# PDNode-600_Pro.net
KiCad netlist of a schematic drawn in EAGLE
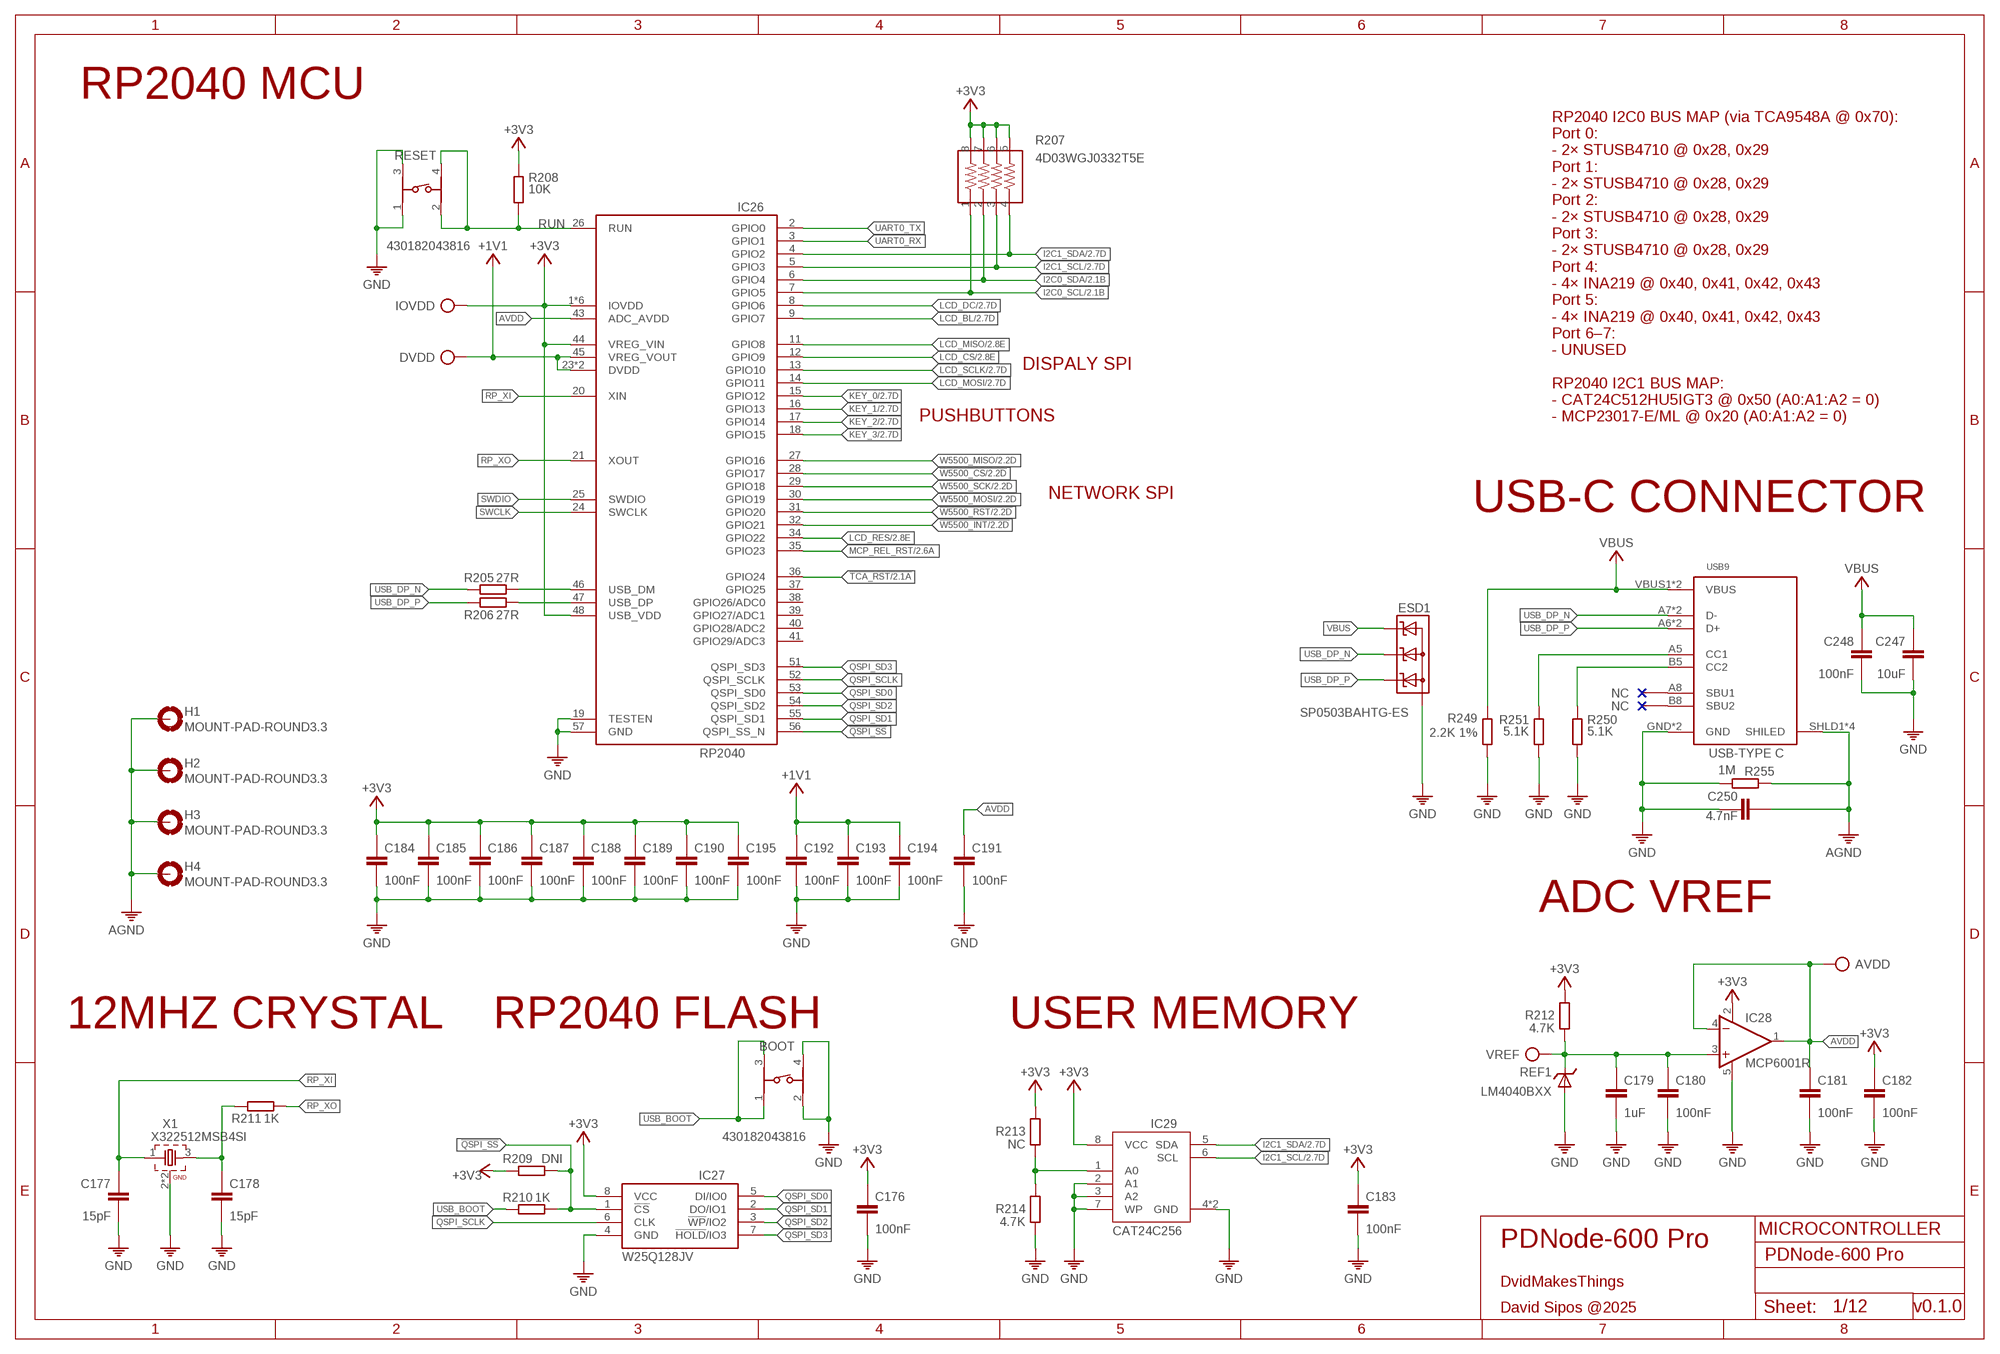
[diagram p0: schematic, sheet 1]
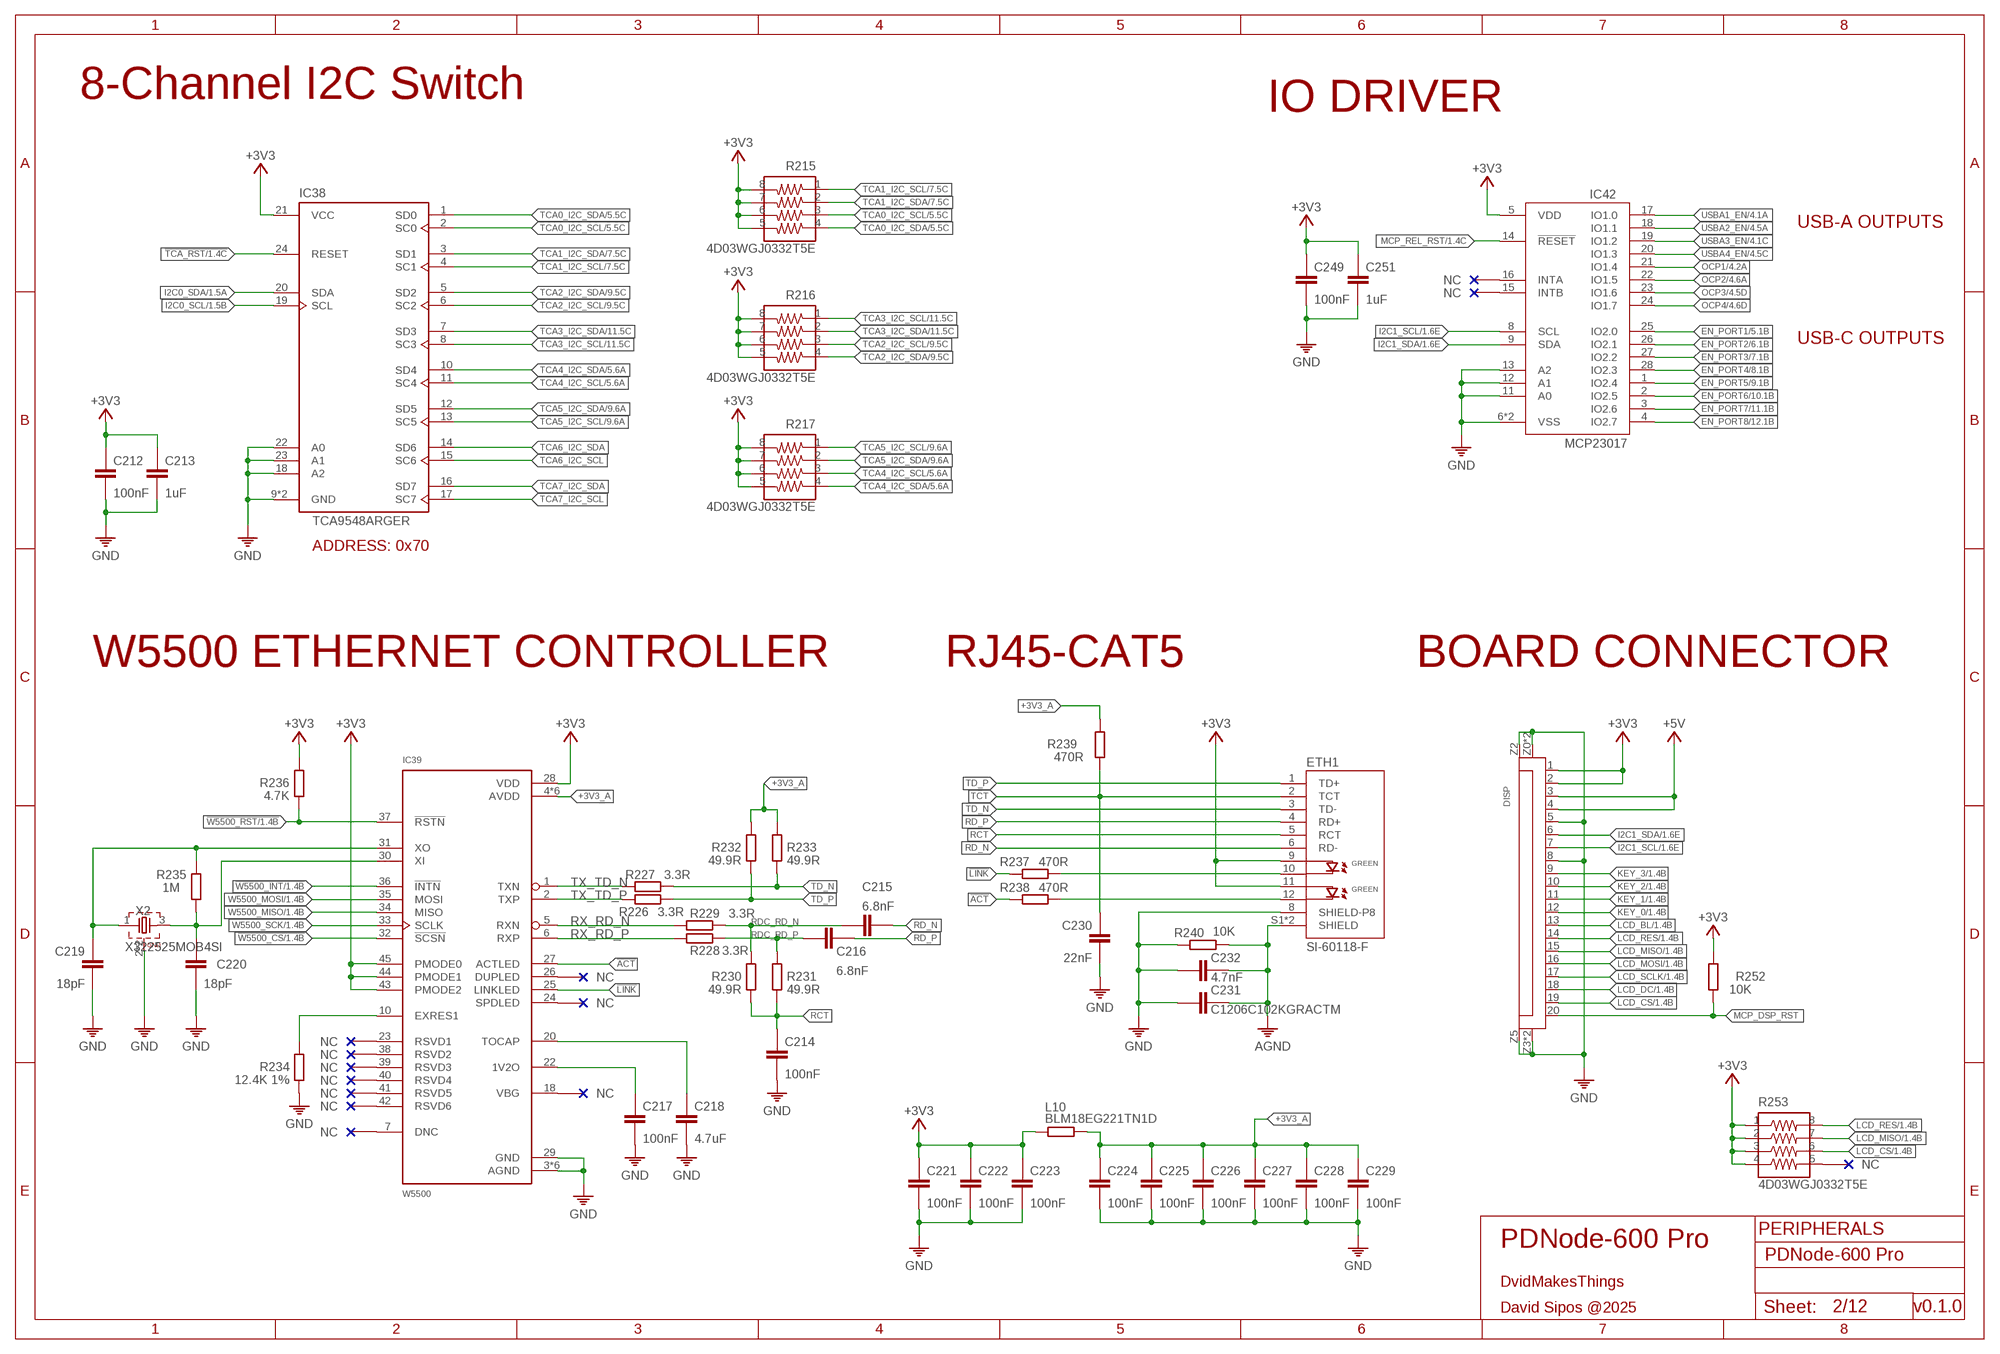
[diagram p1: schematic, sheet 2]
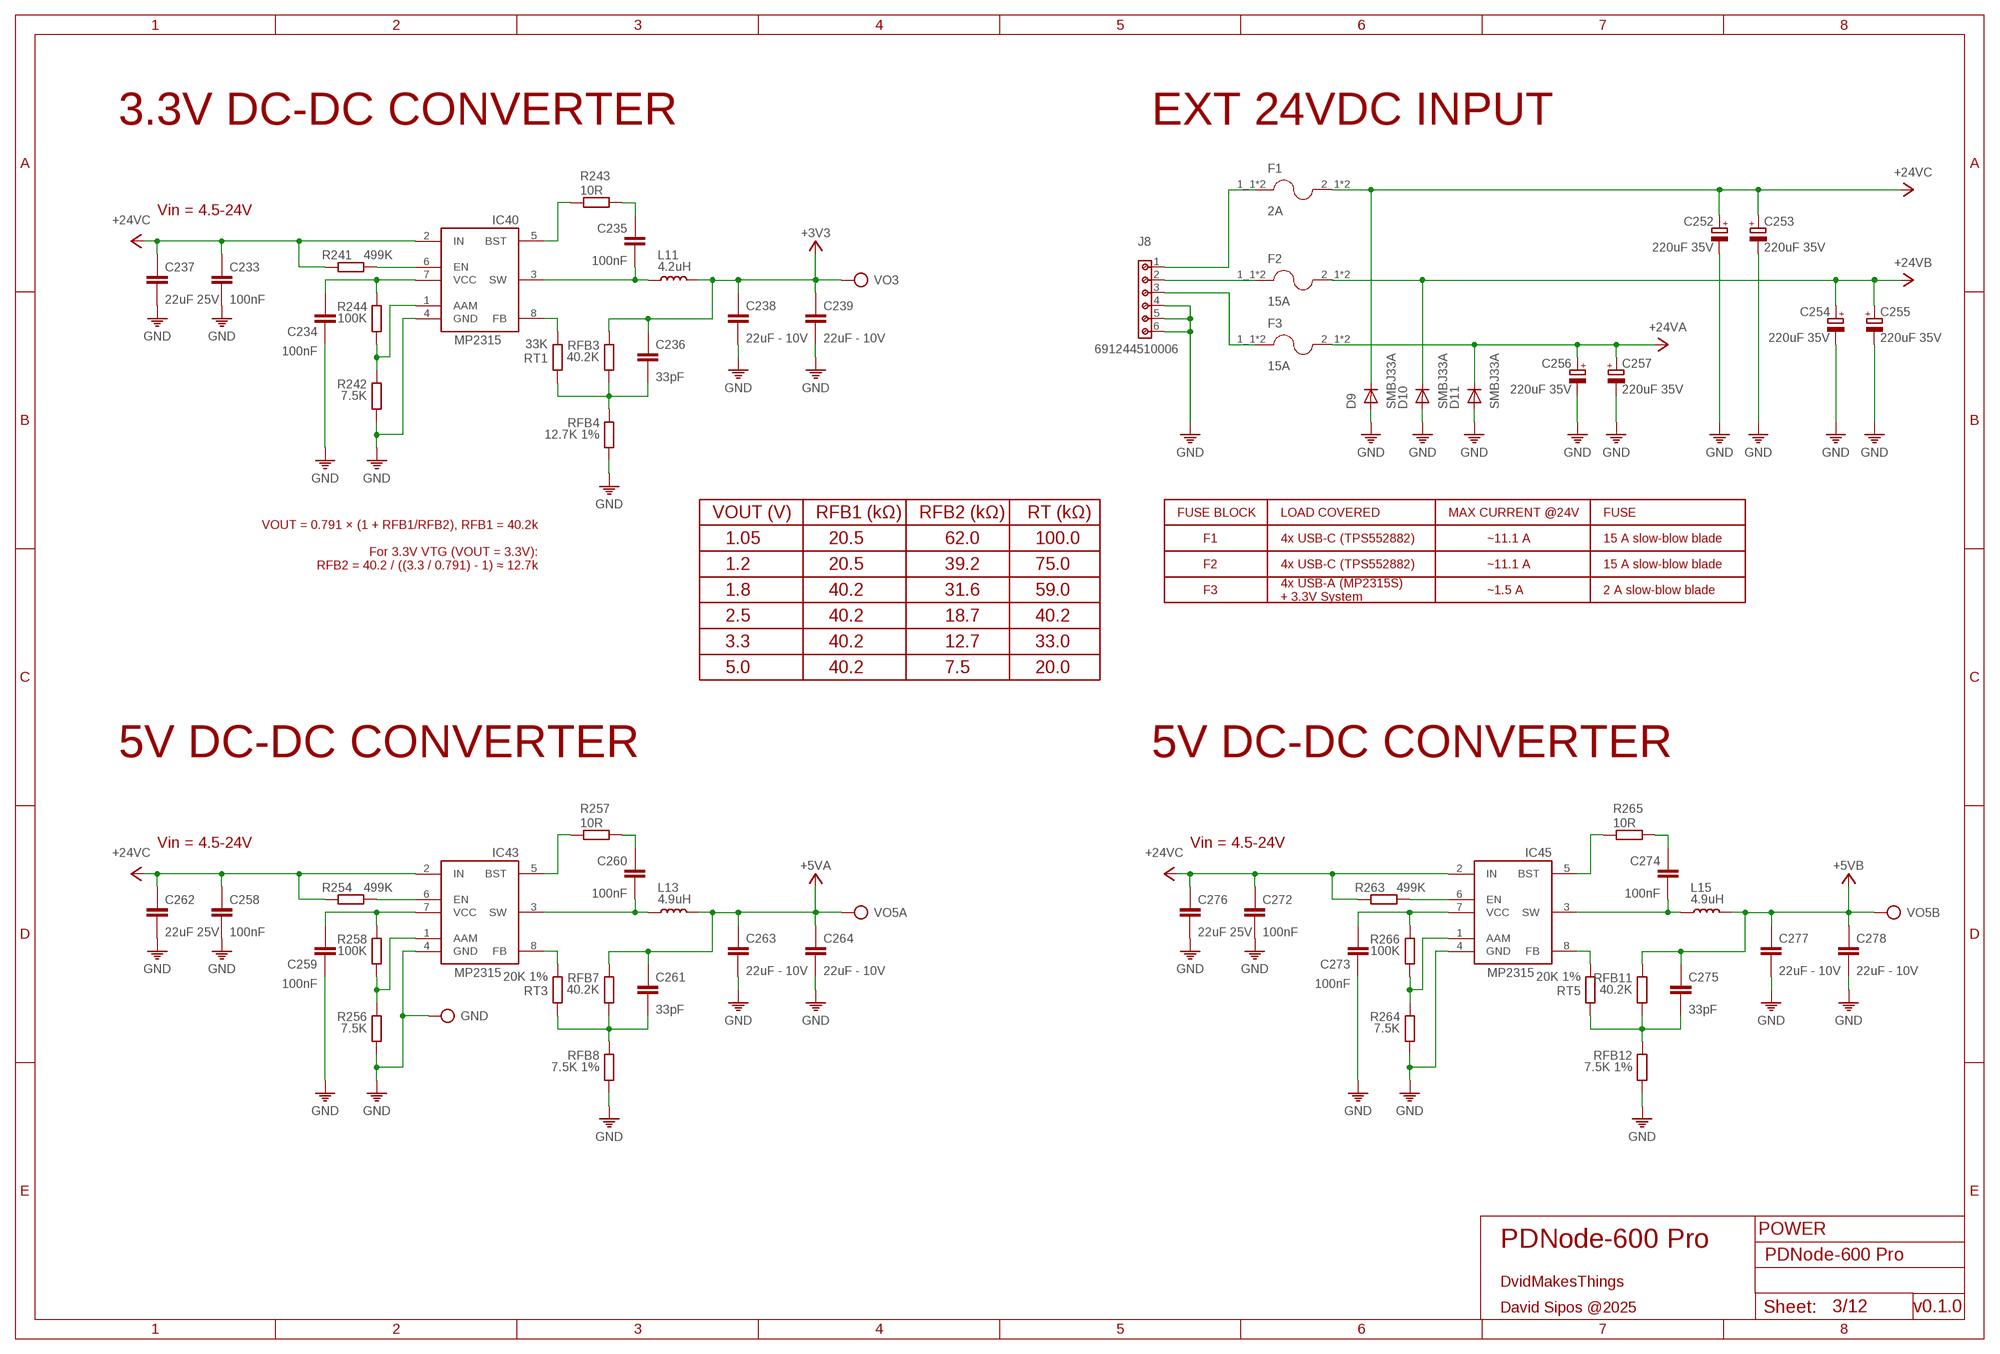
[diagram p2: schematic, sheet 3]
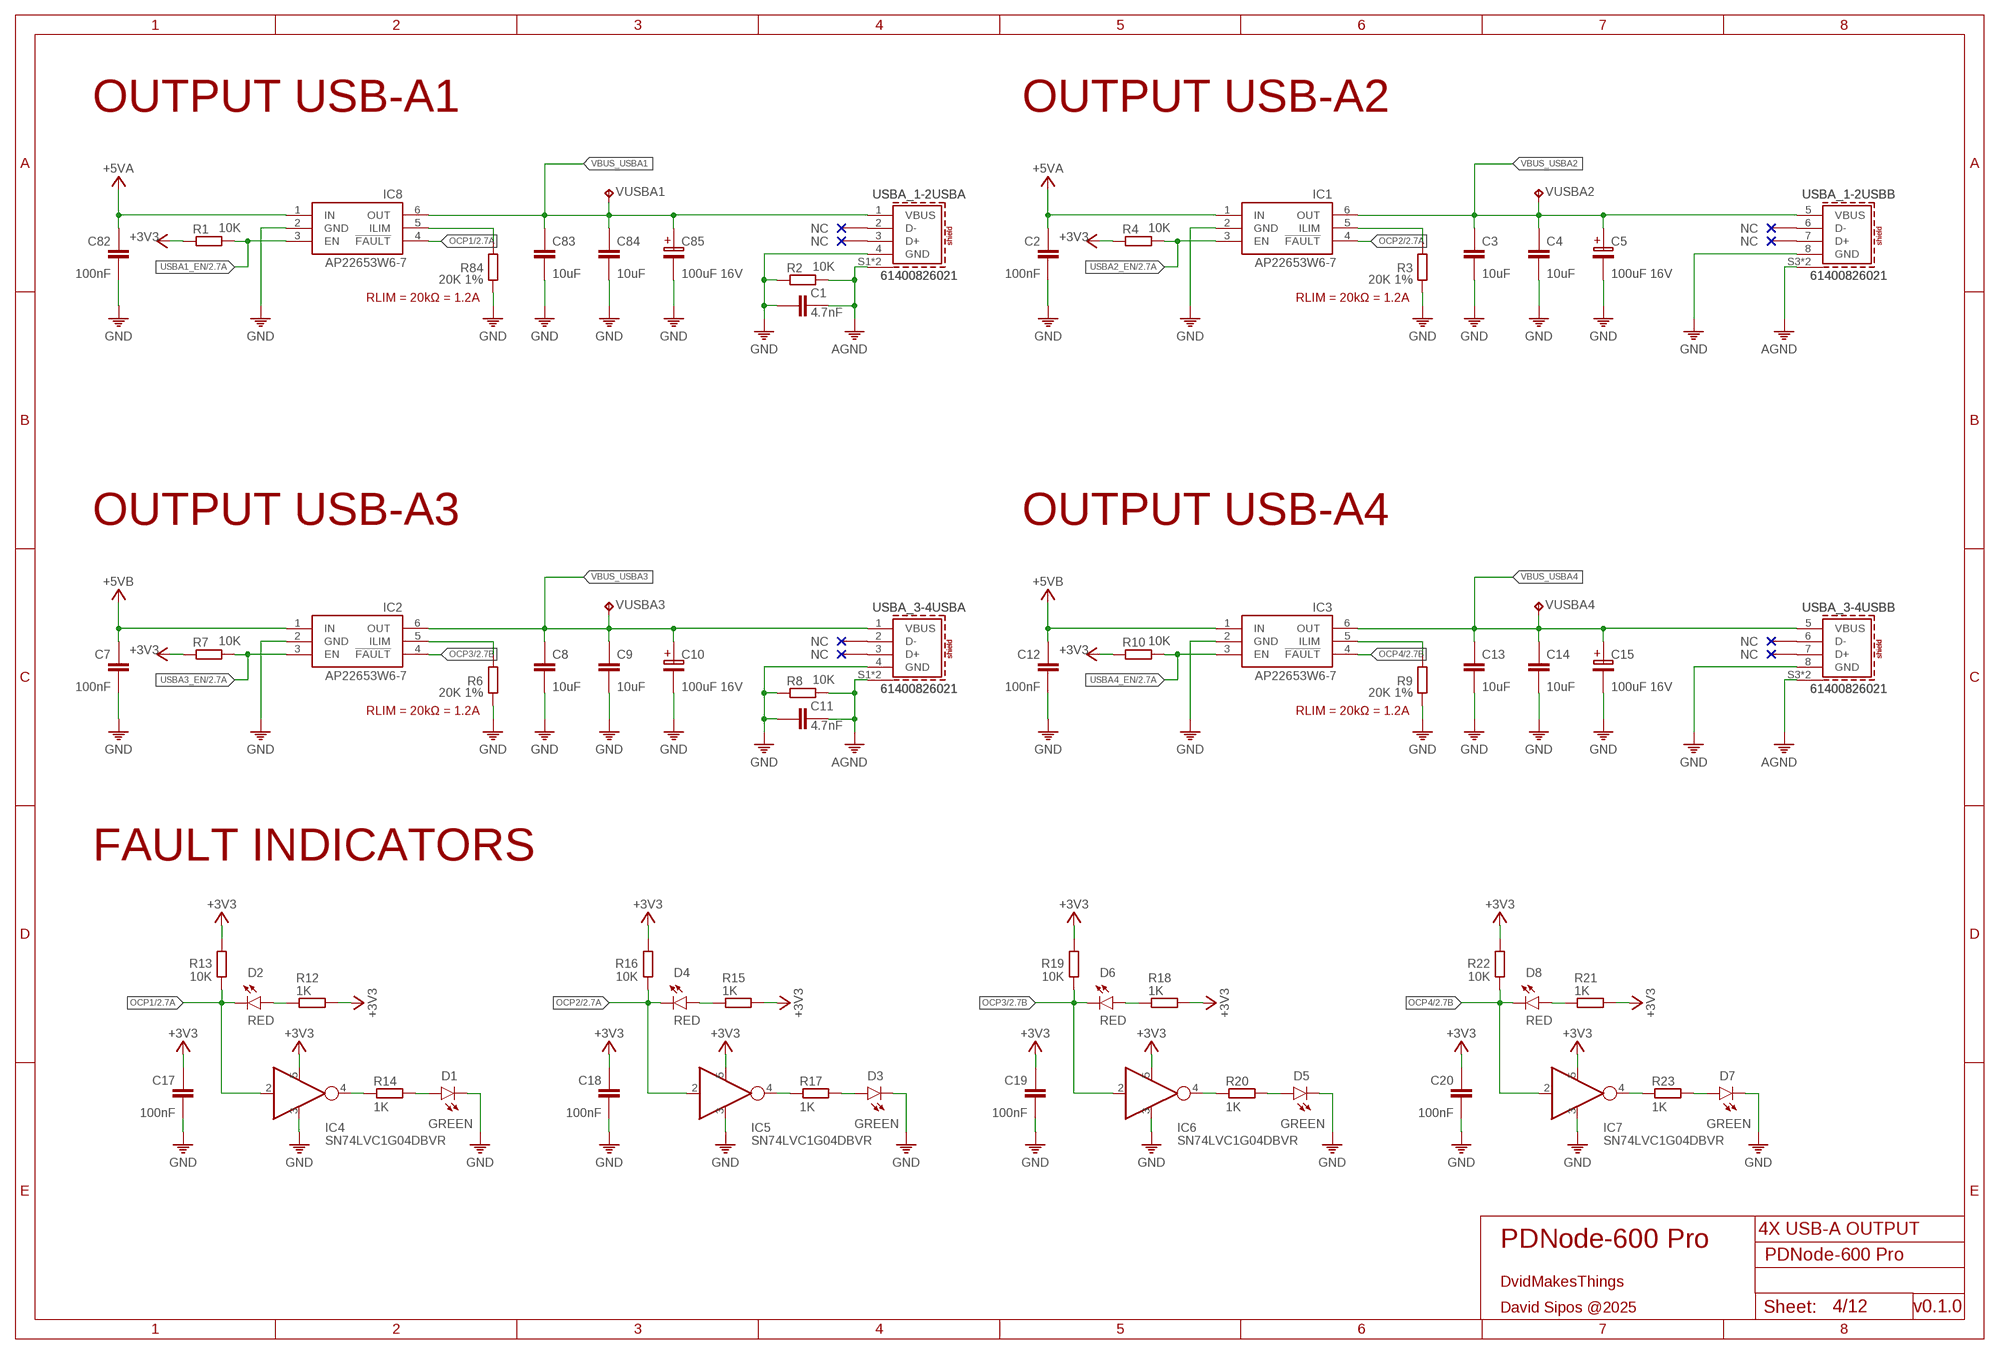
[diagram p3: schematic, sheet 4]
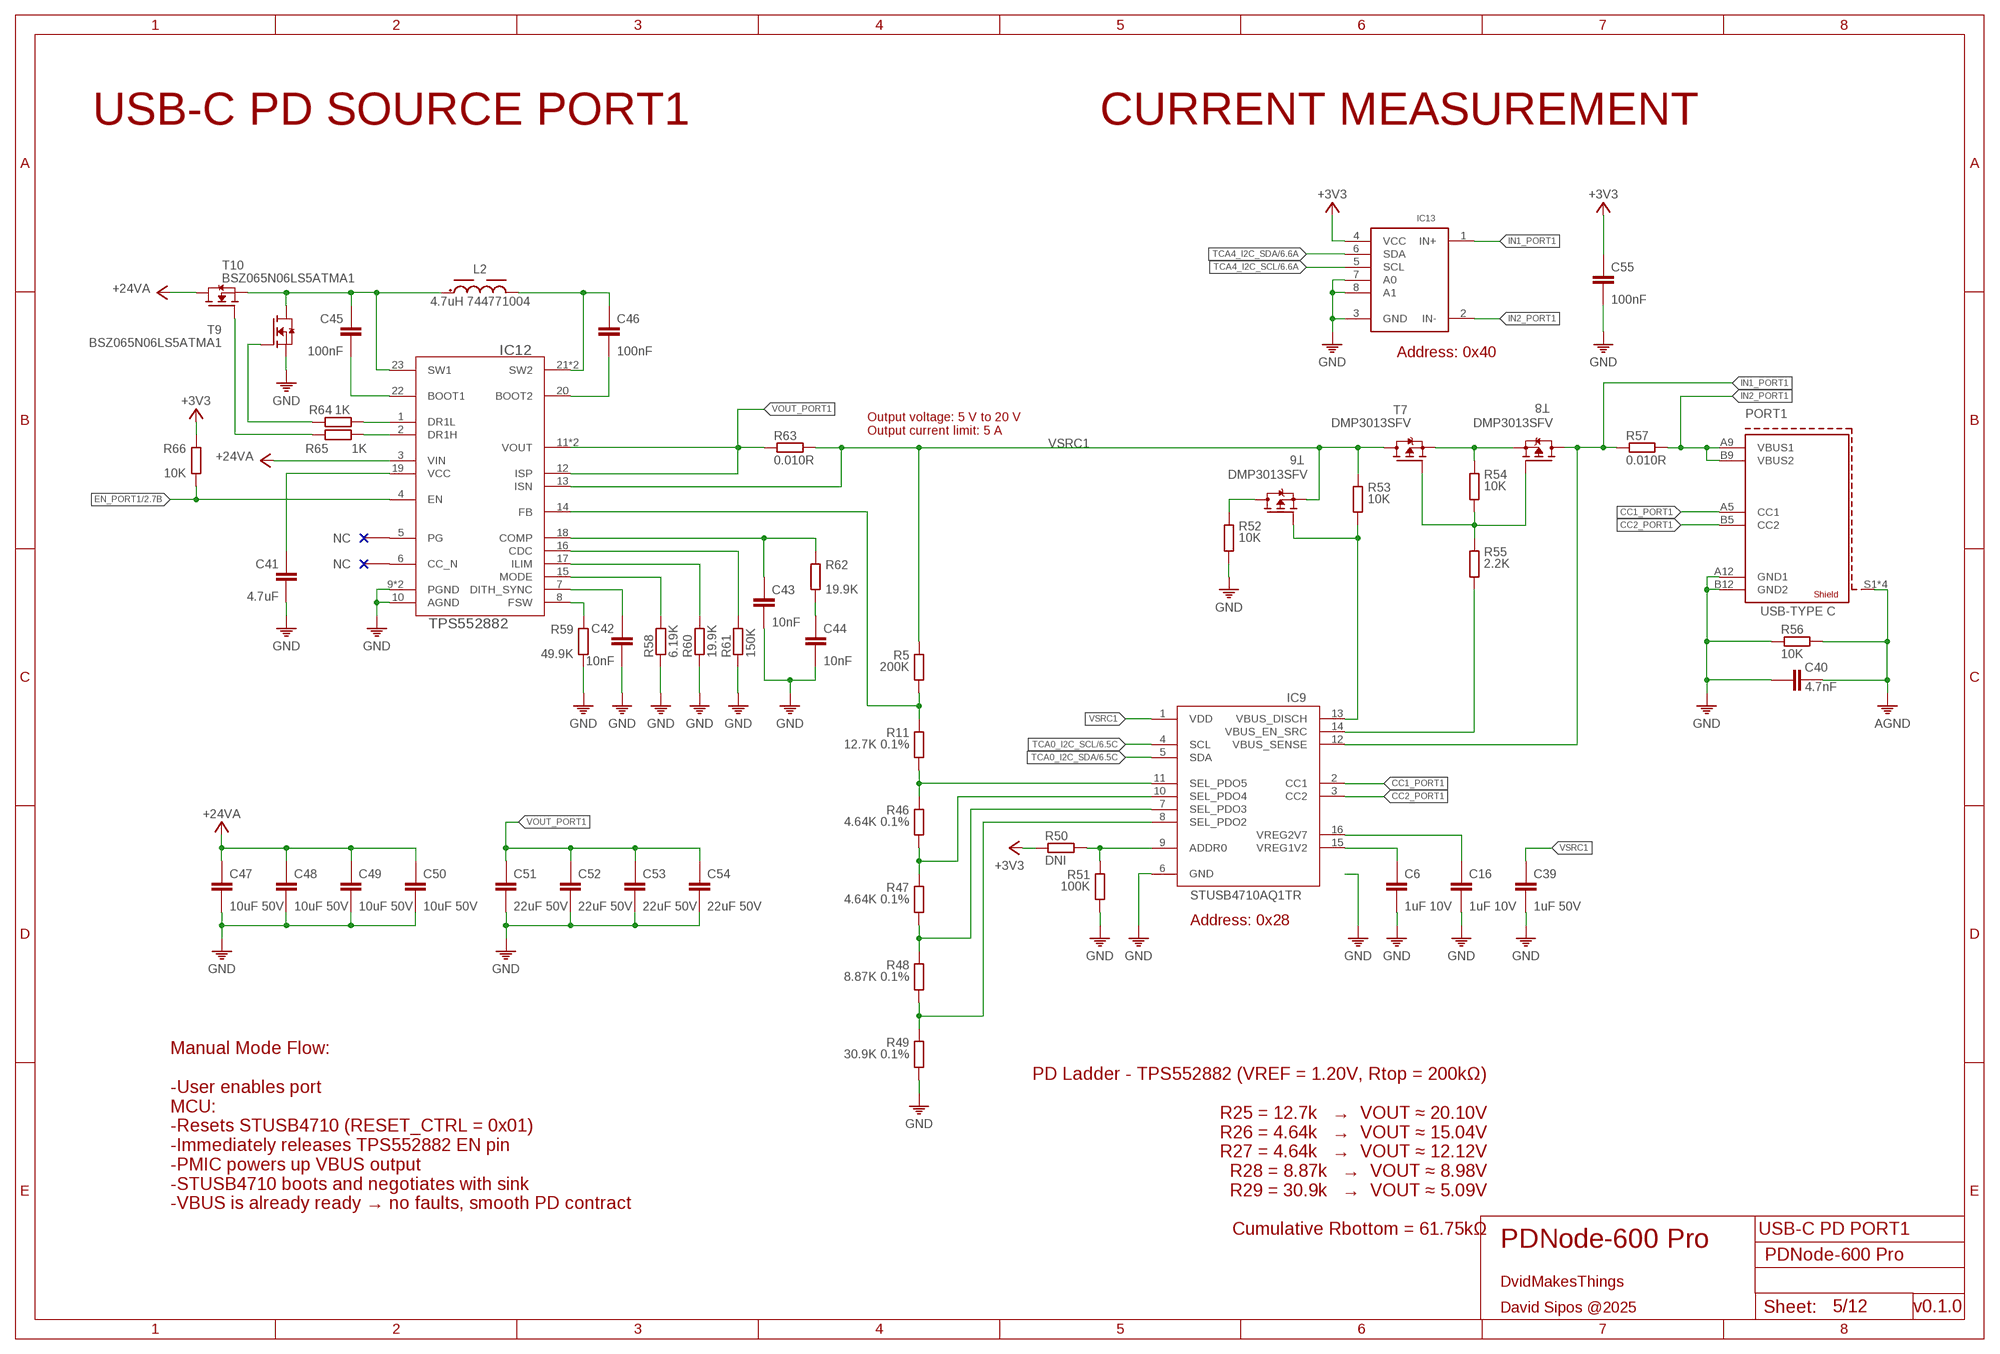
[diagram p4: schematic, sheet 5]
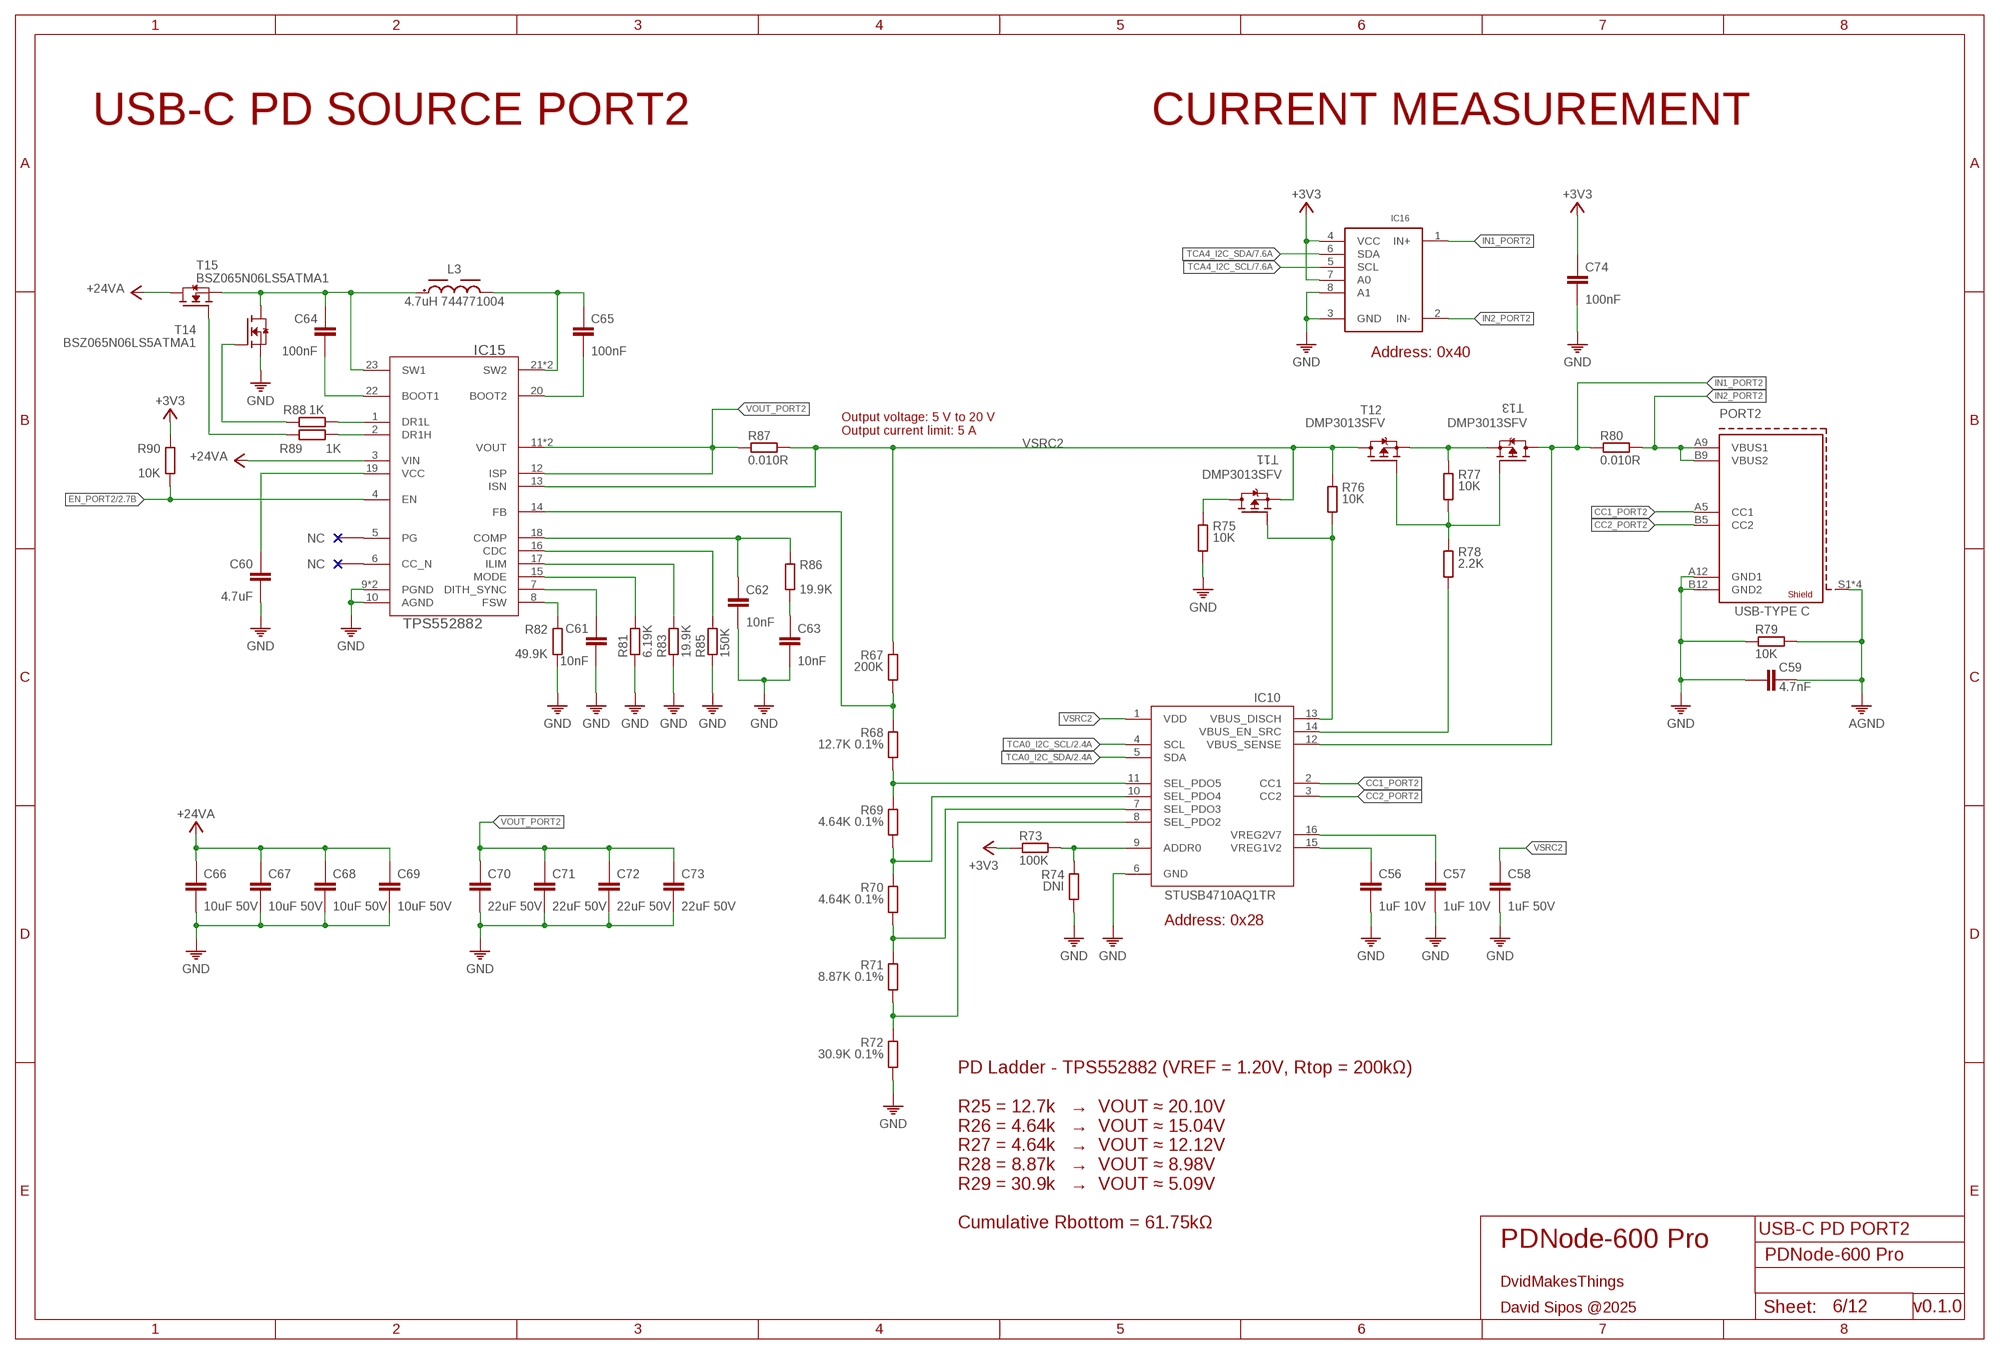
[diagram p5: schematic, sheet 6]
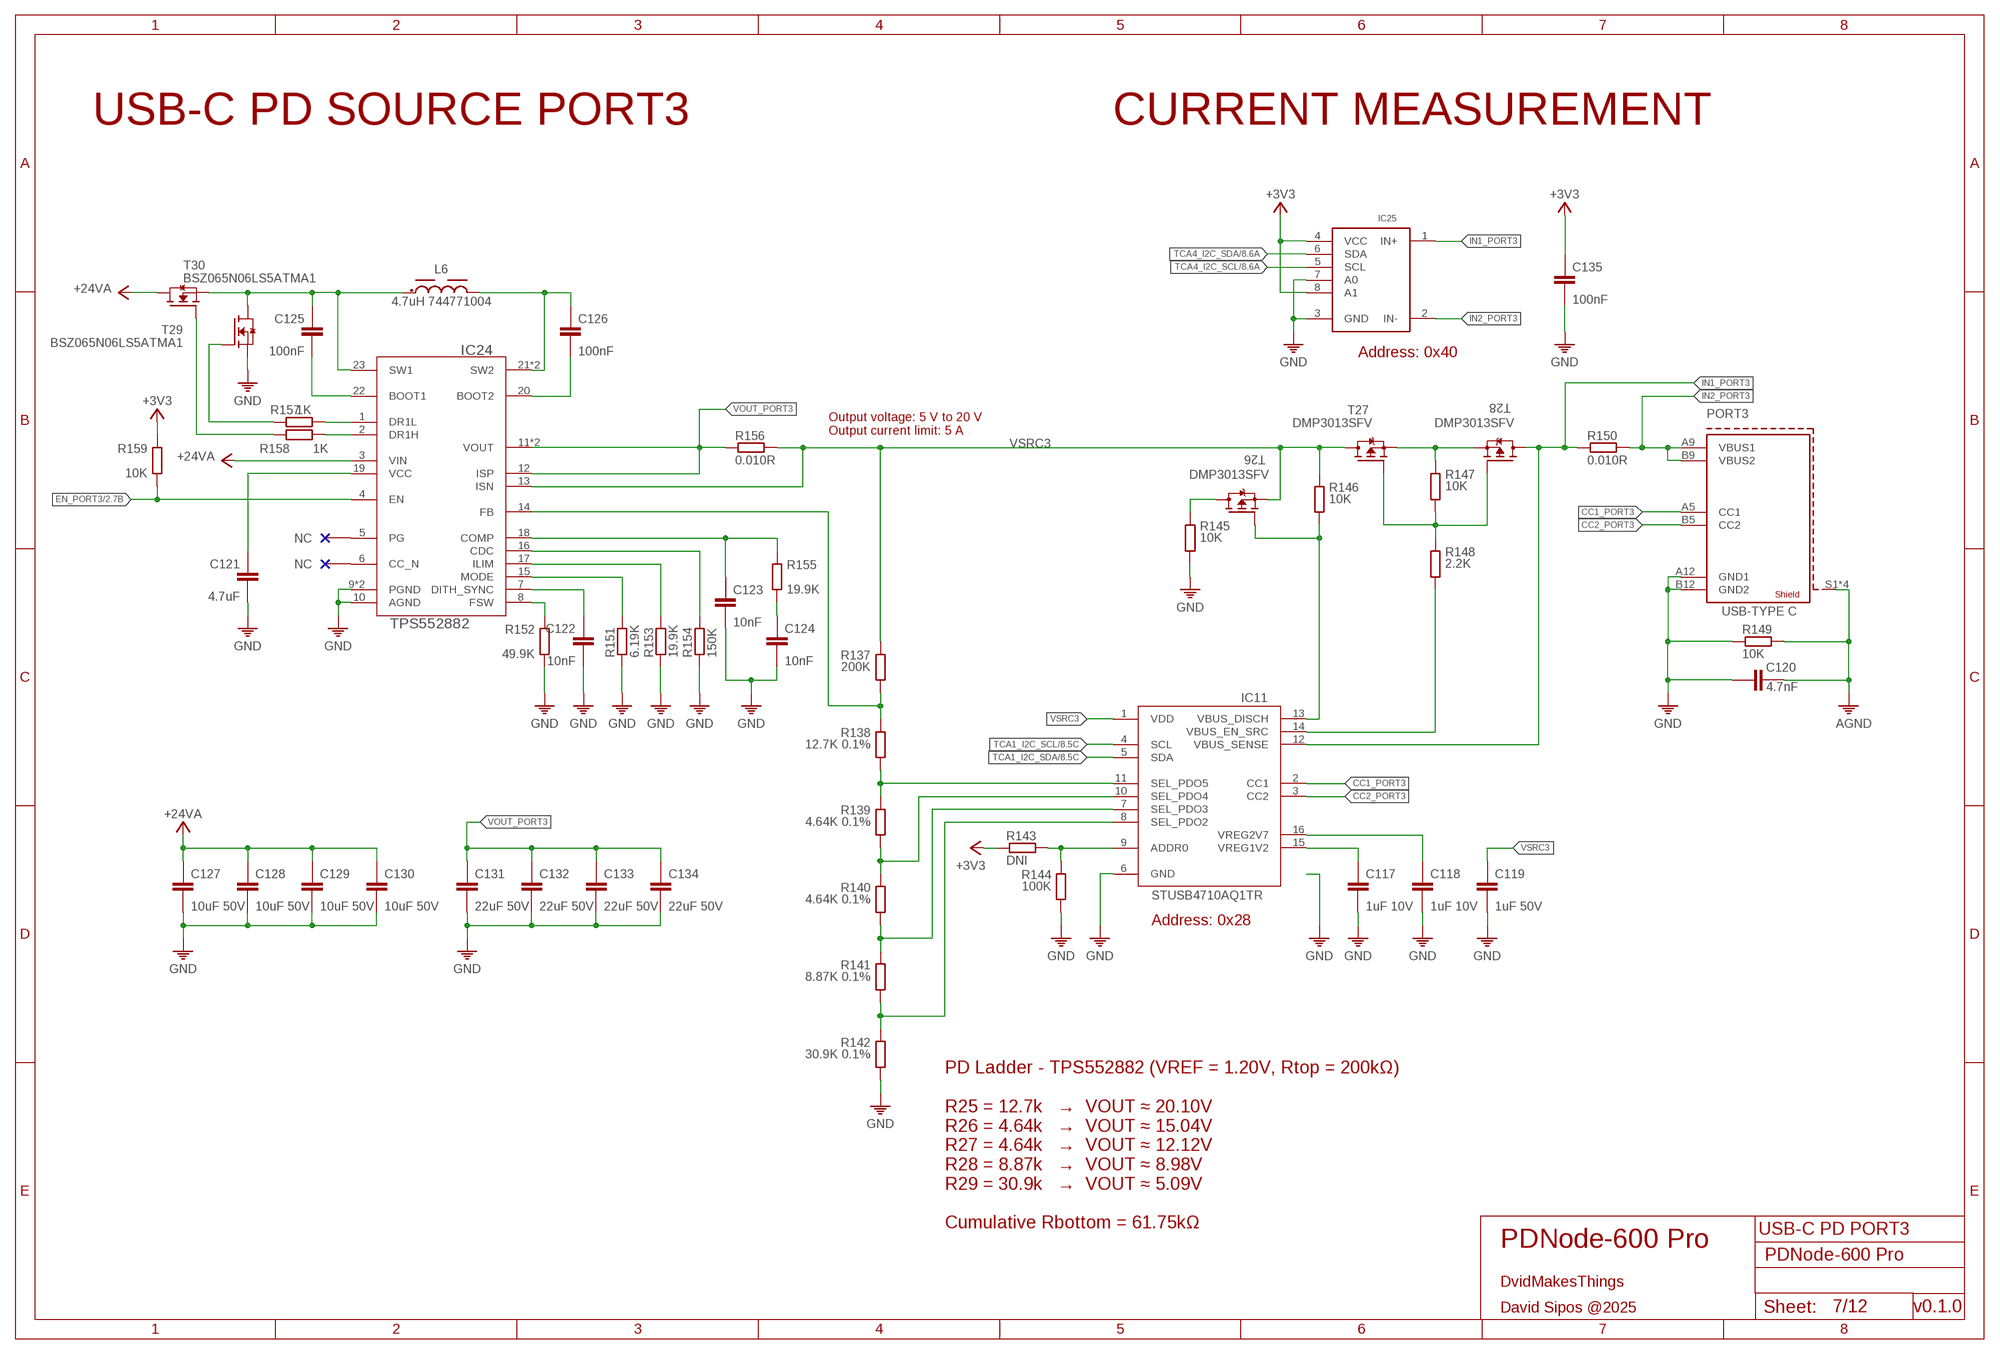
[diagram p6: schematic, sheet 7]
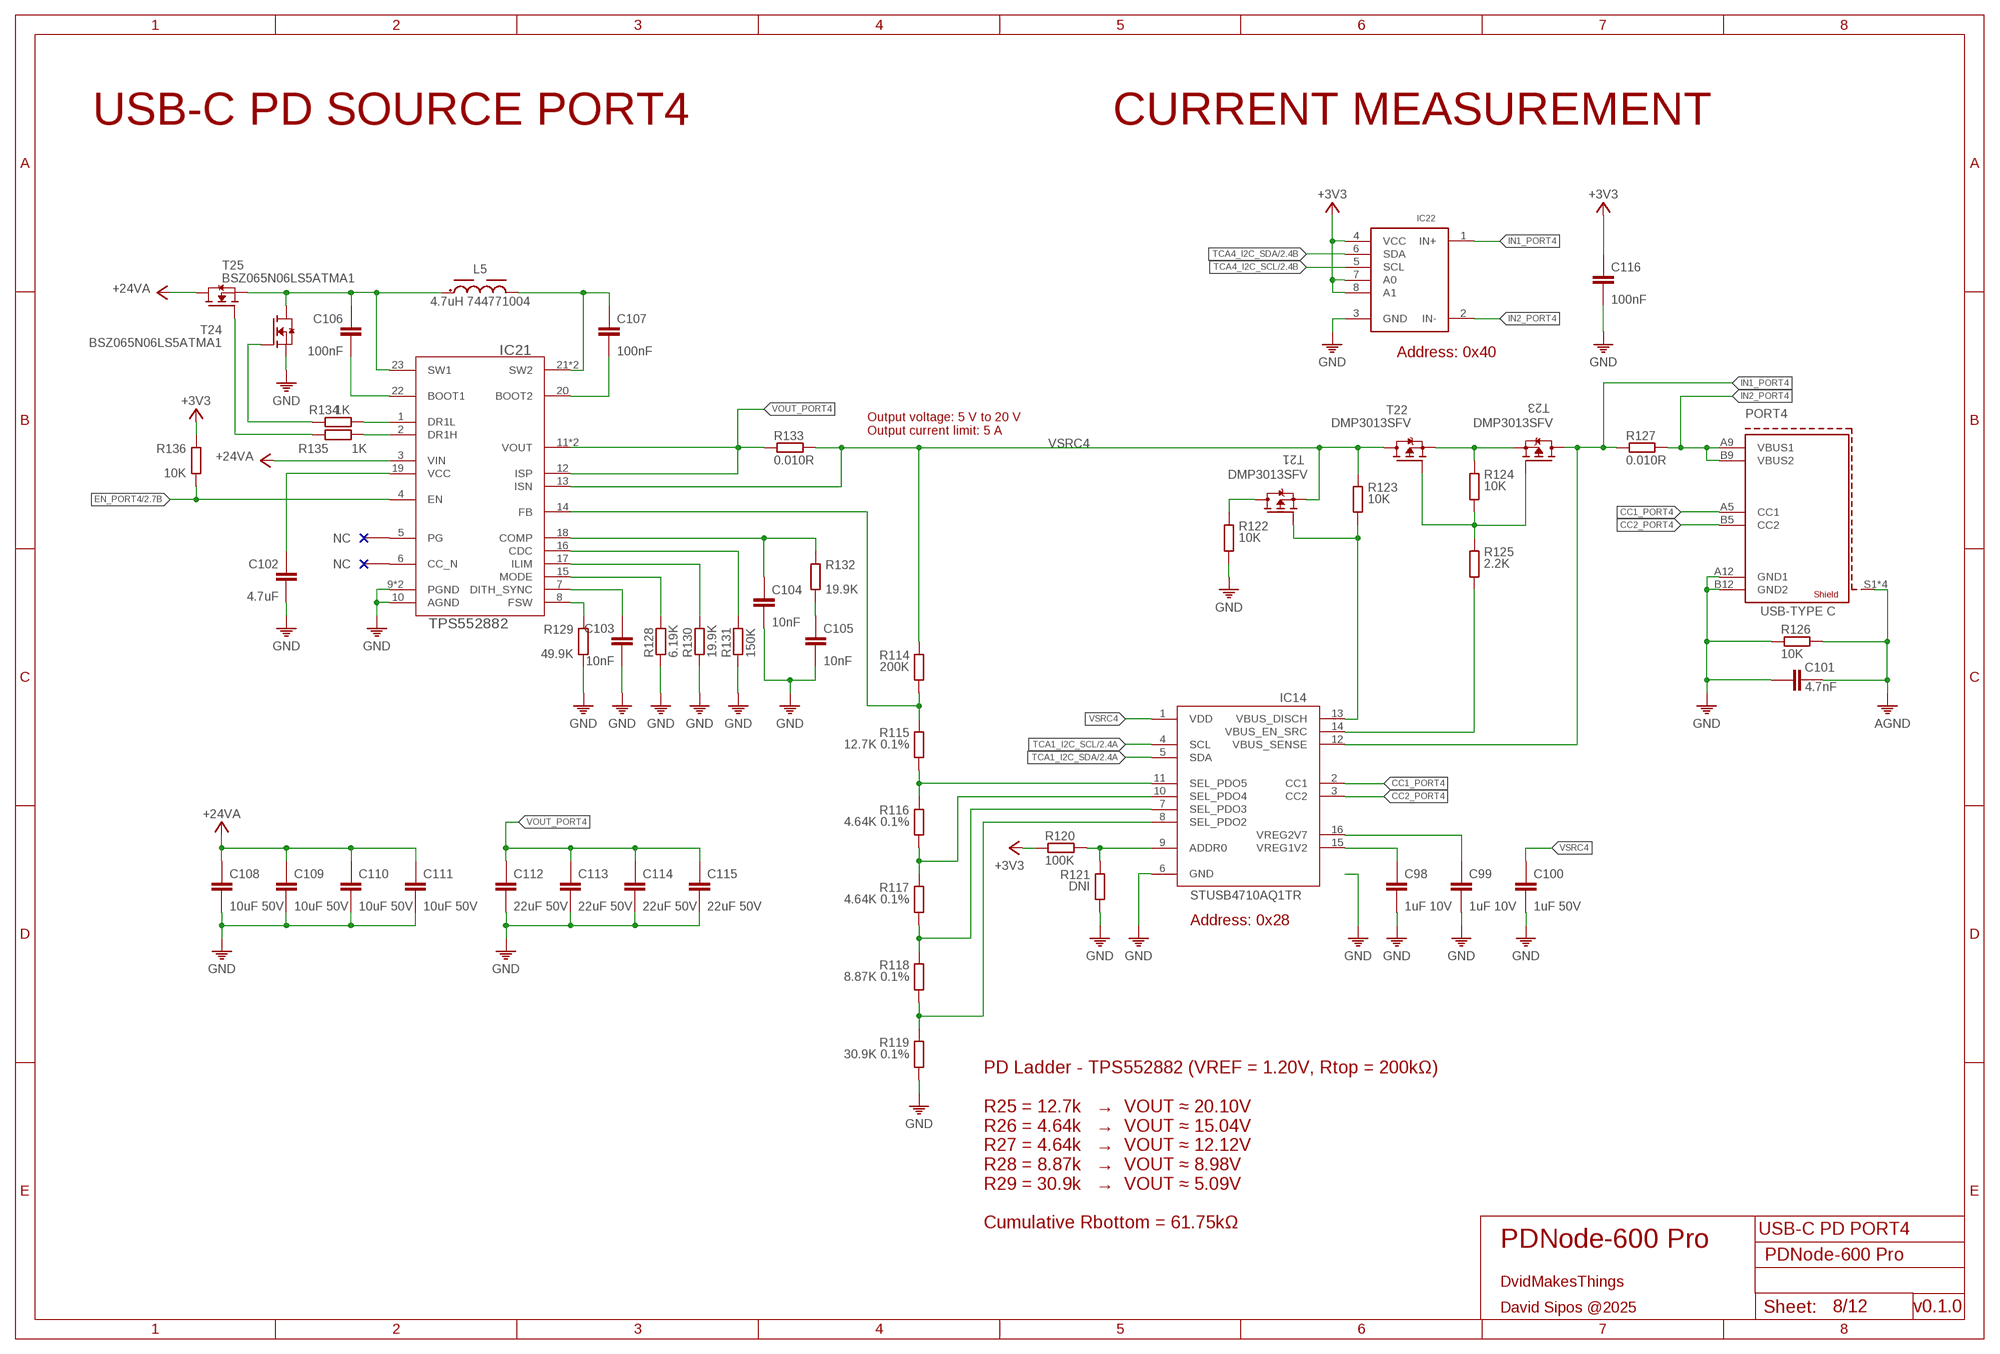
[diagram p7: schematic, sheet 8]
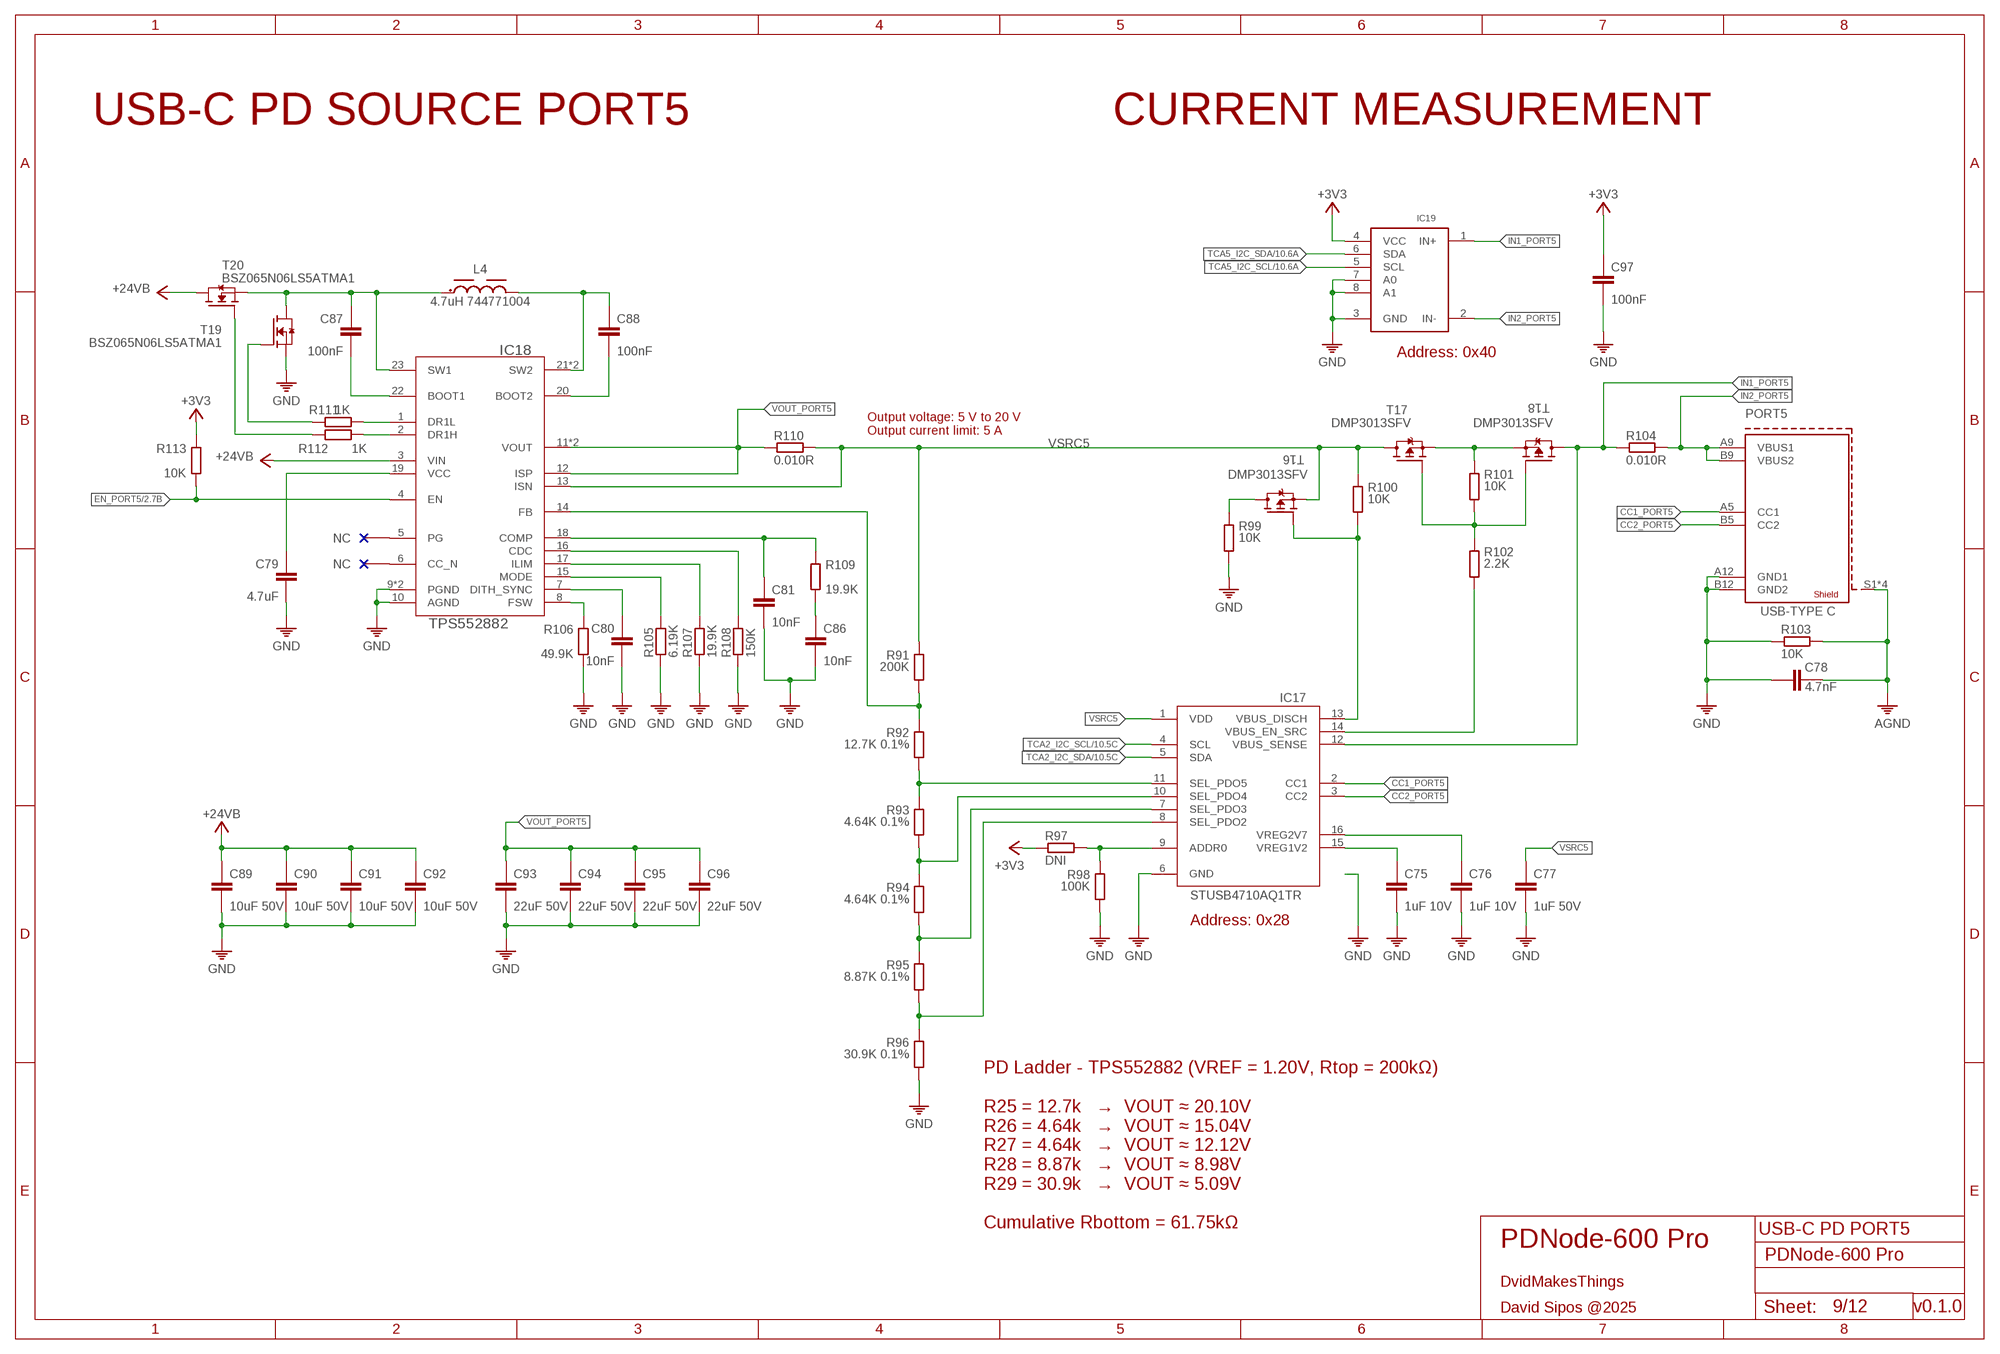
[diagram p8: schematic, sheet 9]
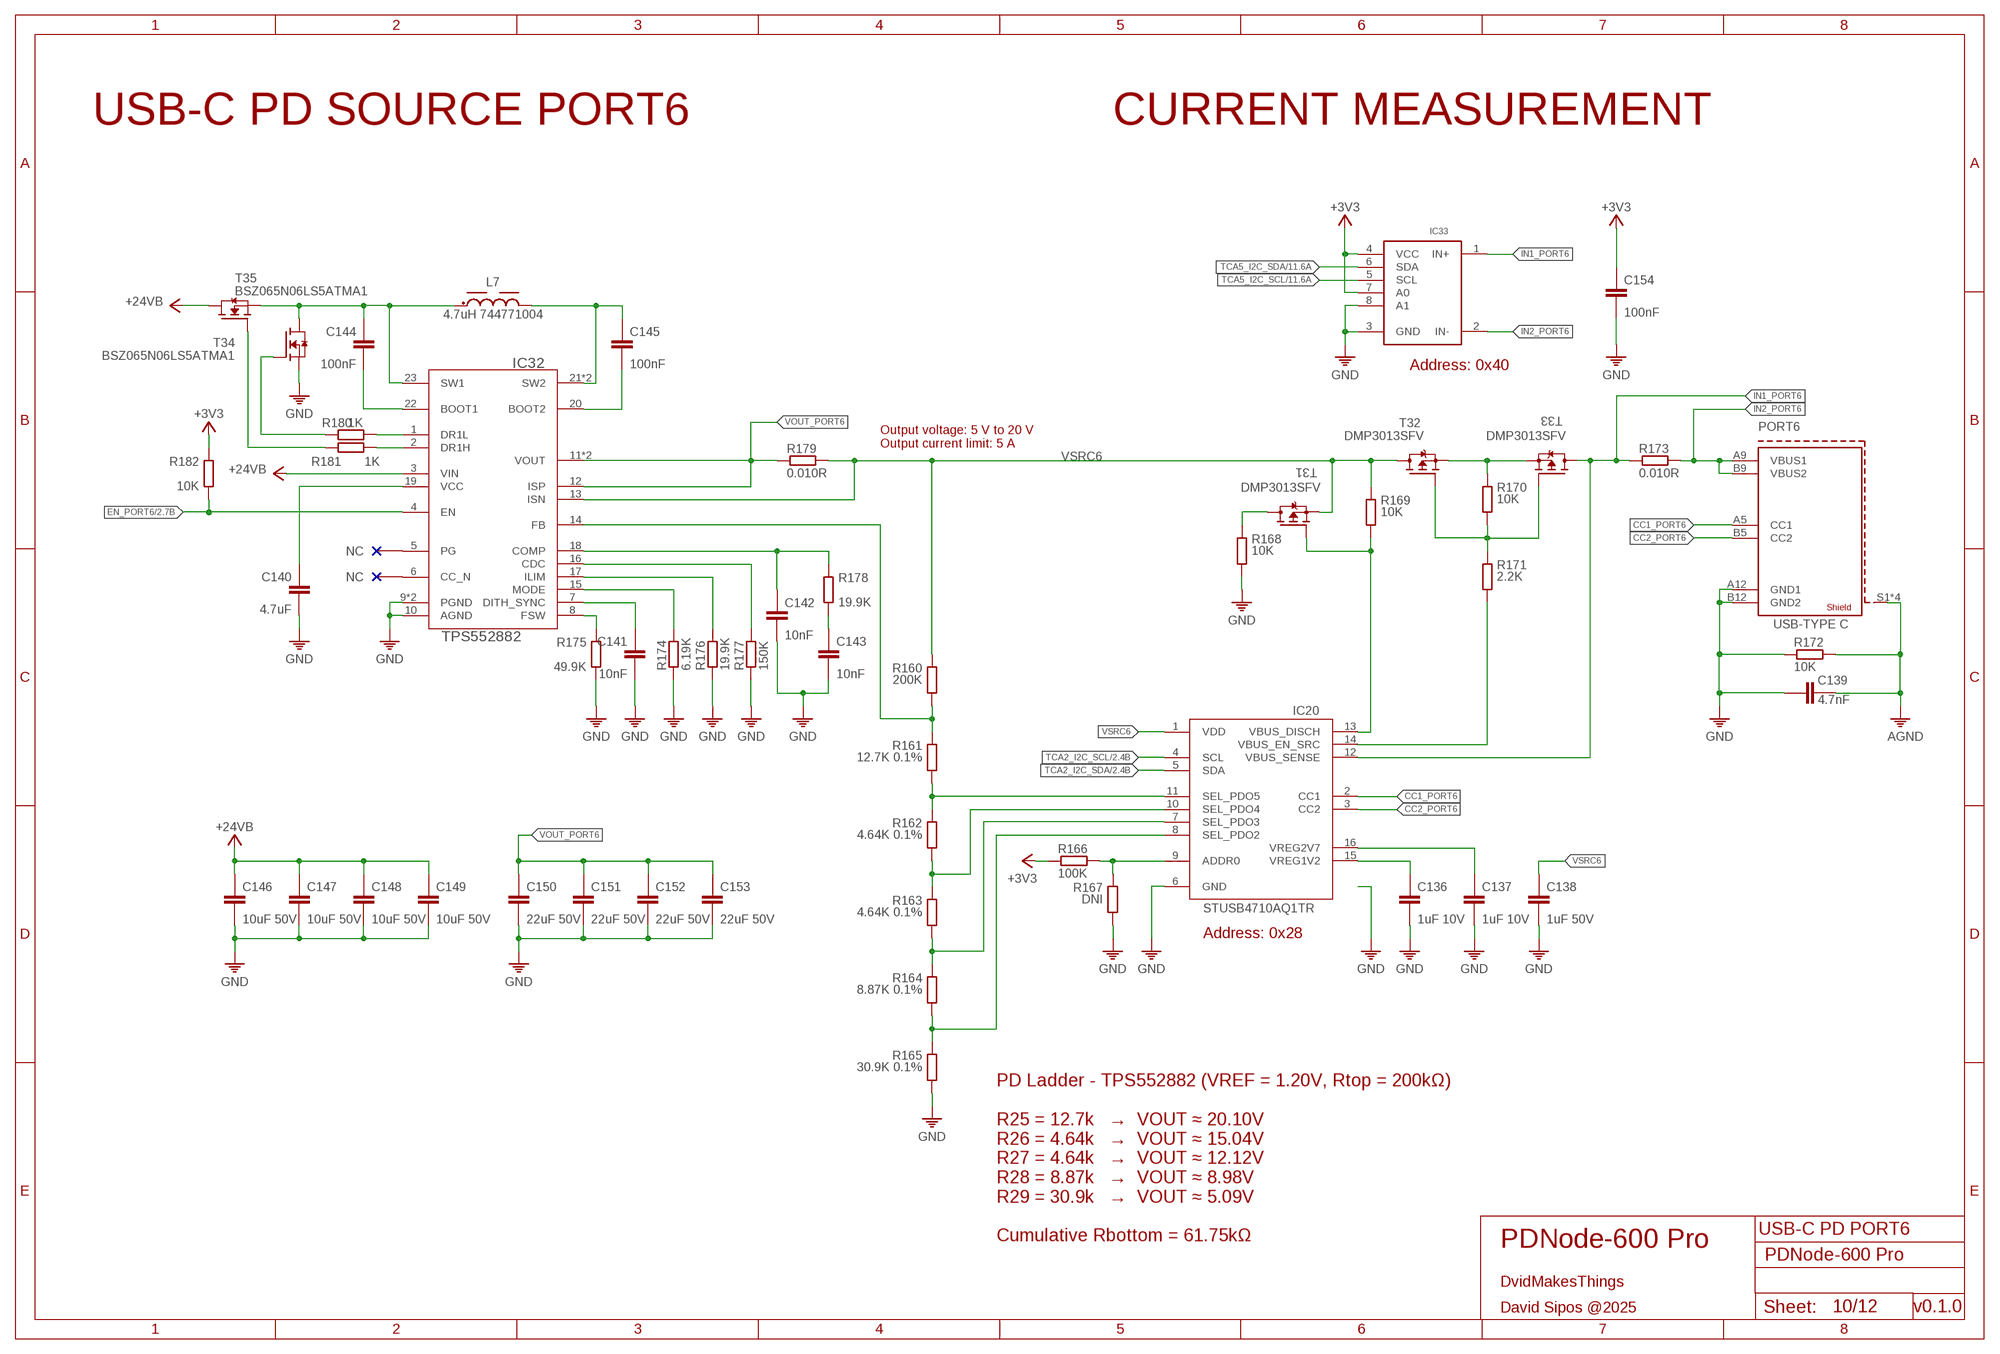
[diagram p9: schematic, sheet 10]
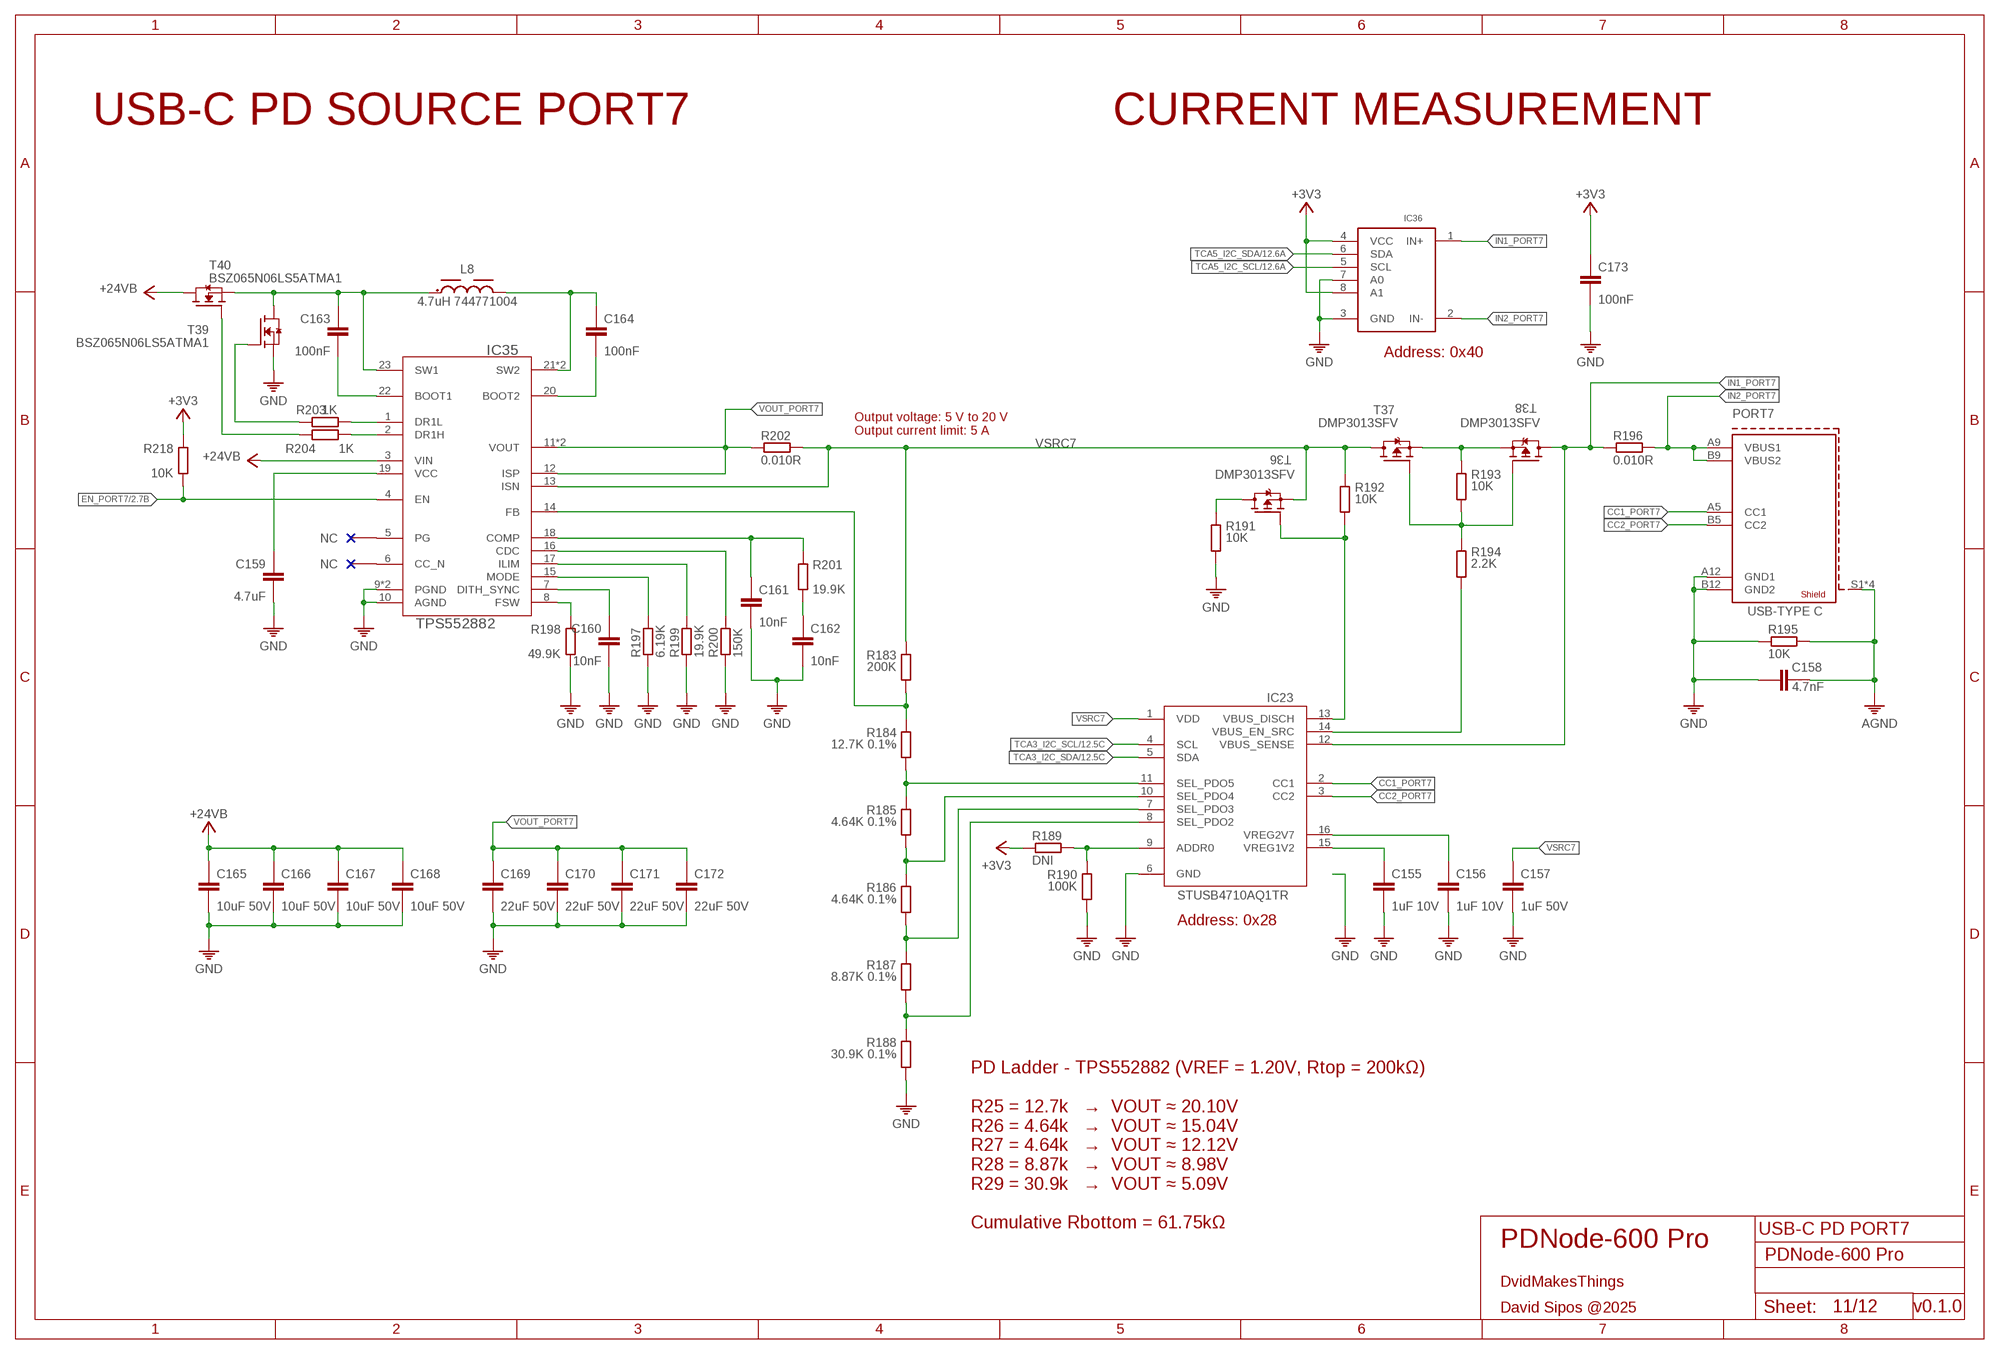
[diagram p10: schematic, sheet 11]
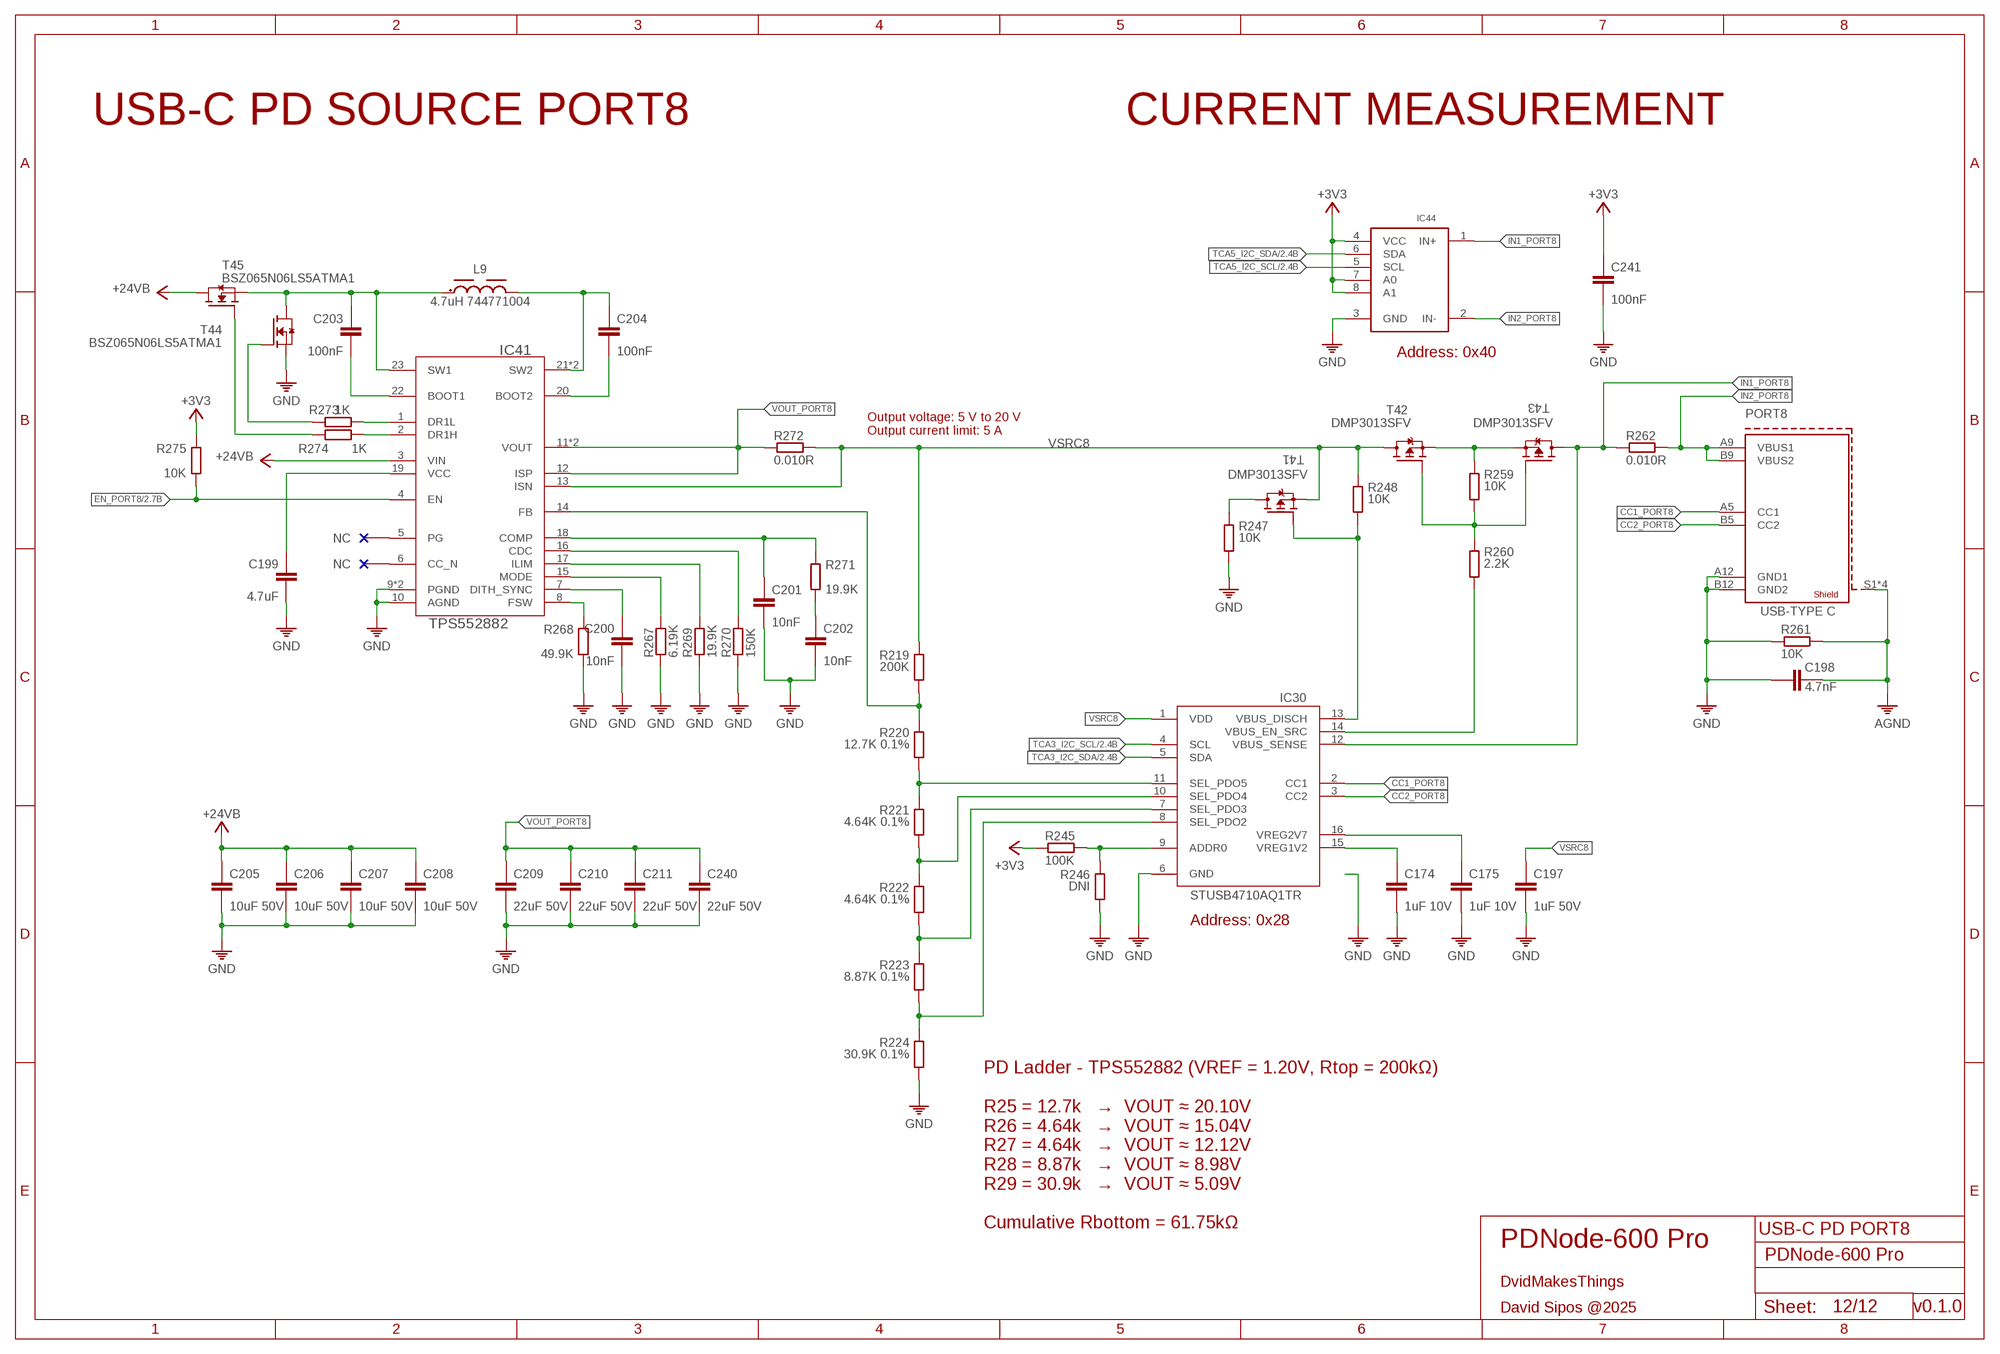
[diagram p11: schematic, sheet 12]

(export (version "E")
  (design (tool "Eeschema 10.0.6"))
  (components
    (comp (ref "AVDD")
      (value "TP")
      (footprint "eagle-import:TP")
      (libsource (lib "eagle-import") (part "TP"))
    )
    (comp (ref "BOOT")
      (value "430182043816")
      (footprint "eagle-import:430182050816")
      (libsource (lib "eagle-import") (part "430182050816"))
    )
    (comp (ref "C176")
      (value "100nF")
      (footprint "eagle-import:0201")
      (libsource (lib "eagle-import") (part "C-0201"))
    )
    (comp (ref "C177")
      (value "15pF")
      (footprint "eagle-import:0201")
      (libsource (lib "eagle-import") (part "C-0201"))
    )
    (comp (ref "C178")
      (value "15pF")
      (footprint "eagle-import:0201")
      (libsource (lib "eagle-import") (part "C-0201"))
    )
    (comp (ref "C179")
      (value "1uF")
      (footprint "eagle-import:C0402")
      (libsource (lib "eagle-import") (part "C-0402"))
    )
    (comp (ref "C180")
      (value "100nF")
      (footprint "eagle-import:0201")
      (libsource (lib "eagle-import") (part "C-0201"))
    )
    (comp (ref "C181")
      (value "100nF")
      (footprint "eagle-import:0201")
      (libsource (lib "eagle-import") (part "C-0201"))
    )
    (comp (ref "C182")
      (value "100nF")
      (footprint "eagle-import:0201")
      (libsource (lib "eagle-import") (part "C-0201"))
    )
    (comp (ref "C183")
      (value "100nF")
      (footprint "eagle-import:0201")
      (libsource (lib "eagle-import") (part "C-0201"))
    )
    (comp (ref "C184")
      (value "100nF")
      (footprint "eagle-import:0201")
      (libsource (lib "eagle-import") (part "C-0201"))
    )
    (comp (ref "C185")
      (value "100nF")
      (footprint "eagle-import:0201")
      (libsource (lib "eagle-import") (part "C-0201"))
    )
    (comp (ref "C186")
      (value "100nF")
      (footprint "eagle-import:0201")
      (libsource (lib "eagle-import") (part "C-0201"))
    )
    (comp (ref "C187")
      (value "100nF")
      (footprint "eagle-import:0201")
      (libsource (lib "eagle-import") (part "C-0201"))
    )
    (comp (ref "C188")
      (value "100nF")
      (footprint "eagle-import:0201")
      (libsource (lib "eagle-import") (part "C-0201"))
    )
    (comp (ref "C189")
      (value "100nF")
      (footprint "eagle-import:0201")
      (libsource (lib "eagle-import") (part "C-0201"))
    )
    (comp (ref "C190")
      (value "100nF")
      (footprint "eagle-import:0201")
      (libsource (lib "eagle-import") (part "C-0201"))
    )
    (comp (ref "C191")
      (value "100nF")
      (footprint "eagle-import:0201")
      (libsource (lib "eagle-import") (part "C-0201"))
    )
    (comp (ref "C192")
      (value "100nF")
      (footprint "eagle-import:0201")
      (libsource (lib "eagle-import") (part "C-0201"))
    )
    (comp (ref "C193")
      (value "100nF")
      (footprint "eagle-import:0201")
      (libsource (lib "eagle-import") (part "C-0201"))
    )
    (comp (ref "C194")
      (value "100nF")
      (footprint "eagle-import:0201")
      (libsource (lib "eagle-import") (part "C-0201"))
    )
    (comp (ref "C195")
      (value "100nF")
      (footprint "eagle-import:0201")
      (libsource (lib "eagle-import") (part "C-0201"))
    )
    (comp (ref "C247")
      (value "10uF")
      (footprint "eagle-import:0805")
      (libsource (lib "eagle-import") (part "C0805"))
    )
    (comp (ref "C248")
      (value "100nF")
      (footprint "eagle-import:0402")
      (libsource (lib "eagle-import") (part "C0402"))
    )
    (comp (ref "C250")
      (value "4.7nF")
      (footprint "eagle-import:C0402")
      (libsource (lib "eagle-import") (part "C-0402"))
    )
    (comp (ref "DVDD")
      (value "TP")
      (footprint "eagle-import:TP")
      (libsource (lib "eagle-import") (part "TP"))
    )
    (comp (ref "ESD1")
      (value "SP0503BAHTG-ES")
      (footprint "eagle-import:SOT143")
      (libsource (lib "eagle-import") (part "SP0503BAHT"))
    )
    (comp (ref "H1")
      (value "MOUNT-PAD-ROUND3.3")
      (footprint "eagle-import:3,3-PAD")
      (libsource (lib "eagle-import") (part "MOUNT-PAD-ROUND3.3"))
    )
    (comp (ref "H2")
      (value "MOUNT-PAD-ROUND3.3")
      (footprint "eagle-import:3,3-PAD")
      (libsource (lib "eagle-import") (part "MOUNT-PAD-ROUND3.3"))
    )
    (comp (ref "H3")
      (value "MOUNT-PAD-ROUND3.3")
      (footprint "eagle-import:3,3-PAD")
      (libsource (lib "eagle-import") (part "MOUNT-PAD-ROUND3.3"))
    )
    (comp (ref "H4")
      (value "MOUNT-PAD-ROUND3.3")
      (footprint "eagle-import:3,3-PAD")
      (libsource (lib "eagle-import") (part "MOUNT-PAD-ROUND3.3"))
    )
    (comp (ref "IC26")
      (value "RP2040")
      (footprint "eagle-import:QFN40P700X700X100-57T510")
      (libsource (lib "eagle-import") (part "RP2040"))
    )
    (comp (ref "IC27")
      (value "W25Q128JVPIQ")
      (footprint "eagle-import:SON127P600X500X75-8N")
      (libsource (lib "eagle-import") (part "W25Q128JVP"))
    )
    (comp (ref "IC28")
      (value "MCP6001R")
      (footprint "eagle-import:SOT23-5")
      (libsource (lib "eagle-import") (part "MCP6001RT"))
    )
    (comp (ref "IC29")
      (value "CAT24C512HU5IGT3")
      (footprint "eagle-import:SON50P300X200X50-9T130X140N")
      (libsource (lib "eagle-import") (part "CAT24C256-HU4"))
    )
    (comp (ref "IOVDD")
      (value "TP")
      (footprint "eagle-import:TP")
      (libsource (lib "eagle-import") (part "TP"))
    )
    (comp (ref "R205")
      (value "27R")
      (footprint "eagle-import:R0201")
      (libsource (lib "eagle-import") (part "R0201"))
    )
    (comp (ref "R206")
      (value "27R")
      (footprint "eagle-import:R0201")
      (libsource (lib "eagle-import") (part "R0201"))
    )
    (comp (ref "R207")
      (value "4D03WGJ0332T5E")
      (footprint "eagle-import:742C083103JP")
      (fields
        (field (name "MANUFACTURER") "CTS Resistor Products")
        (field (name "MPN") "742C083103JP")
        (field (name "CREATED_BY") "PCBLayout.com")
      )
      (libsource (lib "eagle-import") (part "742C083103JP"))
    )
    (comp (ref "R208")
      (value "10K")
      (footprint "eagle-import:R0201")
      (libsource (lib "eagle-import") (part "R0201"))
    )
    (comp (ref "R209")
      (value "DNI")
      (footprint "eagle-import:R0201")
      (libsource (lib "eagle-import") (part "R0201"))
    )
    (comp (ref "R210")
      (value "1K")
      (footprint "eagle-import:R0201")
      (libsource (lib "eagle-import") (part "R0201"))
    )
    (comp (ref "R211")
      (value "1K")
      (footprint "eagle-import:R0201")
      (libsource (lib "eagle-import") (part "R0201"))
    )
    (comp (ref "R212")
      (value "4.7K")
      (footprint "eagle-import:0402")
      (libsource (lib "eagle-import") (part "R0402"))
    )
    (comp (ref "R213")
      (value "NC")
      (footprint "eagle-import:R0201")
      (libsource (lib "eagle-import") (part "R0201"))
    )
    (comp (ref "R214")
      (value "4.7K")
      (footprint "eagle-import:R0201")
      (libsource (lib "eagle-import") (part "R0201"))
    )
    (comp (ref "R249")
      (value "2.2K 1%")
      (footprint "eagle-import:R0201")
      (libsource (lib "eagle-import") (part "R0201"))
    )
    (comp (ref "R250")
      (value "5.1K")
      (footprint "eagle-import:R0201")
      (libsource (lib "eagle-import") (part "R0201"))
    )
    (comp (ref "R251")
      (value "5.1K")
      (footprint "eagle-import:R0201")
      (libsource (lib "eagle-import") (part "R0201"))
    )
    (comp (ref "R255")
      (value "1M")
      (footprint "eagle-import:0402")
      (libsource (lib "eagle-import") (part "R0402"))
    )
    (comp (ref "REF1")
      (value "LM4040BXX")
      (footprint "eagle-import:SOT23")
      (libsource (lib "eagle-import") (part "LM4040BXX"))
    )
    (comp (ref "RESET")
      (value "430182043816")
      (footprint "eagle-import:430182050816")
      (libsource (lib "eagle-import") (part "430182050816"))
    )
    (comp (ref "USB9")
      (value "USB_C-THT")
      (footprint "eagle-import:USB-C")
      (libsource (lib "eagle-import") (part "USB_C-THT"))
    )
    (comp (ref "VREF")
      (value "TP")
      (footprint "eagle-import:TP")
      (libsource (lib "eagle-import") (part "TP"))
    )
    (comp (ref "X1")
      (value "X322512MSB4SI")
      (footprint "eagle-import:WE-XTAL_CFPX-180")
      (fields (field (name "TOLERANCE") "±20ppm"))
      (libsource (lib "eagle-import") (part "WE-XTAL_CFPX-180_830055295"))
    )
    (comp (ref "C233")
      (value "100nF")
      (footprint "eagle-import:0201")
      (libsource (lib "eagle-import") (part "C-0201"))
    )
    (comp (ref "C234")
      (value "100nF")
      (footprint "eagle-import:0201")
      (libsource (lib "eagle-import") (part "C-0201"))
    )
    (comp (ref "C235")
      (value "100nF")
      (footprint "eagle-import:0201")
      (libsource (lib "eagle-import") (part "C-0201"))
    )
    (comp (ref "C236")
      (value "33pF")
      (footprint "eagle-import:0201")
      (libsource (lib "eagle-import") (part "C-0201"))
    )
    (comp (ref "C237")
      (value "22uF 25V")
      (footprint "eagle-import:C1206")
      (libsource (lib "eagle-import") (part "C-1206"))
    )
    (comp (ref "C238")
      (value "22uF - 10V")
      (footprint "eagle-import:C1206")
      (libsource (lib "eagle-import") (part "C-1206"))
    )
    (comp (ref "C239")
      (value "22uF - 10V")
      (footprint "eagle-import:C1206")
      (libsource (lib "eagle-import") (part "C-1206"))
    )
    (comp (ref "C252")
      (value "220uF 35V")
      (footprint "eagle-import:CAPAE830X1050N")
      (libsource (lib "eagle-import") (part "C-POLECAP-8.5MM_"))
    )
    (comp (ref "C253")
      (value "220uF 35V")
      (footprint "eagle-import:CAPAE830X1050N")
      (libsource (lib "eagle-import") (part "C-POLECAP-8.5MM_"))
    )
    (comp (ref "C254")
      (value "220uF 35V")
      (footprint "eagle-import:CAPAE830X1050N")
      (libsource (lib "eagle-import") (part "C-POLECAP-8.5MM_"))
    )
    (comp (ref "C255")
      (value "220uF 35V")
      (footprint "eagle-import:CAPAE830X1050N")
      (libsource (lib "eagle-import") (part "C-POLECAP-8.5MM_"))
    )
    (comp (ref "C256")
      (value "220uF 35V")
      (footprint "eagle-import:CAPAE830X1050N")
      (libsource (lib "eagle-import") (part "C-POLECAP-8.5MM_"))
    )
    (comp (ref "C257")
      (value "220uF 35V")
      (footprint "eagle-import:CAPAE830X1050N")
      (libsource (lib "eagle-import") (part "C-POLECAP-8.5MM_"))
    )
    (comp (ref "C258")
      (value "100nF")
      (footprint "eagle-import:0201")
      (libsource (lib "eagle-import") (part "C-0201"))
    )
    (comp (ref "C259")
      (value "100nF")
      (footprint "eagle-import:0201")
      (libsource (lib "eagle-import") (part "C-0201"))
    )
    (comp (ref "C260")
      (value "100nF")
      (footprint "eagle-import:0201")
      (libsource (lib "eagle-import") (part "C-0201"))
    )
    (comp (ref "C261")
      (value "33pF")
      (footprint "eagle-import:0201")
      (libsource (lib "eagle-import") (part "C-0201"))
    )
    (comp (ref "C262")
      (value "22uF 25V")
      (footprint "eagle-import:C1206")
      (libsource (lib "eagle-import") (part "C-1206"))
    )
    (comp (ref "C263")
      (value "22uF - 10V")
      (footprint "eagle-import:C1206")
      (libsource (lib "eagle-import") (part "C-1206"))
    )
    (comp (ref "C264")
      (value "22uF - 10V")
      (footprint "eagle-import:C1206")
      (libsource (lib "eagle-import") (part "C-1206"))
    )
    (comp (ref "C272")
      (value "100nF")
      (footprint "eagle-import:0201")
      (libsource (lib "eagle-import") (part "C-0201"))
    )
    (comp (ref "C273")
      (value "100nF")
      (footprint "eagle-import:0201")
      (libsource (lib "eagle-import") (part "C-0201"))
    )
    (comp (ref "C274")
      (value "100nF")
      (footprint "eagle-import:0201")
      (libsource (lib "eagle-import") (part "C-0201"))
    )
    (comp (ref "C275")
      (value "33pF")
      (footprint "eagle-import:0201")
      (libsource (lib "eagle-import") (part "C-0201"))
    )
    (comp (ref "C276")
      (value "22uF 25V")
      (footprint "eagle-import:C1206")
      (libsource (lib "eagle-import") (part "C-1206"))
    )
    (comp (ref "C277")
      (value "22uF - 10V")
      (footprint "eagle-import:C1206")
      (libsource (lib "eagle-import") (part "C-1206"))
    )
    (comp (ref "C278")
      (value "22uF - 10V")
      (footprint "eagle-import:C1206")
      (libsource (lib "eagle-import") (part "C-1206"))
    )
    (comp (ref "D9")
      (value "SMBJ33A")
      (footprint "eagle-import:SMB")
      (libsource (lib "eagle-import") (part "DIODE-SMB"))
    )
    (comp (ref "D10")
      (value "SMBJ33A")
      (footprint "eagle-import:SMB")
      (libsource (lib "eagle-import") (part "DIODE-SMB"))
    )
    (comp (ref "D11")
      (value "SMBJ33A")
      (footprint "eagle-import:SMB")
      (libsource (lib "eagle-import") (part "DIODE-SMB"))
    )
    (comp (ref "F1")
      (value "2A")
      (footprint "eagle-import:FUSE_3544-2")
      (fields (field (name "MANUFACTURER") "Keystone"))
      (libsource (lib "eagle-import") (part "BLADE-FUSE"))
    )
    (comp (ref "F2")
      (value "15A")
      (footprint "eagle-import:FUSE_3544-2")
      (fields (field (name "MANUFACTURER") "Keystone"))
      (libsource (lib "eagle-import") (part "BLADE-FUSE"))
    )
    (comp (ref "F3")
      (value "15A")
      (footprint "eagle-import:FUSE_3544-2")
      (fields (field (name "MANUFACTURER") "Keystone"))
      (libsource (lib "eagle-import") (part "BLADE-FUSE"))
    )
    (comp (ref "GND") (value "TP") (footprint "eagle-import:TP") (libsource (lib "eagle-import") (part "TP")))
    (comp (ref "IC40")
      (value "MP2315S")
      (footprint "eagle-import:SOT65P280X110-8N")
      (libsource (lib "eagle-import") (part "MP2315TSOT23-8"))
    )
    (comp (ref "IC43")
      (value "MP2315S")
      (footprint "eagle-import:SOT65P280X110-8N")
      (libsource (lib "eagle-import") (part "MP2315TSOT23-8"))
    )
    (comp (ref "IC45")
      (value "MP2315S")
      (footprint "eagle-import:SOT65P280X110-8N")
      (libsource (lib "eagle-import") (part "MP2315TSOT23-8"))
    )
    (comp (ref "J8")
      (value "691244510006")
      (footprint "eagle-import:691244510006")
      (libsource (lib "eagle-import") (part "691244510006"))
    )
    (comp (ref "L11")
      (value "4.2uH")
      (footprint "eagle-import:SRR5228A")
      (libsource (lib "eagle-import") (part "L"))
    )
    (comp (ref "L13")
      (value "4.9uH")
      (footprint "eagle-import:SRR5228A")
      (libsource (lib "eagle-import") (part "L"))
    )
    (comp (ref "L15")
      (value "4.9uH")
      (footprint "eagle-import:SRR5228A")
      (libsource (lib "eagle-import") (part "L"))
    )
    (comp (ref "R241")
      (value "499K")
      (footprint "eagle-import:R0201")
      (libsource (lib "eagle-import") (part "R0201"))
    )
    (comp (ref "R242")
      (value "7.5K")
      (footprint "eagle-import:R0201")
      (libsource (lib "eagle-import") (part "R0201"))
    )
    (comp (ref "R243")
      (value "10R")
      (footprint "eagle-import:R0201")
      (libsource (lib "eagle-import") (part "R0201"))
    )
    (comp (ref "R244")
      (value "100K")
      (footprint "eagle-import:R0201")
      (libsource (lib "eagle-import") (part "R0201"))
    )
    (comp (ref "R254")
      (value "499K")
      (footprint "eagle-import:R0201")
      (libsource (lib "eagle-import") (part "R0201"))
    )
    (comp (ref "R256")
      (value "7.5K")
      (footprint "eagle-import:R0201")
      (libsource (lib "eagle-import") (part "R0201"))
    )
    (comp (ref "R257")
      (value "10R")
      (footprint "eagle-import:R0201")
      (libsource (lib "eagle-import") (part "R0201"))
    )
    (comp (ref "R258")
      (value "100K")
      (footprint "eagle-import:R0201")
      (libsource (lib "eagle-import") (part "R0201"))
    )
    (comp (ref "R263")
      (value "499K")
      (footprint "eagle-import:R0201")
      (libsource (lib "eagle-import") (part "R0201"))
    )
    (comp (ref "R264")
      (value "7.5K")
      (footprint "eagle-import:R0201")
      (libsource (lib "eagle-import") (part "R0201"))
    )
    (comp (ref "R265")
      (value "10R")
      (footprint "eagle-import:R0201")
      (libsource (lib "eagle-import") (part "R0201"))
    )
    (comp (ref "R266")
      (value "100K")
      (footprint "eagle-import:R0201")
      (libsource (lib "eagle-import") (part "R0201"))
    )
    (comp (ref "RFB3")
      (value "40.2K")
      (footprint "eagle-import:R0201")
      (libsource (lib "eagle-import") (part "R0201"))
    )
    (comp (ref "RFB4")
      (value "12.7K 1%")
      (footprint "eagle-import:R0201")
      (libsource (lib "eagle-import") (part "R0201"))
    )
    (comp (ref "RFB7")
      (value "40.2K")
      (footprint "eagle-import:R0201")
      (libsource (lib "eagle-import") (part "R0201"))
    )
    (comp (ref "RFB8")
      (value "7.5K 1%")
      (footprint "eagle-import:R0201")
      (libsource (lib "eagle-import") (part "R0201"))
    )
    (comp (ref "RFB11")
      (value "40.2K")
      (footprint "eagle-import:R0201")
      (libsource (lib "eagle-import") (part "R0201"))
    )
    (comp (ref "RFB12")
      (value "7.5K 1%")
      (footprint "eagle-import:R0201")
      (libsource (lib "eagle-import") (part "R0201"))
    )
    (comp (ref "RT1")
      (value "33K")
      (footprint "eagle-import:R0201")
      (libsource (lib "eagle-import") (part "R0201"))
    )
    (comp (ref "RT3")
      (value "20K 1%")
      (footprint "eagle-import:R0201")
      (libsource (lib "eagle-import") (part "R0201"))
    )
    (comp (ref "RT5")
      (value "20K 1%")
      (footprint "eagle-import:R0201")
      (libsource (lib "eagle-import") (part "R0201"))
    )
    (comp (ref "VO3") (value "TP") (footprint "eagle-import:TP") (libsource (lib "eagle-import") (part "TP")))
    (comp (ref "VO5A")
      (value "TP")
      (footprint "eagle-import:TP")
      (libsource (lib "eagle-import") (part "TP"))
    )
    (comp (ref "VO5B")
      (value "TP")
      (footprint "eagle-import:TP")
      (libsource (lib "eagle-import") (part "TP"))
    )
    (comp (ref "C56")
      (value "1uF 10V")
      (footprint "eagle-import:0201")
      (libsource (lib "eagle-import") (part "C-0201"))
    )
    (comp (ref "C57")
      (value "1uF 10V")
      (footprint "eagle-import:0201")
      (libsource (lib "eagle-import") (part "C-0201"))
    )
    (comp (ref "C58")
      (value "1uF 50V")
      (footprint "eagle-import:C0603")
      (libsource (lib "eagle-import") (part "C-0603"))
    )
    (comp (ref "C59")
      (value "4.7nF")
      (footprint "eagle-import:C0402")
      (libsource (lib "eagle-import") (part "C-0402"))
    )
    (comp (ref "C60")
      (value "4.7uF")
      (footprint "eagle-import:C0402")
      (libsource (lib "eagle-import") (part "C-0402"))
    )
    (comp (ref "C61")
      (value "10nF")
      (footprint "eagle-import:0201")
      (libsource (lib "eagle-import") (part "C-0201"))
    )
    (comp (ref "C62")
      (value "10nF")
      (footprint "eagle-import:0201")
      (libsource (lib "eagle-import") (part "C-0201"))
    )
    (comp (ref "C63")
      (value "10nF")
      (footprint "eagle-import:0201")
      (libsource (lib "eagle-import") (part "C-0201"))
    )
    (comp (ref "C64")
      (value "100nF")
      (footprint "eagle-import:C0402")
      (libsource (lib "eagle-import") (part "C-0402"))
    )
    (comp (ref "C65")
      (value "100nF")
      (footprint "eagle-import:C0402")
      (libsource (lib "eagle-import") (part "C-0402"))
    )
    (comp (ref "C66")
      (value "10uF 50V")
      (footprint "eagle-import:C0805")
      (libsource (lib "eagle-import") (part "C-0805"))
    )
    (comp (ref "C67")
      (value "10uF 50V")
      (footprint "eagle-import:C0805")
      (libsource (lib "eagle-import") (part "C-0805"))
    )
    (comp (ref "C68")
      (value "10uF 50V")
      (footprint "eagle-import:C0805")
      (libsource (lib "eagle-import") (part "C-0805"))
    )
    (comp (ref "C69")
      (value "10uF 50V")
      (footprint "eagle-import:C0805")
      (libsource (lib "eagle-import") (part "C-0805"))
    )
    (comp (ref "C70")
      (value "22uF 50V")
      (footprint "eagle-import:C0805")
      (libsource (lib "eagle-import") (part "C-0805"))
    )
    (comp (ref "C71")
      (value "22uF 50V")
      (footprint "eagle-import:C0805")
      (libsource (lib "eagle-import") (part "C-0805"))
    )
    (comp (ref "C72")
      (value "22uF 50V")
      (footprint "eagle-import:C0805")
      (libsource (lib "eagle-import") (part "C-0805"))
    )
    (comp (ref "C73")
      (value "22uF 50V")
      (footprint "eagle-import:C0805")
      (libsource (lib "eagle-import") (part "C-0805"))
    )
    (comp (ref "C74")
      (value "100nF")
      (footprint "eagle-import:0201")
      (libsource (lib "eagle-import") (part "C-0201"))
    )
    (comp (ref "IC10")
      (value "STUSB4710AQ1TR")
      (footprint "eagle-import:QFN50P300X300X55-16N")
      (libsource (lib "eagle-import") (part "STUSB4710AQ1TR"))
    )
    (comp (ref "IC15")
      (value "TPS552882")
      (footprint "eagle-import:RPM0026A-MFG")
      (fields
        (field (name "MANUFACTURER_PART_NUMBER") "TPS552882QRPMRQ1")
        (field (name "COPYRIGHT") "Copyright (C) 2025 Ultra Librarian. All rights reserved.")
      )
      (libsource (lib "eagle-import") (part "TPS552882"))
    )
    (comp (ref "IC16")
      (value "INA219BIDCNT")
      (footprint "eagle-import:SOT23-8")
      (libsource (lib "eagle-import") (part "INA219BIDCNT"))
    )
    (comp (ref "L3")
      (value "4.7uH 744771004")
      (footprint "eagle-import:WE-PD_1280")
      (libsource (lib "eagle-import") (part "WE-PD_1280_74477004"))
    )
    (comp (ref "PORT2")
      (value "632722100213")
      (footprint "eagle-import:632722100213")
      (libsource (lib "eagle-import") (part "632722100213"))
    )
    (comp (ref "R67")
      (value "200K")
      (footprint "eagle-import:R0201")
      (libsource (lib "eagle-import") (part "R0201"))
    )
    (comp (ref "R68")
      (value "12.7K 0.1%")
      (footprint "eagle-import:R0201")
      (libsource (lib "eagle-import") (part "R0201"))
    )
    (comp (ref "R69")
      (value "4.64K 0.1%")
      (footprint "eagle-import:R0201")
      (libsource (lib "eagle-import") (part "R0201"))
    )
    (comp (ref "R70")
      (value "4.64K 0.1%")
      (footprint "eagle-import:R0201")
      (libsource (lib "eagle-import") (part "R0201"))
    )
    (comp (ref "R71")
      (value "8.87K 0.1%")
      (footprint "eagle-import:R0201")
      (libsource (lib "eagle-import") (part "R0201"))
    )
    (comp (ref "R72")
      (value "30.9K 0.1%")
      (footprint "eagle-import:R0201")
      (libsource (lib "eagle-import") (part "R0201"))
    )
    (comp (ref "R73")
      (value "100K")
      (footprint "eagle-import:R0201")
      (libsource (lib "eagle-import") (part "R0201"))
    )
    (comp (ref "R74")
      (value "DNI")
      (footprint "eagle-import:R0201")
      (libsource (lib "eagle-import") (part "R0201"))
    )
    (comp (ref "R75")
      (value "10K")
      (footprint "eagle-import:0402")
      (libsource (lib "eagle-import") (part "R0402"))
    )
    (comp (ref "R76")
      (value "10K")
      (footprint "eagle-import:0402")
      (libsource (lib "eagle-import") (part "R0402"))
    )
    (comp (ref "R77")
      (value "10K")
      (footprint "eagle-import:R0201")
      (libsource (lib "eagle-import") (part "R0201"))
    )
    (comp (ref "R78")
      (value "2.2K")
      (footprint "eagle-import:R0201")
      (libsource (lib "eagle-import") (part "R0201"))
    )
    (comp (ref "R79")
      (value "10K")
      (footprint "eagle-import:0402")
      (libsource (lib "eagle-import") (part "R0402"))
    )
    (comp (ref "R80")
      (value "0.010R")
      (footprint "eagle-import:2512")
      (libsource (lib "eagle-import") (part "R2512"))
    )
    (comp (ref "R81")
      (value "6.19K")
      (footprint "eagle-import:R0201")
      (libsource (lib "eagle-import") (part "R0201"))
    )
    (comp (ref "R82")
      (value "49.9K")
      (footprint "eagle-import:R0201")
      (libsource (lib "eagle-import") (part "R0201"))
    )
    (comp (ref "R83")
      (value "19.9K")
      (footprint "eagle-import:R0201")
      (libsource (lib "eagle-import") (part "R0201"))
    )
    (comp (ref "R85")
      (value "150K")
      (footprint "eagle-import:R0201")
      (libsource (lib "eagle-import") (part "R0201"))
    )
    (comp (ref "R86")
      (value "19.9K")
      (footprint "eagle-import:R0201")
      (libsource (lib "eagle-import") (part "R0201"))
    )
    (comp (ref "R87")
      (value "0.010R")
      (footprint "eagle-import:2512")
      (libsource (lib "eagle-import") (part "R2512"))
    )
    (comp (ref "R88")
      (value "1K")
      (footprint "eagle-import:R0201")
      (libsource (lib "eagle-import") (part "R0201"))
    )
    (comp (ref "R89")
      (value "1K")
      (footprint "eagle-import:R0201")
      (libsource (lib "eagle-import") (part "R0201"))
    )
    (comp (ref "R90")
      (value "10K")
      (footprint "eagle-import:R0201")
      (libsource (lib "eagle-import") (part "R0201"))
    )
    (comp (ref "T11")
      (value "DMP3013SFV")
      (footprint "eagle-import:POWERDI3333-8_UX_DIO-L")
      (fields (field (name "MANUFACTURER_PART_NUMBER") "DMP3013SFV-7"))
      (libsource (lib "eagle-import") (part "DMP3013SFV-7UX"))
    )
    (comp (ref "T12")
      (value "DMP3013SFV")
      (footprint "eagle-import:POWERDI3333-8_UX_DIO-L")
      (fields (field (name "MANUFACTURER_PART_NUMBER") "DMP3013SFV-7"))
      (libsource (lib "eagle-import") (part "DMP3013SFV-7UX"))
    )
    (comp (ref "T13")
      (value "DMP3013SFV")
      (footprint "eagle-import:POWERDI3333-8_UX_DIO-L")
      (fields (field (name "MANUFACTURER_PART_NUMBER") "DMP3013SFV-7"))
      (libsource (lib "eagle-import") (part "DMP3013SFV-7UX"))
    )
    (comp (ref "T14")
      (value "BSZ065N06LS5ATMA1")
      (footprint "eagle-import:POWERDI3333-8_UX_DIO-L")
      (fields
        (field (name "MANUFACTURER_PART_NUMBER") "IPZ40N04S5L7R4ATMA1")
        (field (name "COPYRIGHT") "Copyright (C) 2025 Ultra Librarian. All rights reserved.")
      )
      (libsource (lib "eagle-import") (part "IPZ40N04S5L7R4ATMA1"))
    )
    (comp (ref "T15")
      (value "BSZ065N06LS5ATMA1")
      (footprint "eagle-import:POWERDI3333-8_UX_DIO-L")
      (fields
        (field (name "MANUFACTURER_PART_NUMBER") "IPZ40N04S5L7R4ATMA1")
        (field (name "COPYRIGHT") "Copyright (C) 2025 Ultra Librarian. All rights reserved.")
      )
      (libsource (lib "eagle-import") (part "IPZ40N04S5L7R4ATMA1"))
    )
    (comp (ref "C75")
      (value "1uF 10V")
      (footprint "eagle-import:0201")
      (libsource (lib "eagle-import") (part "C-0201"))
    )
    (comp (ref "C76")
      (value "1uF 10V")
      (footprint "eagle-import:0201")
      (libsource (lib "eagle-import") (part "C-0201"))
    )
    (comp (ref "C77")
      (value "1uF 50V")
      (footprint "eagle-import:C0603")
      (libsource (lib "eagle-import") (part "C-0603"))
    )
    (comp (ref "C78")
      (value "4.7nF")
      (footprint "eagle-import:C0402")
      (libsource (lib "eagle-import") (part "C-0402"))
    )
    (comp (ref "C79")
      (value "4.7uF")
      (footprint "eagle-import:C0402")
      (libsource (lib "eagle-import") (part "C-0402"))
    )
    (comp (ref "C80")
      (value "10nF")
      (footprint "eagle-import:0201")
      (libsource (lib "eagle-import") (part "C-0201"))
    )
    (comp (ref "C81")
      (value "10nF")
      (footprint "eagle-import:0201")
      (libsource (lib "eagle-import") (part "C-0201"))
    )
    (comp (ref "C86")
      (value "10nF")
      (footprint "eagle-import:0201")
      (libsource (lib "eagle-import") (part "C-0201"))
    )
    (comp (ref "C87")
      (value "100nF")
      (footprint "eagle-import:C0402")
      (libsource (lib "eagle-import") (part "C-0402"))
    )
    (comp (ref "C88")
      (value "100nF")
      (footprint "eagle-import:C0402")
      (libsource (lib "eagle-import") (part "C-0402"))
    )
    (comp (ref "C89")
      (value "10uF 50V")
      (footprint "eagle-import:C0805")
      (libsource (lib "eagle-import") (part "C-0805"))
    )
    (comp (ref "C90")
      (value "10uF 50V")
      (footprint "eagle-import:C0805")
      (libsource (lib "eagle-import") (part "C-0805"))
    )
    (comp (ref "C91")
      (value "10uF 50V")
      (footprint "eagle-import:C0805")
      (libsource (lib "eagle-import") (part "C-0805"))
    )
    (comp (ref "C92")
      (value "10uF 50V")
      (footprint "eagle-import:C0805")
      (libsource (lib "eagle-import") (part "C-0805"))
    )
    (comp (ref "C93")
      (value "22uF 50V")
      (footprint "eagle-import:C0805")
      (libsource (lib "eagle-import") (part "C-0805"))
    )
    (comp (ref "C94")
      (value "22uF 50V")
      (footprint "eagle-import:C0805")
      (libsource (lib "eagle-import") (part "C-0805"))
    )
    (comp (ref "C95")
      (value "22uF 50V")
      (footprint "eagle-import:C0805")
      (libsource (lib "eagle-import") (part "C-0805"))
    )
    (comp (ref "C96")
      (value "22uF 50V")
      (footprint "eagle-import:C0805")
      (libsource (lib "eagle-import") (part "C-0805"))
    )
    (comp (ref "C97")
      (value "100nF")
      (footprint "eagle-import:0201")
      (libsource (lib "eagle-import") (part "C-0201"))
    )
    (comp (ref "IC17")
      (value "STUSB4710AQ1TR")
      (footprint "eagle-import:QFN50P300X300X55-16N")
      (libsource (lib "eagle-import") (part "STUSB4710AQ1TR"))
    )
    (comp (ref "IC18")
      (value "TPS552882")
      (footprint "eagle-import:RPM0026A-MFG")
      (fields
        (field (name "MANUFACTURER_PART_NUMBER") "TPS552882QRPMRQ1")
        (field (name "COPYRIGHT") "Copyright (C) 2025 Ultra Librarian. All rights reserved.")
      )
      (libsource (lib "eagle-import") (part "TPS552882"))
    )
    (comp (ref "IC19")
      (value "INA219BIDCNT")
      (footprint "eagle-import:SOT23-8")
      (libsource (lib "eagle-import") (part "INA219BIDCNT"))
    )
    (comp (ref "L4")
      (value "4.7uH 744771004")
      (footprint "eagle-import:WE-PD_1280")
      (libsource (lib "eagle-import") (part "WE-PD_1280_74477004"))
    )
    (comp (ref "PORT5")
      (value "632722100213")
      (footprint "eagle-import:632722100213")
      (libsource (lib "eagle-import") (part "632722100213"))
    )
    (comp (ref "R91")
      (value "200K")
      (footprint "eagle-import:R0201")
      (libsource (lib "eagle-import") (part "R0201"))
    )
    (comp (ref "R92")
      (value "12.7K 0.1%")
      (footprint "eagle-import:R0201")
      (libsource (lib "eagle-import") (part "R0201"))
    )
    (comp (ref "R93")
      (value "4.64K 0.1%")
      (footprint "eagle-import:R0201")
      (libsource (lib "eagle-import") (part "R0201"))
    )
    (comp (ref "R94")
      (value "4.64K 0.1%")
      (footprint "eagle-import:R0201")
      (libsource (lib "eagle-import") (part "R0201"))
    )
    (comp (ref "R95")
      (value "8.87K 0.1%")
      (footprint "eagle-import:R0201")
      (libsource (lib "eagle-import") (part "R0201"))
    )
    (comp (ref "R96")
      (value "30.9K 0.1%")
      (footprint "eagle-import:R0201")
      (libsource (lib "eagle-import") (part "R0201"))
    )
    (comp (ref "R97")
      (value "DNI")
      (footprint "eagle-import:R0201")
      (libsource (lib "eagle-import") (part "R0201"))
    )
    (comp (ref "R98")
      (value "100K")
      (footprint "eagle-import:R0201")
      (libsource (lib "eagle-import") (part "R0201"))
    )
    (comp (ref "R99")
      (value "10K")
      (footprint "eagle-import:0402")
      (libsource (lib "eagle-import") (part "R0402"))
    )
    (comp (ref "R100")
      (value "10K")
      (footprint "eagle-import:0402")
      (libsource (lib "eagle-import") (part "R0402"))
    )
    (comp (ref "R101")
      (value "10K")
      (footprint "eagle-import:R0201")
      (libsource (lib "eagle-import") (part "R0201"))
    )
    (comp (ref "R102")
      (value "2.2K")
      (footprint "eagle-import:R0201")
      (libsource (lib "eagle-import") (part "R0201"))
    )
    (comp (ref "R103")
      (value "10K")
      (footprint "eagle-import:0402")
      (libsource (lib "eagle-import") (part "R0402"))
    )
    (comp (ref "R104")
      (value "0.010R")
      (footprint "eagle-import:2512")
      (libsource (lib "eagle-import") (part "R2512"))
    )
    (comp (ref "R105")
      (value "6.19K")
      (footprint "eagle-import:R0201")
      (libsource (lib "eagle-import") (part "R0201"))
    )
    (comp (ref "R106")
      (value "49.9K")
      (footprint "eagle-import:R0201")
      (libsource (lib "eagle-import") (part "R0201"))
    )
    (comp (ref "R107")
      (value "19.9K")
      (footprint "eagle-import:R0201")
      (libsource (lib "eagle-import") (part "R0201"))
    )
    (comp (ref "R108")
      (value "150K")
      (footprint "eagle-import:R0201")
      (libsource (lib "eagle-import") (part "R0201"))
    )
    (comp (ref "R109")
      (value "19.9K")
      (footprint "eagle-import:R0201")
      (libsource (lib "eagle-import") (part "R0201"))
    )
    (comp (ref "R110")
      (value "0.010R")
      (footprint "eagle-import:2512")
      (libsource (lib "eagle-import") (part "R2512"))
    )
    (comp (ref "R111")
      (value "1K")
      (footprint "eagle-import:R0201")
      (libsource (lib "eagle-import") (part "R0201"))
    )
    (comp (ref "R112")
      (value "1K")
      (footprint "eagle-import:R0201")
      (libsource (lib "eagle-import") (part "R0201"))
    )
    (comp (ref "R113")
      (value "10K")
      (footprint "eagle-import:R0201")
      (libsource (lib "eagle-import") (part "R0201"))
    )
    (comp (ref "T16")
      (value "DMP3013SFV")
      (footprint "eagle-import:POWERDI3333-8_UX_DIO-L")
      (fields (field (name "MANUFACTURER_PART_NUMBER") "DMP3013SFV-7"))
      (libsource (lib "eagle-import") (part "DMP3013SFV-7UX"))
    )
    (comp (ref "T17")
      (value "DMP3013SFV")
      (footprint "eagle-import:POWERDI3333-8_UX_DIO-L")
      (fields (field (name "MANUFACTURER_PART_NUMBER") "DMP3013SFV-7"))
      (libsource (lib "eagle-import") (part "DMP3013SFV-7UX"))
    )
    (comp (ref "T18")
      (value "DMP3013SFV")
      (footprint "eagle-import:POWERDI3333-8_UX_DIO-L")
      (fields (field (name "MANUFACTURER_PART_NUMBER") "DMP3013SFV-7"))
      (libsource (lib "eagle-import") (part "DMP3013SFV-7UX"))
    )
    (comp (ref "T19")
      (value "BSZ065N06LS5ATMA1")
      (footprint "eagle-import:POWERDI3333-8_UX_DIO-L")
      (fields
        (field (name "MANUFACTURER_PART_NUMBER") "IPZ40N04S5L7R4ATMA1")
        (field (name "COPYRIGHT") "Copyright (C) 2025 Ultra Librarian. All rights reserved.")
      )
      (libsource (lib "eagle-import") (part "IPZ40N04S5L7R4ATMA1"))
    )
    (comp (ref "T20")
      (value "BSZ065N06LS5ATMA1")
      (footprint "eagle-import:POWERDI3333-8_UX_DIO-L")
      (fields
        (field (name "MANUFACTURER_PART_NUMBER") "IPZ40N04S5L7R4ATMA1")
        (field (name "COPYRIGHT") "Copyright (C) 2025 Ultra Librarian. All rights reserved.")
      )
      (libsource (lib "eagle-import") (part "IPZ40N04S5L7R4ATMA1"))
    )
    (comp (ref "C174")
      (value "1uF 10V")
      (footprint "eagle-import:0201")
      (libsource (lib "eagle-import") (part "C-0201"))
    )
    (comp (ref "C175")
      (value "1uF 10V")
      (footprint "eagle-import:0201")
      (libsource (lib "eagle-import") (part "C-0201"))
    )
    (comp (ref "C197")
      (value "1uF 50V")
      (footprint "eagle-import:C0603")
      (libsource (lib "eagle-import") (part "C-0603"))
    )
    (comp (ref "C198")
      (value "4.7nF")
      (footprint "eagle-import:C0402")
      (libsource (lib "eagle-import") (part "C-0402"))
    )
    (comp (ref "C199")
      (value "4.7uF")
      (footprint "eagle-import:C0402")
      (libsource (lib "eagle-import") (part "C-0402"))
    )
    (comp (ref "C200")
      (value "10nF")
      (footprint "eagle-import:0201")
      (libsource (lib "eagle-import") (part "C-0201"))
    )
    (comp (ref "C201")
      (value "10nF")
      (footprint "eagle-import:0201")
      (libsource (lib "eagle-import") (part "C-0201"))
    )
    (comp (ref "C202")
      (value "10nF")
      (footprint "eagle-import:0201")
      (libsource (lib "eagle-import") (part "C-0201"))
    )
    (comp (ref "C203")
      (value "100nF")
      (footprint "eagle-import:C0402")
      (libsource (lib "eagle-import") (part "C-0402"))
    )
    (comp (ref "C204")
      (value "100nF")
      (footprint "eagle-import:C0402")
      (libsource (lib "eagle-import") (part "C-0402"))
    )
    (comp (ref "C205")
      (value "10uF 50V")
      (footprint "eagle-import:C0805")
      (libsource (lib "eagle-import") (part "C-0805"))
    )
    (comp (ref "C206")
      (value "10uF 50V")
      (footprint "eagle-import:C0805")
      (libsource (lib "eagle-import") (part "C-0805"))
    )
    (comp (ref "C207")
      (value "10uF 50V")
      (footprint "eagle-import:C0805")
      (libsource (lib "eagle-import") (part "C-0805"))
    )
    (comp (ref "C208")
      (value "10uF 50V")
      (footprint "eagle-import:C0805")
      (libsource (lib "eagle-import") (part "C-0805"))
    )
    (comp (ref "C209")
      (value "22uF 50V")
      (footprint "eagle-import:C0805")
      (libsource (lib "eagle-import") (part "C-0805"))
    )
    (comp (ref "C210")
      (value "22uF 50V")
      (footprint "eagle-import:C0805")
      (libsource (lib "eagle-import") (part "C-0805"))
    )
    (comp (ref "C211")
      (value "22uF 50V")
      (footprint "eagle-import:C0805")
      (libsource (lib "eagle-import") (part "C-0805"))
    )
    (comp (ref "C240")
      (value "22uF 50V")
      (footprint "eagle-import:C0805")
      (libsource (lib "eagle-import") (part "C-0805"))
    )
    (comp (ref "C241")
      (value "100nF")
      (footprint "eagle-import:0201")
      (libsource (lib "eagle-import") (part "C-0201"))
    )
    (comp (ref "IC30")
      (value "STUSB4710AQ1TR")
      (footprint "eagle-import:QFN50P300X300X55-16N")
      (libsource (lib "eagle-import") (part "STUSB4710AQ1TR"))
    )
    (comp (ref "IC41")
      (value "TPS552882")
      (footprint "eagle-import:RPM0026A-MFG")
      (fields
        (field (name "MANUFACTURER_PART_NUMBER") "TPS552882QRPMRQ1")
        (field (name "COPYRIGHT") "Copyright (C) 2025 Ultra Librarian. All rights reserved.")
      )
      (libsource (lib "eagle-import") (part "TPS552882"))
    )
    (comp (ref "IC44")
      (value "INA219BIDCNT")
      (footprint "eagle-import:SOT23-8")
      (libsource (lib "eagle-import") (part "INA219BIDCNT"))
    )
    (comp (ref "L9")
      (value "4.7uH 744771004")
      (footprint "eagle-import:WE-PD_1280")
      (libsource (lib "eagle-import") (part "WE-PD_1280_74477004"))
    )
    (comp (ref "PORT8")
      (value "632722100213")
      (footprint "eagle-import:632722100213")
      (libsource (lib "eagle-import") (part "632722100213"))
    )
    (comp (ref "R219")
      (value "200K")
      (footprint "eagle-import:R0201")
      (libsource (lib "eagle-import") (part "R0201"))
    )
    (comp (ref "R220")
      (value "12.7K 0.1%")
      (footprint "eagle-import:R0201")
      (libsource (lib "eagle-import") (part "R0201"))
    )
    (comp (ref "R221")
      (value "4.64K 0.1%")
      (footprint "eagle-import:R0201")
      (libsource (lib "eagle-import") (part "R0201"))
    )
    (comp (ref "R222")
      (value "4.64K 0.1%")
      (footprint "eagle-import:R0201")
      (libsource (lib "eagle-import") (part "R0201"))
    )
    (comp (ref "R223")
      (value "8.87K 0.1%")
      (footprint "eagle-import:R0201")
      (libsource (lib "eagle-import") (part "R0201"))
    )
    (comp (ref "R224")
      (value "30.9K 0.1%")
      (footprint "eagle-import:R0201")
      (libsource (lib "eagle-import") (part "R0201"))
    )
    (comp (ref "R245")
      (value "100K")
      (footprint "eagle-import:R0201")
      (libsource (lib "eagle-import") (part "R0201"))
    )
    (comp (ref "R246")
      (value "DNI")
      (footprint "eagle-import:R0201")
      (libsource (lib "eagle-import") (part "R0201"))
    )
    (comp (ref "R247")
      (value "10K")
      (footprint "eagle-import:0402")
      (libsource (lib "eagle-import") (part "R0402"))
    )
    (comp (ref "R248")
      (value "10K")
      (footprint "eagle-import:0402")
      (libsource (lib "eagle-import") (part "R0402"))
    )
    (comp (ref "R259")
      (value "10K")
      (footprint "eagle-import:R0201")
      (libsource (lib "eagle-import") (part "R0201"))
    )
    (comp (ref "R260")
      (value "2.2K")
      (footprint "eagle-import:R0201")
      (libsource (lib "eagle-import") (part "R0201"))
    )
    (comp (ref "R261")
      (value "10K")
      (footprint "eagle-import:0402")
      (libsource (lib "eagle-import") (part "R0402"))
    )
    (comp (ref "R262")
      (value "0.010R")
      (footprint "eagle-import:2512")
      (libsource (lib "eagle-import") (part "R2512"))
    )
    (comp (ref "R267")
      (value "6.19K")
      (footprint "eagle-import:R0201")
      (libsource (lib "eagle-import") (part "R0201"))
    )
    (comp (ref "R268")
      (value "49.9K")
      (footprint "eagle-import:R0201")
      (libsource (lib "eagle-import") (part "R0201"))
    )
    (comp (ref "R269")
      (value "19.9K")
      (footprint "eagle-import:R0201")
      (libsource (lib "eagle-import") (part "R0201"))
    )
    (comp (ref "R270")
      (value "150K")
      (footprint "eagle-import:R0201")
      (libsource (lib "eagle-import") (part "R0201"))
    )
    (comp (ref "R271")
      (value "19.9K")
      (footprint "eagle-import:R0201")
      (libsource (lib "eagle-import") (part "R0201"))
    )
    (comp (ref "R272")
      (value "0.010R")
      (footprint "eagle-import:2512")
      (libsource (lib "eagle-import") (part "R2512"))
    )
    (comp (ref "R273")
      (value "1K")
      (footprint "eagle-import:R0201")
      (libsource (lib "eagle-import") (part "R0201"))
    )
    (comp (ref "R274")
      (value "1K")
      (footprint "eagle-import:R0201")
      (libsource (lib "eagle-import") (part "R0201"))
    )
    (comp (ref "R275")
      (value "10K")
      (footprint "eagle-import:R0201")
      (libsource (lib "eagle-import") (part "R0201"))
    )
    (comp (ref "T41")
      (value "DMP3013SFV")
      (footprint "eagle-import:POWERDI3333-8_UX_DIO-L")
      (fields (field (name "MANUFACTURER_PART_NUMBER") "DMP3013SFV-7"))
      (libsource (lib "eagle-import") (part "DMP3013SFV-7UX"))
    )
    (comp (ref "T42")
      (value "DMP3013SFV")
      (footprint "eagle-import:POWERDI3333-8_UX_DIO-L")
      (fields (field (name "MANUFACTURER_PART_NUMBER") "DMP3013SFV-7"))
      (libsource (lib "eagle-import") (part "DMP3013SFV-7UX"))
    )
    (comp (ref "T43")
      (value "DMP3013SFV")
      (footprint "eagle-import:POWERDI3333-8_UX_DIO-L")
      (fields (field (name "MANUFACTURER_PART_NUMBER") "DMP3013SFV-7"))
      (libsource (lib "eagle-import") (part "DMP3013SFV-7UX"))
    )
    (comp (ref "T44")
      (value "BSZ065N06LS5ATMA1")
      (footprint "eagle-import:POWERDI3333-8_UX_DIO-L")
      (fields
        (field (name "MANUFACTURER_PART_NUMBER") "IPZ40N04S5L7R4ATMA1")
        (field (name "COPYRIGHT") "Copyright (C) 2025 Ultra Librarian. All rights reserved.")
      )
      (libsource (lib "eagle-import") (part "IPZ40N04S5L7R4ATMA1"))
    )
    (comp (ref "T45")
      (value "BSZ065N06LS5ATMA1")
      (footprint "eagle-import:POWERDI3333-8_UX_DIO-L")
      (fields
        (field (name "MANUFACTURER_PART_NUMBER") "IPZ40N04S5L7R4ATMA1")
        (field (name "COPYRIGHT") "Copyright (C) 2025 Ultra Librarian. All rights reserved.")
      )
      (libsource (lib "eagle-import") (part "IPZ40N04S5L7R4ATMA1"))
    )
    (comp (ref "C98")
      (value "1uF 10V")
      (footprint "eagle-import:0201")
      (libsource (lib "eagle-import") (part "C-0201"))
    )
    (comp (ref "C99")
      (value "1uF 10V")
      (footprint "eagle-import:0201")
      (libsource (lib "eagle-import") (part "C-0201"))
    )
    (comp (ref "C100")
      (value "1uF 50V")
      (footprint "eagle-import:C0603")
      (libsource (lib "eagle-import") (part "C-0603"))
    )
    (comp (ref "C101")
      (value "4.7nF")
      (footprint "eagle-import:C0402")
      (libsource (lib "eagle-import") (part "C-0402"))
    )
    (comp (ref "C102")
      (value "4.7uF")
      (footprint "eagle-import:C0402")
      (libsource (lib "eagle-import") (part "C-0402"))
    )
    (comp (ref "C103")
      (value "10nF")
      (footprint "eagle-import:0201")
      (libsource (lib "eagle-import") (part "C-0201"))
    )
    (comp (ref "C104")
      (value "10nF")
      (footprint "eagle-import:0201")
      (libsource (lib "eagle-import") (part "C-0201"))
    )
    (comp (ref "C105")
      (value "10nF")
      (footprint "eagle-import:0201")
      (libsource (lib "eagle-import") (part "C-0201"))
    )
    (comp (ref "C106")
      (value "100nF")
      (footprint "eagle-import:C0402")
      (libsource (lib "eagle-import") (part "C-0402"))
    )
    (comp (ref "C107")
      (value "100nF")
      (footprint "eagle-import:C0402")
      (libsource (lib "eagle-import") (part "C-0402"))
    )
    (comp (ref "C108")
      (value "10uF 50V")
      (footprint "eagle-import:C0805")
      (libsource (lib "eagle-import") (part "C-0805"))
    )
    (comp (ref "C109")
      (value "10uF 50V")
      (footprint "eagle-import:C0805")
      (libsource (lib "eagle-import") (part "C-0805"))
    )
    (comp (ref "C110")
      (value "10uF 50V")
      (footprint "eagle-import:C0805")
      (libsource (lib "eagle-import") (part "C-0805"))
    )
    (comp (ref "C111")
      (value "10uF 50V")
      (footprint "eagle-import:C0805")
      (libsource (lib "eagle-import") (part "C-0805"))
    )
    (comp (ref "C112")
      (value "22uF 50V")
      (footprint "eagle-import:C0805")
      (libsource (lib "eagle-import") (part "C-0805"))
    )
    (comp (ref "C113")
      (value "22uF 50V")
      (footprint "eagle-import:C0805")
      (libsource (lib "eagle-import") (part "C-0805"))
    )
    (comp (ref "C114")
      (value "22uF 50V")
      (footprint "eagle-import:C0805")
      (libsource (lib "eagle-import") (part "C-0805"))
    )
    (comp (ref "C115")
      (value "22uF 50V")
      (footprint "eagle-import:C0805")
      (libsource (lib "eagle-import") (part "C-0805"))
    )
    (comp (ref "C116")
      (value "100nF")
      (footprint "eagle-import:0201")
      (libsource (lib "eagle-import") (part "C-0201"))
    )
    (comp (ref "IC14")
      (value "STUSB4710AQ1TR")
      (footprint "eagle-import:QFN50P300X300X55-16N")
      (libsource (lib "eagle-import") (part "STUSB4710AQ1TR"))
    )
    (comp (ref "IC21")
      (value "TPS552882")
      (footprint "eagle-import:RPM0026A-MFG")
      (fields
        (field (name "MANUFACTURER_PART_NUMBER") "TPS552882QRPMRQ1")
        (field (name "COPYRIGHT") "Copyright (C) 2025 Ultra Librarian. All rights reserved.")
      )
      (libsource (lib "eagle-import") (part "TPS552882"))
    )
    (comp (ref "IC22")
      (value "INA219BIDCNT")
      (footprint "eagle-import:SOT23-8")
      (libsource (lib "eagle-import") (part "INA219BIDCNT"))
    )
    (comp (ref "L5")
      (value "4.7uH 744771004")
      (footprint "eagle-import:WE-PD_1280")
      (libsource (lib "eagle-import") (part "WE-PD_1280_74477004"))
    )
    (comp (ref "PORT4")
      (value "632722100213")
      (footprint "eagle-import:632722100213")
      (libsource (lib "eagle-import") (part "632722100213"))
    )
    (comp (ref "R114")
      (value "200K")
      (footprint "eagle-import:R0201")
      (libsource (lib "eagle-import") (part "R0201"))
    )
    (comp (ref "R115")
      (value "12.7K 0.1%")
      (footprint "eagle-import:R0201")
      (libsource (lib "eagle-import") (part "R0201"))
    )
    (comp (ref "R116")
      (value "4.64K 0.1%")
      (footprint "eagle-import:R0201")
      (libsource (lib "eagle-import") (part "R0201"))
    )
    (comp (ref "R117")
      (value "4.64K 0.1%")
      (footprint "eagle-import:R0201")
      (libsource (lib "eagle-import") (part "R0201"))
    )
    (comp (ref "R118")
      (value "8.87K 0.1%")
      (footprint "eagle-import:R0201")
      (libsource (lib "eagle-import") (part "R0201"))
    )
    (comp (ref "R119")
      (value "30.9K 0.1%")
      (footprint "eagle-import:R0201")
      (libsource (lib "eagle-import") (part "R0201"))
    )
    (comp (ref "R120")
      (value "100K")
      (footprint "eagle-import:R0201")
      (libsource (lib "eagle-import") (part "R0201"))
    )
    (comp (ref "R121")
      (value "DNI")
      (footprint "eagle-import:R0201")
      (libsource (lib "eagle-import") (part "R0201"))
    )
    (comp (ref "R122")
      (value "10K")
      (footprint "eagle-import:0402")
      (libsource (lib "eagle-import") (part "R0402"))
    )
    (comp (ref "R123")
      (value "10K")
      (footprint "eagle-import:0402")
      (libsource (lib "eagle-import") (part "R0402"))
    )
    (comp (ref "R124")
      (value "10K")
      (footprint "eagle-import:R0201")
      (libsource (lib "eagle-import") (part "R0201"))
    )
    (comp (ref "R125")
      (value "2.2K")
      (footprint "eagle-import:R0201")
      (libsource (lib "eagle-import") (part "R0201"))
    )
    (comp (ref "R126")
      (value "10K")
      (footprint "eagle-import:0402")
      (libsource (lib "eagle-import") (part "R0402"))
    )
    (comp (ref "R127")
      (value "0.010R")
      (footprint "eagle-import:2512")
      (libsource (lib "eagle-import") (part "R2512"))
    )
    (comp (ref "R128")
      (value "6.19K")
      (footprint "eagle-import:R0201")
      (libsource (lib "eagle-import") (part "R0201"))
    )
    (comp (ref "R129")
      (value "49.9K")
      (footprint "eagle-import:R0201")
      (libsource (lib "eagle-import") (part "R0201"))
    )
    (comp (ref "R130")
      (value "19.9K")
      (footprint "eagle-import:R0201")
      (libsource (lib "eagle-import") (part "R0201"))
    )
    (comp (ref "R131")
      (value "150K")
      (footprint "eagle-import:R0201")
      (libsource (lib "eagle-import") (part "R0201"))
    )
    (comp (ref "R132")
      (value "19.9K")
      (footprint "eagle-import:R0201")
      (libsource (lib "eagle-import") (part "R0201"))
    )
    (comp (ref "R133")
      (value "0.010R")
      (footprint "eagle-import:2512")
      (libsource (lib "eagle-import") (part "R2512"))
    )
    (comp (ref "R134")
      (value "1K")
      (footprint "eagle-import:R0201")
      (libsource (lib "eagle-import") (part "R0201"))
    )
    (comp (ref "R135")
      (value "1K")
      (footprint "eagle-import:R0201")
      (libsource (lib "eagle-import") (part "R0201"))
    )
    (comp (ref "R136")
      (value "10K")
      (footprint "eagle-import:R0201")
      (libsource (lib "eagle-import") (part "R0201"))
    )
    (comp (ref "T21")
      (value "DMP3013SFV")
      (footprint "eagle-import:POWERDI3333-8_UX_DIO-L")
      (fields (field (name "MANUFACTURER_PART_NUMBER") "DMP3013SFV-7"))
      (libsource (lib "eagle-import") (part "DMP3013SFV-7UX"))
    )
    (comp (ref "T22")
      (value "DMP3013SFV")
      (footprint "eagle-import:POWERDI3333-8_UX_DIO-L")
      (fields (field (name "MANUFACTURER_PART_NUMBER") "DMP3013SFV-7"))
      (libsource (lib "eagle-import") (part "DMP3013SFV-7UX"))
    )
    (comp (ref "T23")
      (value "DMP3013SFV")
      (footprint "eagle-import:POWERDI3333-8_UX_DIO-L")
      (fields (field (name "MANUFACTURER_PART_NUMBER") "DMP3013SFV-7"))
      (libsource (lib "eagle-import") (part "DMP3013SFV-7UX"))
    )
    (comp (ref "T24")
      (value "BSZ065N06LS5ATMA1")
      (footprint "eagle-import:POWERDI3333-8_UX_DIO-L")
      (fields
        (field (name "MANUFACTURER_PART_NUMBER") "IPZ40N04S5L7R4ATMA1")
        (field (name "COPYRIGHT") "Copyright (C) 2025 Ultra Librarian. All rights reserved.")
      )
      (libsource (lib "eagle-import") (part "IPZ40N04S5L7R4ATMA1"))
    )
    (comp (ref "T25")
      (value "BSZ065N06LS5ATMA1")
      (footprint "eagle-import:POWERDI3333-8_UX_DIO-L")
      (fields
        (field (name "MANUFACTURER_PART_NUMBER") "IPZ40N04S5L7R4ATMA1")
        (field (name "COPYRIGHT") "Copyright (C) 2025 Ultra Librarian. All rights reserved.")
      )
      (libsource (lib "eagle-import") (part "IPZ40N04S5L7R4ATMA1"))
    )
    (comp (ref "C212")
      (value "100nF")
      (footprint "eagle-import:0201")
      (libsource (lib "eagle-import") (part "C-0201"))
    )
    (comp (ref "C213")
      (value "1uF")
      (footprint "eagle-import:0201")
      (libsource (lib "eagle-import") (part "C-0201"))
    )
    (comp (ref "C214")
      (value "100nF")
      (footprint "eagle-import:0201")
      (libsource (lib "eagle-import") (part "C-0201"))
    )
    (comp (ref "C215")
      (value "6.8nF")
      (footprint "eagle-import:0201")
      (libsource (lib "eagle-import") (part "C-0201"))
    )
    (comp (ref "C216")
      (value "6.8nF")
      (footprint "eagle-import:0201")
      (libsource (lib "eagle-import") (part "C-0201"))
    )
    (comp (ref "C217")
      (value "100nF")
      (footprint "eagle-import:0201")
      (libsource (lib "eagle-import") (part "C-0201"))
    )
    (comp (ref "C218")
      (value "4.7uF")
      (footprint "eagle-import:C0402")
      (libsource (lib "eagle-import") (part "C-0402"))
    )
    (comp (ref "C219")
      (value "18pF")
      (footprint "eagle-import:0201")
      (libsource (lib "eagle-import") (part "C-0201"))
    )
    (comp (ref "C220")
      (value "18pF")
      (footprint "eagle-import:0201")
      (libsource (lib "eagle-import") (part "C-0201"))
    )
    (comp (ref "C221")
      (value "100nF")
      (footprint "eagle-import:0201")
      (libsource (lib "eagle-import") (part "C-0201"))
    )
    (comp (ref "C222")
      (value "100nF")
      (footprint "eagle-import:0201")
      (libsource (lib "eagle-import") (part "C-0201"))
    )
    (comp (ref "C223")
      (value "100nF")
      (footprint "eagle-import:0201")
      (libsource (lib "eagle-import") (part "C-0201"))
    )
    (comp (ref "C224")
      (value "100nF")
      (footprint "eagle-import:0201")
      (libsource (lib "eagle-import") (part "C-0201"))
    )
    (comp (ref "C225")
      (value "100nF")
      (footprint "eagle-import:0201")
      (libsource (lib "eagle-import") (part "C-0201"))
    )
    (comp (ref "C226")
      (value "100nF")
      (footprint "eagle-import:0201")
      (libsource (lib "eagle-import") (part "C-0201"))
    )
    (comp (ref "C227")
      (value "100nF")
      (footprint "eagle-import:0201")
      (libsource (lib "eagle-import") (part "C-0201"))
    )
    (comp (ref "C228")
      (value "100nF")
      (footprint "eagle-import:0201")
      (libsource (lib "eagle-import") (part "C-0201"))
    )
    (comp (ref "C229")
      (value "100nF")
      (footprint "eagle-import:0201")
      (libsource (lib "eagle-import") (part "C-0201"))
    )
    (comp (ref "C230")
      (value "22nF")
      (footprint "eagle-import:C0402")
      (libsource (lib "eagle-import") (part "C-0402"))
    )
    (comp (ref "C231")
      (value "C1206C102KGRACTM")
      (footprint "eagle-import:C1206")
      (libsource (lib "eagle-import") (part "C-1206"))
    )
    (comp (ref "C232")
      (value "4.7nF")
      (footprint "eagle-import:C0402")
      (libsource (lib "eagle-import") (part "C-0402"))
    )
    (comp (ref "C249")
      (value "100nF")
      (footprint "eagle-import:0201")
      (libsource (lib "eagle-import") (part "C-0201"))
    )
    (comp (ref "C251")
      (value "1uF")
      (footprint "eagle-import:0201")
      (libsource (lib "eagle-import") (part "C-0201"))
    )
    (comp (ref "DISP")
      (value "AFC11-S20ICC-00")
      (footprint "eagle-import:FPC20")
      (libsource (lib "eagle-import") (part "AFC11-S20ICC-00"))
    )
    (comp (ref "ETH1")
      (value "SI-60118-F")
      (footprint "eagle-import:RJ45-CAT5")
      (fields (field (name "MANUFACTURER") "Bel Fuse"))
      (libsource (lib "eagle-import") (part "RJ45-CAT5"))
    )
    (comp (ref "IC38")
      (value "TCA9548ARGER")
      (footprint "eagle-import:QFN50P400X400X100-25T210N")
      (libsource (lib "eagle-import") (part "TCA9548ARGER"))
    )
    (comp (ref "IC39")
      (value "W5500")
      (footprint "eagle-import:LQFP48")
      (libsource (lib "eagle-import") (part "W5500"))
    )
    (comp (ref "IC42")
      (value "MCP23017-E/ML")
      (footprint "eagle-import:QFN28[6X6]ML")
      (libsource (lib "eagle-import") (part "MCP23017-E/ML"))
    )
    (comp (ref "L10")
      (value "BLM18EG221TN1D")
      (footprint "eagle-import:0603")
      (libsource (lib "eagle-import") (part "R0603"))
    )
    (comp (ref "R215")
      (value "4D03WGJ0332T5E")
      (footprint "eagle-import:YC164-JR-0733RL")
      (fields
        (field (name "MANUFACTURER") "Yageo")
        (field (name "MPN") "YC164-JR-0733RL")
        (field (name "CREATED_BY") "PCBLayout.com")
      )
      (libsource (lib "eagle-import") (part "YC164-JR-0733RL"))
    )
    (comp (ref "R216")
      (value "4D03WGJ0332T5E")
      (footprint "eagle-import:YC164-JR-0733RL")
      (fields
        (field (name "MANUFACTURER") "Yageo")
        (field (name "MPN") "YC164-JR-0733RL")
        (field (name "CREATED_BY") "PCBLayout.com")
      )
      (libsource (lib "eagle-import") (part "YC164-JR-0733RL"))
    )
    (comp (ref "R217")
      (value "4D03WGJ0332T5E")
      (footprint "eagle-import:YC164-JR-0733RL")
      (fields
        (field (name "MANUFACTURER") "Yageo")
        (field (name "MPN") "YC164-JR-0733RL")
        (field (name "CREATED_BY") "PCBLayout.com")
      )
      (libsource (lib "eagle-import") (part "YC164-JR-0733RL"))
    )
    (comp (ref "R226")
      (value "3.3R")
      (footprint "eagle-import:R0201")
      (libsource (lib "eagle-import") (part "R0201"))
    )
    (comp (ref "R227")
      (value "3.3R")
      (footprint "eagle-import:R0201")
      (libsource (lib "eagle-import") (part "R0201"))
    )
    (comp (ref "R228")
      (value "3.3R")
      (footprint "eagle-import:R0201")
      (libsource (lib "eagle-import") (part "R0201"))
    )
    (comp (ref "R229")
      (value "3.3R")
      (footprint "eagle-import:R0201")
      (libsource (lib "eagle-import") (part "R0201"))
    )
    (comp (ref "R230")
      (value "49.9R")
      (footprint "eagle-import:R0201")
      (libsource (lib "eagle-import") (part "R0201"))
    )
    (comp (ref "R231")
      (value "49.9R")
      (footprint "eagle-import:R0201")
      (libsource (lib "eagle-import") (part "R0201"))
    )
    (comp (ref "R232")
      (value "49.9R")
      (footprint "eagle-import:R0201")
      (libsource (lib "eagle-import") (part "R0201"))
    )
    (comp (ref "R233")
      (value "49.9R")
      (footprint "eagle-import:R0201")
      (libsource (lib "eagle-import") (part "R0201"))
    )
    (comp (ref "R234")
      (value "12.4K 1%")
      (footprint "eagle-import:R0201")
      (libsource (lib "eagle-import") (part "R0201"))
    )
    (comp (ref "R235")
      (value "1M")
      (footprint "eagle-import:R0201")
      (libsource (lib "eagle-import") (part "R0201"))
    )
    (comp (ref "R236")
      (value "4.7K")
      (footprint "eagle-import:R0201")
      (libsource (lib "eagle-import") (part "R0201"))
    )
    (comp (ref "R237")
      (value "470R")
      (footprint "eagle-import:0402")
      (libsource (lib "eagle-import") (part "R0402"))
    )
    (comp (ref "R238")
      (value "470R")
      (footprint "eagle-import:0402")
      (libsource (lib "eagle-import") (part "R0402"))
    )
    (comp (ref "R239")
      (value "470R")
      (footprint "eagle-import:0402")
      (libsource (lib "eagle-import") (part "R0402"))
    )
    (comp (ref "R240")
      (value "10K")
      (footprint "eagle-import:0402")
      (libsource (lib "eagle-import") (part "R0402"))
    )
    (comp (ref "R252")
      (value "10K")
      (footprint "eagle-import:0402")
      (libsource (lib "eagle-import") (part "R0402"))
    )
    (comp (ref "R253")
      (value "4D03WGJ0332T5E")
      (footprint "eagle-import:742C083103JP")
      (fields
        (field (name "MANUFACTURER") "CTS Resistor Products")
        (field (name "MPN") "742C083103JP")
        (field (name "CREATED_BY") "PCBLayout.com")
      )
      (libsource (lib "eagle-import") (part "742C083103JP"))
    )
    (comp (ref "X2")
      (value "X322525MOB4SI")
      (footprint "eagle-import:WE-XTAL_CFPX-180")
      (fields (field (name "TOLERANCE") "±50ppm"))
      (libsource (lib "eagle-import") (part "WE-XTAL_CFPX-180_830035268"))
    )
    (comp (ref "C1")
      (value "4.7nF")
      (footprint "eagle-import:C0402")
      (libsource (lib "eagle-import") (part "C-0402"))
    )
    (comp (ref "C2")
      (value "100nF")
      (footprint "eagle-import:C0402")
      (libsource (lib "eagle-import") (part "C-0402"))
    )
    (comp (ref "C3")
      (value "10uF")
      (footprint "eagle-import:C0805")
      (libsource (lib "eagle-import") (part "C-0805"))
    )
    (comp (ref "C4")
      (value "10uF")
      (footprint "eagle-import:C0805")
      (libsource (lib "eagle-import") (part "C-0805"))
    )
    (comp (ref "C5")
      (value "100uF 16V")
      (footprint "eagle-import:100UF-16V")
      (libsource (lib "eagle-import") (part "CPOL"))
    )
    (comp (ref "C7")
      (value "100nF")
      (footprint "eagle-import:C0402")
      (libsource (lib "eagle-import") (part "C-0402"))
    )
    (comp (ref "C8")
      (value "10uF")
      (footprint "eagle-import:C0805")
      (libsource (lib "eagle-import") (part "C-0805"))
    )
    (comp (ref "C9")
      (value "10uF")
      (footprint "eagle-import:C0805")
      (libsource (lib "eagle-import") (part "C-0805"))
    )
    (comp (ref "C10")
      (value "100uF 16V")
      (footprint "eagle-import:100UF-16V")
      (libsource (lib "eagle-import") (part "CPOL"))
    )
    (comp (ref "C11")
      (value "4.7nF")
      (footprint "eagle-import:C0402")
      (libsource (lib "eagle-import") (part "C-0402"))
    )
    (comp (ref "C12")
      (value "100nF")
      (footprint "eagle-import:C0402")
      (libsource (lib "eagle-import") (part "C-0402"))
    )
    (comp (ref "C13")
      (value "10uF")
      (footprint "eagle-import:C0805")
      (libsource (lib "eagle-import") (part "C-0805"))
    )
    (comp (ref "C14")
      (value "10uF")
      (footprint "eagle-import:C0805")
      (libsource (lib "eagle-import") (part "C-0805"))
    )
    (comp (ref "C15")
      (value "100uF 16V")
      (footprint "eagle-import:100UF-16V")
      (libsource (lib "eagle-import") (part "CPOL"))
    )
    (comp (ref "C17")
      (value "100nF")
      (footprint "eagle-import:C0402")
      (libsource (lib "eagle-import") (part "C-0402"))
    )
    (comp (ref "C18")
      (value "100nF")
      (footprint "eagle-import:C0402")
      (libsource (lib "eagle-import") (part "C-0402"))
    )
    (comp (ref "C19")
      (value "100nF")
      (footprint "eagle-import:C0402")
      (libsource (lib "eagle-import") (part "C-0402"))
    )
    (comp (ref "C20")
      (value "100nF")
      (footprint "eagle-import:C0402")
      (libsource (lib "eagle-import") (part "C-0402"))
    )
    (comp (ref "C82")
      (value "100nF")
      (footprint "eagle-import:C0402")
      (libsource (lib "eagle-import") (part "C-0402"))
    )
    (comp (ref "C83")
      (value "10uF")
      (footprint "eagle-import:C0805")
      (libsource (lib "eagle-import") (part "C-0805"))
    )
    (comp (ref "C84")
      (value "10uF")
      (footprint "eagle-import:C0805")
      (libsource (lib "eagle-import") (part "C-0805"))
    )
    (comp (ref "C85")
      (value "100uF 16V")
      (footprint "eagle-import:100UF-16V")
      (libsource (lib "eagle-import") (part "CPOL"))
    )
    (comp (ref "D1")
      (value "GREEN")
      (footprint "eagle-import:LEDC1608X35N_FLAT-G")
      (libsource (lib "eagle-import") (part "CHIP-FLAT-G_0603-0.35MM"))
    )
    (comp (ref "D2")
      (value "RED")
      (footprint "eagle-import:LEDC1608X35N_FLAT-R")
      (libsource (lib "eagle-import") (part "CHIP-FLAT-R_0603-0.35MM"))
    )
    (comp (ref "D3")
      (value "GREEN")
      (footprint "eagle-import:LEDC1608X35N_FLAT-G")
      (libsource (lib "eagle-import") (part "CHIP-FLAT-G_0603-0.35MM"))
    )
    (comp (ref "D4")
      (value "RED")
      (footprint "eagle-import:LEDC1608X35N_FLAT-R")
      (libsource (lib "eagle-import") (part "CHIP-FLAT-R_0603-0.35MM"))
    )
    (comp (ref "D5")
      (value "GREEN")
      (footprint "eagle-import:LEDC1608X35N_FLAT-G")
      (libsource (lib "eagle-import") (part "CHIP-FLAT-G_0603-0.35MM"))
    )
    (comp (ref "D6")
      (value "RED")
      (footprint "eagle-import:LEDC1608X35N_FLAT-R")
      (libsource (lib "eagle-import") (part "CHIP-FLAT-R_0603-0.35MM"))
    )
    (comp (ref "D7")
      (value "GREEN")
      (footprint "eagle-import:LEDC1608X35N_FLAT-G")
      (libsource (lib "eagle-import") (part "CHIP-FLAT-G_0603-0.35MM"))
    )
    (comp (ref "D8")
      (value "RED")
      (footprint "eagle-import:LEDC1608X35N_FLAT-R")
      (libsource (lib "eagle-import") (part "CHIP-FLAT-R_0603-0.35MM"))
    )
    (comp (ref "IC1")
      (value "AP22653W6-7")
      (footprint "eagle-import:SOT23-6")
      (libsource (lib "eagle-import") (part "AP22653W6"))
    )
    (comp (ref "IC2")
      (value "AP22653W6-7")
      (footprint "eagle-import:SOT23-6")
      (libsource (lib "eagle-import") (part "AP22653W6"))
    )
    (comp (ref "IC3")
      (value "AP22653W6-7")
      (footprint "eagle-import:SOT23-6")
      (libsource (lib "eagle-import") (part "AP22653W6"))
    )
    (comp (ref "IC4")
      (value "SN74LVC1G04DBVR")
      (footprint "eagle-import:SOT95P280X145-5N")
      (libsource (lib "eagle-import") (part "74LVC1G04"))
    )
    (comp (ref "IC5")
      (value "SN74LVC1G04DBVR")
      (footprint "eagle-import:SOT95P280X145-5N")
      (libsource (lib "eagle-import") (part "74LVC1G04"))
    )
    (comp (ref "IC6")
      (value "SN74LVC1G04DBVR")
      (footprint "eagle-import:SOT95P280X145-5N")
      (libsource (lib "eagle-import") (part "74LVC1G04"))
    )
    (comp (ref "IC7")
      (value "SN74LVC1G04DBVR")
      (footprint "eagle-import:SOT95P280X145-5N")
      (libsource (lib "eagle-import") (part "74LVC1G04"))
    )
    (comp (ref "IC8")
      (value "AP22653W6-7")
      (footprint "eagle-import:SOT23-6")
      (libsource (lib "eagle-import") (part "AP22653W6"))
    )
    (comp (ref "R1")
      (value "10K")
      (footprint "eagle-import:0402")
      (libsource (lib "eagle-import") (part "R0402"))
    )
    (comp (ref "R2")
      (value "10K")
      (footprint "eagle-import:0402")
      (libsource (lib "eagle-import") (part "R0402"))
    )
    (comp (ref "R3")
      (value "20K 1%")
      (footprint "eagle-import:0402")
      (libsource (lib "eagle-import") (part "R0402"))
    )
    (comp (ref "R4")
      (value "10K")
      (footprint "eagle-import:0402")
      (libsource (lib "eagle-import") (part "R0402"))
    )
    (comp (ref "R6")
      (value "20K 1%")
      (footprint "eagle-import:0402")
      (libsource (lib "eagle-import") (part "R0402"))
    )
    (comp (ref "R7")
      (value "10K")
      (footprint "eagle-import:0402")
      (libsource (lib "eagle-import") (part "R0402"))
    )
    (comp (ref "R8")
      (value "10K")
      (footprint "eagle-import:0402")
      (libsource (lib "eagle-import") (part "R0402"))
    )
    (comp (ref "R9")
      (value "20K 1%")
      (footprint "eagle-import:0402")
      (libsource (lib "eagle-import") (part "R0402"))
    )
    (comp (ref "R10")
      (value "10K")
      (footprint "eagle-import:0402")
      (libsource (lib "eagle-import") (part "R0402"))
    )
    (comp (ref "R12")
      (value "1K")
      (footprint "eagle-import:0402")
      (libsource (lib "eagle-import") (part "R0402"))
    )
    (comp (ref "R13")
      (value "10K")
      (footprint "eagle-import:0402")
      (libsource (lib "eagle-import") (part "R0402"))
    )
    (comp (ref "R14")
      (value "1K")
      (footprint "eagle-import:0402")
      (libsource (lib "eagle-import") (part "R0402"))
    )
    (comp (ref "R15")
      (value "1K")
      (footprint "eagle-import:0402")
      (libsource (lib "eagle-import") (part "R0402"))
    )
    (comp (ref "R16")
      (value "10K")
      (footprint "eagle-import:0402")
      (libsource (lib "eagle-import") (part "R0402"))
    )
    (comp (ref "R17")
      (value "1K")
      (footprint "eagle-import:0402")
      (libsource (lib "eagle-import") (part "R0402"))
    )
    (comp (ref "R18")
      (value "1K")
      (footprint "eagle-import:0402")
      (libsource (lib "eagle-import") (part "R0402"))
    )
    (comp (ref "R19")
      (value "10K")
      (footprint "eagle-import:0402")
      (libsource (lib "eagle-import") (part "R0402"))
    )
    (comp (ref "R20")
      (value "1K")
      (footprint "eagle-import:0402")
      (libsource (lib "eagle-import") (part "R0402"))
    )
    (comp (ref "R21")
      (value "1K")
      (footprint "eagle-import:0402")
      (libsource (lib "eagle-import") (part "R0402"))
    )
    (comp (ref "R22")
      (value "10K")
      (footprint "eagle-import:0402")
      (libsource (lib "eagle-import") (part "R0402"))
    )
    (comp (ref "R23")
      (value "1K")
      (footprint "eagle-import:0402")
      (libsource (lib "eagle-import") (part "R0402"))
    )
    (comp (ref "R84")
      (value "20K 1%")
      (footprint "eagle-import:0402")
      (libsource (lib "eagle-import") (part "R0402"))
    )
    (comp (ref "USBA_1-2")
      (value "61400826021")
      (footprint "eagle-import:61400826021")
      (libsource (lib "eagle-import") (part "61400826021"))
    )
    (comp (ref "USBA_3-4")
      (value "61400826021")
      (footprint "eagle-import:61400826021")
      (libsource (lib "eagle-import") (part "61400826021"))
    )
    (comp (ref "VUSBA1")
      (value "TPB1,27")
      (footprint "eagle-import:B1,27")
      (libsource (lib "eagle-import") (part "TPB1,27"))
    )
    (comp (ref "VUSBA2")
      (value "TPB1,27")
      (footprint "eagle-import:B1,27")
      (libsource (lib "eagle-import") (part "TPB1,27"))
    )
    (comp (ref "VUSBA3")
      (value "TPB1,27")
      (footprint "eagle-import:B1,27")
      (libsource (lib "eagle-import") (part "TPB1,27"))
    )
    (comp (ref "VUSBA4")
      (value "TPB1,27")
      (footprint "eagle-import:B1,27")
      (libsource (lib "eagle-import") (part "TPB1,27"))
    )
    (comp (ref "C117")
      (value "1uF 10V")
      (footprint "eagle-import:0201")
      (libsource (lib "eagle-import") (part "C-0201"))
    )
    (comp (ref "C118")
      (value "1uF 10V")
      (footprint "eagle-import:0201")
      (libsource (lib "eagle-import") (part "C-0201"))
    )
    (comp (ref "C119")
      (value "1uF 50V")
      (footprint "eagle-import:C0603")
      (libsource (lib "eagle-import") (part "C-0603"))
    )
    (comp (ref "C120")
      (value "4.7nF")
      (footprint "eagle-import:C0402")
      (libsource (lib "eagle-import") (part "C-0402"))
    )
    (comp (ref "C121")
      (value "4.7uF")
      (footprint "eagle-import:C0402")
      (libsource (lib "eagle-import") (part "C-0402"))
    )
    (comp (ref "C122")
      (value "10nF")
      (footprint "eagle-import:0201")
      (libsource (lib "eagle-import") (part "C-0201"))
    )
    (comp (ref "C123")
      (value "10nF")
      (footprint "eagle-import:0201")
      (libsource (lib "eagle-import") (part "C-0201"))
    )
    (comp (ref "C124")
      (value "10nF")
      (footprint "eagle-import:0201")
      (libsource (lib "eagle-import") (part "C-0201"))
    )
    (comp (ref "C125")
      (value "100nF")
      (footprint "eagle-import:C0402")
      (libsource (lib "eagle-import") (part "C-0402"))
    )
    (comp (ref "C126")
      (value "100nF")
      (footprint "eagle-import:C0402")
      (libsource (lib "eagle-import") (part "C-0402"))
    )
    (comp (ref "C127")
      (value "10uF 50V")
      (footprint "eagle-import:C0805")
      (libsource (lib "eagle-import") (part "C-0805"))
    )
    (comp (ref "C128")
      (value "10uF 50V")
      (footprint "eagle-import:C0805")
      (libsource (lib "eagle-import") (part "C-0805"))
    )
    (comp (ref "C129")
      (value "10uF 50V")
      (footprint "eagle-import:C0805")
      (libsource (lib "eagle-import") (part "C-0805"))
    )
    (comp (ref "C130")
      (value "10uF 50V")
      (footprint "eagle-import:C0805")
      (libsource (lib "eagle-import") (part "C-0805"))
    )
    (comp (ref "C131")
      (value "22uF 50V")
      (footprint "eagle-import:C0805")
      (libsource (lib "eagle-import") (part "C-0805"))
    )
    (comp (ref "C132")
      (value "22uF 50V")
      (footprint "eagle-import:C0805")
      (libsource (lib "eagle-import") (part "C-0805"))
    )
    (comp (ref "C133")
      (value "22uF 50V")
      (footprint "eagle-import:C0805")
      (libsource (lib "eagle-import") (part "C-0805"))
    )
    (comp (ref "C134")
      (value "22uF 50V")
      (footprint "eagle-import:C0805")
      (libsource (lib "eagle-import") (part "C-0805"))
    )
    (comp (ref "C135")
      (value "100nF")
      (footprint "eagle-import:0201")
      (libsource (lib "eagle-import") (part "C-0201"))
    )
    (comp (ref "IC11")
      (value "STUSB4710AQ1TR")
      (footprint "eagle-import:QFN50P300X300X55-16N")
      (libsource (lib "eagle-import") (part "STUSB4710AQ1TR"))
    )
    (comp (ref "IC24")
      (value "TPS552882")
      (footprint "eagle-import:RPM0026A-MFG")
      (fields
        (field (name "MANUFACTURER_PART_NUMBER") "TPS552882QRPMRQ1")
        (field (name "COPYRIGHT") "Copyright (C) 2025 Ultra Librarian. All rights reserved.")
      )
      (libsource (lib "eagle-import") (part "TPS552882"))
    )
    (comp (ref "IC25")
      (value "INA219BIDCNT")
      (footprint "eagle-import:SOT23-8")
      (libsource (lib "eagle-import") (part "INA219BIDCNT"))
    )
    (comp (ref "L6")
      (value "4.7uH 744771004")
      (footprint "eagle-import:WE-PD_1280")
      (libsource (lib "eagle-import") (part "WE-PD_1280_74477004"))
    )
    (comp (ref "PORT3")
      (value "632722100213")
      (footprint "eagle-import:632722100213")
      (libsource (lib "eagle-import") (part "632722100213"))
    )
    (comp (ref "R137")
      (value "200K")
      (footprint "eagle-import:R0201")
      (libsource (lib "eagle-import") (part "R0201"))
    )
    (comp (ref "R138")
      (value "12.7K 0.1%")
      (footprint "eagle-import:R0201")
      (libsource (lib "eagle-import") (part "R0201"))
    )
    (comp (ref "R139")
      (value "4.64K 0.1%")
      (footprint "eagle-import:R0201")
      (libsource (lib "eagle-import") (part "R0201"))
    )
    (comp (ref "R140")
      (value "4.64K 0.1%")
      (footprint "eagle-import:R0201")
      (libsource (lib "eagle-import") (part "R0201"))
    )
    (comp (ref "R141")
      (value "8.87K 0.1%")
      (footprint "eagle-import:R0201")
      (libsource (lib "eagle-import") (part "R0201"))
    )
    (comp (ref "R142")
      (value "30.9K 0.1%")
      (footprint "eagle-import:R0201")
      (libsource (lib "eagle-import") (part "R0201"))
    )
    (comp (ref "R143")
      (value "DNI")
      (footprint "eagle-import:R0201")
      (libsource (lib "eagle-import") (part "R0201"))
    )
    (comp (ref "R144")
      (value "100K")
      (footprint "eagle-import:R0201")
      (libsource (lib "eagle-import") (part "R0201"))
    )
    (comp (ref "R145")
      (value "10K")
      (footprint "eagle-import:0402")
      (libsource (lib "eagle-import") (part "R0402"))
    )
    (comp (ref "R146")
      (value "10K")
      (footprint "eagle-import:0402")
      (libsource (lib "eagle-import") (part "R0402"))
    )
    (comp (ref "R147")
      (value "10K")
      (footprint "eagle-import:R0201")
      (libsource (lib "eagle-import") (part "R0201"))
    )
    (comp (ref "R148")
      (value "2.2K")
      (footprint "eagle-import:R0201")
      (libsource (lib "eagle-import") (part "R0201"))
    )
    (comp (ref "R149")
      (value "10K")
      (footprint "eagle-import:0402")
      (libsource (lib "eagle-import") (part "R0402"))
    )
    (comp (ref "R150")
      (value "0.010R")
      (footprint "eagle-import:2512")
      (libsource (lib "eagle-import") (part "R2512"))
    )
    (comp (ref "R151")
      (value "6.19K")
      (footprint "eagle-import:R0201")
      (libsource (lib "eagle-import") (part "R0201"))
    )
    (comp (ref "R152")
      (value "49.9K")
      (footprint "eagle-import:R0201")
      (libsource (lib "eagle-import") (part "R0201"))
    )
    (comp (ref "R153")
      (value "19.9K")
      (footprint "eagle-import:R0201")
      (libsource (lib "eagle-import") (part "R0201"))
    )
    (comp (ref "R154")
      (value "150K")
      (footprint "eagle-import:R0201")
      (libsource (lib "eagle-import") (part "R0201"))
    )
    (comp (ref "R155")
      (value "19.9K")
      (footprint "eagle-import:R0201")
      (libsource (lib "eagle-import") (part "R0201"))
    )
    (comp (ref "R156")
      (value "0.010R")
      (footprint "eagle-import:2512")
      (libsource (lib "eagle-import") (part "R2512"))
    )
    (comp (ref "R157")
      (value "1K")
      (footprint "eagle-import:R0201")
      (libsource (lib "eagle-import") (part "R0201"))
    )
    (comp (ref "R158")
      (value "1K")
      (footprint "eagle-import:R0201")
      (libsource (lib "eagle-import") (part "R0201"))
    )
    (comp (ref "R159")
      (value "10K")
      (footprint "eagle-import:R0201")
      (libsource (lib "eagle-import") (part "R0201"))
    )
    (comp (ref "T26")
      (value "DMP3013SFV")
      (footprint "eagle-import:POWERDI3333-8_UX_DIO-L")
      (fields (field (name "MANUFACTURER_PART_NUMBER") "DMP3013SFV-7"))
      (libsource (lib "eagle-import") (part "DMP3013SFV-7UX"))
    )
    (comp (ref "T27")
      (value "DMP3013SFV")
      (footprint "eagle-import:POWERDI3333-8_UX_DIO-L")
      (fields (field (name "MANUFACTURER_PART_NUMBER") "DMP3013SFV-7"))
      (libsource (lib "eagle-import") (part "DMP3013SFV-7UX"))
    )
    (comp (ref "T28")
      (value "DMP3013SFV")
      (footprint "eagle-import:POWERDI3333-8_UX_DIO-L")
      (fields (field (name "MANUFACTURER_PART_NUMBER") "DMP3013SFV-7"))
      (libsource (lib "eagle-import") (part "DMP3013SFV-7UX"))
    )
    (comp (ref "T29")
      (value "BSZ065N06LS5ATMA1")
      (footprint "eagle-import:POWERDI3333-8_UX_DIO-L")
      (fields
        (field (name "MANUFACTURER_PART_NUMBER") "IPZ40N04S5L7R4ATMA1")
        (field (name "COPYRIGHT") "Copyright (C) 2025 Ultra Librarian. All rights reserved.")
      )
      (libsource (lib "eagle-import") (part "IPZ40N04S5L7R4ATMA1"))
    )
    (comp (ref "T30")
      (value "BSZ065N06LS5ATMA1")
      (footprint "eagle-import:POWERDI3333-8_UX_DIO-L")
      (fields
        (field (name "MANUFACTURER_PART_NUMBER") "IPZ40N04S5L7R4ATMA1")
        (field (name "COPYRIGHT") "Copyright (C) 2025 Ultra Librarian. All rights reserved.")
      )
      (libsource (lib "eagle-import") (part "IPZ40N04S5L7R4ATMA1"))
    )
    (comp (ref "C6")
      (value "1uF 10V")
      (footprint "eagle-import:0201")
      (libsource (lib "eagle-import") (part "C-0201"))
    )
    (comp (ref "C16")
      (value "1uF 10V")
      (footprint "eagle-import:0201")
      (libsource (lib "eagle-import") (part "C-0201"))
    )
    (comp (ref "C39")
      (value "1uF 50V")
      (footprint "eagle-import:C0603")
      (libsource (lib "eagle-import") (part "C-0603"))
    )
    (comp (ref "C40")
      (value "4.7nF")
      (footprint "eagle-import:C0402")
      (libsource (lib "eagle-import") (part "C-0402"))
    )
    (comp (ref "C41")
      (value "4.7uF")
      (footprint "eagle-import:C0402")
      (libsource (lib "eagle-import") (part "C-0402"))
    )
    (comp (ref "C42")
      (value "10nF")
      (footprint "eagle-import:0201")
      (libsource (lib "eagle-import") (part "C-0201"))
    )
    (comp (ref "C43")
      (value "10nF")
      (footprint "eagle-import:0201")
      (libsource (lib "eagle-import") (part "C-0201"))
    )
    (comp (ref "C44")
      (value "10nF")
      (footprint "eagle-import:0201")
      (libsource (lib "eagle-import") (part "C-0201"))
    )
    (comp (ref "C45")
      (value "100nF")
      (footprint "eagle-import:C0402")
      (libsource (lib "eagle-import") (part "C-0402"))
    )
    (comp (ref "C46")
      (value "100nF")
      (footprint "eagle-import:C0402")
      (libsource (lib "eagle-import") (part "C-0402"))
    )
    (comp (ref "C47")
      (value "10uF 50V")
      (footprint "eagle-import:C0805")
      (libsource (lib "eagle-import") (part "C-0805"))
    )
    (comp (ref "C48")
      (value "10uF 50V")
      (footprint "eagle-import:C0805")
      (libsource (lib "eagle-import") (part "C-0805"))
    )
    (comp (ref "C49")
      (value "10uF 50V")
      (footprint "eagle-import:C0805")
      (libsource (lib "eagle-import") (part "C-0805"))
    )
    (comp (ref "C50")
      (value "10uF 50V")
      (footprint "eagle-import:C0805")
      (libsource (lib "eagle-import") (part "C-0805"))
    )
    (comp (ref "C51")
      (value "22uF 50V")
      (footprint "eagle-import:C0805")
      (libsource (lib "eagle-import") (part "C-0805"))
    )
    (comp (ref "C52")
      (value "22uF 50V")
      (footprint "eagle-import:C0805")
      (libsource (lib "eagle-import") (part "C-0805"))
    )
    (comp (ref "C53")
      (value "22uF 50V")
      (footprint "eagle-import:C0805")
      (libsource (lib "eagle-import") (part "C-0805"))
    )
    (comp (ref "C54")
      (value "22uF 50V")
      (footprint "eagle-import:C0805")
      (libsource (lib "eagle-import") (part "C-0805"))
    )
    (comp (ref "C55")
      (value "100nF")
      (footprint "eagle-import:0201")
      (libsource (lib "eagle-import") (part "C-0201"))
    )
    (comp (ref "IC9")
      (value "STUSB4710AQ1TR")
      (footprint "eagle-import:QFN50P300X300X55-16N")
      (libsource (lib "eagle-import") (part "STUSB4710AQ1TR"))
    )
    (comp (ref "IC12")
      (value "TPS552882")
      (footprint "eagle-import:RPM0026A-MFG")
      (fields
        (field (name "MANUFACTURER_PART_NUMBER") "TPS552882QRPMRQ1")
        (field (name "COPYRIGHT") "Copyright (C) 2025 Ultra Librarian. All rights reserved.")
      )
      (libsource (lib "eagle-import") (part "TPS552882"))
    )
    (comp (ref "IC13")
      (value "INA219BIDCNT")
      (footprint "eagle-import:SOT23-8")
      (libsource (lib "eagle-import") (part "INA219BIDCNT"))
    )
    (comp (ref "L2")
      (value "4.7uH 744771004")
      (footprint "eagle-import:WE-PD_1280")
      (libsource (lib "eagle-import") (part "WE-PD_1280_74477004"))
    )
    (comp (ref "PORT1")
      (value "632722100213")
      (footprint "eagle-import:632722100213")
      (libsource (lib "eagle-import") (part "632722100213"))
    )
    (comp (ref "R5")
      (value "200K")
      (footprint "eagle-import:R0201")
      (libsource (lib "eagle-import") (part "R0201"))
    )
    (comp (ref "R11")
      (value "12.7K 0.1%")
      (footprint "eagle-import:R0201")
      (libsource (lib "eagle-import") (part "R0201"))
    )
    (comp (ref "R46")
      (value "4.64K 0.1%")
      (footprint "eagle-import:R0201")
      (libsource (lib "eagle-import") (part "R0201"))
    )
    (comp (ref "R47")
      (value "4.64K 0.1%")
      (footprint "eagle-import:R0201")
      (libsource (lib "eagle-import") (part "R0201"))
    )
    (comp (ref "R48")
      (value "8.87K 0.1%")
      (footprint "eagle-import:R0201")
      (libsource (lib "eagle-import") (part "R0201"))
    )
    (comp (ref "R49")
      (value "30.9K 0.1%")
      (footprint "eagle-import:R0201")
      (libsource (lib "eagle-import") (part "R0201"))
    )
    (comp (ref "R50")
      (value "DNI")
      (footprint "eagle-import:R0201")
      (libsource (lib "eagle-import") (part "R0201"))
    )
    (comp (ref "R51")
      (value "100K")
      (footprint "eagle-import:R0201")
      (libsource (lib "eagle-import") (part "R0201"))
    )
    (comp (ref "R52")
      (value "10K")
      (footprint "eagle-import:0402")
      (libsource (lib "eagle-import") (part "R0402"))
    )
    (comp (ref "R53")
      (value "10K")
      (footprint "eagle-import:0402")
      (libsource (lib "eagle-import") (part "R0402"))
    )
    (comp (ref "R54")
      (value "10K")
      (footprint "eagle-import:R0201")
      (libsource (lib "eagle-import") (part "R0201"))
    )
    (comp (ref "R55")
      (value "2.2K")
      (footprint "eagle-import:R0201")
      (libsource (lib "eagle-import") (part "R0201"))
    )
    (comp (ref "R56")
      (value "10K")
      (footprint "eagle-import:0402")
      (libsource (lib "eagle-import") (part "R0402"))
    )
    (comp (ref "R57")
      (value "0.010R")
      (footprint "eagle-import:2512")
      (libsource (lib "eagle-import") (part "R2512"))
    )
    (comp (ref "R58")
      (value "6.19K")
      (footprint "eagle-import:R0201")
      (libsource (lib "eagle-import") (part "R0201"))
    )
    (comp (ref "R59")
      (value "49.9K")
      (footprint "eagle-import:R0201")
      (libsource (lib "eagle-import") (part "R0201"))
    )
    (comp (ref "R60")
      (value "19.9K")
      (footprint "eagle-import:R0201")
      (libsource (lib "eagle-import") (part "R0201"))
    )
    (comp (ref "R61")
      (value "150K")
      (footprint "eagle-import:R0201")
      (libsource (lib "eagle-import") (part "R0201"))
    )
    (comp (ref "R62")
      (value "19.9K")
      (footprint "eagle-import:R0201")
      (libsource (lib "eagle-import") (part "R0201"))
    )
    (comp (ref "R63")
      (value "0.010R")
      (footprint "eagle-import:2512")
      (libsource (lib "eagle-import") (part "R2512"))
    )
    (comp (ref "R64")
      (value "1K")
      (footprint "eagle-import:R0201")
      (libsource (lib "eagle-import") (part "R0201"))
    )
    (comp (ref "R65")
      (value "1K")
      (footprint "eagle-import:R0201")
      (libsource (lib "eagle-import") (part "R0201"))
    )
    (comp (ref "R66")
      (value "10K")
      (footprint "eagle-import:R0201")
      (libsource (lib "eagle-import") (part "R0201"))
    )
    (comp (ref "T6")
      (value "DMP3013SFV")
      (footprint "eagle-import:POWERDI3333-8_UX_DIO-L")
      (fields (field (name "MANUFACTURER_PART_NUMBER") "DMP3013SFV-7"))
      (libsource (lib "eagle-import") (part "DMP3013SFV-7UX"))
    )
    (comp (ref "T7")
      (value "DMP3013SFV")
      (footprint "eagle-import:POWERDI3333-8_UX_DIO-L")
      (fields (field (name "MANUFACTURER_PART_NUMBER") "DMP3013SFV-7"))
      (libsource (lib "eagle-import") (part "DMP3013SFV-7UX"))
    )
    (comp (ref "T8")
      (value "DMP3013SFV")
      (footprint "eagle-import:POWERDI3333-8_UX_DIO-L")
      (fields (field (name "MANUFACTURER_PART_NUMBER") "DMP3013SFV-7"))
      (libsource (lib "eagle-import") (part "DMP3013SFV-7UX"))
    )
    (comp (ref "T9")
      (value "BSZ065N06LS5ATMA1")
      (footprint "eagle-import:POWERDI3333-8_UX_DIO-L")
      (fields
        (field (name "MANUFACTURER_PART_NUMBER") "IPZ40N04S5L7R4ATMA1")
        (field (name "COPYRIGHT") "Copyright (C) 2025 Ultra Librarian. All rights reserved.")
      )
      (libsource (lib "eagle-import") (part "IPZ40N04S5L7R4ATMA1"))
    )
    (comp (ref "T10")
      (value "BSZ065N06LS5ATMA1")
      (footprint "eagle-import:POWERDI3333-8_UX_DIO-L")
      (fields
        (field (name "MANUFACTURER_PART_NUMBER") "IPZ40N04S5L7R4ATMA1")
        (field (name "COPYRIGHT") "Copyright (C) 2025 Ultra Librarian. All rights reserved.")
      )
      (libsource (lib "eagle-import") (part "IPZ40N04S5L7R4ATMA1"))
    )
    (comp (ref "C136")
      (value "1uF 10V")
      (footprint "eagle-import:0201")
      (libsource (lib "eagle-import") (part "C-0201"))
    )
    (comp (ref "C137")
      (value "1uF 10V")
      (footprint "eagle-import:0201")
      (libsource (lib "eagle-import") (part "C-0201"))
    )
    (comp (ref "C138")
      (value "1uF 50V")
      (footprint "eagle-import:C0603")
      (libsource (lib "eagle-import") (part "C-0603"))
    )
    (comp (ref "C139")
      (value "4.7nF")
      (footprint "eagle-import:C0402")
      (libsource (lib "eagle-import") (part "C-0402"))
    )
    (comp (ref "C140")
      (value "4.7uF")
      (footprint "eagle-import:C0402")
      (libsource (lib "eagle-import") (part "C-0402"))
    )
    (comp (ref "C141")
      (value "10nF")
      (footprint "eagle-import:0201")
      (libsource (lib "eagle-import") (part "C-0201"))
    )
    (comp (ref "C142")
      (value "10nF")
      (footprint "eagle-import:0201")
      (libsource (lib "eagle-import") (part "C-0201"))
    )
    (comp (ref "C143")
      (value "10nF")
      (footprint "eagle-import:0201")
      (libsource (lib "eagle-import") (part "C-0201"))
    )
    (comp (ref "C144")
      (value "100nF")
      (footprint "eagle-import:C0402")
      (libsource (lib "eagle-import") (part "C-0402"))
    )
    (comp (ref "C145")
      (value "100nF")
      (footprint "eagle-import:C0402")
      (libsource (lib "eagle-import") (part "C-0402"))
    )
    (comp (ref "C146")
      (value "10uF 50V")
      (footprint "eagle-import:C0805")
      (libsource (lib "eagle-import") (part "C-0805"))
    )
    (comp (ref "C147")
      (value "10uF 50V")
      (footprint "eagle-import:C0805")
      (libsource (lib "eagle-import") (part "C-0805"))
    )
    (comp (ref "C148")
      (value "10uF 50V")
      (footprint "eagle-import:C0805")
      (libsource (lib "eagle-import") (part "C-0805"))
    )
    (comp (ref "C149")
      (value "10uF 50V")
      (footprint "eagle-import:C0805")
      (libsource (lib "eagle-import") (part "C-0805"))
    )
    (comp (ref "C150")
      (value "22uF 50V")
      (footprint "eagle-import:C0805")
      (libsource (lib "eagle-import") (part "C-0805"))
    )
    (comp (ref "C151")
      (value "22uF 50V")
      (footprint "eagle-import:C0805")
      (libsource (lib "eagle-import") (part "C-0805"))
    )
    (comp (ref "C152")
      (value "22uF 50V")
      (footprint "eagle-import:C0805")
      (libsource (lib "eagle-import") (part "C-0805"))
    )
    (comp (ref "C153")
      (value "22uF 50V")
      (footprint "eagle-import:C0805")
      (libsource (lib "eagle-import") (part "C-0805"))
    )
    (comp (ref "C154")
      (value "100nF")
      (footprint "eagle-import:0201")
      (libsource (lib "eagle-import") (part "C-0201"))
    )
    (comp (ref "IC20")
      (value "STUSB4710AQ1TR")
      (footprint "eagle-import:QFN50P300X300X55-16N")
      (libsource (lib "eagle-import") (part "STUSB4710AQ1TR"))
    )
    (comp (ref "IC32")
      (value "TPS552882")
      (footprint "eagle-import:RPM0026A-MFG")
      (fields
        (field (name "MANUFACTURER_PART_NUMBER") "TPS552882QRPMRQ1")
        (field (name "COPYRIGHT") "Copyright (C) 2025 Ultra Librarian. All rights reserved.")
      )
      (libsource (lib "eagle-import") (part "TPS552882"))
    )
    (comp (ref "IC33")
      (value "INA219BIDCNT")
      (footprint "eagle-import:SOT23-8")
      (libsource (lib "eagle-import") (part "INA219BIDCNT"))
    )
    (comp (ref "L7")
      (value "4.7uH 744771004")
      (footprint "eagle-import:WE-PD_1280")
      (libsource (lib "eagle-import") (part "WE-PD_1280_74477004"))
    )
    (comp (ref "PORT6")
      (value "632722100213")
      (footprint "eagle-import:632722100213")
      (libsource (lib "eagle-import") (part "632722100213"))
    )
    (comp (ref "R160")
      (value "200K")
      (footprint "eagle-import:R0201")
      (libsource (lib "eagle-import") (part "R0201"))
    )
    (comp (ref "R161")
      (value "12.7K 0.1%")
      (footprint "eagle-import:R0201")
      (libsource (lib "eagle-import") (part "R0201"))
    )
    (comp (ref "R162")
      (value "4.64K 0.1%")
      (footprint "eagle-import:R0201")
      (libsource (lib "eagle-import") (part "R0201"))
    )
    (comp (ref "R163")
      (value "4.64K 0.1%")
      (footprint "eagle-import:R0201")
      (libsource (lib "eagle-import") (part "R0201"))
    )
    (comp (ref "R164")
      (value "8.87K 0.1%")
      (footprint "eagle-import:R0201")
      (libsource (lib "eagle-import") (part "R0201"))
    )
    (comp (ref "R165")
      (value "30.9K 0.1%")
      (footprint "eagle-import:R0201")
      (libsource (lib "eagle-import") (part "R0201"))
    )
    (comp (ref "R166")
      (value "100K")
      (footprint "eagle-import:R0201")
      (libsource (lib "eagle-import") (part "R0201"))
    )
    (comp (ref "R167")
      (value "DNI")
      (footprint "eagle-import:R0201")
      (libsource (lib "eagle-import") (part "R0201"))
    )
    (comp (ref "R168")
      (value "10K")
      (footprint "eagle-import:0402")
      (libsource (lib "eagle-import") (part "R0402"))
    )
    (comp (ref "R169")
      (value "10K")
      (footprint "eagle-import:0402")
      (libsource (lib "eagle-import") (part "R0402"))
    )
    (comp (ref "R170")
      (value "10K")
      (footprint "eagle-import:R0201")
      (libsource (lib "eagle-import") (part "R0201"))
    )
    (comp (ref "R171")
      (value "2.2K")
      (footprint "eagle-import:R0201")
      (libsource (lib "eagle-import") (part "R0201"))
    )
    (comp (ref "R172")
      (value "10K")
      (footprint "eagle-import:0402")
      (libsource (lib "eagle-import") (part "R0402"))
    )
    (comp (ref "R173")
      (value "0.010R")
      (footprint "eagle-import:2512")
      (libsource (lib "eagle-import") (part "R2512"))
    )
    (comp (ref "R174")
      (value "6.19K")
      (footprint "eagle-import:R0201")
      (libsource (lib "eagle-import") (part "R0201"))
    )
    (comp (ref "R175")
      (value "49.9K")
      (footprint "eagle-import:R0201")
      (libsource (lib "eagle-import") (part "R0201"))
    )
    (comp (ref "R176")
      (value "19.9K")
      (footprint "eagle-import:R0201")
      (libsource (lib "eagle-import") (part "R0201"))
    )
    (comp (ref "R177")
      (value "150K")
      (footprint "eagle-import:R0201")
      (libsource (lib "eagle-import") (part "R0201"))
    )
    (comp (ref "R178")
      (value "19.9K")
      (footprint "eagle-import:R0201")
      (libsource (lib "eagle-import") (part "R0201"))
    )
    (comp (ref "R179")
      (value "0.010R")
      (footprint "eagle-import:2512")
      (libsource (lib "eagle-import") (part "R2512"))
    )
    (comp (ref "R180")
      (value "1K")
      (footprint "eagle-import:R0201")
      (libsource (lib "eagle-import") (part "R0201"))
    )
    (comp (ref "R181")
      (value "1K")
      (footprint "eagle-import:R0201")
      (libsource (lib "eagle-import") (part "R0201"))
    )
    (comp (ref "R182")
      (value "10K")
      (footprint "eagle-import:R0201")
      (libsource (lib "eagle-import") (part "R0201"))
    )
    (comp (ref "T31")
      (value "DMP3013SFV")
      (footprint "eagle-import:POWERDI3333-8_UX_DIO-L")
      (fields (field (name "MANUFACTURER_PART_NUMBER") "DMP3013SFV-7"))
      (libsource (lib "eagle-import") (part "DMP3013SFV-7UX"))
    )
    (comp (ref "T32")
      (value "DMP3013SFV")
      (footprint "eagle-import:POWERDI3333-8_UX_DIO-L")
      (fields (field (name "MANUFACTURER_PART_NUMBER") "DMP3013SFV-7"))
      (libsource (lib "eagle-import") (part "DMP3013SFV-7UX"))
    )
    (comp (ref "T33")
      (value "DMP3013SFV")
      (footprint "eagle-import:POWERDI3333-8_UX_DIO-L")
      (fields (field (name "MANUFACTURER_PART_NUMBER") "DMP3013SFV-7"))
      (libsource (lib "eagle-import") (part "DMP3013SFV-7UX"))
    )
    (comp (ref "T34")
      (value "BSZ065N06LS5ATMA1")
      (footprint "eagle-import:POWERDI3333-8_UX_DIO-L")
      (fields
        (field (name "MANUFACTURER_PART_NUMBER") "IPZ40N04S5L7R4ATMA1")
        (field (name "COPYRIGHT") "Copyright (C) 2025 Ultra Librarian. All rights reserved.")
      )
      (libsource (lib "eagle-import") (part "IPZ40N04S5L7R4ATMA1"))
    )
    (comp (ref "T35")
      (value "BSZ065N06LS5ATMA1")
      (footprint "eagle-import:POWERDI3333-8_UX_DIO-L")
      (fields
        (field (name "MANUFACTURER_PART_NUMBER") "IPZ40N04S5L7R4ATMA1")
        (field (name "COPYRIGHT") "Copyright (C) 2025 Ultra Librarian. All rights reserved.")
      )
      (libsource (lib "eagle-import") (part "IPZ40N04S5L7R4ATMA1"))
    )
    (comp (ref "C155")
      (value "1uF 10V")
      (footprint "eagle-import:0201")
      (libsource (lib "eagle-import") (part "C-0201"))
    )
    (comp (ref "C156")
      (value "1uF 10V")
      (footprint "eagle-import:0201")
      (libsource (lib "eagle-import") (part "C-0201"))
    )
    (comp (ref "C157")
      (value "1uF 50V")
      (footprint "eagle-import:C0603")
      (libsource (lib "eagle-import") (part "C-0603"))
    )
    (comp (ref "C158")
      (value "4.7nF")
      (footprint "eagle-import:C0402")
      (libsource (lib "eagle-import") (part "C-0402"))
    )
    (comp (ref "C159")
      (value "4.7uF")
      (footprint "eagle-import:C0402")
      (libsource (lib "eagle-import") (part "C-0402"))
    )
    (comp (ref "C160")
      (value "10nF")
      (footprint "eagle-import:0201")
      (libsource (lib "eagle-import") (part "C-0201"))
    )
    (comp (ref "C161")
      (value "10nF")
      (footprint "eagle-import:0201")
      (libsource (lib "eagle-import") (part "C-0201"))
    )
    (comp (ref "C162")
      (value "10nF")
      (footprint "eagle-import:0201")
      (libsource (lib "eagle-import") (part "C-0201"))
    )
    (comp (ref "C163")
      (value "100nF")
      (footprint "eagle-import:C0402")
      (libsource (lib "eagle-import") (part "C-0402"))
    )
    (comp (ref "C164")
      (value "100nF")
      (footprint "eagle-import:C0402")
      (libsource (lib "eagle-import") (part "C-0402"))
    )
    (comp (ref "C165")
      (value "10uF 50V")
      (footprint "eagle-import:C0805")
      (libsource (lib "eagle-import") (part "C-0805"))
    )
    (comp (ref "C166")
      (value "10uF 50V")
      (footprint "eagle-import:C0805")
      (libsource (lib "eagle-import") (part "C-0805"))
    )
    (comp (ref "C167")
      (value "10uF 50V")
      (footprint "eagle-import:C0805")
      (libsource (lib "eagle-import") (part "C-0805"))
    )
    (comp (ref "C168")
      (value "10uF 50V")
      (footprint "eagle-import:C0805")
      (libsource (lib "eagle-import") (part "C-0805"))
    )
    (comp (ref "C169")
      (value "22uF 50V")
      (footprint "eagle-import:C0805")
      (libsource (lib "eagle-import") (part "C-0805"))
    )
    (comp (ref "C170")
      (value "22uF 50V")
      (footprint "eagle-import:C0805")
      (libsource (lib "eagle-import") (part "C-0805"))
    )
    (comp (ref "C171")
      (value "22uF 50V")
      (footprint "eagle-import:C0805")
      (libsource (lib "eagle-import") (part "C-0805"))
    )
    (comp (ref "C172")
      (value "22uF 50V")
      (footprint "eagle-import:C0805")
      (libsource (lib "eagle-import") (part "C-0805"))
    )
    (comp (ref "C173")
      (value "100nF")
      (footprint "eagle-import:0201")
      (libsource (lib "eagle-import") (part "C-0201"))
    )
    (comp (ref "IC23")
      (value "STUSB4710AQ1TR")
      (footprint "eagle-import:QFN50P300X300X55-16N")
      (libsource (lib "eagle-import") (part "STUSB4710AQ1TR"))
    )
    (comp (ref "IC35")
      (value "TPS552882")
      (footprint "eagle-import:RPM0026A-MFG")
      (fields
        (field (name "MANUFACTURER_PART_NUMBER") "TPS552882QRPMRQ1")
        (field (name "COPYRIGHT") "Copyright (C) 2025 Ultra Librarian. All rights reserved.")
      )
      (libsource (lib "eagle-import") (part "TPS552882"))
    )
    (comp (ref "IC36")
      (value "INA219BIDCNT")
      (footprint "eagle-import:SOT23-8")
      (libsource (lib "eagle-import") (part "INA219BIDCNT"))
    )
    (comp (ref "L8")
      (value "4.7uH 744771004")
      (footprint "eagle-import:WE-PD_1280")
      (libsource (lib "eagle-import") (part "WE-PD_1280_74477004"))
    )
    (comp (ref "PORT7")
      (value "632722100213")
      (footprint "eagle-import:632722100213")
      (libsource (lib "eagle-import") (part "632722100213"))
    )
    (comp (ref "R183")
      (value "200K")
      (footprint "eagle-import:R0201")
      (libsource (lib "eagle-import") (part "R0201"))
    )
    (comp (ref "R184")
      (value "12.7K 0.1%")
      (footprint "eagle-import:R0201")
      (libsource (lib "eagle-import") (part "R0201"))
    )
    (comp (ref "R185")
      (value "4.64K 0.1%")
      (footprint "eagle-import:R0201")
      (libsource (lib "eagle-import") (part "R0201"))
    )
    (comp (ref "R186")
      (value "4.64K 0.1%")
      (footprint "eagle-import:R0201")
      (libsource (lib "eagle-import") (part "R0201"))
    )
    (comp (ref "R187")
      (value "8.87K 0.1%")
      (footprint "eagle-import:R0201")
      (libsource (lib "eagle-import") (part "R0201"))
    )
    (comp (ref "R188")
      (value "30.9K 0.1%")
      (footprint "eagle-import:R0201")
      (libsource (lib "eagle-import") (part "R0201"))
    )
    (comp (ref "R189")
      (value "DNI")
      (footprint "eagle-import:R0201")
      (libsource (lib "eagle-import") (part "R0201"))
    )
    (comp (ref "R190")
      (value "100K")
      (footprint "eagle-import:R0201")
      (libsource (lib "eagle-import") (part "R0201"))
    )
    (comp (ref "R191")
      (value "10K")
      (footprint "eagle-import:0402")
      (libsource (lib "eagle-import") (part "R0402"))
    )
    (comp (ref "R192")
      (value "10K")
      (footprint "eagle-import:0402")
      (libsource (lib "eagle-import") (part "R0402"))
    )
    (comp (ref "R193")
      (value "10K")
      (footprint "eagle-import:R0201")
      (libsource (lib "eagle-import") (part "R0201"))
    )
    (comp (ref "R194")
      (value "2.2K")
      (footprint "eagle-import:R0201")
      (libsource (lib "eagle-import") (part "R0201"))
    )
    (comp (ref "R195")
      (value "10K")
      (footprint "eagle-import:0402")
      (libsource (lib "eagle-import") (part "R0402"))
    )
    (comp (ref "R196")
      (value "0.010R")
      (footprint "eagle-import:2512")
      (libsource (lib "eagle-import") (part "R2512"))
    )
    (comp (ref "R197")
      (value "6.19K")
      (footprint "eagle-import:R0201")
      (libsource (lib "eagle-import") (part "R0201"))
    )
    (comp (ref "R198")
      (value "49.9K")
      (footprint "eagle-import:R0201")
      (libsource (lib "eagle-import") (part "R0201"))
    )
    (comp (ref "R199")
      (value "19.9K")
      (footprint "eagle-import:R0201")
      (libsource (lib "eagle-import") (part "R0201"))
    )
    (comp (ref "R200")
      (value "150K")
      (footprint "eagle-import:R0201")
      (libsource (lib "eagle-import") (part "R0201"))
    )
    (comp (ref "R201")
      (value "19.9K")
      (footprint "eagle-import:R0201")
      (libsource (lib "eagle-import") (part "R0201"))
    )
    (comp (ref "R202")
      (value "0.010R")
      (footprint "eagle-import:2512")
      (libsource (lib "eagle-import") (part "R2512"))
    )
    (comp (ref "R203")
      (value "1K")
      (footprint "eagle-import:R0201")
      (libsource (lib "eagle-import") (part "R0201"))
    )
    (comp (ref "R204")
      (value "1K")
      (footprint "eagle-import:R0201")
      (libsource (lib "eagle-import") (part "R0201"))
    )
    (comp (ref "R218")
      (value "10K")
      (footprint "eagle-import:R0201")
      (libsource (lib "eagle-import") (part "R0201"))
    )
    (comp (ref "T36")
      (value "DMP3013SFV")
      (footprint "eagle-import:POWERDI3333-8_UX_DIO-L")
      (fields (field (name "MANUFACTURER_PART_NUMBER") "DMP3013SFV-7"))
      (libsource (lib "eagle-import") (part "DMP3013SFV-7UX"))
    )
    (comp (ref "T37")
      (value "DMP3013SFV")
      (footprint "eagle-import:POWERDI3333-8_UX_DIO-L")
      (fields (field (name "MANUFACTURER_PART_NUMBER") "DMP3013SFV-7"))
      (libsource (lib "eagle-import") (part "DMP3013SFV-7UX"))
    )
    (comp (ref "T38")
      (value "DMP3013SFV")
      (footprint "eagle-import:POWERDI3333-8_UX_DIO-L")
      (fields (field (name "MANUFACTURER_PART_NUMBER") "DMP3013SFV-7"))
      (libsource (lib "eagle-import") (part "DMP3013SFV-7UX"))
    )
    (comp (ref "T39")
      (value "BSZ065N06LS5ATMA1")
      (footprint "eagle-import:POWERDI3333-8_UX_DIO-L")
      (fields
        (field (name "MANUFACTURER_PART_NUMBER") "IPZ40N04S5L7R4ATMA1")
        (field (name "COPYRIGHT") "Copyright (C) 2025 Ultra Librarian. All rights reserved.")
      )
      (libsource (lib "eagle-import") (part "IPZ40N04S5L7R4ATMA1"))
    )
    (comp (ref "T40")
      (value "BSZ065N06LS5ATMA1")
      (footprint "eagle-import:POWERDI3333-8_UX_DIO-L")
      (fields
        (field (name "MANUFACTURER_PART_NUMBER") "IPZ40N04S5L7R4ATMA1")
        (field (name "COPYRIGHT") "Copyright (C) 2025 Ultra Librarian. All rights reserved.")
      )
      (libsource (lib "eagle-import") (part "IPZ40N04S5L7R4ATMA1"))
    )
  )
  (nets
    (net (code "1") (name "+1V1") (class "Default")
      (node (ref "C192") (pin "1") (pinfunction "1_1") (pintype "passive"))
      (node (ref "C193") (pin "1") (pinfunction "1_1") (pintype "passive"))
      (node (ref "C194") (pin "1") (pinfunction "1_1") (pintype "passive"))
      (node (ref "DVDD") (pin "TP") (pinfunction "P$1_TP") (pintype "bidirectional"))
      (node (ref "IC26") (pin "23") (pinfunction "DVDD_23") (pintype "bidirectional"))
      (node (ref "IC26") (pin "45") (pinfunction "VREG_VOUT_45") (pintype "bidirectional"))
      (node (ref "IC26") (pin "50") (pinfunction "DVDD_50") (pintype "bidirectional"))
    )
    (net (code "2") (name "+3V3") (class "Default")
      (node (ref "C116") (pin "1") (pinfunction "1_1") (pintype "passive"))
      (node (ref "C135") (pin "1") (pinfunction "1_1") (pintype "passive"))
      (node (ref "C154") (pin "1") (pinfunction "1_1") (pintype "passive"))
      (node (ref "C17") (pin "1") (pinfunction "1_1") (pintype "passive"))
      (node (ref "C173") (pin "1") (pinfunction "1_1") (pintype "passive"))
      (node (ref "C176") (pin "1") (pinfunction "1_1") (pintype "passive"))
      (node (ref "C18") (pin "1") (pinfunction "1_1") (pintype "passive"))
      (node (ref "C182") (pin "1") (pinfunction "1_1") (pintype "passive"))
      (node (ref "C183") (pin "1") (pinfunction "1_1") (pintype "passive"))
      (node (ref "C184") (pin "1") (pinfunction "1_1") (pintype "passive"))
      (node (ref "C185") (pin "1") (pinfunction "1_1") (pintype "passive"))
      (node (ref "C186") (pin "1") (pinfunction "1_1") (pintype "passive"))
      (node (ref "C187") (pin "1") (pinfunction "1_1") (pintype "passive"))
      (node (ref "C188") (pin "1") (pinfunction "1_1") (pintype "passive"))
      (node (ref "C189") (pin "1") (pinfunction "1_1") (pintype "passive"))
      (node (ref "C19") (pin "1") (pinfunction "1_1") (pintype "passive"))
      (node (ref "C190") (pin "1") (pinfunction "1_1") (pintype "passive"))
      (node (ref "C195") (pin "1") (pinfunction "1_1") (pintype "passive"))
      (node (ref "C20") (pin "1") (pinfunction "1_1") (pintype "passive"))
      (node (ref "C212") (pin "1") (pinfunction "1_1") (pintype "passive"))
      (node (ref "C213") (pin "1") (pinfunction "1_1") (pintype "passive"))
      (node (ref "C221") (pin "1") (pinfunction "1_1") (pintype "passive"))
      (node (ref "C222") (pin "1") (pinfunction "1_1") (pintype "passive"))
      (node (ref "C223") (pin "1") (pinfunction "1_1") (pintype "passive"))
      (node (ref "C236") (pin "1") (pinfunction "1_1") (pintype "passive"))
      (node (ref "C238") (pin "1") (pinfunction "1_1") (pintype "passive"))
      (node (ref "C239") (pin "1") (pinfunction "1_1") (pintype "passive"))
      (node (ref "C241") (pin "1") (pinfunction "1_1") (pintype "passive"))
      (node (ref "C249") (pin "1") (pinfunction "1_1") (pintype "passive"))
      (node (ref "C251") (pin "1") (pinfunction "1_1") (pintype "passive"))
      (node (ref "C55") (pin "1") (pinfunction "1_1") (pintype "passive"))
      (node (ref "C74") (pin "1") (pinfunction "1_1") (pintype "passive"))
      (node (ref "C97") (pin "1") (pinfunction "1_1") (pintype "passive"))
      (node (ref "DISP") (pin "1") (pinfunction "1_1") (pintype "bidirectional"))
      (node (ref "DISP") (pin "2") (pinfunction "2_2") (pintype "bidirectional"))
      (node (ref "ETH1") (pin "11") (pinfunction "GA2_11") (pintype "passive"))
      (node (ref "ETH1") (pin "9") (pinfunction "GA1_9") (pintype "passive"))
      (node (ref "IC13") (pin "4") (pinfunction "VCC_4") (pintype "bidirectional"))
      (node (ref "IC16") (pin "4") (pinfunction "VCC_4") (pintype "bidirectional"))
      (node (ref "IC16") (pin "7") (pinfunction "A0_7") (pintype "bidirectional"))
      (node (ref "IC19") (pin "4") (pinfunction "VCC_4") (pintype "bidirectional"))
      (node (ref "IC22") (pin "4") (pinfunction "VCC_4") (pintype "bidirectional"))
      (node (ref "IC22") (pin "7") (pinfunction "A0_7") (pintype "bidirectional"))
      (node (ref "IC22") (pin "8") (pinfunction "A1_8") (pintype "bidirectional"))
      (node (ref "IC25") (pin "4") (pinfunction "VCC_4") (pintype "bidirectional"))
      (node (ref "IC25") (pin "8") (pinfunction "A1_8") (pintype "bidirectional"))
      (node (ref "IC26") (pin "1") (pinfunction "IOVDD_1") (pintype "bidirectional"))
      (node (ref "IC26") (pin "10") (pinfunction "IOVDD_10") (pintype "bidirectional"))
      (node (ref "IC26") (pin "22") (pinfunction "IOVDD_22") (pintype "bidirectional"))
      (node (ref "IC26") (pin "33") (pinfunction "IOVDD_33") (pintype "bidirectional"))
      (node (ref "IC26") (pin "42") (pinfunction "IOVDD_42") (pintype "bidirectional"))
      (node (ref "IC26") (pin "44") (pinfunction "VREG_VIN_44") (pintype "bidirectional"))
      (node (ref "IC26") (pin "48") (pinfunction "USB_VDD_48") (pintype "bidirectional"))
      (node (ref "IC26") (pin "49") (pinfunction "IOVDD_49") (pintype "bidirectional"))
      (node (ref "IC27") (pin "8") (pinfunction "VCC_8") (pintype "power_in"))
      (node (ref "IC28") (pin "2") (pinfunction "V+_2") (pintype "power_in"))
      (node (ref "IC29") (pin "8") (pinfunction "VCC_8") (pintype "power_in"))
      (node (ref "IC33") (pin "4") (pinfunction "VCC_4") (pintype "bidirectional"))
      (node (ref "IC33") (pin "7") (pinfunction "A0_7") (pintype "bidirectional"))
      (node (ref "IC36") (pin "4") (pinfunction "VCC_4") (pintype "bidirectional"))
      (node (ref "IC36") (pin "8") (pinfunction "A1_8") (pintype "bidirectional"))
      (node (ref "IC38") (pin "21") (pinfunction "VCC_21") (pintype "power_in"))
      (node (ref "IC39") (pin "28") (pinfunction "VDD_28") (pintype "power_in"))
      (node (ref "IC39") (pin "43") (pinfunction "PMODE2_43") (pintype "input"))
      (node (ref "IC39") (pin "44") (pinfunction "PMODE1_44") (pintype "input"))
      (node (ref "IC39") (pin "45") (pinfunction "PMODE0_45") (pintype "input"))
      (node (ref "IC4") (pin "5") (pinfunction "V+_5") (pintype "bidirectional"))
      (node (ref "IC42") (pin "5") (pinfunction "VDD_5") (pintype "bidirectional"))
      (node (ref "IC44") (pin "4") (pinfunction "VCC_4") (pintype "bidirectional"))
      (node (ref "IC44") (pin "7") (pinfunction "A0_7") (pintype "bidirectional"))
      (node (ref "IC44") (pin "8") (pinfunction "A1_8") (pintype "bidirectional"))
      (node (ref "IC5") (pin "5") (pinfunction "V+_5") (pintype "bidirectional"))
      (node (ref "IC6") (pin "5") (pinfunction "V+_5") (pintype "bidirectional"))
      (node (ref "IC7") (pin "5") (pinfunction "V+_5") (pintype "bidirectional"))
      (node (ref "IOVDD") (pin "TP") (pinfunction "P$1_TP") (pintype "bidirectional"))
      (node (ref "L10") (pin "1") (pinfunction "1_1") (pintype "passive"))
      (node (ref "L11") (pin "2") (pinfunction "2_2") (pintype "passive"))
      (node (ref "R1") (pin "1") (pinfunction "1_1") (pintype "passive"))
      (node (ref "R10") (pin "1") (pinfunction "1_1") (pintype "passive"))
      (node (ref "R113") (pin "1") (pinfunction "1_1") (pintype "passive"))
      (node (ref "R12") (pin "2") (pinfunction "2_2") (pintype "passive"))
      (node (ref "R120") (pin "1") (pinfunction "1_1") (pintype "passive"))
      (node (ref "R13") (pin "2") (pinfunction "2_2") (pintype "passive"))
      (node (ref "R136") (pin "1") (pinfunction "1_1") (pintype "passive"))
      (node (ref "R143") (pin "1") (pinfunction "1_1") (pintype "passive"))
      (node (ref "R15") (pin "2") (pinfunction "2_2") (pintype "passive"))
      (node (ref "R159") (pin "1") (pinfunction "1_1") (pintype "passive"))
      (node (ref "R16") (pin "2") (pinfunction "2_2") (pintype "passive"))
      (node (ref "R166") (pin "1") (pinfunction "1_1") (pintype "passive"))
      (node (ref "R18") (pin "2") (pinfunction "2_2") (pintype "passive"))
      (node (ref "R182") (pin "1") (pinfunction "1_1") (pintype "passive"))
      (node (ref "R189") (pin "1") (pinfunction "1_1") (pintype "passive"))
      (node (ref "R19") (pin "2") (pinfunction "2_2") (pintype "passive"))
      (node (ref "R207") (pin "5") (pinfunction "5_5") (pintype "passive"))
      (node (ref "R207") (pin "6") (pinfunction "6_6") (pintype "passive"))
      (node (ref "R207") (pin "7") (pinfunction "7_7") (pintype "passive"))
      (node (ref "R207") (pin "8") (pinfunction "8_8") (pintype "passive"))
      (node (ref "R208") (pin "1") (pinfunction "1_1") (pintype "passive"))
      (node (ref "R209") (pin "2") (pinfunction "2_2") (pintype "passive"))
      (node (ref "R21") (pin "2") (pinfunction "2_2") (pintype "passive"))
      (node (ref "R212") (pin "2") (pinfunction "2_2") (pintype "passive"))
      (node (ref "R213") (pin "2") (pinfunction "2_2") (pintype "passive"))
      (node (ref "R215") (pin "5") (pinfunction "5_5") (pintype "passive"))
      (node (ref "R215") (pin "6") (pinfunction "6_6") (pintype "passive"))
      (node (ref "R215") (pin "7") (pinfunction "7_7") (pintype "passive"))
      (node (ref "R215") (pin "8") (pinfunction "8_8") (pintype "passive"))
      (node (ref "R216") (pin "5") (pinfunction "5_5") (pintype "passive"))
      (node (ref "R216") (pin "6") (pinfunction "6_6") (pintype "passive"))
      (node (ref "R216") (pin "7") (pinfunction "7_7") (pintype "passive"))
      (node (ref "R216") (pin "8") (pinfunction "8_8") (pintype "passive"))
      (node (ref "R217") (pin "5") (pinfunction "5_5") (pintype "passive"))
      (node (ref "R217") (pin "6") (pinfunction "6_6") (pintype "passive"))
      (node (ref "R217") (pin "7") (pinfunction "7_7") (pintype "passive"))
      (node (ref "R217") (pin "8") (pinfunction "8_8") (pintype "passive"))
      (node (ref "R218") (pin "1") (pinfunction "1_1") (pintype "passive"))
      (node (ref "R22") (pin "2") (pinfunction "2_2") (pintype "passive"))
      (node (ref "R236") (pin "2") (pinfunction "2_2") (pintype "passive"))
      (node (ref "R245") (pin "1") (pinfunction "1_1") (pintype "passive"))
      (node (ref "R252") (pin "2") (pinfunction "2_2") (pintype "passive"))
      (node (ref "R253") (pin "1") (pinfunction "1_1") (pintype "passive"))
      (node (ref "R253") (pin "2") (pinfunction "2_2") (pintype "passive"))
      (node (ref "R253") (pin "3") (pinfunction "3_3") (pintype "passive"))
      (node (ref "R253") (pin "4") (pinfunction "4_4") (pintype "passive"))
      (node (ref "R275") (pin "1") (pinfunction "1_1") (pintype "passive"))
      (node (ref "R4") (pin "1") (pinfunction "1_1") (pintype "passive"))
      (node (ref "R50") (pin "1") (pinfunction "1_1") (pintype "passive"))
      (node (ref "R66") (pin "1") (pinfunction "1_1") (pintype "passive"))
      (node (ref "R7") (pin "1") (pinfunction "1_1") (pintype "passive"))
      (node (ref "R73") (pin "1") (pinfunction "1_1") (pintype "passive"))
      (node (ref "R90") (pin "1") (pinfunction "1_1") (pintype "passive"))
      (node (ref "R97") (pin "1") (pinfunction "1_1") (pintype "passive"))
      (node (ref "RFB3") (pin "1") (pinfunction "1_1") (pintype "passive"))
      (node (ref "VO3") (pin "TP") (pinfunction "P$1_TP") (pintype "bidirectional"))
    )
    (net (code "3") (name "+3V3_A") (class "Default")
      (node (ref "C224") (pin "1") (pinfunction "1_1") (pintype "passive"))
      (node (ref "C225") (pin "1") (pinfunction "1_1") (pintype "passive"))
      (node (ref "C226") (pin "1") (pinfunction "1_1") (pintype "passive"))
      (node (ref "C227") (pin "1") (pinfunction "1_1") (pintype "passive"))
      (node (ref "C228") (pin "1") (pinfunction "1_1") (pintype "passive"))
      (node (ref "C229") (pin "1") (pinfunction "1_1") (pintype "passive"))
      (node (ref "IC39") (pin "11") (pinfunction "AVDD_11") (pintype "power_in"))
      (node (ref "IC39") (pin "15") (pinfunction "AVDD_15") (pintype "power_in"))
      (node (ref "IC39") (pin "17") (pinfunction "AVDD_17") (pintype "power_in"))
      (node (ref "IC39") (pin "21") (pinfunction "AVDD_21") (pintype "power_in"))
      (node (ref "IC39") (pin "4") (pinfunction "AVDD_4") (pintype "power_in"))
      (node (ref "IC39") (pin "8") (pinfunction "AVDD_8") (pintype "power_in"))
      (node (ref "L10") (pin "2") (pinfunction "2_2") (pintype "passive"))
      (node (ref "R232") (pin "2") (pinfunction "2_2") (pintype "passive"))
      (node (ref "R233") (pin "2") (pinfunction "2_2") (pintype "passive"))
      (node (ref "R239") (pin "2") (pinfunction "2_2") (pintype "passive"))
    )
    (net (code "4") (name "+5V") (class "Default")
      (node (ref "DISP") (pin "3") (pinfunction "3_3") (pintype "bidirectional"))
      (node (ref "DISP") (pin "4") (pinfunction "4_4") (pintype "bidirectional"))
    )
    (net (code "5") (name "+5VA") (class "Default")
      (node (ref "C2") (pin "1") (pinfunction "1_1") (pintype "passive"))
      (node (ref "C261") (pin "1") (pinfunction "1_1") (pintype "passive"))
      (node (ref "C263") (pin "1") (pinfunction "1_1") (pintype "passive"))
      (node (ref "C264") (pin "1") (pinfunction "1_1") (pintype "passive"))
      (node (ref "C82") (pin "1") (pinfunction "1_1") (pintype "passive"))
      (node (ref "IC1") (pin "1") (pinfunction "IN_1") (pintype "bidirectional"))
      (node (ref "IC8") (pin "1") (pinfunction "IN_1") (pintype "bidirectional"))
      (node (ref "L13") (pin "2") (pinfunction "2_2") (pintype "passive"))
      (node (ref "RFB7") (pin "1") (pinfunction "1_1") (pintype "passive"))
      (node (ref "VO5A") (pin "TP") (pinfunction "P$1_TP") (pintype "bidirectional"))
    )
    (net (code "6") (name "+5VB") (class "Default")
      (node (ref "C12") (pin "1") (pinfunction "1_1") (pintype "passive"))
      (node (ref "C275") (pin "1") (pinfunction "1_1") (pintype "passive"))
      (node (ref "C277") (pin "1") (pinfunction "1_1") (pintype "passive"))
      (node (ref "C278") (pin "1") (pinfunction "1_1") (pintype "passive"))
      (node (ref "C7") (pin "1") (pinfunction "1_1") (pintype "passive"))
      (node (ref "IC2") (pin "1") (pinfunction "IN_1") (pintype "bidirectional"))
      (node (ref "IC3") (pin "1") (pinfunction "IN_1") (pintype "bidirectional"))
      (node (ref "L15") (pin "2") (pinfunction "2_2") (pintype "passive"))
      (node (ref "RFB11") (pin "1") (pinfunction "1_1") (pintype "passive"))
      (node (ref "VO5B") (pin "TP") (pinfunction "P$1_TP") (pintype "bidirectional"))
    )
    (net (code "7") (name "+24V_A") (class "Default")
      (node (ref "C108") (pin "1") (pinfunction "1_1") (pintype "passive"))
      (node (ref "C109") (pin "1") (pinfunction "1_1") (pintype "passive"))
      (node (ref "C110") (pin "1") (pinfunction "1_1") (pintype "passive"))
      (node (ref "C111") (pin "1") (pinfunction "1_1") (pintype "passive"))
      (node (ref "C127") (pin "1") (pinfunction "1_1") (pintype "passive"))
      (node (ref "C128") (pin "1") (pinfunction "1_1") (pintype "passive"))
      (node (ref "C129") (pin "1") (pinfunction "1_1") (pintype "passive"))
      (node (ref "C130") (pin "1") (pinfunction "1_1") (pintype "passive"))
      (node (ref "C256") (pin "1") (pinfunction "+_1") (pintype "passive"))
      (node (ref "C257") (pin "1") (pinfunction "+_1") (pintype "passive"))
      (node (ref "C47") (pin "1") (pinfunction "1_1") (pintype "passive"))
      (node (ref "C48") (pin "1") (pinfunction "1_1") (pintype "passive"))
      (node (ref "C49") (pin "1") (pinfunction "1_1") (pintype "passive"))
      (node (ref "C50") (pin "1") (pinfunction "1_1") (pintype "passive"))
      (node (ref "C66") (pin "1") (pinfunction "1_1") (pintype "passive"))
      (node (ref "C67") (pin "1") (pinfunction "1_1") (pintype "passive"))
      (node (ref "C68") (pin "1") (pinfunction "1_1") (pintype "passive"))
      (node (ref "C69") (pin "1") (pinfunction "1_1") (pintype "passive"))
      (node (ref "D11") (pin "C") (pinfunction "C_C") (pintype "passive"))
      (node (ref "F3") (pin "2_1") (pinfunction "2_2_1") (pintype "passive"))
      (node (ref "F3") (pin "2_2") (pinfunction "2_2_2") (pintype "passive"))
      (node (ref "IC12") (pin "3") (pinfunction "VIN_3") (pintype "power_in"))
      (node (ref "IC15") (pin "3") (pinfunction "VIN_3") (pintype "power_in"))
      (node (ref "IC21") (pin "3") (pinfunction "VIN_3") (pintype "power_in"))
      (node (ref "IC24") (pin "3") (pinfunction "VIN_3") (pintype "power_in"))
      (node (ref "T10") (pin "5") (pinfunction "D_5") (pintype "passive"))
      (node (ref "T10") (pin "6") (pinfunction "D_6") (pintype "passive"))
      (node (ref "T10") (pin "7") (pinfunction "D_7") (pintype "passive"))
      (node (ref "T10") (pin "8") (pinfunction "D_8") (pintype "passive"))
      (node (ref "T10") (pin "9") (pinfunction "D_9") (pintype "passive"))
      (node (ref "T15") (pin "5") (pinfunction "D_5") (pintype "passive"))
      (node (ref "T15") (pin "6") (pinfunction "D_6") (pintype "passive"))
      (node (ref "T15") (pin "7") (pinfunction "D_7") (pintype "passive"))
      (node (ref "T15") (pin "8") (pinfunction "D_8") (pintype "passive"))
      (node (ref "T15") (pin "9") (pinfunction "D_9") (pintype "passive"))
      (node (ref "T25") (pin "5") (pinfunction "D_5") (pintype "passive"))
      (node (ref "T25") (pin "6") (pinfunction "D_6") (pintype "passive"))
      (node (ref "T25") (pin "7") (pinfunction "D_7") (pintype "passive"))
      (node (ref "T25") (pin "8") (pinfunction "D_8") (pintype "passive"))
      (node (ref "T25") (pin "9") (pinfunction "D_9") (pintype "passive"))
      (node (ref "T30") (pin "5") (pinfunction "D_5") (pintype "passive"))
      (node (ref "T30") (pin "6") (pinfunction "D_6") (pintype "passive"))
      (node (ref "T30") (pin "7") (pinfunction "D_7") (pintype "passive"))
      (node (ref "T30") (pin "8") (pinfunction "D_8") (pintype "passive"))
      (node (ref "T30") (pin "9") (pinfunction "D_9") (pintype "passive"))
    )
    (net (code "8") (name "+24V_B") (class "Default")
      (node (ref "C146") (pin "1") (pinfunction "1_1") (pintype "passive"))
      (node (ref "C147") (pin "1") (pinfunction "1_1") (pintype "passive"))
      (node (ref "C148") (pin "1") (pinfunction "1_1") (pintype "passive"))
      (node (ref "C149") (pin "1") (pinfunction "1_1") (pintype "passive"))
      (node (ref "C165") (pin "1") (pinfunction "1_1") (pintype "passive"))
      (node (ref "C166") (pin "1") (pinfunction "1_1") (pintype "passive"))
      (node (ref "C167") (pin "1") (pinfunction "1_1") (pintype "passive"))
      (node (ref "C168") (pin "1") (pinfunction "1_1") (pintype "passive"))
      (node (ref "C205") (pin "1") (pinfunction "1_1") (pintype "passive"))
      (node (ref "C206") (pin "1") (pinfunction "1_1") (pintype "passive"))
      (node (ref "C207") (pin "1") (pinfunction "1_1") (pintype "passive"))
      (node (ref "C208") (pin "1") (pinfunction "1_1") (pintype "passive"))
      (node (ref "C254") (pin "1") (pinfunction "+_1") (pintype "passive"))
      (node (ref "C255") (pin "1") (pinfunction "+_1") (pintype "passive"))
      (node (ref "C89") (pin "1") (pinfunction "1_1") (pintype "passive"))
      (node (ref "C90") (pin "1") (pinfunction "1_1") (pintype "passive"))
      (node (ref "C91") (pin "1") (pinfunction "1_1") (pintype "passive"))
      (node (ref "C92") (pin "1") (pinfunction "1_1") (pintype "passive"))
      (node (ref "D10") (pin "C") (pinfunction "C_C") (pintype "passive"))
      (node (ref "F2") (pin "2_1") (pinfunction "2_2_1") (pintype "passive"))
      (node (ref "F2") (pin "2_2") (pinfunction "2_2_2") (pintype "passive"))
      (node (ref "IC18") (pin "3") (pinfunction "VIN_3") (pintype "power_in"))
      (node (ref "IC32") (pin "3") (pinfunction "VIN_3") (pintype "power_in"))
      (node (ref "IC35") (pin "3") (pinfunction "VIN_3") (pintype "power_in"))
      (node (ref "IC41") (pin "3") (pinfunction "VIN_3") (pintype "power_in"))
      (node (ref "T20") (pin "5") (pinfunction "D_5") (pintype "passive"))
      (node (ref "T20") (pin "6") (pinfunction "D_6") (pintype "passive"))
      (node (ref "T20") (pin "7") (pinfunction "D_7") (pintype "passive"))
      (node (ref "T20") (pin "8") (pinfunction "D_8") (pintype "passive"))
      (node (ref "T20") (pin "9") (pinfunction "D_9") (pintype "passive"))
      (node (ref "T35") (pin "5") (pinfunction "D_5") (pintype "passive"))
      (node (ref "T35") (pin "6") (pinfunction "D_6") (pintype "passive"))
      (node (ref "T35") (pin "7") (pinfunction "D_7") (pintype "passive"))
      (node (ref "T35") (pin "8") (pinfunction "D_8") (pintype "passive"))
      (node (ref "T35") (pin "9") (pinfunction "D_9") (pintype "passive"))
      (node (ref "T40") (pin "5") (pinfunction "D_5") (pintype "passive"))
      (node (ref "T40") (pin "6") (pinfunction "D_6") (pintype "passive"))
      (node (ref "T40") (pin "7") (pinfunction "D_7") (pintype "passive"))
      (node (ref "T40") (pin "8") (pinfunction "D_8") (pintype "passive"))
      (node (ref "T40") (pin "9") (pinfunction "D_9") (pintype "passive"))
      (node (ref "T45") (pin "5") (pinfunction "D_5") (pintype "passive"))
      (node (ref "T45") (pin "6") (pinfunction "D_6") (pintype "passive"))
      (node (ref "T45") (pin "7") (pinfunction "D_7") (pintype "passive"))
      (node (ref "T45") (pin "8") (pinfunction "D_8") (pintype "passive"))
      (node (ref "T45") (pin "9") (pinfunction "D_9") (pintype "passive"))
    )
    (net (code "9") (name "+24V_C") (class "Default")
      (node (ref "C233") (pin "1") (pinfunction "1_1") (pintype "passive"))
      (node (ref "C237") (pin "1") (pinfunction "1_1") (pintype "passive"))
      (node (ref "C252") (pin "1") (pinfunction "+_1") (pintype "passive"))
      (node (ref "C253") (pin "1") (pinfunction "+_1") (pintype "passive"))
      (node (ref "C258") (pin "1") (pinfunction "1_1") (pintype "passive"))
      (node (ref "C262") (pin "1") (pinfunction "1_1") (pintype "passive"))
      (node (ref "C272") (pin "1") (pinfunction "1_1") (pintype "passive"))
      (node (ref "C276") (pin "1") (pinfunction "1_1") (pintype "passive"))
      (node (ref "D9") (pin "C") (pinfunction "C_C") (pintype "passive"))
      (node (ref "F1") (pin "2_1") (pinfunction "2_2_1") (pintype "passive"))
      (node (ref "F1") (pin "2_2") (pinfunction "2_2_2") (pintype "passive"))
      (node (ref "IC40") (pin "2") (pinfunction "IN_2") (pintype "bidirectional"))
      (node (ref "IC43") (pin "2") (pinfunction "IN_2") (pintype "bidirectional"))
      (node (ref "IC45") (pin "2") (pinfunction "IN_2") (pintype "bidirectional"))
      (node (ref "R241") (pin "1") (pinfunction "1_1") (pintype "passive"))
      (node (ref "R254") (pin "1") (pinfunction "1_1") (pintype "passive"))
      (node (ref "R263") (pin "1") (pinfunction "1_1") (pintype "passive"))
    )
    (net (code "10") (name "AGND") (class "Default")
      (node (ref "C1") (pin "2") (pinfunction "2_2") (pintype "passive"))
      (node (ref "C101") (pin "2") (pinfunction "2_2") (pintype "passive"))
      (node (ref "C11") (pin "2") (pinfunction "2_2") (pintype "passive"))
      (node (ref "C120") (pin "2") (pinfunction "2_2") (pintype "passive"))
      (node (ref "C139") (pin "2") (pinfunction "2_2") (pintype "passive"))
      (node (ref "C158") (pin "2") (pinfunction "2_2") (pintype "passive"))
      (node (ref "C198") (pin "2") (pinfunction "2_2") (pintype "passive"))
      (node (ref "C231") (pin "2") (pinfunction "2_2") (pintype "passive"))
      (node (ref "C232") (pin "2") (pinfunction "2_2") (pintype "passive"))
      (node (ref "C250") (pin "1") (pinfunction "1_1") (pintype "passive"))
      (node (ref "C40") (pin "2") (pinfunction "2_2") (pintype "passive"))
      (node (ref "C59") (pin "2") (pinfunction "2_2") (pintype "passive"))
      (node (ref "C78") (pin "2") (pinfunction "2_2") (pintype "passive"))
      (node (ref "ETH1") (pin "S1") (pinfunction "SHIELD_S1") (pintype "passive"))
      (node (ref "ETH1") (pin "S2") (pinfunction "SHIELD_S2") (pintype "passive"))
      (node (ref "H1") (pin "B3,3") (pinfunction "MOUNT_B3,3") (pintype "passive"))
      (node (ref "H2") (pin "B3,3") (pinfunction "MOUNT_B3,3") (pintype "passive"))
      (node (ref "H3") (pin "B3,3") (pinfunction "MOUNT_B3,3") (pintype "passive"))
      (node (ref "H4") (pin "B3,3") (pinfunction "MOUNT_B3,3") (pintype "passive"))
      (node (ref "PORT1") (pin "S1") (pinfunction "SHIELD1_S1") (pintype "passive"))
      (node (ref "PORT1") (pin "S2") (pinfunction "SHIELD1_S2") (pintype "passive"))
      (node (ref "PORT1") (pin "S3") (pinfunction "SHIELD1_S3") (pintype "passive"))
      (node (ref "PORT1") (pin "S4") (pinfunction "SHIELD1_S4") (pintype "passive"))
      (node (ref "PORT2") (pin "S1") (pinfunction "SHIELD1_S1") (pintype "passive"))
      (node (ref "PORT2") (pin "S2") (pinfunction "SHIELD1_S2") (pintype "passive"))
      (node (ref "PORT2") (pin "S3") (pinfunction "SHIELD1_S3") (pintype "passive"))
      (node (ref "PORT2") (pin "S4") (pinfunction "SHIELD1_S4") (pintype "passive"))
      (node (ref "PORT3") (pin "S1") (pinfunction "SHIELD1_S1") (pintype "passive"))
      (node (ref "PORT3") (pin "S2") (pinfunction "SHIELD1_S2") (pintype "passive"))
      (node (ref "PORT3") (pin "S3") (pinfunction "SHIELD1_S3") (pintype "passive"))
      (node (ref "PORT3") (pin "S4") (pinfunction "SHIELD1_S4") (pintype "passive"))
      (node (ref "PORT4") (pin "S1") (pinfunction "SHIELD1_S1") (pintype "passive"))
      (node (ref "PORT4") (pin "S2") (pinfunction "SHIELD1_S2") (pintype "passive"))
      (node (ref "PORT4") (pin "S3") (pinfunction "SHIELD1_S3") (pintype "passive"))
      (node (ref "PORT4") (pin "S4") (pinfunction "SHIELD1_S4") (pintype "passive"))
      (node (ref "PORT5") (pin "S1") (pinfunction "SHIELD1_S1") (pintype "passive"))
      (node (ref "PORT5") (pin "S2") (pinfunction "SHIELD1_S2") (pintype "passive"))
      (node (ref "PORT5") (pin "S3") (pinfunction "SHIELD1_S3") (pintype "passive"))
      (node (ref "PORT5") (pin "S4") (pinfunction "SHIELD1_S4") (pintype "passive"))
      (node (ref "PORT6") (pin "S1") (pinfunction "SHIELD1_S1") (pintype "passive"))
      (node (ref "PORT6") (pin "S2") (pinfunction "SHIELD1_S2") (pintype "passive"))
      (node (ref "PORT6") (pin "S3") (pinfunction "SHIELD1_S3") (pintype "passive"))
      (node (ref "PORT6") (pin "S4") (pinfunction "SHIELD1_S4") (pintype "passive"))
      (node (ref "PORT7") (pin "S1") (pinfunction "SHIELD1_S1") (pintype "passive"))
      (node (ref "PORT7") (pin "S2") (pinfunction "SHIELD1_S2") (pintype "passive"))
      (node (ref "PORT7") (pin "S3") (pinfunction "SHIELD1_S3") (pintype "passive"))
      (node (ref "PORT7") (pin "S4") (pinfunction "SHIELD1_S4") (pintype "passive"))
      (node (ref "PORT8") (pin "S1") (pinfunction "SHIELD1_S1") (pintype "passive"))
      (node (ref "PORT8") (pin "S2") (pinfunction "SHIELD1_S2") (pintype "passive"))
      (node (ref "PORT8") (pin "S3") (pinfunction "SHIELD1_S3") (pintype "passive"))
      (node (ref "PORT8") (pin "S4") (pinfunction "SHIELD1_S4") (pintype "passive"))
      (node (ref "R103") (pin "2") (pinfunction "2_2") (pintype "passive"))
      (node (ref "R126") (pin "2") (pinfunction "2_2") (pintype "passive"))
      (node (ref "R149") (pin "2") (pinfunction "2_2") (pintype "passive"))
      (node (ref "R172") (pin "2") (pinfunction "2_2") (pintype "passive"))
      (node (ref "R195") (pin "2") (pinfunction "2_2") (pintype "passive"))
      (node (ref "R2") (pin "2") (pinfunction "2_2") (pintype "passive"))
      (node (ref "R240") (pin "2") (pinfunction "2_2") (pintype "passive"))
      (node (ref "R255") (pin "1") (pinfunction "1_1") (pintype "passive"))
      (node (ref "R261") (pin "2") (pinfunction "2_2") (pintype "passive"))
      (node (ref "R56") (pin "2") (pinfunction "2_2") (pintype "passive"))
      (node (ref "R79") (pin "2") (pinfunction "2_2") (pintype "passive"))
      (node (ref "R8") (pin "2") (pinfunction "2_2") (pintype "passive"))
      (node (ref "USB9") (pin "SHLD1") (pinfunction "SHILED_SHLD1") (pintype "power_in"))
      (node (ref "USB9") (pin "SHLD2") (pinfunction "SHILED_SHLD2") (pintype "power_in"))
      (node (ref "USB9") (pin "SHLD3") (pinfunction "SHILED_SHLD3") (pintype "power_in"))
      (node (ref "USB9") (pin "SHLD4") (pinfunction "SHILED_SHLD4") (pintype "power_in"))
      (node (ref "USBA_1-2") (pin "S1") (pinfunction "SHIELD_S1") (pintype "passive"))
      (node (ref "USBA_1-2") (pin "S2") (pinfunction "SHIELD_S2") (pintype "passive"))
      (node (ref "USBA_1-2") (pin "S3") (pinfunction "SHIELD_S3") (pintype "passive"))
      (node (ref "USBA_1-2") (pin "S4") (pinfunction "SHIELD_S4") (pintype "passive"))
      (node (ref "USBA_3-4") (pin "S1") (pinfunction "SHIELD_S1") (pintype "passive"))
      (node (ref "USBA_3-4") (pin "S2") (pinfunction "SHIELD_S2") (pintype "passive"))
      (node (ref "USBA_3-4") (pin "S3") (pinfunction "SHIELD_S3") (pintype "passive"))
      (node (ref "USBA_3-4") (pin "S4") (pinfunction "SHIELD_S4") (pintype "passive"))
    )
    (net (code "11") (name "AVDD") (class "Default")
      (node (ref "AVDD") (pin "TP") (pinfunction "P$1_TP") (pintype "bidirectional"))
      (node (ref "C181") (pin "1") (pinfunction "1_1") (pintype "passive"))
      (node (ref "C191") (pin "1") (pinfunction "1_1") (pintype "passive"))
      (node (ref "IC26") (pin "43") (pinfunction "ADC_AVDD_43") (pintype "bidirectional"))
      (node (ref "IC28") (pin "1") (pinfunction "OUT_1") (pintype "output"))
      (node (ref "IC28") (pin "4") (pinfunction "-IN_4") (pintype "input"))
    )
    (net (code "12") (name "CC1_PORT1") (class "Default")
      (node (ref "IC9") (pin "2") (pinfunction "CC1_2") (pintype "bidirectional"))
      (node (ref "PORT1") (pin "A5") (pinfunction "CC1_A5") (pintype "passive"))
    )
    (net (code "13") (name "CC1_PORT2") (class "Default")
      (node (ref "IC10") (pin "2") (pinfunction "CC1_2") (pintype "bidirectional"))
      (node (ref "PORT2") (pin "A5") (pinfunction "CC1_A5") (pintype "passive"))
    )
    (net (code "14") (name "CC1_PORT3") (class "Default")
      (node (ref "IC11") (pin "2") (pinfunction "CC1_2") (pintype "bidirectional"))
      (node (ref "PORT3") (pin "A5") (pinfunction "CC1_A5") (pintype "passive"))
    )
    (net (code "15") (name "CC1_PORT4") (class "Default")
      (node (ref "IC14") (pin "2") (pinfunction "CC1_2") (pintype "bidirectional"))
      (node (ref "PORT4") (pin "A5") (pinfunction "CC1_A5") (pintype "passive"))
    )
    (net (code "16") (name "CC1_PORT5") (class "Default")
      (node (ref "IC17") (pin "2") (pinfunction "CC1_2") (pintype "bidirectional"))
      (node (ref "PORT5") (pin "A5") (pinfunction "CC1_A5") (pintype "passive"))
    )
    (net (code "17") (name "CC1_PORT6") (class "Default")
      (node (ref "IC20") (pin "2") (pinfunction "CC1_2") (pintype "bidirectional"))
      (node (ref "PORT6") (pin "A5") (pinfunction "CC1_A5") (pintype "passive"))
    )
    (net (code "18") (name "CC1_PORT7") (class "Default")
      (node (ref "IC23") (pin "2") (pinfunction "CC1_2") (pintype "bidirectional"))
      (node (ref "PORT7") (pin "A5") (pinfunction "CC1_A5") (pintype "passive"))
    )
    (net (code "19") (name "CC1_PORT8") (class "Default")
      (node (ref "IC30") (pin "2") (pinfunction "CC1_2") (pintype "bidirectional"))
      (node (ref "PORT8") (pin "A5") (pinfunction "CC1_A5") (pintype "passive"))
    )
    (net (code "20") (name "CC2_PORT1") (class "Default")
      (node (ref "IC9") (pin "3") (pinfunction "CC2_3") (pintype "bidirectional"))
      (node (ref "PORT1") (pin "B5") (pinfunction "CC2_B5") (pintype "passive"))
    )
    (net (code "21") (name "CC2_PORT2") (class "Default")
      (node (ref "IC10") (pin "3") (pinfunction "CC2_3") (pintype "bidirectional"))
      (node (ref "PORT2") (pin "B5") (pinfunction "CC2_B5") (pintype "passive"))
    )
    (net (code "22") (name "CC2_PORT3") (class "Default")
      (node (ref "IC11") (pin "3") (pinfunction "CC2_3") (pintype "bidirectional"))
      (node (ref "PORT3") (pin "B5") (pinfunction "CC2_B5") (pintype "passive"))
    )
    (net (code "23") (name "CC2_PORT4") (class "Default")
      (node (ref "IC14") (pin "3") (pinfunction "CC2_3") (pintype "bidirectional"))
      (node (ref "PORT4") (pin "B5") (pinfunction "CC2_B5") (pintype "passive"))
    )
    (net (code "24") (name "CC2_PORT5") (class "Default")
      (node (ref "IC17") (pin "3") (pinfunction "CC2_3") (pintype "bidirectional"))
      (node (ref "PORT5") (pin "B5") (pinfunction "CC2_B5") (pintype "passive"))
    )
    (net (code "25") (name "CC2_PORT6") (class "Default")
      (node (ref "IC20") (pin "3") (pinfunction "CC2_3") (pintype "bidirectional"))
      (node (ref "PORT6") (pin "B5") (pinfunction "CC2_B5") (pintype "passive"))
    )
    (net (code "26") (name "CC2_PORT7") (class "Default")
      (node (ref "IC23") (pin "3") (pinfunction "CC2_3") (pintype "bidirectional"))
      (node (ref "PORT7") (pin "B5") (pinfunction "CC2_B5") (pintype "passive"))
    )
    (net (code "27") (name "CC2_PORT8") (class "Default")
      (node (ref "IC30") (pin "3") (pinfunction "CC2_3") (pintype "bidirectional"))
      (node (ref "PORT8") (pin "B5") (pinfunction "CC2_B5") (pintype "passive"))
    )
    (net (code "28") (name "EN_PORT1") (class "Default")
      (node (ref "IC12") (pin "4") (pinfunction "EN_4") (pintype "input"))
      (node (ref "IC42") (pin "25") (pinfunction "IO2.0_25") (pintype "bidirectional"))
      (node (ref "R66") (pin "2") (pinfunction "2_2") (pintype "passive"))
    )
    (net (code "29") (name "EN_PORT2") (class "Default")
      (node (ref "IC15") (pin "4") (pinfunction "EN_4") (pintype "input"))
      (node (ref "IC42") (pin "26") (pinfunction "IO2.1_26") (pintype "bidirectional"))
      (node (ref "R90") (pin "2") (pinfunction "2_2") (pintype "passive"))
    )
    (net (code "30") (name "EN_PORT3") (class "Default")
      (node (ref "IC24") (pin "4") (pinfunction "EN_4") (pintype "input"))
      (node (ref "IC42") (pin "27") (pinfunction "IO2.2_27") (pintype "bidirectional"))
      (node (ref "R159") (pin "2") (pinfunction "2_2") (pintype "passive"))
    )
    (net (code "31") (name "EN_PORT4") (class "Default")
      (node (ref "IC21") (pin "4") (pinfunction "EN_4") (pintype "input"))
      (node (ref "IC42") (pin "28") (pinfunction "IO2.3_28") (pintype "bidirectional"))
      (node (ref "R136") (pin "2") (pinfunction "2_2") (pintype "passive"))
    )
    (net (code "32") (name "EN_PORT5") (class "Default")
      (node (ref "IC18") (pin "4") (pinfunction "EN_4") (pintype "input"))
      (node (ref "IC42") (pin "1") (pinfunction "IO2.4_1") (pintype "bidirectional"))
      (node (ref "R113") (pin "2") (pinfunction "2_2") (pintype "passive"))
    )
    (net (code "33") (name "EN_PORT6") (class "Default")
      (node (ref "IC32") (pin "4") (pinfunction "EN_4") (pintype "input"))
      (node (ref "IC42") (pin "2") (pinfunction "IO2.5_2") (pintype "bidirectional"))
      (node (ref "R182") (pin "2") (pinfunction "2_2") (pintype "passive"))
    )
    (net (code "34") (name "EN_PORT7") (class "Default")
      (node (ref "IC35") (pin "4") (pinfunction "EN_4") (pintype "input"))
      (node (ref "IC42") (pin "3") (pinfunction "IO2.6_3") (pintype "bidirectional"))
      (node (ref "R218") (pin "2") (pinfunction "2_2") (pintype "passive"))
    )
    (net (code "35") (name "EN_PORT8") (class "Default")
      (node (ref "IC41") (pin "4") (pinfunction "EN_4") (pintype "input"))
      (node (ref "IC42") (pin "4") (pinfunction "IO2.7_4") (pintype "bidirectional"))
      (node (ref "R275") (pin "2") (pinfunction "2_2") (pintype "passive"))
    )
    (net (code "36") (name "GND") (class "Default")
      (node (ref "BOOT") (pin "2") (pinfunction "2_2") (pintype "passive"))
      (node (ref "BOOT") (pin "4") (pinfunction "4_4") (pintype "passive"))
      (node (ref "C1") (pin "1") (pinfunction "1_1") (pintype "passive"))
      (node (ref "C10") (pin "2") (pinfunction "2_2") (pintype "passive"))
      (node (ref "C100") (pin "2") (pinfunction "2_2") (pintype "passive"))
      (node (ref "C101") (pin "1") (pinfunction "1_1") (pintype "passive"))
      (node (ref "C102") (pin "2") (pinfunction "2_2") (pintype "passive"))
      (node (ref "C103") (pin "2") (pinfunction "2_2") (pintype "passive"))
      (node (ref "C104") (pin "2") (pinfunction "2_2") (pintype "passive"))
      (node (ref "C105") (pin "2") (pinfunction "2_2") (pintype "passive"))
      (node (ref "C108") (pin "2") (pinfunction "2_2") (pintype "passive"))
      (node (ref "C109") (pin "2") (pinfunction "2_2") (pintype "passive"))
      (node (ref "C11") (pin "1") (pinfunction "1_1") (pintype "passive"))
      (node (ref "C110") (pin "2") (pinfunction "2_2") (pintype "passive"))
      (node (ref "C111") (pin "2") (pinfunction "2_2") (pintype "passive"))
      (node (ref "C112") (pin "2") (pinfunction "2_2") (pintype "passive"))
      (node (ref "C113") (pin "2") (pinfunction "2_2") (pintype "passive"))
      (node (ref "C114") (pin "2") (pinfunction "2_2") (pintype "passive"))
      (node (ref "C115") (pin "2") (pinfunction "2_2") (pintype "passive"))
      (node (ref "C116") (pin "2") (pinfunction "2_2") (pintype "passive"))
      (node (ref "C117") (pin "2") (pinfunction "2_2") (pintype "passive"))
      (node (ref "C118") (pin "2") (pinfunction "2_2") (pintype "passive"))
      (node (ref "C119") (pin "2") (pinfunction "2_2") (pintype "passive"))
      (node (ref "C12") (pin "2") (pinfunction "2_2") (pintype "passive"))
      (node (ref "C120") (pin "1") (pinfunction "1_1") (pintype "passive"))
      (node (ref "C121") (pin "2") (pinfunction "2_2") (pintype "passive"))
      (node (ref "C122") (pin "2") (pinfunction "2_2") (pintype "passive"))
      (node (ref "C123") (pin "2") (pinfunction "2_2") (pintype "passive"))
      (node (ref "C124") (pin "2") (pinfunction "2_2") (pintype "passive"))
      (node (ref "C127") (pin "2") (pinfunction "2_2") (pintype "passive"))
      (node (ref "C128") (pin "2") (pinfunction "2_2") (pintype "passive"))
      (node (ref "C129") (pin "2") (pinfunction "2_2") (pintype "passive"))
      (node (ref "C13") (pin "2") (pinfunction "2_2") (pintype "passive"))
      (node (ref "C130") (pin "2") (pinfunction "2_2") (pintype "passive"))
      (node (ref "C131") (pin "2") (pinfunction "2_2") (pintype "passive"))
      (node (ref "C132") (pin "2") (pinfunction "2_2") (pintype "passive"))
      (node (ref "C133") (pin "2") (pinfunction "2_2") (pintype "passive"))
      (node (ref "C134") (pin "2") (pinfunction "2_2") (pintype "passive"))
      (node (ref "C135") (pin "2") (pinfunction "2_2") (pintype "passive"))
      (node (ref "C136") (pin "2") (pinfunction "2_2") (pintype "passive"))
      (node (ref "C137") (pin "2") (pinfunction "2_2") (pintype "passive"))
      (node (ref "C138") (pin "2") (pinfunction "2_2") (pintype "passive"))
      (node (ref "C139") (pin "1") (pinfunction "1_1") (pintype "passive"))
      (node (ref "C14") (pin "2") (pinfunction "2_2") (pintype "passive"))
      (node (ref "C140") (pin "2") (pinfunction "2_2") (pintype "passive"))
      (node (ref "C141") (pin "2") (pinfunction "2_2") (pintype "passive"))
      (node (ref "C142") (pin "2") (pinfunction "2_2") (pintype "passive"))
      (node (ref "C143") (pin "2") (pinfunction "2_2") (pintype "passive"))
      (node (ref "C146") (pin "2") (pinfunction "2_2") (pintype "passive"))
      (node (ref "C147") (pin "2") (pinfunction "2_2") (pintype "passive"))
      (node (ref "C148") (pin "2") (pinfunction "2_2") (pintype "passive"))
      (node (ref "C149") (pin "2") (pinfunction "2_2") (pintype "passive"))
      (node (ref "C15") (pin "2") (pinfunction "2_2") (pintype "passive"))
      (node (ref "C150") (pin "2") (pinfunction "2_2") (pintype "passive"))
      (node (ref "C151") (pin "2") (pinfunction "2_2") (pintype "passive"))
      (node (ref "C152") (pin "2") (pinfunction "2_2") (pintype "passive"))
      (node (ref "C153") (pin "2") (pinfunction "2_2") (pintype "passive"))
      (node (ref "C154") (pin "2") (pinfunction "2_2") (pintype "passive"))
      (node (ref "C155") (pin "2") (pinfunction "2_2") (pintype "passive"))
      (node (ref "C156") (pin "2") (pinfunction "2_2") (pintype "passive"))
      (node (ref "C157") (pin "2") (pinfunction "2_2") (pintype "passive"))
      (node (ref "C158") (pin "1") (pinfunction "1_1") (pintype "passive"))
      (node (ref "C159") (pin "2") (pinfunction "2_2") (pintype "passive"))
      (node (ref "C16") (pin "2") (pinfunction "2_2") (pintype "passive"))
      (node (ref "C160") (pin "2") (pinfunction "2_2") (pintype "passive"))
      (node (ref "C161") (pin "2") (pinfunction "2_2") (pintype "passive"))
      (node (ref "C162") (pin "2") (pinfunction "2_2") (pintype "passive"))
      (node (ref "C165") (pin "2") (pinfunction "2_2") (pintype "passive"))
      (node (ref "C166") (pin "2") (pinfunction "2_2") (pintype "passive"))
      (node (ref "C167") (pin "2") (pinfunction "2_2") (pintype "passive"))
      (node (ref "C168") (pin "2") (pinfunction "2_2") (pintype "passive"))
      (node (ref "C169") (pin "2") (pinfunction "2_2") (pintype "passive"))
      (node (ref "C17") (pin "2") (pinfunction "2_2") (pintype "passive"))
      (node (ref "C170") (pin "2") (pinfunction "2_2") (pintype "passive"))
      (node (ref "C171") (pin "2") (pinfunction "2_2") (pintype "passive"))
      (node (ref "C172") (pin "2") (pinfunction "2_2") (pintype "passive"))
      (node (ref "C173") (pin "2") (pinfunction "2_2") (pintype "passive"))
      (node (ref "C174") (pin "2") (pinfunction "2_2") (pintype "passive"))
      (node (ref "C175") (pin "2") (pinfunction "2_2") (pintype "passive"))
      (node (ref "C176") (pin "2") (pinfunction "2_2") (pintype "passive"))
      (node (ref "C177") (pin "2") (pinfunction "2_2") (pintype "passive"))
      (node (ref "C178") (pin "2") (pinfunction "2_2") (pintype "passive"))
      (node (ref "C179") (pin "2") (pinfunction "2_2") (pintype "passive"))
      (node (ref "C18") (pin "2") (pinfunction "2_2") (pintype "passive"))
      (node (ref "C180") (pin "2") (pinfunction "2_2") (pintype "passive"))
      (node (ref "C181") (pin "2") (pinfunction "2_2") (pintype "passive"))
      (node (ref "C182") (pin "2") (pinfunction "2_2") (pintype "passive"))
      (node (ref "C183") (pin "2") (pinfunction "2_2") (pintype "passive"))
      (node (ref "C184") (pin "2") (pinfunction "2_2") (pintype "passive"))
      (node (ref "C185") (pin "2") (pinfunction "2_2") (pintype "passive"))
      (node (ref "C186") (pin "2") (pinfunction "2_2") (pintype "passive"))
      (node (ref "C187") (pin "2") (pinfunction "2_2") (pintype "passive"))
      (node (ref "C188") (pin "2") (pinfunction "2_2") (pintype "passive"))
      (node (ref "C189") (pin "2") (pinfunction "2_2") (pintype "passive"))
      (node (ref "C19") (pin "2") (pinfunction "2_2") (pintype "passive"))
      (node (ref "C190") (pin "2") (pinfunction "2_2") (pintype "passive"))
      (node (ref "C191") (pin "2") (pinfunction "2_2") (pintype "passive"))
      (node (ref "C192") (pin "2") (pinfunction "2_2") (pintype "passive"))
      (node (ref "C193") (pin "2") (pinfunction "2_2") (pintype "passive"))
      (node (ref "C194") (pin "2") (pinfunction "2_2") (pintype "passive"))
      (node (ref "C195") (pin "2") (pinfunction "2_2") (pintype "passive"))
      (node (ref "C197") (pin "2") (pinfunction "2_2") (pintype "passive"))
      (node (ref "C198") (pin "1") (pinfunction "1_1") (pintype "passive"))
      (node (ref "C199") (pin "2") (pinfunction "2_2") (pintype "passive"))
      (node (ref "C2") (pin "2") (pinfunction "2_2") (pintype "passive"))
      (node (ref "C20") (pin "2") (pinfunction "2_2") (pintype "passive"))
      (node (ref "C200") (pin "2") (pinfunction "2_2") (pintype "passive"))
      (node (ref "C201") (pin "2") (pinfunction "2_2") (pintype "passive"))
      (node (ref "C202") (pin "2") (pinfunction "2_2") (pintype "passive"))
      (node (ref "C205") (pin "2") (pinfunction "2_2") (pintype "passive"))
      (node (ref "C206") (pin "2") (pinfunction "2_2") (pintype "passive"))
      (node (ref "C207") (pin "2") (pinfunction "2_2") (pintype "passive"))
      (node (ref "C208") (pin "2") (pinfunction "2_2") (pintype "passive"))
      (node (ref "C209") (pin "2") (pinfunction "2_2") (pintype "passive"))
      (node (ref "C210") (pin "2") (pinfunction "2_2") (pintype "passive"))
      (node (ref "C211") (pin "2") (pinfunction "2_2") (pintype "passive"))
      (node (ref "C212") (pin "2") (pinfunction "2_2") (pintype "passive"))
      (node (ref "C213") (pin "2") (pinfunction "2_2") (pintype "passive"))
      (node (ref "C214") (pin "2") (pinfunction "2_2") (pintype "passive"))
      (node (ref "C217") (pin "2") (pinfunction "2_2") (pintype "passive"))
      (node (ref "C218") (pin "2") (pinfunction "2_2") (pintype "passive"))
      (node (ref "C219") (pin "2") (pinfunction "2_2") (pintype "passive"))
      (node (ref "C220") (pin "2") (pinfunction "2_2") (pintype "passive"))
      (node (ref "C221") (pin "2") (pinfunction "2_2") (pintype "passive"))
      (node (ref "C222") (pin "2") (pinfunction "2_2") (pintype "passive"))
      (node (ref "C223") (pin "2") (pinfunction "2_2") (pintype "passive"))
      (node (ref "C224") (pin "2") (pinfunction "2_2") (pintype "passive"))
      (node (ref "C225") (pin "2") (pinfunction "2_2") (pintype "passive"))
      (node (ref "C226") (pin "2") (pinfunction "2_2") (pintype "passive"))
      (node (ref "C227") (pin "2") (pinfunction "2_2") (pintype "passive"))
      (node (ref "C228") (pin "2") (pinfunction "2_2") (pintype "passive"))
      (node (ref "C229") (pin "2") (pinfunction "2_2") (pintype "passive"))
      (node (ref "C230") (pin "2") (pinfunction "2_2") (pintype "passive"))
      (node (ref "C231") (pin "1") (pinfunction "1_1") (pintype "passive"))
      (node (ref "C232") (pin "1") (pinfunction "1_1") (pintype "passive"))
      (node (ref "C233") (pin "2") (pinfunction "2_2") (pintype "passive"))
      (node (ref "C234") (pin "2") (pinfunction "2_2") (pintype "passive"))
      (node (ref "C237") (pin "2") (pinfunction "2_2") (pintype "passive"))
      (node (ref "C238") (pin "2") (pinfunction "2_2") (pintype "passive"))
      (node (ref "C239") (pin "2") (pinfunction "2_2") (pintype "passive"))
      (node (ref "C240") (pin "2") (pinfunction "2_2") (pintype "passive"))
      (node (ref "C241") (pin "2") (pinfunction "2_2") (pintype "passive"))
      (node (ref "C247") (pin "2") (pinfunction "2_2") (pintype "passive"))
      (node (ref "C248") (pin "2") (pinfunction "2_2") (pintype "passive"))
      (node (ref "C249") (pin "2") (pinfunction "2_2") (pintype "passive"))
      (node (ref "C250") (pin "2") (pinfunction "2_2") (pintype "passive"))
      (node (ref "C251") (pin "2") (pinfunction "2_2") (pintype "passive"))
      (node (ref "C252") (pin "2") (pinfunction "-_2") (pintype "passive"))
      (node (ref "C253") (pin "2") (pinfunction "-_2") (pintype "passive"))
      (node (ref "C254") (pin "2") (pinfunction "-_2") (pintype "passive"))
      (node (ref "C255") (pin "2") (pinfunction "-_2") (pintype "passive"))
      (node (ref "C256") (pin "2") (pinfunction "-_2") (pintype "passive"))
      (node (ref "C257") (pin "2") (pinfunction "-_2") (pintype "passive"))
      (node (ref "C258") (pin "2") (pinfunction "2_2") (pintype "passive"))
      (node (ref "C259") (pin "2") (pinfunction "2_2") (pintype "passive"))
      (node (ref "C262") (pin "2") (pinfunction "2_2") (pintype "passive"))
      (node (ref "C263") (pin "2") (pinfunction "2_2") (pintype "passive"))
      (node (ref "C264") (pin "2") (pinfunction "2_2") (pintype "passive"))
      (node (ref "C272") (pin "2") (pinfunction "2_2") (pintype "passive"))
      (node (ref "C273") (pin "2") (pinfunction "2_2") (pintype "passive"))
      (node (ref "C276") (pin "2") (pinfunction "2_2") (pintype "passive"))
      (node (ref "C277") (pin "2") (pinfunction "2_2") (pintype "passive"))
      (node (ref "C278") (pin "2") (pinfunction "2_2") (pintype "passive"))
      (node (ref "C3") (pin "2") (pinfunction "2_2") (pintype "passive"))
      (node (ref "C39") (pin "2") (pinfunction "2_2") (pintype "passive"))
      (node (ref "C4") (pin "2") (pinfunction "2_2") (pintype "passive"))
      (node (ref "C40") (pin "1") (pinfunction "1_1") (pintype "passive"))
      (node (ref "C41") (pin "2") (pinfunction "2_2") (pintype "passive"))
      (node (ref "C42") (pin "2") (pinfunction "2_2") (pintype "passive"))
      (node (ref "C43") (pin "2") (pinfunction "2_2") (pintype "passive"))
      (node (ref "C44") (pin "2") (pinfunction "2_2") (pintype "passive"))
      (node (ref "C47") (pin "2") (pinfunction "2_2") (pintype "passive"))
      (node (ref "C48") (pin "2") (pinfunction "2_2") (pintype "passive"))
      (node (ref "C49") (pin "2") (pinfunction "2_2") (pintype "passive"))
      (node (ref "C5") (pin "2") (pinfunction "2_2") (pintype "passive"))
      (node (ref "C50") (pin "2") (pinfunction "2_2") (pintype "passive"))
      (node (ref "C51") (pin "2") (pinfunction "2_2") (pintype "passive"))
      (node (ref "C52") (pin "2") (pinfunction "2_2") (pintype "passive"))
      (node (ref "C53") (pin "2") (pinfunction "2_2") (pintype "passive"))
      (node (ref "C54") (pin "2") (pinfunction "2_2") (pintype "passive"))
      (node (ref "C55") (pin "2") (pinfunction "2_2") (pintype "passive"))
      (node (ref "C56") (pin "2") (pinfunction "2_2") (pintype "passive"))
      (node (ref "C57") (pin "2") (pinfunction "2_2") (pintype "passive"))
      (node (ref "C58") (pin "2") (pinfunction "2_2") (pintype "passive"))
      (node (ref "C59") (pin "1") (pinfunction "1_1") (pintype "passive"))
      (node (ref "C6") (pin "2") (pinfunction "2_2") (pintype "passive"))
      (node (ref "C60") (pin "2") (pinfunction "2_2") (pintype "passive"))
      (node (ref "C61") (pin "2") (pinfunction "2_2") (pintype "passive"))
      (node (ref "C62") (pin "2") (pinfunction "2_2") (pintype "passive"))
      (node (ref "C63") (pin "2") (pinfunction "2_2") (pintype "passive"))
      (node (ref "C66") (pin "2") (pinfunction "2_2") (pintype "passive"))
      (node (ref "C67") (pin "2") (pinfunction "2_2") (pintype "passive"))
      (node (ref "C68") (pin "2") (pinfunction "2_2") (pintype "passive"))
      (node (ref "C69") (pin "2") (pinfunction "2_2") (pintype "passive"))
      (node (ref "C7") (pin "2") (pinfunction "2_2") (pintype "passive"))
      (node (ref "C70") (pin "2") (pinfunction "2_2") (pintype "passive"))
      (node (ref "C71") (pin "2") (pinfunction "2_2") (pintype "passive"))
      (node (ref "C72") (pin "2") (pinfunction "2_2") (pintype "passive"))
      (node (ref "C73") (pin "2") (pinfunction "2_2") (pintype "passive"))
      (node (ref "C74") (pin "2") (pinfunction "2_2") (pintype "passive"))
      (node (ref "C75") (pin "2") (pinfunction "2_2") (pintype "passive"))
      (node (ref "C76") (pin "2") (pinfunction "2_2") (pintype "passive"))
      (node (ref "C77") (pin "2") (pinfunction "2_2") (pintype "passive"))
      (node (ref "C78") (pin "1") (pinfunction "1_1") (pintype "passive"))
      (node (ref "C79") (pin "2") (pinfunction "2_2") (pintype "passive"))
      (node (ref "C8") (pin "2") (pinfunction "2_2") (pintype "passive"))
      (node (ref "C80") (pin "2") (pinfunction "2_2") (pintype "passive"))
      (node (ref "C81") (pin "2") (pinfunction "2_2") (pintype "passive"))
      (node (ref "C82") (pin "2") (pinfunction "2_2") (pintype "passive"))
      (node (ref "C83") (pin "2") (pinfunction "2_2") (pintype "passive"))
      (node (ref "C84") (pin "2") (pinfunction "2_2") (pintype "passive"))
      (node (ref "C85") (pin "2") (pinfunction "2_2") (pintype "passive"))
      (node (ref "C86") (pin "2") (pinfunction "2_2") (pintype "passive"))
      (node (ref "C89") (pin "2") (pinfunction "2_2") (pintype "passive"))
      (node (ref "C9") (pin "2") (pinfunction "2_2") (pintype "passive"))
      (node (ref "C90") (pin "2") (pinfunction "2_2") (pintype "passive"))
      (node (ref "C91") (pin "2") (pinfunction "2_2") (pintype "passive"))
      (node (ref "C92") (pin "2") (pinfunction "2_2") (pintype "passive"))
      (node (ref "C93") (pin "2") (pinfunction "2_2") (pintype "passive"))
      (node (ref "C94") (pin "2") (pinfunction "2_2") (pintype "passive"))
      (node (ref "C95") (pin "2") (pinfunction "2_2") (pintype "passive"))
      (node (ref "C96") (pin "2") (pinfunction "2_2") (pintype "passive"))
      (node (ref "C97") (pin "2") (pinfunction "2_2") (pintype "passive"))
      (node (ref "C98") (pin "2") (pinfunction "2_2") (pintype "passive"))
      (node (ref "C99") (pin "2") (pinfunction "2_2") (pintype "passive"))
      (node (ref "D1") (pin "C") (pinfunction "C_C") (pintype "passive"))
      (node (ref "D10") (pin "A") (pinfunction "A_A") (pintype "passive"))
      (node (ref "D11") (pin "A") (pinfunction "A_A") (pintype "passive"))
      (node (ref "D3") (pin "C") (pinfunction "C_C") (pintype "passive"))
      (node (ref "D5") (pin "C") (pinfunction "C_C") (pintype "passive"))
      (node (ref "D7") (pin "C") (pinfunction "C_C") (pintype "passive"))
      (node (ref "D9") (pin "A") (pinfunction "A_A") (pintype "passive"))
      (node (ref "DISP") (pin "5") (pinfunction "5_5") (pintype "bidirectional"))
      (node (ref "DISP") (pin "8") (pinfunction "8_8") (pintype "bidirectional"))
      (node (ref "DISP") (pin "Z0") (pinfunction "Z1_Z0") (pintype "bidirectional"))
      (node (ref "DISP") (pin "Z1") (pinfunction "Z1_Z1") (pintype "bidirectional"))
      (node (ref "DISP") (pin "Z2") (pinfunction "Z2_Z2") (pintype "bidirectional"))
      (node (ref "DISP") (pin "Z3") (pinfunction "Z3_Z3") (pintype "bidirectional"))
      (node (ref "DISP") (pin "Z4") (pinfunction "Z3_Z4") (pintype "bidirectional"))
      (node (ref "DISP") (pin "Z5") (pinfunction "Z4_Z5") (pintype "bidirectional"))
      (node (ref "ESD1") (pin "1") (pinfunction "A_1") (pintype "bidirectional"))
      (node (ref "ETH1") (pin "8") (pinfunction "SHIELD-P8_8") (pintype "passive"))
      (node (ref "GND") (pin "TP") (pinfunction "P$1_TP") (pintype "bidirectional"))
      (node (ref "IC1") (pin "2") (pinfunction "GND_2") (pintype "bidirectional"))
      (node (ref "IC10") (pin "6") (pinfunction "GND_6") (pintype "power_in"))
      (node (ref "IC11") (pin "6") (pinfunction "GND_6") (pintype "power_in"))
      (node (ref "IC12") (pin "10") (pinfunction "AGND_10") (pintype "power_in"))
      (node (ref "IC12") (pin "24") (pinfunction "PGND_24") (pintype "power_in"))
      (node (ref "IC12") (pin "9") (pinfunction "PGND_9") (pintype "power_in"))
      (node (ref "IC13") (pin "3") (pinfunction "GND_3") (pintype "bidirectional"))
      (node (ref "IC13") (pin "7") (pinfunction "A0_7") (pintype "bidirectional"))
      (node (ref "IC13") (pin "8") (pinfunction "A1_8") (pintype "bidirectional"))
      (node (ref "IC14") (pin "6") (pinfunction "GND_6") (pintype "power_in"))
      (node (ref "IC15") (pin "10") (pinfunction "AGND_10") (pintype "power_in"))
      (node (ref "IC15") (pin "24") (pinfunction "PGND_24") (pintype "power_in"))
      (node (ref "IC15") (pin "9") (pinfunction "PGND_9") (pintype "power_in"))
      (node (ref "IC16") (pin "3") (pinfunction "GND_3") (pintype "bidirectional"))
      (node (ref "IC16") (pin "8") (pinfunction "A1_8") (pintype "bidirectional"))
      (node (ref "IC17") (pin "6") (pinfunction "GND_6") (pintype "power_in"))
      (node (ref "IC18") (pin "10") (pinfunction "AGND_10") (pintype "power_in"))
      (node (ref "IC18") (pin "24") (pinfunction "PGND_24") (pintype "power_in"))
      (node (ref "IC18") (pin "9") (pinfunction "PGND_9") (pintype "power_in"))
      (node (ref "IC19") (pin "3") (pinfunction "GND_3") (pintype "bidirectional"))
      (node (ref "IC19") (pin "7") (pinfunction "A0_7") (pintype "bidirectional"))
      (node (ref "IC19") (pin "8") (pinfunction "A1_8") (pintype "bidirectional"))
      (node (ref "IC2") (pin "2") (pinfunction "GND_2") (pintype "bidirectional"))
      (node (ref "IC20") (pin "6") (pinfunction "GND_6") (pintype "power_in"))
      (node (ref "IC21") (pin "10") (pinfunction "AGND_10") (pintype "power_in"))
      (node (ref "IC21") (pin "24") (pinfunction "PGND_24") (pintype "power_in"))
      (node (ref "IC21") (pin "9") (pinfunction "PGND_9") (pintype "power_in"))
      (node (ref "IC22") (pin "3") (pinfunction "GND_3") (pintype "bidirectional"))
      (node (ref "IC23") (pin "6") (pinfunction "GND_6") (pintype "power_in"))
      (node (ref "IC24") (pin "10") (pinfunction "AGND_10") (pintype "power_in"))
      (node (ref "IC24") (pin "24") (pinfunction "PGND_24") (pintype "power_in"))
      (node (ref "IC24") (pin "9") (pinfunction "PGND_9") (pintype "power_in"))
      (node (ref "IC25") (pin "3") (pinfunction "GND_3") (pintype "bidirectional"))
      (node (ref "IC25") (pin "7") (pinfunction "A0_7") (pintype "bidirectional"))
      (node (ref "IC26") (pin "19") (pinfunction "TESTEN_19") (pintype "bidirectional"))
      (node (ref "IC26") (pin "57") (pinfunction "GND_57") (pintype "bidirectional"))
      (node (ref "IC27") (pin "4") (pinfunction "GND_4") (pintype "power_in"))
      (node (ref "IC28") (pin "5") (pinfunction "V-_5") (pintype "power_in"))
      (node (ref "IC29") (pin "2") (pinfunction "A1_2") (pintype "bidirectional"))
      (node (ref "IC29") (pin "3") (pinfunction "A2_3") (pintype "bidirectional"))
      (node (ref "IC29") (pin "4") (pinfunction "GND_4") (pintype "power_in"))
      (node (ref "IC29") (pin "7") (pinfunction "WP_7") (pintype "bidirectional"))
      (node (ref "IC29") (pin "9") (pinfunction "GND_9") (pintype "power_in"))
      (node (ref "IC3") (pin "2") (pinfunction "GND_2") (pintype "bidirectional"))
      (node (ref "IC30") (pin "6") (pinfunction "GND_6") (pintype "power_in"))
      (node (ref "IC32") (pin "10") (pinfunction "AGND_10") (pintype "power_in"))
      (node (ref "IC32") (pin "24") (pinfunction "PGND_24") (pintype "power_in"))
      (node (ref "IC32") (pin "9") (pinfunction "PGND_9") (pintype "power_in"))
      (node (ref "IC33") (pin "3") (pinfunction "GND_3") (pintype "bidirectional"))
      (node (ref "IC33") (pin "8") (pinfunction "A1_8") (pintype "bidirectional"))
      (node (ref "IC35") (pin "10") (pinfunction "AGND_10") (pintype "power_in"))
      (node (ref "IC35") (pin "24") (pinfunction "PGND_24") (pintype "power_in"))
      (node (ref "IC35") (pin "9") (pinfunction "PGND_9") (pintype "power_in"))
      (node (ref "IC36") (pin "3") (pinfunction "GND_3") (pintype "bidirectional"))
      (node (ref "IC36") (pin "7") (pinfunction "A0_7") (pintype "bidirectional"))
      (node (ref "IC38") (pin "18") (pinfunction "A2_18") (pintype "input"))
      (node (ref "IC38") (pin "22") (pinfunction "A0_22") (pintype "input"))
      (node (ref "IC38") (pin "23") (pinfunction "A1_23") (pintype "input"))
      (node (ref "IC38") (pin "25") (pinfunction "GND_25") (pintype "power_in"))
      (node (ref "IC38") (pin "9") (pinfunction "GND_9") (pintype "power_in"))
      (node (ref "IC39") (pin "14") (pinfunction "AGND_14") (pintype "power_in"))
      (node (ref "IC39") (pin "16") (pinfunction "AGND_16") (pintype "power_in"))
      (node (ref "IC39") (pin "19") (pinfunction "AGND_19") (pintype "power_in"))
      (node (ref "IC39") (pin "29") (pinfunction "GND_29") (pintype "passive"))
      (node (ref "IC39") (pin "3") (pinfunction "AGND_3") (pintype "power_in"))
      (node (ref "IC39") (pin "48") (pinfunction "AGND_48") (pintype "power_in"))
      (node (ref "IC39") (pin "9") (pinfunction "AGND_9") (pintype "power_in"))
      (node (ref "IC4") (pin "3") (pinfunction "V-_3") (pintype "bidirectional"))
      (node (ref "IC40") (pin "4") (pinfunction "GND_4") (pintype "bidirectional"))
      (node (ref "IC41") (pin "10") (pinfunction "AGND_10") (pintype "power_in"))
      (node (ref "IC41") (pin "24") (pinfunction "PGND_24") (pintype "power_in"))
      (node (ref "IC41") (pin "9") (pinfunction "PGND_9") (pintype "power_in"))
      (node (ref "IC42") (pin "11") (pinfunction "A0_11") (pintype "bidirectional"))
      (node (ref "IC42") (pin "12") (pinfunction "A1_12") (pintype "bidirectional"))
      (node (ref "IC42") (pin "13") (pinfunction "A2_13") (pintype "bidirectional"))
      (node (ref "IC42") (pin "6") (pinfunction "VSS_6") (pintype "bidirectional"))
      (node (ref "IC42") (pin "PAD") (pinfunction "VSS_PAD") (pintype "bidirectional"))
      (node (ref "IC43") (pin "4") (pinfunction "GND_4") (pintype "bidirectional"))
      (node (ref "IC44") (pin "3") (pinfunction "GND_3") (pintype "bidirectional"))
      (node (ref "IC45") (pin "4") (pinfunction "GND_4") (pintype "bidirectional"))
      (node (ref "IC5") (pin "3") (pinfunction "V-_3") (pintype "bidirectional"))
      (node (ref "IC6") (pin "3") (pinfunction "V-_3") (pintype "bidirectional"))
      (node (ref "IC7") (pin "3") (pinfunction "V-_3") (pintype "bidirectional"))
      (node (ref "IC8") (pin "2") (pinfunction "GND_2") (pintype "bidirectional"))
      (node (ref "IC9") (pin "6") (pinfunction "GND_6") (pintype "power_in"))
      (node (ref "J8") (pin "4") (pinfunction "4_4") (pintype "passive"))
      (node (ref "J8") (pin "5") (pinfunction "5_5") (pintype "passive"))
      (node (ref "J8") (pin "6") (pinfunction "6_6") (pintype "passive"))
      (node (ref "PORT1") (pin "A12") (pinfunction "GND1_A12") (pintype "passive"))
      (node (ref "PORT1") (pin "B12") (pinfunction "GND2_B12") (pintype "passive"))
      (node (ref "PORT2") (pin "A12") (pinfunction "GND1_A12") (pintype "passive"))
      (node (ref "PORT2") (pin "B12") (pinfunction "GND2_B12") (pintype "passive"))
      (node (ref "PORT3") (pin "A12") (pinfunction "GND1_A12") (pintype "passive"))
      (node (ref "PORT3") (pin "B12") (pinfunction "GND2_B12") (pintype "passive"))
      (node (ref "PORT4") (pin "A12") (pinfunction "GND1_A12") (pintype "passive"))
      (node (ref "PORT4") (pin "B12") (pinfunction "GND2_B12") (pintype "passive"))
      (node (ref "PORT5") (pin "A12") (pinfunction "GND1_A12") (pintype "passive"))
      (node (ref "PORT5") (pin "B12") (pinfunction "GND2_B12") (pintype "passive"))
      (node (ref "PORT6") (pin "A12") (pinfunction "GND1_A12") (pintype "passive"))
      (node (ref "PORT6") (pin "B12") (pinfunction "GND2_B12") (pintype "passive"))
      (node (ref "PORT7") (pin "A12") (pinfunction "GND1_A12") (pintype "passive"))
      (node (ref "PORT7") (pin "B12") (pinfunction "GND2_B12") (pintype "passive"))
      (node (ref "PORT8") (pin "A12") (pinfunction "GND1_A12") (pintype "passive"))
      (node (ref "PORT8") (pin "B12") (pinfunction "GND2_B12") (pintype "passive"))
      (node (ref "R103") (pin "1") (pinfunction "1_1") (pintype "passive"))
      (node (ref "R105") (pin "2") (pinfunction "2_2") (pintype "passive"))
      (node (ref "R106") (pin "2") (pinfunction "2_2") (pintype "passive"))
      (node (ref "R107") (pin "2") (pinfunction "2_2") (pintype "passive"))
      (node (ref "R108") (pin "2") (pinfunction "2_2") (pintype "passive"))
      (node (ref "R119") (pin "2") (pinfunction "2_2") (pintype "passive"))
      (node (ref "R121") (pin "2") (pinfunction "2_2") (pintype "passive"))
      (node (ref "R122") (pin "2") (pinfunction "2_2") (pintype "passive"))
      (node (ref "R126") (pin "1") (pinfunction "1_1") (pintype "passive"))
      (node (ref "R128") (pin "2") (pinfunction "2_2") (pintype "passive"))
      (node (ref "R129") (pin "2") (pinfunction "2_2") (pintype "passive"))
      (node (ref "R130") (pin "2") (pinfunction "2_2") (pintype "passive"))
      (node (ref "R131") (pin "2") (pinfunction "2_2") (pintype "passive"))
      (node (ref "R142") (pin "2") (pinfunction "2_2") (pintype "passive"))
      (node (ref "R144") (pin "2") (pinfunction "2_2") (pintype "passive"))
      (node (ref "R145") (pin "2") (pinfunction "2_2") (pintype "passive"))
      (node (ref "R149") (pin "1") (pinfunction "1_1") (pintype "passive"))
      (node (ref "R151") (pin "2") (pinfunction "2_2") (pintype "passive"))
      (node (ref "R152") (pin "2") (pinfunction "2_2") (pintype "passive"))
      (node (ref "R153") (pin "2") (pinfunction "2_2") (pintype "passive"))
      (node (ref "R154") (pin "2") (pinfunction "2_2") (pintype "passive"))
      (node (ref "R165") (pin "2") (pinfunction "2_2") (pintype "passive"))
      (node (ref "R167") (pin "2") (pinfunction "2_2") (pintype "passive"))
      (node (ref "R168") (pin "2") (pinfunction "2_2") (pintype "passive"))
      (node (ref "R172") (pin "1") (pinfunction "1_1") (pintype "passive"))
      (node (ref "R174") (pin "2") (pinfunction "2_2") (pintype "passive"))
      (node (ref "R175") (pin "2") (pinfunction "2_2") (pintype "passive"))
      (node (ref "R176") (pin "2") (pinfunction "2_2") (pintype "passive"))
      (node (ref "R177") (pin "2") (pinfunction "2_2") (pintype "passive"))
      (node (ref "R188") (pin "2") (pinfunction "2_2") (pintype "passive"))
      (node (ref "R190") (pin "2") (pinfunction "2_2") (pintype "passive"))
      (node (ref "R191") (pin "2") (pinfunction "2_2") (pintype "passive"))
      (node (ref "R195") (pin "1") (pinfunction "1_1") (pintype "passive"))
      (node (ref "R197") (pin "2") (pinfunction "2_2") (pintype "passive"))
      (node (ref "R198") (pin "2") (pinfunction "2_2") (pintype "passive"))
      (node (ref "R199") (pin "2") (pinfunction "2_2") (pintype "passive"))
      (node (ref "R2") (pin "1") (pinfunction "1_1") (pintype "passive"))
      (node (ref "R200") (pin "2") (pinfunction "2_2") (pintype "passive"))
      (node (ref "R214") (pin "1") (pinfunction "1_1") (pintype "passive"))
      (node (ref "R224") (pin "2") (pinfunction "2_2") (pintype "passive"))
      (node (ref "R234") (pin "1") (pinfunction "1_1") (pintype "passive"))
      (node (ref "R240") (pin "1") (pinfunction "1_1") (pintype "passive"))
      (node (ref "R242") (pin "2") (pinfunction "2_2") (pintype "passive"))
      (node (ref "R246") (pin "2") (pinfunction "2_2") (pintype "passive"))
      (node (ref "R247") (pin "2") (pinfunction "2_2") (pintype "passive"))
      (node (ref "R249") (pin "2") (pinfunction "2_2") (pintype "passive"))
      (node (ref "R250") (pin "2") (pinfunction "2_2") (pintype "passive"))
      (node (ref "R251") (pin "2") (pinfunction "2_2") (pintype "passive"))
      (node (ref "R255") (pin "2") (pinfunction "2_2") (pintype "passive"))
      (node (ref "R256") (pin "2") (pinfunction "2_2") (pintype "passive"))
      (node (ref "R261") (pin "1") (pinfunction "1_1") (pintype "passive"))
      (node (ref "R264") (pin "2") (pinfunction "2_2") (pintype "passive"))
      (node (ref "R267") (pin "2") (pinfunction "2_2") (pintype "passive"))
      (node (ref "R268") (pin "2") (pinfunction "2_2") (pintype "passive"))
      (node (ref "R269") (pin "2") (pinfunction "2_2") (pintype "passive"))
      (node (ref "R270") (pin "2") (pinfunction "2_2") (pintype "passive"))
      (node (ref "R3") (pin "2") (pinfunction "2_2") (pintype "passive"))
      (node (ref "R49") (pin "2") (pinfunction "2_2") (pintype "passive"))
      (node (ref "R51") (pin "2") (pinfunction "2_2") (pintype "passive"))
      (node (ref "R52") (pin "2") (pinfunction "2_2") (pintype "passive"))
      (node (ref "R56") (pin "1") (pinfunction "1_1") (pintype "passive"))
      (node (ref "R58") (pin "2") (pinfunction "2_2") (pintype "passive"))
      (node (ref "R59") (pin "2") (pinfunction "2_2") (pintype "passive"))
      (node (ref "R6") (pin "2") (pinfunction "2_2") (pintype "passive"))
      (node (ref "R60") (pin "2") (pinfunction "2_2") (pintype "passive"))
      (node (ref "R61") (pin "2") (pinfunction "2_2") (pintype "passive"))
      (node (ref "R72") (pin "2") (pinfunction "2_2") (pintype "passive"))
      (node (ref "R74") (pin "2") (pinfunction "2_2") (pintype "passive"))
      (node (ref "R75") (pin "2") (pinfunction "2_2") (pintype "passive"))
      (node (ref "R79") (pin "1") (pinfunction "1_1") (pintype "passive"))
      (node (ref "R8") (pin "1") (pinfunction "1_1") (pintype "passive"))
      (node (ref "R81") (pin "2") (pinfunction "2_2") (pintype "passive"))
      (node (ref "R82") (pin "2") (pinfunction "2_2") (pintype "passive"))
      (node (ref "R83") (pin "2") (pinfunction "2_2") (pintype "passive"))
      (node (ref "R84") (pin "2") (pinfunction "2_2") (pintype "passive"))
      (node (ref "R85") (pin "2") (pinfunction "2_2") (pintype "passive"))
      (node (ref "R9") (pin "2") (pinfunction "2_2") (pintype "passive"))
      (node (ref "R96") (pin "2") (pinfunction "2_2") (pintype "passive"))
      (node (ref "R98") (pin "2") (pinfunction "2_2") (pintype "passive"))
      (node (ref "R99") (pin "2") (pinfunction "2_2") (pintype "passive"))
      (node (ref "REF1") (pin "2") (pinfunction "A_2") (pintype "passive"))
      (node (ref "REF1") (pin "3") (pinfunction "A_3") (pintype "passive"))
      (node (ref "RESET") (pin "1") (pinfunction "1_1") (pintype "passive"))
      (node (ref "RESET") (pin "3") (pinfunction "3_3") (pintype "passive"))
      (node (ref "RFB12") (pin "2") (pinfunction "2_2") (pintype "passive"))
      (node (ref "RFB4") (pin "2") (pinfunction "2_2") (pintype "passive"))
      (node (ref "RFB8") (pin "2") (pinfunction "2_2") (pintype "passive"))
      (node (ref "T14") (pin "1") (pinfunction "S_1") (pintype "passive"))
      (node (ref "T14") (pin "2") (pinfunction "S_2") (pintype "passive"))
      (node (ref "T14") (pin "3") (pinfunction "S_3") (pintype "passive"))
      (node (ref "T19") (pin "1") (pinfunction "S_1") (pintype "passive"))
      (node (ref "T19") (pin "2") (pinfunction "S_2") (pintype "passive"))
      (node (ref "T19") (pin "3") (pinfunction "S_3") (pintype "passive"))
      (node (ref "T24") (pin "1") (pinfunction "S_1") (pintype "passive"))
      (node (ref "T24") (pin "2") (pinfunction "S_2") (pintype "passive"))
      (node (ref "T24") (pin "3") (pinfunction "S_3") (pintype "passive"))
      (node (ref "T29") (pin "1") (pinfunction "S_1") (pintype "passive"))
      (node (ref "T29") (pin "2") (pinfunction "S_2") (pintype "passive"))
      (node (ref "T29") (pin "3") (pinfunction "S_3") (pintype "passive"))
      (node (ref "T34") (pin "1") (pinfunction "S_1") (pintype "passive"))
      (node (ref "T34") (pin "2") (pinfunction "S_2") (pintype "passive"))
      (node (ref "T34") (pin "3") (pinfunction "S_3") (pintype "passive"))
      (node (ref "T39") (pin "1") (pinfunction "S_1") (pintype "passive"))
      (node (ref "T39") (pin "2") (pinfunction "S_2") (pintype "passive"))
      (node (ref "T39") (pin "3") (pinfunction "S_3") (pintype "passive"))
      (node (ref "T44") (pin "1") (pinfunction "S_1") (pintype "passive"))
      (node (ref "T44") (pin "2") (pinfunction "S_2") (pintype "passive"))
      (node (ref "T44") (pin "3") (pinfunction "S_3") (pintype "passive"))
      (node (ref "T9") (pin "1") (pinfunction "S_1") (pintype "passive"))
      (node (ref "T9") (pin "2") (pinfunction "S_2") (pintype "passive"))
      (node (ref "T9") (pin "3") (pinfunction "S_3") (pintype "passive"))
      (node (ref "USB9") (pin "GND") (pinfunction "GND_GND") (pintype "power_in"))
      (node (ref "USB9") (pin "GND2") (pinfunction "GND_GND2") (pintype "power_in"))
      (node (ref "USBA_1-2") (pin "4") (pinfunction "GND_4") (pintype "passive"))
      (node (ref "USBA_1-2") (pin "8") (pinfunction "GND_8") (pintype "passive"))
      (node (ref "USBA_3-4") (pin "4") (pinfunction "GND_4") (pintype "passive"))
      (node (ref "USBA_3-4") (pin "8") (pinfunction "GND_8") (pintype "passive"))
      (node (ref "X1") (pin "2") (pinfunction "GND_2") (pintype "passive"))
      (node (ref "X1") (pin "4") (pinfunction "GND_4") (pintype "passive"))
      (node (ref "X2") (pin "2") (pinfunction "GND_2") (pintype "passive"))
      (node (ref "X2") (pin "4") (pinfunction "GND_4") (pintype "passive"))
    )
    (net (code "37") (name "I2C0_SCL") (class "Default")
      (node (ref "IC26") (pin "7") (pinfunction "GPIO5_7") (pintype "bidirectional"))
      (node (ref "IC38") (pin "19") (pinfunction "SCL_19") (pintype "bidirectional"))
      (node (ref "R207") (pin "1") (pinfunction "1_1") (pintype "passive"))
    )
    (net (code "38") (name "I2C0_SDA") (class "Default")
      (node (ref "IC26") (pin "6") (pinfunction "GPIO4_6") (pintype "bidirectional"))
      (node (ref "IC38") (pin "20") (pinfunction "SDA_20") (pintype "bidirectional"))
      (node (ref "R207") (pin "2") (pinfunction "2_2") (pintype "passive"))
    )
    (net (code "39") (name "I2C1_SCL") (class "Default")
      (node (ref "DISP") (pin "7") (pinfunction "7_7") (pintype "bidirectional"))
      (node (ref "IC26") (pin "5") (pinfunction "GPIO3_5") (pintype "bidirectional"))
      (node (ref "IC29") (pin "6") (pinfunction "SCL_6") (pintype "bidirectional"))
      (node (ref "IC42") (pin "8") (pinfunction "SCL_8") (pintype "bidirectional"))
      (node (ref "R207") (pin "3") (pinfunction "3_3") (pintype "passive"))
    )
    (net (code "40") (name "I2C1_SDA") (class "Default")
      (node (ref "DISP") (pin "6") (pinfunction "6_6") (pintype "bidirectional"))
      (node (ref "IC26") (pin "4") (pinfunction "GPIO2_4") (pintype "bidirectional"))
      (node (ref "IC29") (pin "5") (pinfunction "SDA_5") (pintype "bidirectional"))
      (node (ref "IC42") (pin "9") (pinfunction "SDA_9") (pintype "bidirectional"))
      (node (ref "R207") (pin "4") (pinfunction "4_4") (pintype "passive"))
    )
    (net (code "41") (name "IN1_PORT1") (class "Default")
      (node (ref "IC13") (pin "1") (pinfunction "IN+_1") (pintype "bidirectional"))
      (node (ref "IC9") (pin "12") (pinfunction "VBUS_SENSE_12") (pintype "input"))
      (node (ref "R57") (pin "1") (pinfunction "1_1") (pintype "passive"))
      (node (ref "T8") (pin "5") (pinfunction "D_5") (pintype "passive"))
      (node (ref "T8") (pin "6") (pinfunction "D_6") (pintype "passive"))
      (node (ref "T8") (pin "7") (pinfunction "D_7") (pintype "passive"))
      (node (ref "T8") (pin "8") (pinfunction "D_8") (pintype "passive"))
      (node (ref "T8") (pin "9") (pinfunction "D_9") (pintype "passive"))
    )
    (net (code "42") (name "IN1_PORT2") (class "Default")
      (node (ref "IC10") (pin "12") (pinfunction "VBUS_SENSE_12") (pintype "input"))
      (node (ref "IC16") (pin "1") (pinfunction "IN+_1") (pintype "bidirectional"))
      (node (ref "R80") (pin "1") (pinfunction "1_1") (pintype "passive"))
      (node (ref "T13") (pin "5") (pinfunction "D_5") (pintype "passive"))
      (node (ref "T13") (pin "6") (pinfunction "D_6") (pintype "passive"))
      (node (ref "T13") (pin "7") (pinfunction "D_7") (pintype "passive"))
      (node (ref "T13") (pin "8") (pinfunction "D_8") (pintype "passive"))
      (node (ref "T13") (pin "9") (pinfunction "D_9") (pintype "passive"))
    )
    (net (code "43") (name "IN1_PORT3") (class "Default")
      (node (ref "IC11") (pin "12") (pinfunction "VBUS_SENSE_12") (pintype "input"))
      (node (ref "IC25") (pin "1") (pinfunction "IN+_1") (pintype "bidirectional"))
      (node (ref "R150") (pin "1") (pinfunction "1_1") (pintype "passive"))
      (node (ref "T28") (pin "5") (pinfunction "D_5") (pintype "passive"))
      (node (ref "T28") (pin "6") (pinfunction "D_6") (pintype "passive"))
      (node (ref "T28") (pin "7") (pinfunction "D_7") (pintype "passive"))
      (node (ref "T28") (pin "8") (pinfunction "D_8") (pintype "passive"))
      (node (ref "T28") (pin "9") (pinfunction "D_9") (pintype "passive"))
    )
    (net (code "44") (name "IN1_PORT4") (class "Default")
      (node (ref "IC14") (pin "12") (pinfunction "VBUS_SENSE_12") (pintype "input"))
      (node (ref "IC22") (pin "1") (pinfunction "IN+_1") (pintype "bidirectional"))
      (node (ref "R127") (pin "1") (pinfunction "1_1") (pintype "passive"))
      (node (ref "T23") (pin "5") (pinfunction "D_5") (pintype "passive"))
      (node (ref "T23") (pin "6") (pinfunction "D_6") (pintype "passive"))
      (node (ref "T23") (pin "7") (pinfunction "D_7") (pintype "passive"))
      (node (ref "T23") (pin "8") (pinfunction "D_8") (pintype "passive"))
      (node (ref "T23") (pin "9") (pinfunction "D_9") (pintype "passive"))
    )
    (net (code "45") (name "IN1_PORT5") (class "Default")
      (node (ref "IC17") (pin "12") (pinfunction "VBUS_SENSE_12") (pintype "input"))
      (node (ref "IC19") (pin "1") (pinfunction "IN+_1") (pintype "bidirectional"))
      (node (ref "R104") (pin "1") (pinfunction "1_1") (pintype "passive"))
      (node (ref "T18") (pin "5") (pinfunction "D_5") (pintype "passive"))
      (node (ref "T18") (pin "6") (pinfunction "D_6") (pintype "passive"))
      (node (ref "T18") (pin "7") (pinfunction "D_7") (pintype "passive"))
      (node (ref "T18") (pin "8") (pinfunction "D_8") (pintype "passive"))
      (node (ref "T18") (pin "9") (pinfunction "D_9") (pintype "passive"))
    )
    (net (code "46") (name "IN1_PORT6") (class "Default")
      (node (ref "IC20") (pin "12") (pinfunction "VBUS_SENSE_12") (pintype "input"))
      (node (ref "IC33") (pin "1") (pinfunction "IN+_1") (pintype "bidirectional"))
      (node (ref "R173") (pin "1") (pinfunction "1_1") (pintype "passive"))
      (node (ref "T33") (pin "5") (pinfunction "D_5") (pintype "passive"))
      (node (ref "T33") (pin "6") (pinfunction "D_6") (pintype "passive"))
      (node (ref "T33") (pin "7") (pinfunction "D_7") (pintype "passive"))
      (node (ref "T33") (pin "8") (pinfunction "D_8") (pintype "passive"))
      (node (ref "T33") (pin "9") (pinfunction "D_9") (pintype "passive"))
    )
    (net (code "47") (name "IN1_PORT7") (class "Default")
      (node (ref "IC23") (pin "12") (pinfunction "VBUS_SENSE_12") (pintype "input"))
      (node (ref "IC36") (pin "1") (pinfunction "IN+_1") (pintype "bidirectional"))
      (node (ref "R196") (pin "1") (pinfunction "1_1") (pintype "passive"))
      (node (ref "T38") (pin "5") (pinfunction "D_5") (pintype "passive"))
      (node (ref "T38") (pin "6") (pinfunction "D_6") (pintype "passive"))
      (node (ref "T38") (pin "7") (pinfunction "D_7") (pintype "passive"))
      (node (ref "T38") (pin "8") (pinfunction "D_8") (pintype "passive"))
      (node (ref "T38") (pin "9") (pinfunction "D_9") (pintype "passive"))
    )
    (net (code "48") (name "IN1_PORT8") (class "Default")
      (node (ref "IC30") (pin "12") (pinfunction "VBUS_SENSE_12") (pintype "input"))
      (node (ref "IC44") (pin "1") (pinfunction "IN+_1") (pintype "bidirectional"))
      (node (ref "R262") (pin "1") (pinfunction "1_1") (pintype "passive"))
      (node (ref "T43") (pin "5") (pinfunction "D_5") (pintype "passive"))
      (node (ref "T43") (pin "6") (pinfunction "D_6") (pintype "passive"))
      (node (ref "T43") (pin "7") (pinfunction "D_7") (pintype "passive"))
      (node (ref "T43") (pin "8") (pinfunction "D_8") (pintype "passive"))
      (node (ref "T43") (pin "9") (pinfunction "D_9") (pintype "passive"))
    )
    (net (code "49") (name "IN2_PORT1") (class "Default")
      (node (ref "IC13") (pin "2") (pinfunction "IN-_2") (pintype "bidirectional"))
      (node (ref "PORT1") (pin "A9") (pinfunction "VBUS1_A9") (pintype "passive"))
      (node (ref "PORT1") (pin "B9") (pinfunction "VBUS2_B9") (pintype "passive"))
      (node (ref "R57") (pin "2") (pinfunction "2_2") (pintype "passive"))
    )
    (net (code "50") (name "IN2_PORT2") (class "Default")
      (node (ref "IC16") (pin "2") (pinfunction "IN-_2") (pintype "bidirectional"))
      (node (ref "PORT2") (pin "A9") (pinfunction "VBUS1_A9") (pintype "passive"))
      (node (ref "PORT2") (pin "B9") (pinfunction "VBUS2_B9") (pintype "passive"))
      (node (ref "R80") (pin "2") (pinfunction "2_2") (pintype "passive"))
    )
    (net (code "51") (name "IN2_PORT3") (class "Default")
      (node (ref "IC25") (pin "2") (pinfunction "IN-_2") (pintype "bidirectional"))
      (node (ref "PORT3") (pin "A9") (pinfunction "VBUS1_A9") (pintype "passive"))
      (node (ref "PORT3") (pin "B9") (pinfunction "VBUS2_B9") (pintype "passive"))
      (node (ref "R150") (pin "2") (pinfunction "2_2") (pintype "passive"))
    )
    (net (code "52") (name "IN2_PORT4") (class "Default")
      (node (ref "IC22") (pin "2") (pinfunction "IN-_2") (pintype "bidirectional"))
      (node (ref "PORT4") (pin "A9") (pinfunction "VBUS1_A9") (pintype "passive"))
      (node (ref "PORT4") (pin "B9") (pinfunction "VBUS2_B9") (pintype "passive"))
      (node (ref "R127") (pin "2") (pinfunction "2_2") (pintype "passive"))
    )
    (net (code "53") (name "IN2_PORT5") (class "Default")
      (node (ref "IC19") (pin "2") (pinfunction "IN-_2") (pintype "bidirectional"))
      (node (ref "PORT5") (pin "A9") (pinfunction "VBUS1_A9") (pintype "passive"))
      (node (ref "PORT5") (pin "B9") (pinfunction "VBUS2_B9") (pintype "passive"))
      (node (ref "R104") (pin "2") (pinfunction "2_2") (pintype "passive"))
    )
    (net (code "54") (name "IN2_PORT6") (class "Default")
      (node (ref "IC33") (pin "2") (pinfunction "IN-_2") (pintype "bidirectional"))
      (node (ref "PORT6") (pin "A9") (pinfunction "VBUS1_A9") (pintype "passive"))
      (node (ref "PORT6") (pin "B9") (pinfunction "VBUS2_B9") (pintype "passive"))
      (node (ref "R173") (pin "2") (pinfunction "2_2") (pintype "passive"))
    )
    (net (code "55") (name "IN2_PORT7") (class "Default")
      (node (ref "IC36") (pin "2") (pinfunction "IN-_2") (pintype "bidirectional"))
      (node (ref "PORT7") (pin "A9") (pinfunction "VBUS1_A9") (pintype "passive"))
      (node (ref "PORT7") (pin "B9") (pinfunction "VBUS2_B9") (pintype "passive"))
      (node (ref "R196") (pin "2") (pinfunction "2_2") (pintype "passive"))
    )
    (net (code "56") (name "IN2_PORT8") (class "Default")
      (node (ref "IC44") (pin "2") (pinfunction "IN-_2") (pintype "bidirectional"))
      (node (ref "PORT8") (pin "A9") (pinfunction "VBUS1_A9") (pintype "passive"))
      (node (ref "PORT8") (pin "B9") (pinfunction "VBUS2_B9") (pintype "passive"))
      (node (ref "R262") (pin "2") (pinfunction "2_2") (pintype "passive"))
    )
    (net (code "57") (name "KEY_0") (class "Default")
      (node (ref "DISP") (pin "12") (pinfunction "12_12") (pintype "bidirectional"))
      (node (ref "IC26") (pin "15") (pinfunction "GPIO12_15") (pintype "bidirectional"))
    )
    (net (code "58") (name "KEY_1") (class "Default")
      (node (ref "DISP") (pin "11") (pinfunction "11_11") (pintype "bidirectional"))
      (node (ref "IC26") (pin "16") (pinfunction "GPIO13_16") (pintype "bidirectional"))
    )
    (net (code "59") (name "KEY_2") (class "Default")
      (node (ref "DISP") (pin "10") (pinfunction "10_10") (pintype "bidirectional"))
      (node (ref "IC26") (pin "17") (pinfunction "GPIO14_17") (pintype "bidirectional"))
    )
    (net (code "60") (name "KEY_3") (class "Default")
      (node (ref "DISP") (pin "9") (pinfunction "9_9") (pintype "bidirectional"))
      (node (ref "IC26") (pin "18") (pinfunction "GPIO15_18") (pintype "bidirectional"))
    )
    (net (code "61") (name "LCD_BL") (class "Default")
      (node (ref "DISP") (pin "13") (pinfunction "13_13") (pintype "bidirectional"))
      (node (ref "IC26") (pin "9") (pinfunction "GPIO7_9") (pintype "bidirectional"))
    )
    (net (code "62") (name "LCD_CS") (class "Default")
      (node (ref "DISP") (pin "19") (pinfunction "19_19") (pintype "bidirectional"))
      (node (ref "IC26") (pin "12") (pinfunction "GPIO9_12") (pintype "bidirectional"))
      (node (ref "R253") (pin "6") (pinfunction "6_6") (pintype "passive"))
    )
    (net (code "63") (name "LCD_DC") (class "Default")
      (node (ref "DISP") (pin "18") (pinfunction "18_18") (pintype "bidirectional"))
      (node (ref "IC26") (pin "8") (pinfunction "GPIO6_8") (pintype "bidirectional"))
    )
    (net (code "64") (name "LCD_MISO") (class "Default")
      (node (ref "DISP") (pin "15") (pinfunction "15_15") (pintype "bidirectional"))
      (node (ref "IC26") (pin "11") (pinfunction "GPIO8_11") (pintype "bidirectional"))
      (node (ref "R253") (pin "7") (pinfunction "7_7") (pintype "passive"))
    )
    (net (code "65") (name "LCD_MOSI") (class "Default")
      (node (ref "DISP") (pin "16") (pinfunction "16_16") (pintype "bidirectional"))
      (node (ref "IC26") (pin "14") (pinfunction "GPIO11_14") (pintype "bidirectional"))
    )
    (net (code "66") (name "LCD_RES") (class "Default")
      (node (ref "DISP") (pin "14") (pinfunction "14_14") (pintype "bidirectional"))
      (node (ref "IC26") (pin "34") (pinfunction "GPIO22_34") (pintype "bidirectional"))
      (node (ref "R253") (pin "8") (pinfunction "8_8") (pintype "passive"))
    )
    (net (code "67") (name "LCD_SCLK") (class "Default")
      (node (ref "DISP") (pin "17") (pinfunction "17_17") (pintype "bidirectional"))
      (node (ref "IC26") (pin "13") (pinfunction "GPIO10_13") (pintype "bidirectional"))
    )
    (net (code "68") (name "MCP_DSP_RST") (class "Default")
      (node (ref "DISP") (pin "20") (pinfunction "20_20") (pintype "bidirectional"))
      (node (ref "R252") (pin "1") (pinfunction "1_1") (pintype "passive"))
    )
    (net (code "69") (name "MCP_REL_RST") (class "Default")
      (node (ref "IC26") (pin "35") (pinfunction "GPIO23_35") (pintype "bidirectional"))
      (node (ref "IC42") (pin "14") (pinfunction "~{RESET}_14") (pintype "bidirectional"))
    )
    (net (code "70") (name "Net-(C44-Pad1)") (class "Default")
      (node (ref "C44") (pin "1") (pinfunction "1_1") (pintype "passive"))
      (node (ref "R62") (pin "2") (pinfunction "2_2") (pintype "passive"))
    )
    (net (code "71") (name "Net-(C46-Pad1)") (class "Default")
      (node (ref "C46") (pin "1") (pinfunction "1_1") (pintype "passive"))
      (node (ref "IC12") (pin "21") (pinfunction "SW2_21") (pintype "power_in"))
      (node (ref "IC12") (pin "25") (pinfunction "SW2_25") (pintype "power_in"))
      (node (ref "L2") (pin "2") (pinfunction "2_2") (pintype "passive"))
    )
    (net (code "72") (name "Net-(C63-Pad1)") (class "Default")
      (node (ref "C63") (pin "1") (pinfunction "1_1") (pintype "passive"))
      (node (ref "R86") (pin "2") (pinfunction "2_2") (pintype "passive"))
    )
    (net (code "73") (name "Net-(C65-Pad1)") (class "Default")
      (node (ref "C65") (pin "1") (pinfunction "1_1") (pintype "passive"))
      (node (ref "IC15") (pin "21") (pinfunction "SW2_21") (pintype "power_in"))
      (node (ref "IC15") (pin "25") (pinfunction "SW2_25") (pintype "power_in"))
      (node (ref "L3") (pin "2") (pinfunction "2_2") (pintype "passive"))
    )
    (net (code "74") (name "Net-(C86-Pad1)") (class "Default")
      (node (ref "C86") (pin "1") (pinfunction "1_1") (pintype "passive"))
      (node (ref "R109") (pin "2") (pinfunction "2_2") (pintype "passive"))
    )
    (net (code "75") (name "Net-(C88-Pad1)") (class "Default")
      (node (ref "C88") (pin "1") (pinfunction "1_1") (pintype "passive"))
      (node (ref "IC18") (pin "21") (pinfunction "SW2_21") (pintype "power_in"))
      (node (ref "IC18") (pin "25") (pinfunction "SW2_25") (pintype "power_in"))
      (node (ref "L4") (pin "2") (pinfunction "2_2") (pintype "passive"))
    )
    (net (code "76") (name "Net-(C105-Pad1)") (class "Default")
      (node (ref "C105") (pin "1") (pinfunction "1_1") (pintype "passive"))
      (node (ref "R132") (pin "2") (pinfunction "2_2") (pintype "passive"))
    )
    (net (code "77") (name "Net-(C107-Pad1)") (class "Default")
      (node (ref "C107") (pin "1") (pinfunction "1_1") (pintype "passive"))
      (node (ref "IC21") (pin "21") (pinfunction "SW2_21") (pintype "power_in"))
      (node (ref "IC21") (pin "25") (pinfunction "SW2_25") (pintype "power_in"))
      (node (ref "L5") (pin "2") (pinfunction "2_2") (pintype "passive"))
    )
    (net (code "78") (name "Net-(C124-Pad1)") (class "Default")
      (node (ref "C124") (pin "1") (pinfunction "1_1") (pintype "passive"))
      (node (ref "R155") (pin "2") (pinfunction "2_2") (pintype "passive"))
    )
    (net (code "79") (name "Net-(C126-Pad1)") (class "Default")
      (node (ref "C126") (pin "1") (pinfunction "1_1") (pintype "passive"))
      (node (ref "IC24") (pin "21") (pinfunction "SW2_21") (pintype "power_in"))
      (node (ref "IC24") (pin "25") (pinfunction "SW2_25") (pintype "power_in"))
      (node (ref "L6") (pin "2") (pinfunction "2_2") (pintype "passive"))
    )
    (net (code "80") (name "Net-(C143-Pad1)") (class "Default")
      (node (ref "C143") (pin "1") (pinfunction "1_1") (pintype "passive"))
      (node (ref "R178") (pin "2") (pinfunction "2_2") (pintype "passive"))
    )
    (net (code "81") (name "Net-(C145-Pad1)") (class "Default")
      (node (ref "C145") (pin "1") (pinfunction "1_1") (pintype "passive"))
      (node (ref "IC32") (pin "21") (pinfunction "SW2_21") (pintype "power_in"))
      (node (ref "IC32") (pin "25") (pinfunction "SW2_25") (pintype "power_in"))
      (node (ref "L7") (pin "2") (pinfunction "2_2") (pintype "passive"))
    )
    (net (code "82") (name "Net-(C162-Pad1)") (class "Default")
      (node (ref "C162") (pin "1") (pinfunction "1_1") (pintype "passive"))
      (node (ref "R201") (pin "2") (pinfunction "2_2") (pintype "passive"))
    )
    (net (code "83") (name "Net-(C164-Pad1)") (class "Default")
      (node (ref "C164") (pin "1") (pinfunction "1_1") (pintype "passive"))
      (node (ref "IC35") (pin "21") (pinfunction "SW2_21") (pintype "power_in"))
      (node (ref "IC35") (pin "25") (pinfunction "SW2_25") (pintype "power_in"))
      (node (ref "L8") (pin "2") (pinfunction "2_2") (pintype "passive"))
    )
    (net (code "84") (name "Net-(C202-Pad1)") (class "Default")
      (node (ref "C202") (pin "1") (pinfunction "1_1") (pintype "passive"))
      (node (ref "R271") (pin "2") (pinfunction "2_2") (pintype "passive"))
    )
    (net (code "85") (name "Net-(C204-Pad1)") (class "Default")
      (node (ref "C204") (pin "1") (pinfunction "1_1") (pintype "passive"))
      (node (ref "IC41") (pin "21") (pinfunction "SW2_21") (pintype "power_in"))
      (node (ref "IC41") (pin "25") (pinfunction "SW2_25") (pintype "power_in"))
      (node (ref "L9") (pin "2") (pinfunction "2_2") (pintype "passive"))
    )
    (net (code "86") (name "Net-(C235-Pad1)") (class "Default")
      (node (ref "C235") (pin "1") (pinfunction "1_1") (pintype "passive"))
      (node (ref "R243") (pin "1") (pinfunction "1_1") (pintype "passive"))
    )
    (net (code "87") (name "Net-(C236-Pad2)") (class "Default")
      (node (ref "C236") (pin "2") (pinfunction "2_2") (pintype "passive"))
      (node (ref "RFB3") (pin "2") (pinfunction "2_2") (pintype "passive"))
      (node (ref "RFB4") (pin "1") (pinfunction "1_1") (pintype "passive"))
      (node (ref "RT1") (pin "2") (pinfunction "2_2") (pintype "passive"))
    )
    (net (code "88") (name "Net-(C260-Pad1)") (class "Default")
      (node (ref "C260") (pin "1") (pinfunction "1_1") (pintype "passive"))
      (node (ref "R257") (pin "1") (pinfunction "1_1") (pintype "passive"))
    )
    (net (code "89") (name "Net-(C261-Pad2)") (class "Default")
      (node (ref "C261") (pin "2") (pinfunction "2_2") (pintype "passive"))
      (node (ref "RFB7") (pin "2") (pinfunction "2_2") (pintype "passive"))
      (node (ref "RFB8") (pin "1") (pinfunction "1_1") (pintype "passive"))
      (node (ref "RT3") (pin "2") (pinfunction "2_2") (pintype "passive"))
    )
    (net (code "90") (name "Net-(C274-Pad1)") (class "Default")
      (node (ref "C274") (pin "1") (pinfunction "1_1") (pintype "passive"))
      (node (ref "R265") (pin "1") (pinfunction "1_1") (pintype "passive"))
    )
    (net (code "91") (name "Net-(C275-Pad2)") (class "Default")
      (node (ref "C275") (pin "2") (pinfunction "2_2") (pintype "passive"))
      (node (ref "RFB11") (pin "2") (pinfunction "2_2") (pintype "passive"))
      (node (ref "RFB12") (pin "1") (pinfunction "1_1") (pintype "passive"))
      (node (ref "RT5") (pin "2") (pinfunction "2_2") (pintype "passive"))
    )
    (net (code "92") (name "Net-(D1-PadA)") (class "Default")
      (node (ref "D1") (pin "A") (pinfunction "A_A") (pintype "passive"))
      (node (ref "R14") (pin "2") (pinfunction "2_2") (pintype "passive"))
    )
    (net (code "93") (name "Net-(D2-PadA)") (class "Default")
      (node (ref "D2") (pin "A") (pinfunction "A_A") (pintype "passive"))
      (node (ref "R12") (pin "1") (pinfunction "1_1") (pintype "passive"))
    )
    (net (code "94") (name "Net-(D3-PadA)") (class "Default")
      (node (ref "D3") (pin "A") (pinfunction "A_A") (pintype "passive"))
      (node (ref "R17") (pin "2") (pinfunction "2_2") (pintype "passive"))
    )
    (net (code "95") (name "Net-(D4-PadA)") (class "Default")
      (node (ref "D4") (pin "A") (pinfunction "A_A") (pintype "passive"))
      (node (ref "R15") (pin "1") (pinfunction "1_1") (pintype "passive"))
    )
    (net (code "96") (name "Net-(D5-PadA)") (class "Default")
      (node (ref "D5") (pin "A") (pinfunction "A_A") (pintype "passive"))
      (node (ref "R20") (pin "2") (pinfunction "2_2") (pintype "passive"))
    )
    (net (code "97") (name "Net-(D6-PadA)") (class "Default")
      (node (ref "D6") (pin "A") (pinfunction "A_A") (pintype "passive"))
      (node (ref "R18") (pin "1") (pinfunction "1_1") (pintype "passive"))
    )
    (net (code "98") (name "Net-(D7-PadA)") (class "Default")
      (node (ref "D7") (pin "A") (pinfunction "A_A") (pintype "passive"))
      (node (ref "R23") (pin "2") (pinfunction "2_2") (pintype "passive"))
    )
    (net (code "99") (name "Net-(D8-PadA)") (class "Default")
      (node (ref "D8") (pin "A") (pinfunction "A_A") (pintype "passive"))
      (node (ref "R21") (pin "1") (pinfunction "1_1") (pintype "passive"))
    )
    (net (code "100") (name "Net-(ETH1-GK1)") (class "Default")
      (node (ref "ETH1") (pin "10") (pinfunction "GK1_10") (pintype "passive"))
      (node (ref "R237") (pin "2") (pinfunction "2_2") (pintype "passive"))
    )
    (net (code "101") (name "Net-(ETH1-GK2)") (class "Default")
      (node (ref "ETH1") (pin "12") (pinfunction "GK2_12") (pintype "passive"))
      (node (ref "R238") (pin "2") (pinfunction "2_2") (pintype "passive"))
    )
    (net (code "102") (name "Net-(F1-1-Pad1_1)") (class "Default")
      (node (ref "F1") (pin "1_1") (pinfunction "1_1_1") (pintype "passive"))
      (node (ref "F1") (pin "1_2") (pinfunction "1_1_2") (pintype "passive"))
      (node (ref "J8") (pin "1") (pinfunction "1_1") (pintype "passive"))
    )
    (net (code "103") (name "Net-(F2-1-Pad1_1)") (class "Default")
      (node (ref "F2") (pin "1_1") (pinfunction "1_1_1") (pintype "passive"))
      (node (ref "F2") (pin "1_2") (pinfunction "1_1_2") (pintype "passive"))
      (node (ref "J8") (pin "2") (pinfunction "2_2") (pintype "passive"))
    )
    (net (code "104") (name "Net-(F3-1-Pad1_1)") (class "Default")
      (node (ref "F3") (pin "1_1") (pinfunction "1_1_1") (pintype "passive"))
      (node (ref "F3") (pin "1_2") (pinfunction "1_1_2") (pintype "passive"))
      (node (ref "J8") (pin "3") (pinfunction "3_3") (pintype "passive"))
    )
    (net (code "105") (name "Net-(IC1-ILIM)") (class "Default")
      (node (ref "IC1") (pin "5") (pinfunction "ILIM_5") (pintype "bidirectional"))
      (node (ref "R3") (pin "1") (pinfunction "1_1") (pintype "passive"))
    )
    (net (code "106") (name "Net-(IC2-ILIM)") (class "Default")
      (node (ref "IC2") (pin "5") (pinfunction "ILIM_5") (pintype "bidirectional"))
      (node (ref "R6") (pin "1") (pinfunction "1_1") (pintype "passive"))
    )
    (net (code "107") (name "Net-(IC3-ILIM)") (class "Default")
      (node (ref "IC3") (pin "5") (pinfunction "ILIM_5") (pintype "bidirectional"))
      (node (ref "R9") (pin "1") (pinfunction "1_1") (pintype "passive"))
    )
    (net (code "108") (name "Net-(IC4-OUT)") (class "Default")
      (node (ref "IC4") (pin "4") (pinfunction "OUT_4") (pintype "bidirectional"))
      (node (ref "R14") (pin "1") (pinfunction "1_1") (pintype "passive"))
    )
    (net (code "109") (name "Net-(IC5-OUT)") (class "Default")
      (node (ref "IC5") (pin "4") (pinfunction "OUT_4") (pintype "bidirectional"))
      (node (ref "R17") (pin "1") (pinfunction "1_1") (pintype "passive"))
    )
    (net (code "110") (name "Net-(IC6-OUT)") (class "Default")
      (node (ref "IC6") (pin "4") (pinfunction "OUT_4") (pintype "bidirectional"))
      (node (ref "R20") (pin "1") (pinfunction "1_1") (pintype "passive"))
    )
    (net (code "111") (name "Net-(IC7-OUT)") (class "Default")
      (node (ref "IC7") (pin "4") (pinfunction "OUT_4") (pintype "bidirectional"))
      (node (ref "R23") (pin "1") (pinfunction "1_1") (pintype "passive"))
    )
    (net (code "112") (name "Net-(IC8-ILIM)") (class "Default")
      (node (ref "IC8") (pin "5") (pinfunction "ILIM_5") (pintype "bidirectional"))
      (node (ref "R84") (pin "1") (pinfunction "1_1") (pintype "passive"))
    )
    (net (code "113") (name "Net-(IC9-ADDR0)") (class "Default")
      (node (ref "IC9") (pin "9") (pinfunction "ADDR0_9") (pintype "input"))
      (node (ref "R50") (pin "2") (pinfunction "2_2") (pintype "passive"))
      (node (ref "R51") (pin "1") (pinfunction "1_1") (pintype "passive"))
    )
    (net (code "114") (name "Net-(IC9-SEL_PDO2)") (class "Default")
      (node (ref "IC9") (pin "8") (pinfunction "SEL_PDO2_8") (pintype "open_collector"))
      (node (ref "R48") (pin "2") (pinfunction "2_2") (pintype "passive"))
      (node (ref "R49") (pin "1") (pinfunction "1_1") (pintype "passive"))
    )
    (net (code "115") (name "Net-(IC9-SEL_PDO3)") (class "Default")
      (node (ref "IC9") (pin "7") (pinfunction "SEL_PDO3_7") (pintype "open_collector"))
      (node (ref "R47") (pin "2") (pinfunction "2_2") (pintype "passive"))
      (node (ref "R48") (pin "1") (pinfunction "1_1") (pintype "passive"))
    )
    (net (code "116") (name "Net-(IC9-SEL_PDO4)") (class "Default")
      (node (ref "IC9") (pin "10") (pinfunction "SEL_PDO4_10") (pintype "open_collector"))
      (node (ref "R46") (pin "2") (pinfunction "2_2") (pintype "passive"))
      (node (ref "R47") (pin "1") (pinfunction "1_1") (pintype "passive"))
    )
    (net (code "117") (name "Net-(IC9-SEL_PDO5)") (class "Default")
      (node (ref "IC9") (pin "11") (pinfunction "SEL_PDO5_11") (pintype "open_collector"))
      (node (ref "R11") (pin "2") (pinfunction "2_2") (pintype "passive"))
      (node (ref "R46") (pin "1") (pinfunction "1_1") (pintype "passive"))
    )
    (net (code "118") (name "Net-(IC9-VBUS_DISCH)") (class "Default")
      (node (ref "IC9") (pin "13") (pinfunction "VBUS_DISCH_13") (pintype "output"))
      (node (ref "R53") (pin "2") (pinfunction "2_2") (pintype "passive"))
      (node (ref "T6") (pin "4") (pinfunction "G_4") (pintype "passive"))
    )
    (net (code "119") (name "Net-(IC9-VBUS_EN_SRC)") (class "Default")
      (node (ref "IC9") (pin "14") (pinfunction "VBUS_EN_SRC_14") (pintype "open_collector"))
      (node (ref "R55") (pin "2") (pinfunction "2_2") (pintype "passive"))
    )
    (net (code "120") (name "Net-(IC9-VREG1V2)") (class "Default")
      (node (ref "C6") (pin "1") (pinfunction "1_1") (pintype "passive"))
      (node (ref "IC9") (pin "15") (pinfunction "VREG1V2_15") (pintype "input"))
    )
    (net (code "121") (name "Net-(IC9-VREG2V7)") (class "Default")
      (node (ref "C16") (pin "1") (pinfunction "1_1") (pintype "passive"))
      (node (ref "IC9") (pin "16") (pinfunction "VREG2V7_16") (pintype "input"))
    )
    (net (code "122") (name "Net-(IC10-ADDR0)") (class "Default")
      (node (ref "IC10") (pin "9") (pinfunction "ADDR0_9") (pintype "input"))
      (node (ref "R73") (pin "2") (pinfunction "2_2") (pintype "passive"))
      (node (ref "R74") (pin "1") (pinfunction "1_1") (pintype "passive"))
    )
    (net (code "123") (name "Net-(IC10-SEL_PDO2)") (class "Default")
      (node (ref "IC10") (pin "8") (pinfunction "SEL_PDO2_8") (pintype "open_collector"))
      (node (ref "R71") (pin "2") (pinfunction "2_2") (pintype "passive"))
      (node (ref "R72") (pin "1") (pinfunction "1_1") (pintype "passive"))
    )
    (net (code "124") (name "Net-(IC10-SEL_PDO3)") (class "Default")
      (node (ref "IC10") (pin "7") (pinfunction "SEL_PDO3_7") (pintype "open_collector"))
      (node (ref "R70") (pin "2") (pinfunction "2_2") (pintype "passive"))
      (node (ref "R71") (pin "1") (pinfunction "1_1") (pintype "passive"))
    )
    (net (code "125") (name "Net-(IC10-SEL_PDO4)") (class "Default")
      (node (ref "IC10") (pin "10") (pinfunction "SEL_PDO4_10") (pintype "open_collector"))
      (node (ref "R69") (pin "2") (pinfunction "2_2") (pintype "passive"))
      (node (ref "R70") (pin "1") (pinfunction "1_1") (pintype "passive"))
    )
    (net (code "126") (name "Net-(IC10-SEL_PDO5)") (class "Default")
      (node (ref "IC10") (pin "11") (pinfunction "SEL_PDO5_11") (pintype "open_collector"))
      (node (ref "R68") (pin "2") (pinfunction "2_2") (pintype "passive"))
      (node (ref "R69") (pin "1") (pinfunction "1_1") (pintype "passive"))
    )
    (net (code "127") (name "Net-(IC10-VBUS_DISCH)") (class "Default")
      (node (ref "IC10") (pin "13") (pinfunction "VBUS_DISCH_13") (pintype "output"))
      (node (ref "R76") (pin "2") (pinfunction "2_2") (pintype "passive"))
      (node (ref "T11") (pin "4") (pinfunction "G_4") (pintype "passive"))
    )
    (net (code "128") (name "Net-(IC10-VBUS_EN_SRC)") (class "Default")
      (node (ref "IC10") (pin "14") (pinfunction "VBUS_EN_SRC_14") (pintype "open_collector"))
      (node (ref "R78") (pin "2") (pinfunction "2_2") (pintype "passive"))
    )
    (net (code "129") (name "Net-(IC10-VREG1V2)") (class "Default")
      (node (ref "C56") (pin "1") (pinfunction "1_1") (pintype "passive"))
      (node (ref "IC10") (pin "15") (pinfunction "VREG1V2_15") (pintype "input"))
    )
    (net (code "130") (name "Net-(IC10-VREG2V7)") (class "Default")
      (node (ref "C57") (pin "1") (pinfunction "1_1") (pintype "passive"))
      (node (ref "IC10") (pin "16") (pinfunction "VREG2V7_16") (pintype "input"))
    )
    (net (code "131") (name "Net-(IC11-ADDR0)") (class "Default")
      (node (ref "IC11") (pin "9") (pinfunction "ADDR0_9") (pintype "input"))
      (node (ref "R143") (pin "2") (pinfunction "2_2") (pintype "passive"))
      (node (ref "R144") (pin "1") (pinfunction "1_1") (pintype "passive"))
    )
    (net (code "132") (name "Net-(IC11-SEL_PDO2)") (class "Default")
      (node (ref "IC11") (pin "8") (pinfunction "SEL_PDO2_8") (pintype "open_collector"))
      (node (ref "R141") (pin "2") (pinfunction "2_2") (pintype "passive"))
      (node (ref "R142") (pin "1") (pinfunction "1_1") (pintype "passive"))
    )
    (net (code "133") (name "Net-(IC11-SEL_PDO3)") (class "Default")
      (node (ref "IC11") (pin "7") (pinfunction "SEL_PDO3_7") (pintype "open_collector"))
      (node (ref "R140") (pin "2") (pinfunction "2_2") (pintype "passive"))
      (node (ref "R141") (pin "1") (pinfunction "1_1") (pintype "passive"))
    )
    (net (code "134") (name "Net-(IC11-SEL_PDO4)") (class "Default")
      (node (ref "IC11") (pin "10") (pinfunction "SEL_PDO4_10") (pintype "open_collector"))
      (node (ref "R139") (pin "2") (pinfunction "2_2") (pintype "passive"))
      (node (ref "R140") (pin "1") (pinfunction "1_1") (pintype "passive"))
    )
    (net (code "135") (name "Net-(IC11-SEL_PDO5)") (class "Default")
      (node (ref "IC11") (pin "11") (pinfunction "SEL_PDO5_11") (pintype "open_collector"))
      (node (ref "R138") (pin "2") (pinfunction "2_2") (pintype "passive"))
      (node (ref "R139") (pin "1") (pinfunction "1_1") (pintype "passive"))
    )
    (net (code "136") (name "Net-(IC11-VBUS_DISCH)") (class "Default")
      (node (ref "IC11") (pin "13") (pinfunction "VBUS_DISCH_13") (pintype "output"))
      (node (ref "R146") (pin "2") (pinfunction "2_2") (pintype "passive"))
      (node (ref "T26") (pin "4") (pinfunction "G_4") (pintype "passive"))
    )
    (net (code "137") (name "Net-(IC11-VBUS_EN_SRC)") (class "Default")
      (node (ref "IC11") (pin "14") (pinfunction "VBUS_EN_SRC_14") (pintype "open_collector"))
      (node (ref "R148") (pin "2") (pinfunction "2_2") (pintype "passive"))
    )
    (net (code "138") (name "Net-(IC11-VREG1V2)") (class "Default")
      (node (ref "C117") (pin "1") (pinfunction "1_1") (pintype "passive"))
      (node (ref "IC11") (pin "15") (pinfunction "VREG1V2_15") (pintype "input"))
    )
    (net (code "139") (name "Net-(IC11-VREG2V7)") (class "Default")
      (node (ref "C118") (pin "1") (pinfunction "1_1") (pintype "passive"))
      (node (ref "IC11") (pin "16") (pinfunction "VREG2V7_16") (pintype "input"))
    )
    (net (code "140") (name "Net-(IC12-BOOT1)") (class "Default")
      (node (ref "C45") (pin "2") (pinfunction "2_2") (pintype "passive"))
      (node (ref "IC12") (pin "22") (pinfunction "BOOT1_22") (pintype "power_in"))
    )
    (net (code "141") (name "Net-(IC12-BOOT2)") (class "Default")
      (node (ref "C46") (pin "2") (pinfunction "2_2") (pintype "passive"))
      (node (ref "IC12") (pin "20") (pinfunction "BOOT2_20") (pintype "power_in"))
    )
    (net (code "142") (name "Net-(IC12-CDC)") (class "Default")
      (node (ref "IC12") (pin "16") (pinfunction "CDC_16") (pintype "output"))
      (node (ref "R61") (pin "1") (pinfunction "1_1") (pintype "passive"))
    )
    (net (code "143") (name "Net-(IC12-COMP)") (class "Default")
      (node (ref "C43") (pin "1") (pinfunction "1_1") (pintype "passive"))
      (node (ref "IC12") (pin "18") (pinfunction "COMP_18") (pintype "input"))
      (node (ref "R62") (pin "1") (pinfunction "1_1") (pintype "passive"))
    )
    (net (code "144") (name "Net-(IC12-DITH_SYNC)") (class "Default")
      (node (ref "C42") (pin "1") (pinfunction "1_1") (pintype "passive"))
      (node (ref "IC12") (pin "7") (pinfunction "DITH_SYNC_7") (pintype "input"))
    )
    (net (code "145") (name "Net-(IC12-DR1H)") (class "Default")
      (node (ref "IC12") (pin "2") (pinfunction "DR1H_2") (pintype "output"))
      (node (ref "R65") (pin "1") (pinfunction "1_1") (pintype "passive"))
    )
    (net (code "146") (name "Net-(IC12-DR1L)") (class "Default")
      (node (ref "IC12") (pin "1") (pinfunction "DR1L_1") (pintype "output"))
      (node (ref "R64") (pin "1") (pinfunction "1_1") (pintype "passive"))
    )
    (net (code "147") (name "Net-(IC12-FB)") (class "Default")
      (node (ref "IC12") (pin "14") (pinfunction "FB_14") (pintype "input"))
      (node (ref "R11") (pin "1") (pinfunction "1_1") (pintype "passive"))
      (node (ref "R5") (pin "2") (pinfunction "2_2") (pintype "passive"))
    )
    (net (code "148") (name "Net-(IC12-FSW)") (class "Default")
      (node (ref "IC12") (pin "8") (pinfunction "FSW_8") (pintype "input"))
      (node (ref "R59") (pin "1") (pinfunction "1_1") (pintype "passive"))
    )
    (net (code "149") (name "Net-(IC12-ILIM)") (class "Default")
      (node (ref "IC12") (pin "17") (pinfunction "ILIM_17") (pintype "output"))
      (node (ref "R60") (pin "1") (pinfunction "1_1") (pintype "passive"))
    )
    (net (code "150") (name "Net-(IC12-MODE)") (class "Default")
      (node (ref "IC12") (pin "15") (pinfunction "MODE_15") (pintype "input"))
      (node (ref "R58") (pin "1") (pinfunction "1_1") (pintype "passive"))
    )
    (net (code "151") (name "Net-(IC12-SW1)") (class "Default")
      (node (ref "C45") (pin "1") (pinfunction "1_1") (pintype "passive"))
      (node (ref "IC12") (pin "23") (pinfunction "SW1_23") (pintype "power_in"))
      (node (ref "L2") (pin "1") (pinfunction "1_1") (pintype "passive"))
      (node (ref "T10") (pin "1") (pinfunction "S_1") (pintype "passive"))
      (node (ref "T10") (pin "2") (pinfunction "S_2") (pintype "passive"))
      (node (ref "T10") (pin "3") (pinfunction "S_3") (pintype "passive"))
      (node (ref "T9") (pin "5") (pinfunction "D_5") (pintype "passive"))
      (node (ref "T9") (pin "6") (pinfunction "D_6") (pintype "passive"))
      (node (ref "T9") (pin "7") (pinfunction "D_7") (pintype "passive"))
      (node (ref "T9") (pin "8") (pinfunction "D_8") (pintype "passive"))
      (node (ref "T9") (pin "9") (pinfunction "D_9") (pintype "passive"))
    )
    (net (code "152") (name "Net-(IC12-VCC)") (class "Default")
      (node (ref "C41") (pin "1") (pinfunction "1_1") (pintype "passive"))
      (node (ref "IC12") (pin "19") (pinfunction "VCC_19") (pintype "power_in"))
    )
    (net (code "153") (name "Net-(IC14-ADDR0)") (class "Default")
      (node (ref "IC14") (pin "9") (pinfunction "ADDR0_9") (pintype "input"))
      (node (ref "R120") (pin "2") (pinfunction "2_2") (pintype "passive"))
      (node (ref "R121") (pin "1") (pinfunction "1_1") (pintype "passive"))
    )
    (net (code "154") (name "Net-(IC14-SEL_PDO2)") (class "Default")
      (node (ref "IC14") (pin "8") (pinfunction "SEL_PDO2_8") (pintype "open_collector"))
      (node (ref "R118") (pin "2") (pinfunction "2_2") (pintype "passive"))
      (node (ref "R119") (pin "1") (pinfunction "1_1") (pintype "passive"))
    )
    (net (code "155") (name "Net-(IC14-SEL_PDO3)") (class "Default")
      (node (ref "IC14") (pin "7") (pinfunction "SEL_PDO3_7") (pintype "open_collector"))
      (node (ref "R117") (pin "2") (pinfunction "2_2") (pintype "passive"))
      (node (ref "R118") (pin "1") (pinfunction "1_1") (pintype "passive"))
    )
    (net (code "156") (name "Net-(IC14-SEL_PDO4)") (class "Default")
      (node (ref "IC14") (pin "10") (pinfunction "SEL_PDO4_10") (pintype "open_collector"))
      (node (ref "R116") (pin "2") (pinfunction "2_2") (pintype "passive"))
      (node (ref "R117") (pin "1") (pinfunction "1_1") (pintype "passive"))
    )
    (net (code "157") (name "Net-(IC14-SEL_PDO5)") (class "Default")
      (node (ref "IC14") (pin "11") (pinfunction "SEL_PDO5_11") (pintype "open_collector"))
      (node (ref "R115") (pin "2") (pinfunction "2_2") (pintype "passive"))
      (node (ref "R116") (pin "1") (pinfunction "1_1") (pintype "passive"))
    )
    (net (code "158") (name "Net-(IC14-VBUS_DISCH)") (class "Default")
      (node (ref "IC14") (pin "13") (pinfunction "VBUS_DISCH_13") (pintype "output"))
      (node (ref "R123") (pin "2") (pinfunction "2_2") (pintype "passive"))
      (node (ref "T21") (pin "4") (pinfunction "G_4") (pintype "passive"))
    )
    (net (code "159") (name "Net-(IC14-VBUS_EN_SRC)") (class "Default")
      (node (ref "IC14") (pin "14") (pinfunction "VBUS_EN_SRC_14") (pintype "open_collector"))
      (node (ref "R125") (pin "2") (pinfunction "2_2") (pintype "passive"))
    )
    (net (code "160") (name "Net-(IC14-VREG1V2)") (class "Default")
      (node (ref "C98") (pin "1") (pinfunction "1_1") (pintype "passive"))
      (node (ref "IC14") (pin "15") (pinfunction "VREG1V2_15") (pintype "input"))
    )
    (net (code "161") (name "Net-(IC14-VREG2V7)") (class "Default")
      (node (ref "C99") (pin "1") (pinfunction "1_1") (pintype "passive"))
      (node (ref "IC14") (pin "16") (pinfunction "VREG2V7_16") (pintype "input"))
    )
    (net (code "162") (name "Net-(IC15-BOOT1)") (class "Default")
      (node (ref "C64") (pin "2") (pinfunction "2_2") (pintype "passive"))
      (node (ref "IC15") (pin "22") (pinfunction "BOOT1_22") (pintype "power_in"))
    )
    (net (code "163") (name "Net-(IC15-BOOT2)") (class "Default")
      (node (ref "C65") (pin "2") (pinfunction "2_2") (pintype "passive"))
      (node (ref "IC15") (pin "20") (pinfunction "BOOT2_20") (pintype "power_in"))
    )
    (net (code "164") (name "Net-(IC15-CDC)") (class "Default")
      (node (ref "IC15") (pin "16") (pinfunction "CDC_16") (pintype "output"))
      (node (ref "R85") (pin "1") (pinfunction "1_1") (pintype "passive"))
    )
    (net (code "165") (name "Net-(IC15-COMP)") (class "Default")
      (node (ref "C62") (pin "1") (pinfunction "1_1") (pintype "passive"))
      (node (ref "IC15") (pin "18") (pinfunction "COMP_18") (pintype "input"))
      (node (ref "R86") (pin "1") (pinfunction "1_1") (pintype "passive"))
    )
    (net (code "166") (name "Net-(IC15-DITH_SYNC)") (class "Default")
      (node (ref "C61") (pin "1") (pinfunction "1_1") (pintype "passive"))
      (node (ref "IC15") (pin "7") (pinfunction "DITH_SYNC_7") (pintype "input"))
    )
    (net (code "167") (name "Net-(IC15-DR1H)") (class "Default")
      (node (ref "IC15") (pin "2") (pinfunction "DR1H_2") (pintype "output"))
      (node (ref "R89") (pin "1") (pinfunction "1_1") (pintype "passive"))
    )
    (net (code "168") (name "Net-(IC15-DR1L)") (class "Default")
      (node (ref "IC15") (pin "1") (pinfunction "DR1L_1") (pintype "output"))
      (node (ref "R88") (pin "1") (pinfunction "1_1") (pintype "passive"))
    )
    (net (code "169") (name "Net-(IC15-FB)") (class "Default")
      (node (ref "IC15") (pin "14") (pinfunction "FB_14") (pintype "input"))
      (node (ref "R67") (pin "2") (pinfunction "2_2") (pintype "passive"))
      (node (ref "R68") (pin "1") (pinfunction "1_1") (pintype "passive"))
    )
    (net (code "170") (name "Net-(IC15-FSW)") (class "Default")
      (node (ref "IC15") (pin "8") (pinfunction "FSW_8") (pintype "input"))
      (node (ref "R82") (pin "1") (pinfunction "1_1") (pintype "passive"))
    )
    (net (code "171") (name "Net-(IC15-ILIM)") (class "Default")
      (node (ref "IC15") (pin "17") (pinfunction "ILIM_17") (pintype "output"))
      (node (ref "R83") (pin "1") (pinfunction "1_1") (pintype "passive"))
    )
    (net (code "172") (name "Net-(IC15-MODE)") (class "Default")
      (node (ref "IC15") (pin "15") (pinfunction "MODE_15") (pintype "input"))
      (node (ref "R81") (pin "1") (pinfunction "1_1") (pintype "passive"))
    )
    (net (code "173") (name "Net-(IC15-SW1)") (class "Default")
      (node (ref "C64") (pin "1") (pinfunction "1_1") (pintype "passive"))
      (node (ref "IC15") (pin "23") (pinfunction "SW1_23") (pintype "power_in"))
      (node (ref "L3") (pin "1") (pinfunction "1_1") (pintype "passive"))
      (node (ref "T14") (pin "5") (pinfunction "D_5") (pintype "passive"))
      (node (ref "T14") (pin "6") (pinfunction "D_6") (pintype "passive"))
      (node (ref "T14") (pin "7") (pinfunction "D_7") (pintype "passive"))
      (node (ref "T14") (pin "8") (pinfunction "D_8") (pintype "passive"))
      (node (ref "T14") (pin "9") (pinfunction "D_9") (pintype "passive"))
      (node (ref "T15") (pin "1") (pinfunction "S_1") (pintype "passive"))
      (node (ref "T15") (pin "2") (pinfunction "S_2") (pintype "passive"))
      (node (ref "T15") (pin "3") (pinfunction "S_3") (pintype "passive"))
    )
    (net (code "174") (name "Net-(IC15-VCC)") (class "Default")
      (node (ref "C60") (pin "1") (pinfunction "1_1") (pintype "passive"))
      (node (ref "IC15") (pin "19") (pinfunction "VCC_19") (pintype "power_in"))
    )
    (net (code "175") (name "Net-(IC17-ADDR0)") (class "Default")
      (node (ref "IC17") (pin "9") (pinfunction "ADDR0_9") (pintype "input"))
      (node (ref "R97") (pin "2") (pinfunction "2_2") (pintype "passive"))
      (node (ref "R98") (pin "1") (pinfunction "1_1") (pintype "passive"))
    )
    (net (code "176") (name "Net-(IC17-SEL_PDO2)") (class "Default")
      (node (ref "IC17") (pin "8") (pinfunction "SEL_PDO2_8") (pintype "open_collector"))
      (node (ref "R95") (pin "2") (pinfunction "2_2") (pintype "passive"))
      (node (ref "R96") (pin "1") (pinfunction "1_1") (pintype "passive"))
    )
    (net (code "177") (name "Net-(IC17-SEL_PDO3)") (class "Default")
      (node (ref "IC17") (pin "7") (pinfunction "SEL_PDO3_7") (pintype "open_collector"))
      (node (ref "R94") (pin "2") (pinfunction "2_2") (pintype "passive"))
      (node (ref "R95") (pin "1") (pinfunction "1_1") (pintype "passive"))
    )
    (net (code "178") (name "Net-(IC17-SEL_PDO4)") (class "Default")
      (node (ref "IC17") (pin "10") (pinfunction "SEL_PDO4_10") (pintype "open_collector"))
      (node (ref "R93") (pin "2") (pinfunction "2_2") (pintype "passive"))
      (node (ref "R94") (pin "1") (pinfunction "1_1") (pintype "passive"))
    )
    (net (code "179") (name "Net-(IC17-SEL_PDO5)") (class "Default")
      (node (ref "IC17") (pin "11") (pinfunction "SEL_PDO5_11") (pintype "open_collector"))
      (node (ref "R92") (pin "2") (pinfunction "2_2") (pintype "passive"))
      (node (ref "R93") (pin "1") (pinfunction "1_1") (pintype "passive"))
    )
    (net (code "180") (name "Net-(IC17-VBUS_DISCH)") (class "Default")
      (node (ref "IC17") (pin "13") (pinfunction "VBUS_DISCH_13") (pintype "output"))
      (node (ref "R100") (pin "2") (pinfunction "2_2") (pintype "passive"))
      (node (ref "T16") (pin "4") (pinfunction "G_4") (pintype "passive"))
    )
    (net (code "181") (name "Net-(IC17-VBUS_EN_SRC)") (class "Default")
      (node (ref "IC17") (pin "14") (pinfunction "VBUS_EN_SRC_14") (pintype "open_collector"))
      (node (ref "R102") (pin "2") (pinfunction "2_2") (pintype "passive"))
    )
    (net (code "182") (name "Net-(IC17-VREG1V2)") (class "Default")
      (node (ref "C75") (pin "1") (pinfunction "1_1") (pintype "passive"))
      (node (ref "IC17") (pin "15") (pinfunction "VREG1V2_15") (pintype "input"))
    )
    (net (code "183") (name "Net-(IC17-VREG2V7)") (class "Default")
      (node (ref "C76") (pin "1") (pinfunction "1_1") (pintype "passive"))
      (node (ref "IC17") (pin "16") (pinfunction "VREG2V7_16") (pintype "input"))
    )
    (net (code "184") (name "Net-(IC18-BOOT1)") (class "Default")
      (node (ref "C87") (pin "2") (pinfunction "2_2") (pintype "passive"))
      (node (ref "IC18") (pin "22") (pinfunction "BOOT1_22") (pintype "power_in"))
    )
    (net (code "185") (name "Net-(IC18-BOOT2)") (class "Default")
      (node (ref "C88") (pin "2") (pinfunction "2_2") (pintype "passive"))
      (node (ref "IC18") (pin "20") (pinfunction "BOOT2_20") (pintype "power_in"))
    )
    (net (code "186") (name "Net-(IC18-CDC)") (class "Default")
      (node (ref "IC18") (pin "16") (pinfunction "CDC_16") (pintype "output"))
      (node (ref "R108") (pin "1") (pinfunction "1_1") (pintype "passive"))
    )
    (net (code "187") (name "Net-(IC18-COMP)") (class "Default")
      (node (ref "C81") (pin "1") (pinfunction "1_1") (pintype "passive"))
      (node (ref "IC18") (pin "18") (pinfunction "COMP_18") (pintype "input"))
      (node (ref "R109") (pin "1") (pinfunction "1_1") (pintype "passive"))
    )
    (net (code "188") (name "Net-(IC18-DITH_SYNC)") (class "Default")
      (node (ref "C80") (pin "1") (pinfunction "1_1") (pintype "passive"))
      (node (ref "IC18") (pin "7") (pinfunction "DITH_SYNC_7") (pintype "input"))
    )
    (net (code "189") (name "Net-(IC18-DR1H)") (class "Default")
      (node (ref "IC18") (pin "2") (pinfunction "DR1H_2") (pintype "output"))
      (node (ref "R112") (pin "1") (pinfunction "1_1") (pintype "passive"))
    )
    (net (code "190") (name "Net-(IC18-DR1L)") (class "Default")
      (node (ref "IC18") (pin "1") (pinfunction "DR1L_1") (pintype "output"))
      (node (ref "R111") (pin "1") (pinfunction "1_1") (pintype "passive"))
    )
    (net (code "191") (name "Net-(IC18-FB)") (class "Default")
      (node (ref "IC18") (pin "14") (pinfunction "FB_14") (pintype "input"))
      (node (ref "R91") (pin "2") (pinfunction "2_2") (pintype "passive"))
      (node (ref "R92") (pin "1") (pinfunction "1_1") (pintype "passive"))
    )
    (net (code "192") (name "Net-(IC18-FSW)") (class "Default")
      (node (ref "IC18") (pin "8") (pinfunction "FSW_8") (pintype "input"))
      (node (ref "R106") (pin "1") (pinfunction "1_1") (pintype "passive"))
    )
    (net (code "193") (name "Net-(IC18-ILIM)") (class "Default")
      (node (ref "IC18") (pin "17") (pinfunction "ILIM_17") (pintype "output"))
      (node (ref "R107") (pin "1") (pinfunction "1_1") (pintype "passive"))
    )
    (net (code "194") (name "Net-(IC18-MODE)") (class "Default")
      (node (ref "IC18") (pin "15") (pinfunction "MODE_15") (pintype "input"))
      (node (ref "R105") (pin "1") (pinfunction "1_1") (pintype "passive"))
    )
    (net (code "195") (name "Net-(IC18-SW1)") (class "Default")
      (node (ref "C87") (pin "1") (pinfunction "1_1") (pintype "passive"))
      (node (ref "IC18") (pin "23") (pinfunction "SW1_23") (pintype "power_in"))
      (node (ref "L4") (pin "1") (pinfunction "1_1") (pintype "passive"))
      (node (ref "T19") (pin "5") (pinfunction "D_5") (pintype "passive"))
      (node (ref "T19") (pin "6") (pinfunction "D_6") (pintype "passive"))
      (node (ref "T19") (pin "7") (pinfunction "D_7") (pintype "passive"))
      (node (ref "T19") (pin "8") (pinfunction "D_8") (pintype "passive"))
      (node (ref "T19") (pin "9") (pinfunction "D_9") (pintype "passive"))
      (node (ref "T20") (pin "1") (pinfunction "S_1") (pintype "passive"))
      (node (ref "T20") (pin "2") (pinfunction "S_2") (pintype "passive"))
      (node (ref "T20") (pin "3") (pinfunction "S_3") (pintype "passive"))
    )
    (net (code "196") (name "Net-(IC18-VCC)") (class "Default")
      (node (ref "C79") (pin "1") (pinfunction "1_1") (pintype "passive"))
      (node (ref "IC18") (pin "19") (pinfunction "VCC_19") (pintype "power_in"))
    )
    (net (code "197") (name "Net-(IC20-ADDR0)") (class "Default")
      (node (ref "IC20") (pin "9") (pinfunction "ADDR0_9") (pintype "input"))
      (node (ref "R166") (pin "2") (pinfunction "2_2") (pintype "passive"))
      (node (ref "R167") (pin "1") (pinfunction "1_1") (pintype "passive"))
    )
    (net (code "198") (name "Net-(IC20-SEL_PDO2)") (class "Default")
      (node (ref "IC20") (pin "8") (pinfunction "SEL_PDO2_8") (pintype "open_collector"))
      (node (ref "R164") (pin "2") (pinfunction "2_2") (pintype "passive"))
      (node (ref "R165") (pin "1") (pinfunction "1_1") (pintype "passive"))
    )
    (net (code "199") (name "Net-(IC20-SEL_PDO3)") (class "Default")
      (node (ref "IC20") (pin "7") (pinfunction "SEL_PDO3_7") (pintype "open_collector"))
      (node (ref "R163") (pin "2") (pinfunction "2_2") (pintype "passive"))
      (node (ref "R164") (pin "1") (pinfunction "1_1") (pintype "passive"))
    )
    (net (code "200") (name "Net-(IC20-SEL_PDO4)") (class "Default")
      (node (ref "IC20") (pin "10") (pinfunction "SEL_PDO4_10") (pintype "open_collector"))
      (node (ref "R162") (pin "2") (pinfunction "2_2") (pintype "passive"))
      (node (ref "R163") (pin "1") (pinfunction "1_1") (pintype "passive"))
    )
    (net (code "201") (name "Net-(IC20-SEL_PDO5)") (class "Default")
      (node (ref "IC20") (pin "11") (pinfunction "SEL_PDO5_11") (pintype "open_collector"))
      (node (ref "R161") (pin "2") (pinfunction "2_2") (pintype "passive"))
      (node (ref "R162") (pin "1") (pinfunction "1_1") (pintype "passive"))
    )
    (net (code "202") (name "Net-(IC20-VBUS_DISCH)") (class "Default")
      (node (ref "IC20") (pin "13") (pinfunction "VBUS_DISCH_13") (pintype "output"))
      (node (ref "R169") (pin "2") (pinfunction "2_2") (pintype "passive"))
      (node (ref "T31") (pin "4") (pinfunction "G_4") (pintype "passive"))
    )
    (net (code "203") (name "Net-(IC20-VBUS_EN_SRC)") (class "Default")
      (node (ref "IC20") (pin "14") (pinfunction "VBUS_EN_SRC_14") (pintype "open_collector"))
      (node (ref "R171") (pin "2") (pinfunction "2_2") (pintype "passive"))
    )
    (net (code "204") (name "Net-(IC20-VREG1V2)") (class "Default")
      (node (ref "C136") (pin "1") (pinfunction "1_1") (pintype "passive"))
      (node (ref "IC20") (pin "15") (pinfunction "VREG1V2_15") (pintype "input"))
    )
    (net (code "205") (name "Net-(IC20-VREG2V7)") (class "Default")
      (node (ref "C137") (pin "1") (pinfunction "1_1") (pintype "passive"))
      (node (ref "IC20") (pin "16") (pinfunction "VREG2V7_16") (pintype "input"))
    )
    (net (code "206") (name "Net-(IC21-BOOT1)") (class "Default")
      (node (ref "C106") (pin "2") (pinfunction "2_2") (pintype "passive"))
      (node (ref "IC21") (pin "22") (pinfunction "BOOT1_22") (pintype "power_in"))
    )
    (net (code "207") (name "Net-(IC21-BOOT2)") (class "Default")
      (node (ref "C107") (pin "2") (pinfunction "2_2") (pintype "passive"))
      (node (ref "IC21") (pin "20") (pinfunction "BOOT2_20") (pintype "power_in"))
    )
    (net (code "208") (name "Net-(IC21-CDC)") (class "Default")
      (node (ref "IC21") (pin "16") (pinfunction "CDC_16") (pintype "output"))
      (node (ref "R131") (pin "1") (pinfunction "1_1") (pintype "passive"))
    )
    (net (code "209") (name "Net-(IC21-COMP)") (class "Default")
      (node (ref "C104") (pin "1") (pinfunction "1_1") (pintype "passive"))
      (node (ref "IC21") (pin "18") (pinfunction "COMP_18") (pintype "input"))
      (node (ref "R132") (pin "1") (pinfunction "1_1") (pintype "passive"))
    )
    (net (code "210") (name "Net-(IC21-DITH_SYNC)") (class "Default")
      (node (ref "C103") (pin "1") (pinfunction "1_1") (pintype "passive"))
      (node (ref "IC21") (pin "7") (pinfunction "DITH_SYNC_7") (pintype "input"))
    )
    (net (code "211") (name "Net-(IC21-DR1H)") (class "Default")
      (node (ref "IC21") (pin "2") (pinfunction "DR1H_2") (pintype "output"))
      (node (ref "R135") (pin "1") (pinfunction "1_1") (pintype "passive"))
    )
    (net (code "212") (name "Net-(IC21-DR1L)") (class "Default")
      (node (ref "IC21") (pin "1") (pinfunction "DR1L_1") (pintype "output"))
      (node (ref "R134") (pin "1") (pinfunction "1_1") (pintype "passive"))
    )
    (net (code "213") (name "Net-(IC21-FB)") (class "Default")
      (node (ref "IC21") (pin "14") (pinfunction "FB_14") (pintype "input"))
      (node (ref "R114") (pin "2") (pinfunction "2_2") (pintype "passive"))
      (node (ref "R115") (pin "1") (pinfunction "1_1") (pintype "passive"))
    )
    (net (code "214") (name "Net-(IC21-FSW)") (class "Default")
      (node (ref "IC21") (pin "8") (pinfunction "FSW_8") (pintype "input"))
      (node (ref "R129") (pin "1") (pinfunction "1_1") (pintype "passive"))
    )
    (net (code "215") (name "Net-(IC21-ILIM)") (class "Default")
      (node (ref "IC21") (pin "17") (pinfunction "ILIM_17") (pintype "output"))
      (node (ref "R130") (pin "1") (pinfunction "1_1") (pintype "passive"))
    )
    (net (code "216") (name "Net-(IC21-MODE)") (class "Default")
      (node (ref "IC21") (pin "15") (pinfunction "MODE_15") (pintype "input"))
      (node (ref "R128") (pin "1") (pinfunction "1_1") (pintype "passive"))
    )
    (net (code "217") (name "Net-(IC21-SW1)") (class "Default")
      (node (ref "C106") (pin "1") (pinfunction "1_1") (pintype "passive"))
      (node (ref "IC21") (pin "23") (pinfunction "SW1_23") (pintype "power_in"))
      (node (ref "L5") (pin "1") (pinfunction "1_1") (pintype "passive"))
      (node (ref "T24") (pin "5") (pinfunction "D_5") (pintype "passive"))
      (node (ref "T24") (pin "6") (pinfunction "D_6") (pintype "passive"))
      (node (ref "T24") (pin "7") (pinfunction "D_7") (pintype "passive"))
      (node (ref "T24") (pin "8") (pinfunction "D_8") (pintype "passive"))
      (node (ref "T24") (pin "9") (pinfunction "D_9") (pintype "passive"))
      (node (ref "T25") (pin "1") (pinfunction "S_1") (pintype "passive"))
      (node (ref "T25") (pin "2") (pinfunction "S_2") (pintype "passive"))
      (node (ref "T25") (pin "3") (pinfunction "S_3") (pintype "passive"))
    )
    (net (code "218") (name "Net-(IC21-VCC)") (class "Default")
      (node (ref "C102") (pin "1") (pinfunction "1_1") (pintype "passive"))
      (node (ref "IC21") (pin "19") (pinfunction "VCC_19") (pintype "power_in"))
    )
    (net (code "219") (name "Net-(IC23-ADDR0)") (class "Default")
      (node (ref "IC23") (pin "9") (pinfunction "ADDR0_9") (pintype "input"))
      (node (ref "R189") (pin "2") (pinfunction "2_2") (pintype "passive"))
      (node (ref "R190") (pin "1") (pinfunction "1_1") (pintype "passive"))
    )
    (net (code "220") (name "Net-(IC23-SEL_PDO2)") (class "Default")
      (node (ref "IC23") (pin "8") (pinfunction "SEL_PDO2_8") (pintype "open_collector"))
      (node (ref "R187") (pin "2") (pinfunction "2_2") (pintype "passive"))
      (node (ref "R188") (pin "1") (pinfunction "1_1") (pintype "passive"))
    )
    (net (code "221") (name "Net-(IC23-SEL_PDO3)") (class "Default")
      (node (ref "IC23") (pin "7") (pinfunction "SEL_PDO3_7") (pintype "open_collector"))
      (node (ref "R186") (pin "2") (pinfunction "2_2") (pintype "passive"))
      (node (ref "R187") (pin "1") (pinfunction "1_1") (pintype "passive"))
    )
    (net (code "222") (name "Net-(IC23-SEL_PDO4)") (class "Default")
      (node (ref "IC23") (pin "10") (pinfunction "SEL_PDO4_10") (pintype "open_collector"))
      (node (ref "R185") (pin "2") (pinfunction "2_2") (pintype "passive"))
      (node (ref "R186") (pin "1") (pinfunction "1_1") (pintype "passive"))
    )
    (net (code "223") (name "Net-(IC23-SEL_PDO5)") (class "Default")
      (node (ref "IC23") (pin "11") (pinfunction "SEL_PDO5_11") (pintype "open_collector"))
      (node (ref "R184") (pin "2") (pinfunction "2_2") (pintype "passive"))
      (node (ref "R185") (pin "1") (pinfunction "1_1") (pintype "passive"))
    )
    (net (code "224") (name "Net-(IC23-VBUS_DISCH)") (class "Default")
      (node (ref "IC23") (pin "13") (pinfunction "VBUS_DISCH_13") (pintype "output"))
      (node (ref "R192") (pin "2") (pinfunction "2_2") (pintype "passive"))
      (node (ref "T36") (pin "4") (pinfunction "G_4") (pintype "passive"))
    )
    (net (code "225") (name "Net-(IC23-VBUS_EN_SRC)") (class "Default")
      (node (ref "IC23") (pin "14") (pinfunction "VBUS_EN_SRC_14") (pintype "open_collector"))
      (node (ref "R194") (pin "2") (pinfunction "2_2") (pintype "passive"))
    )
    (net (code "226") (name "Net-(IC23-VREG1V2)") (class "Default")
      (node (ref "C155") (pin "1") (pinfunction "1_1") (pintype "passive"))
      (node (ref "IC23") (pin "15") (pinfunction "VREG1V2_15") (pintype "input"))
    )
    (net (code "227") (name "Net-(IC23-VREG2V7)") (class "Default")
      (node (ref "C156") (pin "1") (pinfunction "1_1") (pintype "passive"))
      (node (ref "IC23") (pin "16") (pinfunction "VREG2V7_16") (pintype "input"))
    )
    (net (code "228") (name "Net-(IC24-BOOT1)") (class "Default")
      (node (ref "C125") (pin "2") (pinfunction "2_2") (pintype "passive"))
      (node (ref "IC24") (pin "22") (pinfunction "BOOT1_22") (pintype "power_in"))
    )
    (net (code "229") (name "Net-(IC24-BOOT2)") (class "Default")
      (node (ref "C126") (pin "2") (pinfunction "2_2") (pintype "passive"))
      (node (ref "IC24") (pin "20") (pinfunction "BOOT2_20") (pintype "power_in"))
    )
    (net (code "230") (name "Net-(IC24-CDC)") (class "Default")
      (node (ref "IC24") (pin "16") (pinfunction "CDC_16") (pintype "output"))
      (node (ref "R154") (pin "1") (pinfunction "1_1") (pintype "passive"))
    )
    (net (code "231") (name "Net-(IC24-COMP)") (class "Default")
      (node (ref "C123") (pin "1") (pinfunction "1_1") (pintype "passive"))
      (node (ref "IC24") (pin "18") (pinfunction "COMP_18") (pintype "input"))
      (node (ref "R155") (pin "1") (pinfunction "1_1") (pintype "passive"))
    )
    (net (code "232") (name "Net-(IC24-DITH_SYNC)") (class "Default")
      (node (ref "C122") (pin "1") (pinfunction "1_1") (pintype "passive"))
      (node (ref "IC24") (pin "7") (pinfunction "DITH_SYNC_7") (pintype "input"))
    )
    (net (code "233") (name "Net-(IC24-DR1H)") (class "Default")
      (node (ref "IC24") (pin "2") (pinfunction "DR1H_2") (pintype "output"))
      (node (ref "R158") (pin "1") (pinfunction "1_1") (pintype "passive"))
    )
    (net (code "234") (name "Net-(IC24-DR1L)") (class "Default")
      (node (ref "IC24") (pin "1") (pinfunction "DR1L_1") (pintype "output"))
      (node (ref "R157") (pin "1") (pinfunction "1_1") (pintype "passive"))
    )
    (net (code "235") (name "Net-(IC24-FB)") (class "Default")
      (node (ref "IC24") (pin "14") (pinfunction "FB_14") (pintype "input"))
      (node (ref "R137") (pin "2") (pinfunction "2_2") (pintype "passive"))
      (node (ref "R138") (pin "1") (pinfunction "1_1") (pintype "passive"))
    )
    (net (code "236") (name "Net-(IC24-FSW)") (class "Default")
      (node (ref "IC24") (pin "8") (pinfunction "FSW_8") (pintype "input"))
      (node (ref "R152") (pin "1") (pinfunction "1_1") (pintype "passive"))
    )
    (net (code "237") (name "Net-(IC24-ILIM)") (class "Default")
      (node (ref "IC24") (pin "17") (pinfunction "ILIM_17") (pintype "output"))
      (node (ref "R153") (pin "1") (pinfunction "1_1") (pintype "passive"))
    )
    (net (code "238") (name "Net-(IC24-MODE)") (class "Default")
      (node (ref "IC24") (pin "15") (pinfunction "MODE_15") (pintype "input"))
      (node (ref "R151") (pin "1") (pinfunction "1_1") (pintype "passive"))
    )
    (net (code "239") (name "Net-(IC24-SW1)") (class "Default")
      (node (ref "C125") (pin "1") (pinfunction "1_1") (pintype "passive"))
      (node (ref "IC24") (pin "23") (pinfunction "SW1_23") (pintype "power_in"))
      (node (ref "L6") (pin "1") (pinfunction "1_1") (pintype "passive"))
      (node (ref "T29") (pin "5") (pinfunction "D_5") (pintype "passive"))
      (node (ref "T29") (pin "6") (pinfunction "D_6") (pintype "passive"))
      (node (ref "T29") (pin "7") (pinfunction "D_7") (pintype "passive"))
      (node (ref "T29") (pin "8") (pinfunction "D_8") (pintype "passive"))
      (node (ref "T29") (pin "9") (pinfunction "D_9") (pintype "passive"))
      (node (ref "T30") (pin "1") (pinfunction "S_1") (pintype "passive"))
      (node (ref "T30") (pin "2") (pinfunction "S_2") (pintype "passive"))
      (node (ref "T30") (pin "3") (pinfunction "S_3") (pintype "passive"))
    )
    (net (code "240") (name "Net-(IC24-VCC)") (class "Default")
      (node (ref "C121") (pin "1") (pinfunction "1_1") (pintype "passive"))
      (node (ref "IC24") (pin "19") (pinfunction "VCC_19") (pintype "power_in"))
    )
    (net (code "241") (name "Net-(IC26-USB_DM)") (class "Default")
      (node (ref "IC26") (pin "46") (pinfunction "USB_DM_46") (pintype "bidirectional"))
      (node (ref "R205") (pin "2") (pinfunction "2_2") (pintype "passive"))
    )
    (net (code "242") (name "Net-(IC26-USB_DP)") (class "Default")
      (node (ref "IC26") (pin "47") (pinfunction "USB_DP_47") (pintype "bidirectional"))
      (node (ref "R206") (pin "2") (pinfunction "2_2") (pintype "passive"))
    )
    (net (code "243") (name "Net-(IC28-+IN)") (class "Default")
      (node (ref "C179") (pin "1") (pinfunction "1_1") (pintype "passive"))
      (node (ref "C180") (pin "1") (pinfunction "1_1") (pintype "passive"))
      (node (ref "IC28") (pin "3") (pinfunction "+IN_3") (pintype "input"))
      (node (ref "R212") (pin "1") (pinfunction "1_1") (pintype "passive"))
      (node (ref "REF1") (pin "1") (pinfunction "C_1") (pintype "passive"))
      (node (ref "VREF") (pin "TP") (pinfunction "P$1_TP") (pintype "bidirectional"))
    )
    (net (code "244") (name "Net-(IC29-A0)") (class "Default")
      (node (ref "IC29") (pin "1") (pinfunction "A0_1") (pintype "bidirectional"))
      (node (ref "R213") (pin "1") (pinfunction "1_1") (pintype "passive"))
      (node (ref "R214") (pin "2") (pinfunction "2_2") (pintype "passive"))
    )
    (net (code "245") (name "Net-(IC30-ADDR0)") (class "Default")
      (node (ref "IC30") (pin "9") (pinfunction "ADDR0_9") (pintype "input"))
      (node (ref "R245") (pin "2") (pinfunction "2_2") (pintype "passive"))
      (node (ref "R246") (pin "1") (pinfunction "1_1") (pintype "passive"))
    )
    (net (code "246") (name "Net-(IC30-SEL_PDO2)") (class "Default")
      (node (ref "IC30") (pin "8") (pinfunction "SEL_PDO2_8") (pintype "open_collector"))
      (node (ref "R223") (pin "2") (pinfunction "2_2") (pintype "passive"))
      (node (ref "R224") (pin "1") (pinfunction "1_1") (pintype "passive"))
    )
    (net (code "247") (name "Net-(IC30-SEL_PDO3)") (class "Default")
      (node (ref "IC30") (pin "7") (pinfunction "SEL_PDO3_7") (pintype "open_collector"))
      (node (ref "R222") (pin "2") (pinfunction "2_2") (pintype "passive"))
      (node (ref "R223") (pin "1") (pinfunction "1_1") (pintype "passive"))
    )
    (net (code "248") (name "Net-(IC30-SEL_PDO4)") (class "Default")
      (node (ref "IC30") (pin "10") (pinfunction "SEL_PDO4_10") (pintype "open_collector"))
      (node (ref "R221") (pin "2") (pinfunction "2_2") (pintype "passive"))
      (node (ref "R222") (pin "1") (pinfunction "1_1") (pintype "passive"))
    )
    (net (code "249") (name "Net-(IC30-SEL_PDO5)") (class "Default")
      (node (ref "IC30") (pin "11") (pinfunction "SEL_PDO5_11") (pintype "open_collector"))
      (node (ref "R220") (pin "2") (pinfunction "2_2") (pintype "passive"))
      (node (ref "R221") (pin "1") (pinfunction "1_1") (pintype "passive"))
    )
    (net (code "250") (name "Net-(IC30-VBUS_DISCH)") (class "Default")
      (node (ref "IC30") (pin "13") (pinfunction "VBUS_DISCH_13") (pintype "output"))
      (node (ref "R248") (pin "2") (pinfunction "2_2") (pintype "passive"))
      (node (ref "T41") (pin "4") (pinfunction "G_4") (pintype "passive"))
    )
    (net (code "251") (name "Net-(IC30-VBUS_EN_SRC)") (class "Default")
      (node (ref "IC30") (pin "14") (pinfunction "VBUS_EN_SRC_14") (pintype "open_collector"))
      (node (ref "R260") (pin "2") (pinfunction "2_2") (pintype "passive"))
    )
    (net (code "252") (name "Net-(IC30-VREG1V2)") (class "Default")
      (node (ref "C174") (pin "1") (pinfunction "1_1") (pintype "passive"))
      (node (ref "IC30") (pin "15") (pinfunction "VREG1V2_15") (pintype "input"))
    )
    (net (code "253") (name "Net-(IC30-VREG2V7)") (class "Default")
      (node (ref "C175") (pin "1") (pinfunction "1_1") (pintype "passive"))
      (node (ref "IC30") (pin "16") (pinfunction "VREG2V7_16") (pintype "input"))
    )
    (net (code "254") (name "Net-(IC32-BOOT1)") (class "Default")
      (node (ref "C144") (pin "2") (pinfunction "2_2") (pintype "passive"))
      (node (ref "IC32") (pin "22") (pinfunction "BOOT1_22") (pintype "power_in"))
    )
    (net (code "255") (name "Net-(IC32-BOOT2)") (class "Default")
      (node (ref "C145") (pin "2") (pinfunction "2_2") (pintype "passive"))
      (node (ref "IC32") (pin "20") (pinfunction "BOOT2_20") (pintype "power_in"))
    )
    (net (code "256") (name "Net-(IC32-CDC)") (class "Default")
      (node (ref "IC32") (pin "16") (pinfunction "CDC_16") (pintype "output"))
      (node (ref "R177") (pin "1") (pinfunction "1_1") (pintype "passive"))
    )
    (net (code "257") (name "Net-(IC32-COMP)") (class "Default")
      (node (ref "C142") (pin "1") (pinfunction "1_1") (pintype "passive"))
      (node (ref "IC32") (pin "18") (pinfunction "COMP_18") (pintype "input"))
      (node (ref "R178") (pin "1") (pinfunction "1_1") (pintype "passive"))
    )
    (net (code "258") (name "Net-(IC32-DITH_SYNC)") (class "Default")
      (node (ref "C141") (pin "1") (pinfunction "1_1") (pintype "passive"))
      (node (ref "IC32") (pin "7") (pinfunction "DITH_SYNC_7") (pintype "input"))
    )
    (net (code "259") (name "Net-(IC32-DR1H)") (class "Default")
      (node (ref "IC32") (pin "2") (pinfunction "DR1H_2") (pintype "output"))
      (node (ref "R181") (pin "1") (pinfunction "1_1") (pintype "passive"))
    )
    (net (code "260") (name "Net-(IC32-DR1L)") (class "Default")
      (node (ref "IC32") (pin "1") (pinfunction "DR1L_1") (pintype "output"))
      (node (ref "R180") (pin "1") (pinfunction "1_1") (pintype "passive"))
    )
    (net (code "261") (name "Net-(IC32-FB)") (class "Default")
      (node (ref "IC32") (pin "14") (pinfunction "FB_14") (pintype "input"))
      (node (ref "R160") (pin "2") (pinfunction "2_2") (pintype "passive"))
      (node (ref "R161") (pin "1") (pinfunction "1_1") (pintype "passive"))
    )
    (net (code "262") (name "Net-(IC32-FSW)") (class "Default")
      (node (ref "IC32") (pin "8") (pinfunction "FSW_8") (pintype "input"))
      (node (ref "R175") (pin "1") (pinfunction "1_1") (pintype "passive"))
    )
    (net (code "263") (name "Net-(IC32-ILIM)") (class "Default")
      (node (ref "IC32") (pin "17") (pinfunction "ILIM_17") (pintype "output"))
      (node (ref "R176") (pin "1") (pinfunction "1_1") (pintype "passive"))
    )
    (net (code "264") (name "Net-(IC32-MODE)") (class "Default")
      (node (ref "IC32") (pin "15") (pinfunction "MODE_15") (pintype "input"))
      (node (ref "R174") (pin "1") (pinfunction "1_1") (pintype "passive"))
    )
    (net (code "265") (name "Net-(IC32-SW1)") (class "Default")
      (node (ref "C144") (pin "1") (pinfunction "1_1") (pintype "passive"))
      (node (ref "IC32") (pin "23") (pinfunction "SW1_23") (pintype "power_in"))
      (node (ref "L7") (pin "1") (pinfunction "1_1") (pintype "passive"))
      (node (ref "T34") (pin "5") (pinfunction "D_5") (pintype "passive"))
      (node (ref "T34") (pin "6") (pinfunction "D_6") (pintype "passive"))
      (node (ref "T34") (pin "7") (pinfunction "D_7") (pintype "passive"))
      (node (ref "T34") (pin "8") (pinfunction "D_8") (pintype "passive"))
      (node (ref "T34") (pin "9") (pinfunction "D_9") (pintype "passive"))
      (node (ref "T35") (pin "1") (pinfunction "S_1") (pintype "passive"))
      (node (ref "T35") (pin "2") (pinfunction "S_2") (pintype "passive"))
      (node (ref "T35") (pin "3") (pinfunction "S_3") (pintype "passive"))
    )
    (net (code "266") (name "Net-(IC32-VCC)") (class "Default")
      (node (ref "C140") (pin "1") (pinfunction "1_1") (pintype "passive"))
      (node (ref "IC32") (pin "19") (pinfunction "VCC_19") (pintype "power_in"))
    )
    (net (code "267") (name "Net-(IC35-BOOT1)") (class "Default")
      (node (ref "C163") (pin "2") (pinfunction "2_2") (pintype "passive"))
      (node (ref "IC35") (pin "22") (pinfunction "BOOT1_22") (pintype "power_in"))
    )
    (net (code "268") (name "Net-(IC35-BOOT2)") (class "Default")
      (node (ref "C164") (pin "2") (pinfunction "2_2") (pintype "passive"))
      (node (ref "IC35") (pin "20") (pinfunction "BOOT2_20") (pintype "power_in"))
    )
    (net (code "269") (name "Net-(IC35-CDC)") (class "Default")
      (node (ref "IC35") (pin "16") (pinfunction "CDC_16") (pintype "output"))
      (node (ref "R200") (pin "1") (pinfunction "1_1") (pintype "passive"))
    )
    (net (code "270") (name "Net-(IC35-COMP)") (class "Default")
      (node (ref "C161") (pin "1") (pinfunction "1_1") (pintype "passive"))
      (node (ref "IC35") (pin "18") (pinfunction "COMP_18") (pintype "input"))
      (node (ref "R201") (pin "1") (pinfunction "1_1") (pintype "passive"))
    )
    (net (code "271") (name "Net-(IC35-DITH_SYNC)") (class "Default")
      (node (ref "C160") (pin "1") (pinfunction "1_1") (pintype "passive"))
      (node (ref "IC35") (pin "7") (pinfunction "DITH_SYNC_7") (pintype "input"))
    )
    (net (code "272") (name "Net-(IC35-DR1H)") (class "Default")
      (node (ref "IC35") (pin "2") (pinfunction "DR1H_2") (pintype "output"))
      (node (ref "R204") (pin "1") (pinfunction "1_1") (pintype "passive"))
    )
    (net (code "273") (name "Net-(IC35-DR1L)") (class "Default")
      (node (ref "IC35") (pin "1") (pinfunction "DR1L_1") (pintype "output"))
      (node (ref "R203") (pin "1") (pinfunction "1_1") (pintype "passive"))
    )
    (net (code "274") (name "Net-(IC35-FB)") (class "Default")
      (node (ref "IC35") (pin "14") (pinfunction "FB_14") (pintype "input"))
      (node (ref "R183") (pin "2") (pinfunction "2_2") (pintype "passive"))
      (node (ref "R184") (pin "1") (pinfunction "1_1") (pintype "passive"))
    )
    (net (code "275") (name "Net-(IC35-FSW)") (class "Default")
      (node (ref "IC35") (pin "8") (pinfunction "FSW_8") (pintype "input"))
      (node (ref "R198") (pin "1") (pinfunction "1_1") (pintype "passive"))
    )
    (net (code "276") (name "Net-(IC35-ILIM)") (class "Default")
      (node (ref "IC35") (pin "17") (pinfunction "ILIM_17") (pintype "output"))
      (node (ref "R199") (pin "1") (pinfunction "1_1") (pintype "passive"))
    )
    (net (code "277") (name "Net-(IC35-MODE)") (class "Default")
      (node (ref "IC35") (pin "15") (pinfunction "MODE_15") (pintype "input"))
      (node (ref "R197") (pin "1") (pinfunction "1_1") (pintype "passive"))
    )
    (net (code "278") (name "Net-(IC35-SW1)") (class "Default")
      (node (ref "C163") (pin "1") (pinfunction "1_1") (pintype "passive"))
      (node (ref "IC35") (pin "23") (pinfunction "SW1_23") (pintype "power_in"))
      (node (ref "L8") (pin "1") (pinfunction "1_1") (pintype "passive"))
      (node (ref "T39") (pin "5") (pinfunction "D_5") (pintype "passive"))
      (node (ref "T39") (pin "6") (pinfunction "D_6") (pintype "passive"))
      (node (ref "T39") (pin "7") (pinfunction "D_7") (pintype "passive"))
      (node (ref "T39") (pin "8") (pinfunction "D_8") (pintype "passive"))
      (node (ref "T39") (pin "9") (pinfunction "D_9") (pintype "passive"))
      (node (ref "T40") (pin "1") (pinfunction "S_1") (pintype "passive"))
      (node (ref "T40") (pin "2") (pinfunction "S_2") (pintype "passive"))
      (node (ref "T40") (pin "3") (pinfunction "S_3") (pintype "passive"))
    )
    (net (code "279") (name "Net-(IC35-VCC)") (class "Default")
      (node (ref "C159") (pin "1") (pinfunction "1_1") (pintype "passive"))
      (node (ref "IC35") (pin "19") (pinfunction "VCC_19") (pintype "power_in"))
    )
    (net (code "280") (name "Net-(IC39-1V2O)") (class "Default")
      (node (ref "C217") (pin "1") (pinfunction "1_1") (pintype "passive"))
      (node (ref "IC39") (pin "22") (pinfunction "1V2O_22") (pintype "output"))
    )
    (net (code "281") (name "Net-(IC39-EXRES1)") (class "Default")
      (node (ref "IC39") (pin "10") (pinfunction "EXRES1_10") (pintype "bidirectional"))
      (node (ref "R234") (pin "2") (pinfunction "2_2") (pintype "passive"))
    )
    (net (code "282") (name "Net-(IC39-TOCAP)") (class "Default")
      (node (ref "C218") (pin "1") (pinfunction "1_1") (pintype "passive"))
      (node (ref "IC39") (pin "20") (pinfunction "TOCAP_20") (pintype "output"))
    )
    (net (code "283") (name "Net-(IC39-XI)") (class "Default")
      (node (ref "C220") (pin "1") (pinfunction "1_1") (pintype "passive"))
      (node (ref "IC39") (pin "30") (pinfunction "XI_30") (pintype "input"))
      (node (ref "R235") (pin "1") (pinfunction "1_1") (pintype "passive"))
      (node (ref "X2") (pin "3") (pinfunction "2_3") (pintype "passive"))
    )
    (net (code "284") (name "Net-(IC39-XO)") (class "Default")
      (node (ref "C219") (pin "1") (pinfunction "1_1") (pintype "passive"))
      (node (ref "IC39") (pin "31") (pinfunction "XO_31") (pintype "output"))
      (node (ref "R235") (pin "2") (pinfunction "2_2") (pintype "passive"))
      (node (ref "X2") (pin "1") (pinfunction "1_1") (pintype "passive"))
    )
    (net (code "285") (name "Net-(IC40-AAM)") (class "Default")
      (node (ref "IC40") (pin "1") (pinfunction "AAM_1") (pintype "bidirectional"))
      (node (ref "R242") (pin "1") (pinfunction "1_1") (pintype "passive"))
      (node (ref "R244") (pin "2") (pinfunction "2_2") (pintype "passive"))
    )
    (net (code "286") (name "Net-(IC40-BST)") (class "Default")
      (node (ref "IC40") (pin "5") (pinfunction "BST_5") (pintype "bidirectional"))
      (node (ref "R243") (pin "2") (pinfunction "2_2") (pintype "passive"))
    )
    (net (code "287") (name "Net-(IC40-EN)") (class "Default")
      (node (ref "IC40") (pin "6") (pinfunction "EN_6") (pintype "bidirectional"))
      (node (ref "R241") (pin "2") (pinfunction "2_2") (pintype "passive"))
    )
    (net (code "288") (name "Net-(IC40-FB)") (class "Default")
      (node (ref "IC40") (pin "8") (pinfunction "FB_8") (pintype "bidirectional"))
      (node (ref "RT1") (pin "1") (pinfunction "1_1") (pintype "passive"))
    )
    (net (code "289") (name "Net-(IC40-SW)") (class "Default")
      (node (ref "C235") (pin "2") (pinfunction "2_2") (pintype "passive"))
      (node (ref "IC40") (pin "3") (pinfunction "SW_3") (pintype "bidirectional"))
      (node (ref "L11") (pin "1") (pinfunction "1_1") (pintype "passive"))
    )
    (net (code "290") (name "Net-(IC40-VCC)") (class "Default")
      (node (ref "C234") (pin "1") (pinfunction "1_1") (pintype "passive"))
      (node (ref "IC40") (pin "7") (pinfunction "VCC_7") (pintype "bidirectional"))
      (node (ref "R244") (pin "1") (pinfunction "1_1") (pintype "passive"))
    )
    (net (code "291") (name "Net-(IC41-BOOT1)") (class "Default")
      (node (ref "C203") (pin "2") (pinfunction "2_2") (pintype "passive"))
      (node (ref "IC41") (pin "22") (pinfunction "BOOT1_22") (pintype "power_in"))
    )
    (net (code "292") (name "Net-(IC41-BOOT2)") (class "Default")
      (node (ref "C204") (pin "2") (pinfunction "2_2") (pintype "passive"))
      (node (ref "IC41") (pin "20") (pinfunction "BOOT2_20") (pintype "power_in"))
    )
    (net (code "293") (name "Net-(IC41-CDC)") (class "Default")
      (node (ref "IC41") (pin "16") (pinfunction "CDC_16") (pintype "output"))
      (node (ref "R270") (pin "1") (pinfunction "1_1") (pintype "passive"))
    )
    (net (code "294") (name "Net-(IC41-COMP)") (class "Default")
      (node (ref "C201") (pin "1") (pinfunction "1_1") (pintype "passive"))
      (node (ref "IC41") (pin "18") (pinfunction "COMP_18") (pintype "input"))
      (node (ref "R271") (pin "1") (pinfunction "1_1") (pintype "passive"))
    )
    (net (code "295") (name "Net-(IC41-DITH_SYNC)") (class "Default")
      (node (ref "C200") (pin "1") (pinfunction "1_1") (pintype "passive"))
      (node (ref "IC41") (pin "7") (pinfunction "DITH_SYNC_7") (pintype "input"))
    )
    (net (code "296") (name "Net-(IC41-DR1H)") (class "Default")
      (node (ref "IC41") (pin "2") (pinfunction "DR1H_2") (pintype "output"))
      (node (ref "R274") (pin "1") (pinfunction "1_1") (pintype "passive"))
    )
    (net (code "297") (name "Net-(IC41-DR1L)") (class "Default")
      (node (ref "IC41") (pin "1") (pinfunction "DR1L_1") (pintype "output"))
      (node (ref "R273") (pin "1") (pinfunction "1_1") (pintype "passive"))
    )
    (net (code "298") (name "Net-(IC41-FB)") (class "Default")
      (node (ref "IC41") (pin "14") (pinfunction "FB_14") (pintype "input"))
      (node (ref "R219") (pin "2") (pinfunction "2_2") (pintype "passive"))
      (node (ref "R220") (pin "1") (pinfunction "1_1") (pintype "passive"))
    )
    (net (code "299") (name "Net-(IC41-FSW)") (class "Default")
      (node (ref "IC41") (pin "8") (pinfunction "FSW_8") (pintype "input"))
      (node (ref "R268") (pin "1") (pinfunction "1_1") (pintype "passive"))
    )
    (net (code "300") (name "Net-(IC41-ILIM)") (class "Default")
      (node (ref "IC41") (pin "17") (pinfunction "ILIM_17") (pintype "output"))
      (node (ref "R269") (pin "1") (pinfunction "1_1") (pintype "passive"))
    )
    (net (code "301") (name "Net-(IC41-MODE)") (class "Default")
      (node (ref "IC41") (pin "15") (pinfunction "MODE_15") (pintype "input"))
      (node (ref "R267") (pin "1") (pinfunction "1_1") (pintype "passive"))
    )
    (net (code "302") (name "Net-(IC41-SW1)") (class "Default")
      (node (ref "C203") (pin "1") (pinfunction "1_1") (pintype "passive"))
      (node (ref "IC41") (pin "23") (pinfunction "SW1_23") (pintype "power_in"))
      (node (ref "L9") (pin "1") (pinfunction "1_1") (pintype "passive"))
      (node (ref "T44") (pin "5") (pinfunction "D_5") (pintype "passive"))
      (node (ref "T44") (pin "6") (pinfunction "D_6") (pintype "passive"))
      (node (ref "T44") (pin "7") (pinfunction "D_7") (pintype "passive"))
      (node (ref "T44") (pin "8") (pinfunction "D_8") (pintype "passive"))
      (node (ref "T44") (pin "9") (pinfunction "D_9") (pintype "passive"))
      (node (ref "T45") (pin "1") (pinfunction "S_1") (pintype "passive"))
      (node (ref "T45") (pin "2") (pinfunction "S_2") (pintype "passive"))
      (node (ref "T45") (pin "3") (pinfunction "S_3") (pintype "passive"))
    )
    (net (code "303") (name "Net-(IC41-VCC)") (class "Default")
      (node (ref "C199") (pin "1") (pinfunction "1_1") (pintype "passive"))
      (node (ref "IC41") (pin "19") (pinfunction "VCC_19") (pintype "power_in"))
    )
    (net (code "304") (name "Net-(IC43-AAM)") (class "Default")
      (node (ref "IC43") (pin "1") (pinfunction "AAM_1") (pintype "bidirectional"))
      (node (ref "R256") (pin "1") (pinfunction "1_1") (pintype "passive"))
      (node (ref "R258") (pin "2") (pinfunction "2_2") (pintype "passive"))
    )
    (net (code "305") (name "Net-(IC43-BST)") (class "Default")
      (node (ref "IC43") (pin "5") (pinfunction "BST_5") (pintype "bidirectional"))
      (node (ref "R257") (pin "2") (pinfunction "2_2") (pintype "passive"))
    )
    (net (code "306") (name "Net-(IC43-EN)") (class "Default")
      (node (ref "IC43") (pin "6") (pinfunction "EN_6") (pintype "bidirectional"))
      (node (ref "R254") (pin "2") (pinfunction "2_2") (pintype "passive"))
    )
    (net (code "307") (name "Net-(IC43-FB)") (class "Default")
      (node (ref "IC43") (pin "8") (pinfunction "FB_8") (pintype "bidirectional"))
      (node (ref "RT3") (pin "1") (pinfunction "1_1") (pintype "passive"))
    )
    (net (code "308") (name "Net-(IC43-SW)") (class "Default")
      (node (ref "C260") (pin "2") (pinfunction "2_2") (pintype "passive"))
      (node (ref "IC43") (pin "3") (pinfunction "SW_3") (pintype "bidirectional"))
      (node (ref "L13") (pin "1") (pinfunction "1_1") (pintype "passive"))
    )
    (net (code "309") (name "Net-(IC43-VCC)") (class "Default")
      (node (ref "C259") (pin "1") (pinfunction "1_1") (pintype "passive"))
      (node (ref "IC43") (pin "7") (pinfunction "VCC_7") (pintype "bidirectional"))
      (node (ref "R258") (pin "1") (pinfunction "1_1") (pintype "passive"))
    )
    (net (code "310") (name "Net-(IC45-AAM)") (class "Default")
      (node (ref "IC45") (pin "1") (pinfunction "AAM_1") (pintype "bidirectional"))
      (node (ref "R264") (pin "1") (pinfunction "1_1") (pintype "passive"))
      (node (ref "R266") (pin "2") (pinfunction "2_2") (pintype "passive"))
    )
    (net (code "311") (name "Net-(IC45-BST)") (class "Default")
      (node (ref "IC45") (pin "5") (pinfunction "BST_5") (pintype "bidirectional"))
      (node (ref "R265") (pin "2") (pinfunction "2_2") (pintype "passive"))
    )
    (net (code "312") (name "Net-(IC45-EN)") (class "Default")
      (node (ref "IC45") (pin "6") (pinfunction "EN_6") (pintype "bidirectional"))
      (node (ref "R263") (pin "2") (pinfunction "2_2") (pintype "passive"))
    )
    (net (code "313") (name "Net-(IC45-FB)") (class "Default")
      (node (ref "IC45") (pin "8") (pinfunction "FB_8") (pintype "bidirectional"))
      (node (ref "RT5") (pin "1") (pinfunction "1_1") (pintype "passive"))
    )
    (net (code "314") (name "Net-(IC45-SW)") (class "Default")
      (node (ref "C274") (pin "2") (pinfunction "2_2") (pintype "passive"))
      (node (ref "IC45") (pin "3") (pinfunction "SW_3") (pintype "bidirectional"))
      (node (ref "L15") (pin "1") (pinfunction "1_1") (pintype "passive"))
    )
    (net (code "315") (name "Net-(IC45-VCC)") (class "Default")
      (node (ref "C273") (pin "1") (pinfunction "1_1") (pintype "passive"))
      (node (ref "IC45") (pin "7") (pinfunction "VCC_7") (pintype "bidirectional"))
      (node (ref "R266") (pin "1") (pinfunction "1_1") (pintype "passive"))
    )
    (net (code "316") (name "Net-(R52-Pad1)") (class "Default")
      (node (ref "R52") (pin "1") (pinfunction "1_1") (pintype "passive"))
      (node (ref "T6") (pin "5") (pinfunction "D_5") (pintype "passive"))
      (node (ref "T6") (pin "6") (pinfunction "D_6") (pintype "passive"))
      (node (ref "T6") (pin "7") (pinfunction "D_7") (pintype "passive"))
      (node (ref "T6") (pin "8") (pinfunction "D_8") (pintype "passive"))
      (node (ref "T6") (pin "9") (pinfunction "D_9") (pintype "passive"))
    )
    (net (code "317") (name "Net-(R54-Pad1)") (class "Default")
      (node (ref "R54") (pin "1") (pinfunction "1_1") (pintype "passive"))
      (node (ref "T7") (pin "1") (pinfunction "S_1") (pintype "passive"))
      (node (ref "T7") (pin "2") (pinfunction "S_2") (pintype "passive"))
      (node (ref "T7") (pin "3") (pinfunction "S_3") (pintype "passive"))
      (node (ref "T8") (pin "1") (pinfunction "S_1") (pintype "passive"))
      (node (ref "T8") (pin "2") (pinfunction "S_2") (pintype "passive"))
      (node (ref "T8") (pin "3") (pinfunction "S_3") (pintype "passive"))
    )
    (net (code "318") (name "Net-(R75-Pad1)") (class "Default")
      (node (ref "R75") (pin "1") (pinfunction "1_1") (pintype "passive"))
      (node (ref "T11") (pin "5") (pinfunction "D_5") (pintype "passive"))
      (node (ref "T11") (pin "6") (pinfunction "D_6") (pintype "passive"))
      (node (ref "T11") (pin "7") (pinfunction "D_7") (pintype "passive"))
      (node (ref "T11") (pin "8") (pinfunction "D_8") (pintype "passive"))
      (node (ref "T11") (pin "9") (pinfunction "D_9") (pintype "passive"))
    )
    (net (code "319") (name "Net-(R77-Pad1)") (class "Default")
      (node (ref "R77") (pin "1") (pinfunction "1_1") (pintype "passive"))
      (node (ref "T12") (pin "1") (pinfunction "S_1") (pintype "passive"))
      (node (ref "T12") (pin "2") (pinfunction "S_2") (pintype "passive"))
      (node (ref "T12") (pin "3") (pinfunction "S_3") (pintype "passive"))
      (node (ref "T13") (pin "1") (pinfunction "S_1") (pintype "passive"))
      (node (ref "T13") (pin "2") (pinfunction "S_2") (pintype "passive"))
      (node (ref "T13") (pin "3") (pinfunction "S_3") (pintype "passive"))
    )
    (net (code "320") (name "Net-(R99-Pad1)") (class "Default")
      (node (ref "R99") (pin "1") (pinfunction "1_1") (pintype "passive"))
      (node (ref "T16") (pin "5") (pinfunction "D_5") (pintype "passive"))
      (node (ref "T16") (pin "6") (pinfunction "D_6") (pintype "passive"))
      (node (ref "T16") (pin "7") (pinfunction "D_7") (pintype "passive"))
      (node (ref "T16") (pin "8") (pinfunction "D_8") (pintype "passive"))
      (node (ref "T16") (pin "9") (pinfunction "D_9") (pintype "passive"))
    )
    (net (code "321") (name "Net-(R101-Pad1)") (class "Default")
      (node (ref "R101") (pin "1") (pinfunction "1_1") (pintype "passive"))
      (node (ref "T17") (pin "1") (pinfunction "S_1") (pintype "passive"))
      (node (ref "T17") (pin "2") (pinfunction "S_2") (pintype "passive"))
      (node (ref "T17") (pin "3") (pinfunction "S_3") (pintype "passive"))
      (node (ref "T18") (pin "1") (pinfunction "S_1") (pintype "passive"))
      (node (ref "T18") (pin "2") (pinfunction "S_2") (pintype "passive"))
      (node (ref "T18") (pin "3") (pinfunction "S_3") (pintype "passive"))
    )
    (net (code "322") (name "Net-(R122-Pad1)") (class "Default")
      (node (ref "R122") (pin "1") (pinfunction "1_1") (pintype "passive"))
      (node (ref "T21") (pin "5") (pinfunction "D_5") (pintype "passive"))
      (node (ref "T21") (pin "6") (pinfunction "D_6") (pintype "passive"))
      (node (ref "T21") (pin "7") (pinfunction "D_7") (pintype "passive"))
      (node (ref "T21") (pin "8") (pinfunction "D_8") (pintype "passive"))
      (node (ref "T21") (pin "9") (pinfunction "D_9") (pintype "passive"))
    )
    (net (code "323") (name "Net-(R124-Pad1)") (class "Default")
      (node (ref "R124") (pin "1") (pinfunction "1_1") (pintype "passive"))
      (node (ref "T22") (pin "1") (pinfunction "S_1") (pintype "passive"))
      (node (ref "T22") (pin "2") (pinfunction "S_2") (pintype "passive"))
      (node (ref "T22") (pin "3") (pinfunction "S_3") (pintype "passive"))
      (node (ref "T23") (pin "1") (pinfunction "S_1") (pintype "passive"))
      (node (ref "T23") (pin "2") (pinfunction "S_2") (pintype "passive"))
      (node (ref "T23") (pin "3") (pinfunction "S_3") (pintype "passive"))
    )
    (net (code "324") (name "Net-(R145-Pad1)") (class "Default")
      (node (ref "R145") (pin "1") (pinfunction "1_1") (pintype "passive"))
      (node (ref "T26") (pin "5") (pinfunction "D_5") (pintype "passive"))
      (node (ref "T26") (pin "6") (pinfunction "D_6") (pintype "passive"))
      (node (ref "T26") (pin "7") (pinfunction "D_7") (pintype "passive"))
      (node (ref "T26") (pin "8") (pinfunction "D_8") (pintype "passive"))
      (node (ref "T26") (pin "9") (pinfunction "D_9") (pintype "passive"))
    )
    (net (code "325") (name "Net-(R147-Pad1)") (class "Default")
      (node (ref "R147") (pin "1") (pinfunction "1_1") (pintype "passive"))
      (node (ref "T27") (pin "1") (pinfunction "S_1") (pintype "passive"))
      (node (ref "T27") (pin "2") (pinfunction "S_2") (pintype "passive"))
      (node (ref "T27") (pin "3") (pinfunction "S_3") (pintype "passive"))
      (node (ref "T28") (pin "1") (pinfunction "S_1") (pintype "passive"))
      (node (ref "T28") (pin "2") (pinfunction "S_2") (pintype "passive"))
      (node (ref "T28") (pin "3") (pinfunction "S_3") (pintype "passive"))
    )
    (net (code "326") (name "Net-(R168-Pad1)") (class "Default")
      (node (ref "R168") (pin "1") (pinfunction "1_1") (pintype "passive"))
      (node (ref "T31") (pin "5") (pinfunction "D_5") (pintype "passive"))
      (node (ref "T31") (pin "6") (pinfunction "D_6") (pintype "passive"))
      (node (ref "T31") (pin "7") (pinfunction "D_7") (pintype "passive"))
      (node (ref "T31") (pin "8") (pinfunction "D_8") (pintype "passive"))
      (node (ref "T31") (pin "9") (pinfunction "D_9") (pintype "passive"))
    )
    (net (code "327") (name "Net-(R170-Pad1)") (class "Default")
      (node (ref "R170") (pin "1") (pinfunction "1_1") (pintype "passive"))
      (node (ref "T32") (pin "1") (pinfunction "S_1") (pintype "passive"))
      (node (ref "T32") (pin "2") (pinfunction "S_2") (pintype "passive"))
      (node (ref "T32") (pin "3") (pinfunction "S_3") (pintype "passive"))
      (node (ref "T33") (pin "1") (pinfunction "S_1") (pintype "passive"))
      (node (ref "T33") (pin "2") (pinfunction "S_2") (pintype "passive"))
      (node (ref "T33") (pin "3") (pinfunction "S_3") (pintype "passive"))
    )
    (net (code "328") (name "Net-(R191-Pad1)") (class "Default")
      (node (ref "R191") (pin "1") (pinfunction "1_1") (pintype "passive"))
      (node (ref "T36") (pin "5") (pinfunction "D_5") (pintype "passive"))
      (node (ref "T36") (pin "6") (pinfunction "D_6") (pintype "passive"))
      (node (ref "T36") (pin "7") (pinfunction "D_7") (pintype "passive"))
      (node (ref "T36") (pin "8") (pinfunction "D_8") (pintype "passive"))
      (node (ref "T36") (pin "9") (pinfunction "D_9") (pintype "passive"))
    )
    (net (code "329") (name "Net-(R193-Pad1)") (class "Default")
      (node (ref "R193") (pin "1") (pinfunction "1_1") (pintype "passive"))
      (node (ref "T37") (pin "1") (pinfunction "S_1") (pintype "passive"))
      (node (ref "T37") (pin "2") (pinfunction "S_2") (pintype "passive"))
      (node (ref "T37") (pin "3") (pinfunction "S_3") (pintype "passive"))
      (node (ref "T38") (pin "1") (pinfunction "S_1") (pintype "passive"))
      (node (ref "T38") (pin "2") (pinfunction "S_2") (pintype "passive"))
      (node (ref "T38") (pin "3") (pinfunction "S_3") (pintype "passive"))
    )
    (net (code "330") (name "Net-(R247-Pad1)") (class "Default")
      (node (ref "R247") (pin "1") (pinfunction "1_1") (pintype "passive"))
      (node (ref "T41") (pin "5") (pinfunction "D_5") (pintype "passive"))
      (node (ref "T41") (pin "6") (pinfunction "D_6") (pintype "passive"))
      (node (ref "T41") (pin "7") (pinfunction "D_7") (pintype "passive"))
      (node (ref "T41") (pin "8") (pinfunction "D_8") (pintype "passive"))
      (node (ref "T41") (pin "9") (pinfunction "D_9") (pintype "passive"))
    )
    (net (code "331") (name "Net-(R259-Pad1)") (class "Default")
      (node (ref "R259") (pin "1") (pinfunction "1_1") (pintype "passive"))
      (node (ref "T42") (pin "1") (pinfunction "S_1") (pintype "passive"))
      (node (ref "T42") (pin "2") (pinfunction "S_2") (pintype "passive"))
      (node (ref "T42") (pin "3") (pinfunction "S_3") (pintype "passive"))
      (node (ref "T43") (pin "1") (pinfunction "S_1") (pintype "passive"))
      (node (ref "T43") (pin "2") (pinfunction "S_2") (pintype "passive"))
      (node (ref "T43") (pin "3") (pinfunction "S_3") (pintype "passive"))
    )
    (net (code "332") (name "Net-(T7-G)") (class "Default")
      (node (ref "R54") (pin "2") (pinfunction "2_2") (pintype "passive"))
      (node (ref "R55") (pin "1") (pinfunction "1_1") (pintype "passive"))
      (node (ref "T7") (pin "4") (pinfunction "G_4") (pintype "passive"))
      (node (ref "T8") (pin "4") (pinfunction "G_4") (pintype "passive"))
    )
    (net (code "333") (name "Net-(T9-G)") (class "Default")
      (node (ref "R64") (pin "2") (pinfunction "2_2") (pintype "passive"))
      (node (ref "T9") (pin "4") (pinfunction "G_4") (pintype "passive"))
    )
    (net (code "334") (name "Net-(T10-G)") (class "Default")
      (node (ref "R65") (pin "2") (pinfunction "2_2") (pintype "passive"))
      (node (ref "T10") (pin "4") (pinfunction "G_4") (pintype "passive"))
    )
    (net (code "335") (name "Net-(T12-G)") (class "Default")
      (node (ref "R77") (pin "2") (pinfunction "2_2") (pintype "passive"))
      (node (ref "R78") (pin "1") (pinfunction "1_1") (pintype "passive"))
      (node (ref "T12") (pin "4") (pinfunction "G_4") (pintype "passive"))
      (node (ref "T13") (pin "4") (pinfunction "G_4") (pintype "passive"))
    )
    (net (code "336") (name "Net-(T14-G)") (class "Default")
      (node (ref "R88") (pin "2") (pinfunction "2_2") (pintype "passive"))
      (node (ref "T14") (pin "4") (pinfunction "G_4") (pintype "passive"))
    )
    (net (code "337") (name "Net-(T15-G)") (class "Default")
      (node (ref "R89") (pin "2") (pinfunction "2_2") (pintype "passive"))
      (node (ref "T15") (pin "4") (pinfunction "G_4") (pintype "passive"))
    )
    (net (code "338") (name "Net-(T17-G)") (class "Default")
      (node (ref "R101") (pin "2") (pinfunction "2_2") (pintype "passive"))
      (node (ref "R102") (pin "1") (pinfunction "1_1") (pintype "passive"))
      (node (ref "T17") (pin "4") (pinfunction "G_4") (pintype "passive"))
      (node (ref "T18") (pin "4") (pinfunction "G_4") (pintype "passive"))
    )
    (net (code "339") (name "Net-(T19-G)") (class "Default")
      (node (ref "R111") (pin "2") (pinfunction "2_2") (pintype "passive"))
      (node (ref "T19") (pin "4") (pinfunction "G_4") (pintype "passive"))
    )
    (net (code "340") (name "Net-(T20-G)") (class "Default")
      (node (ref "R112") (pin "2") (pinfunction "2_2") (pintype "passive"))
      (node (ref "T20") (pin "4") (pinfunction "G_4") (pintype "passive"))
    )
    (net (code "341") (name "Net-(T22-G)") (class "Default")
      (node (ref "R124") (pin "2") (pinfunction "2_2") (pintype "passive"))
      (node (ref "R125") (pin "1") (pinfunction "1_1") (pintype "passive"))
      (node (ref "T22") (pin "4") (pinfunction "G_4") (pintype "passive"))
      (node (ref "T23") (pin "4") (pinfunction "G_4") (pintype "passive"))
    )
    (net (code "342") (name "Net-(T24-G)") (class "Default")
      (node (ref "R134") (pin "2") (pinfunction "2_2") (pintype "passive"))
      (node (ref "T24") (pin "4") (pinfunction "G_4") (pintype "passive"))
    )
    (net (code "343") (name "Net-(T25-G)") (class "Default")
      (node (ref "R135") (pin "2") (pinfunction "2_2") (pintype "passive"))
      (node (ref "T25") (pin "4") (pinfunction "G_4") (pintype "passive"))
    )
    (net (code "344") (name "Net-(T27-G)") (class "Default")
      (node (ref "R147") (pin "2") (pinfunction "2_2") (pintype "passive"))
      (node (ref "R148") (pin "1") (pinfunction "1_1") (pintype "passive"))
      (node (ref "T27") (pin "4") (pinfunction "G_4") (pintype "passive"))
      (node (ref "T28") (pin "4") (pinfunction "G_4") (pintype "passive"))
    )
    (net (code "345") (name "Net-(T29-G)") (class "Default")
      (node (ref "R157") (pin "2") (pinfunction "2_2") (pintype "passive"))
      (node (ref "T29") (pin "4") (pinfunction "G_4") (pintype "passive"))
    )
    (net (code "346") (name "Net-(T30-G)") (class "Default")
      (node (ref "R158") (pin "2") (pinfunction "2_2") (pintype "passive"))
      (node (ref "T30") (pin "4") (pinfunction "G_4") (pintype "passive"))
    )
    (net (code "347") (name "Net-(T32-G)") (class "Default")
      (node (ref "R170") (pin "2") (pinfunction "2_2") (pintype "passive"))
      (node (ref "R171") (pin "1") (pinfunction "1_1") (pintype "passive"))
      (node (ref "T32") (pin "4") (pinfunction "G_4") (pintype "passive"))
      (node (ref "T33") (pin "4") (pinfunction "G_4") (pintype "passive"))
    )
    (net (code "348") (name "Net-(T34-G)") (class "Default")
      (node (ref "R180") (pin "2") (pinfunction "2_2") (pintype "passive"))
      (node (ref "T34") (pin "4") (pinfunction "G_4") (pintype "passive"))
    )
    (net (code "349") (name "Net-(T35-G)") (class "Default")
      (node (ref "R181") (pin "2") (pinfunction "2_2") (pintype "passive"))
      (node (ref "T35") (pin "4") (pinfunction "G_4") (pintype "passive"))
    )
    (net (code "350") (name "Net-(T37-G)") (class "Default")
      (node (ref "R193") (pin "2") (pinfunction "2_2") (pintype "passive"))
      (node (ref "R194") (pin "1") (pinfunction "1_1") (pintype "passive"))
      (node (ref "T37") (pin "4") (pinfunction "G_4") (pintype "passive"))
      (node (ref "T38") (pin "4") (pinfunction "G_4") (pintype "passive"))
    )
    (net (code "351") (name "Net-(T39-G)") (class "Default")
      (node (ref "R203") (pin "2") (pinfunction "2_2") (pintype "passive"))
      (node (ref "T39") (pin "4") (pinfunction "G_4") (pintype "passive"))
    )
    (net (code "352") (name "Net-(T40-G)") (class "Default")
      (node (ref "R204") (pin "2") (pinfunction "2_2") (pintype "passive"))
      (node (ref "T40") (pin "4") (pinfunction "G_4") (pintype "passive"))
    )
    (net (code "353") (name "Net-(T42-G)") (class "Default")
      (node (ref "R259") (pin "2") (pinfunction "2_2") (pintype "passive"))
      (node (ref "R260") (pin "1") (pinfunction "1_1") (pintype "passive"))
      (node (ref "T42") (pin "4") (pinfunction "G_4") (pintype "passive"))
      (node (ref "T43") (pin "4") (pinfunction "G_4") (pintype "passive"))
    )
    (net (code "354") (name "Net-(T44-G)") (class "Default")
      (node (ref "R273") (pin "2") (pinfunction "2_2") (pintype "passive"))
      (node (ref "T44") (pin "4") (pinfunction "G_4") (pintype "passive"))
    )
    (net (code "355") (name "Net-(T45-G)") (class "Default")
      (node (ref "R274") (pin "2") (pinfunction "2_2") (pintype "passive"))
      (node (ref "T45") (pin "4") (pinfunction "G_4") (pintype "passive"))
    )
    (net (code "356") (name "Net-(USB9-CC1)") (class "Default")
      (node (ref "R251") (pin "1") (pinfunction "1_1") (pintype "passive"))
      (node (ref "USB9") (pin "A5") (pinfunction "CC1_A5") (pintype "bidirectional"))
    )
    (net (code "357") (name "Net-(USB9-CC2)") (class "Default")
      (node (ref "R250") (pin "1") (pinfunction "1_1") (pintype "passive"))
      (node (ref "USB9") (pin "B5") (pinfunction "CC2_B5") (pintype "bidirectional"))
    )
    (net (code "358") (name "Net-(X1-2)") (class "Default")
      (node (ref "C178") (pin "1") (pinfunction "1_1") (pintype "passive"))
      (node (ref "R211") (pin "1") (pinfunction "1_1") (pintype "passive"))
      (node (ref "X1") (pin "3") (pinfunction "2_3") (pintype "passive"))
    )
    (net (code "359") (name "OCP1") (class "Default")
      (node (ref "D2") (pin "C") (pinfunction "C_C") (pintype "passive"))
      (node (ref "IC4") (pin "2") (pinfunction "IN_2") (pintype "bidirectional"))
      (node (ref "IC42") (pin "21") (pinfunction "IO1.4_21") (pintype "bidirectional"))
      (node (ref "IC8") (pin "4") (pinfunction "~{FAULT}_4") (pintype "bidirectional"))
      (node (ref "R13") (pin "1") (pinfunction "1_1") (pintype "passive"))
    )
    (net (code "360") (name "OCP2") (class "Default")
      (node (ref "D4") (pin "C") (pinfunction "C_C") (pintype "passive"))
      (node (ref "IC1") (pin "4") (pinfunction "~{FAULT}_4") (pintype "bidirectional"))
      (node (ref "IC42") (pin "22") (pinfunction "IO1.5_22") (pintype "bidirectional"))
      (node (ref "IC5") (pin "2") (pinfunction "IN_2") (pintype "bidirectional"))
      (node (ref "R16") (pin "1") (pinfunction "1_1") (pintype "passive"))
    )
    (net (code "361") (name "OCP3") (class "Default")
      (node (ref "D6") (pin "C") (pinfunction "C_C") (pintype "passive"))
      (node (ref "IC2") (pin "4") (pinfunction "~{FAULT}_4") (pintype "bidirectional"))
      (node (ref "IC42") (pin "23") (pinfunction "IO1.6_23") (pintype "bidirectional"))
      (node (ref "IC6") (pin "2") (pinfunction "IN_2") (pintype "bidirectional"))
      (node (ref "R19") (pin "1") (pinfunction "1_1") (pintype "passive"))
    )
    (net (code "362") (name "OCP4") (class "Default")
      (node (ref "D8") (pin "C") (pinfunction "C_C") (pintype "passive"))
      (node (ref "IC3") (pin "4") (pinfunction "~{FAULT}_4") (pintype "bidirectional"))
      (node (ref "IC42") (pin "24") (pinfunction "IO1.7_24") (pintype "bidirectional"))
      (node (ref "IC7") (pin "2") (pinfunction "IN_2") (pintype "bidirectional"))
      (node (ref "R22") (pin "1") (pinfunction "1_1") (pintype "passive"))
    )
    (net (code "363") (name "QSPI_SCLK") (class "Default")
      (node (ref "IC26") (pin "52") (pinfunction "QSPI_SCLK_52") (pintype "bidirectional"))
      (node (ref "IC27") (pin "6") (pinfunction "CLK_6") (pintype "bidirectional"))
    )
    (net (code "364") (name "QSPI_SD0") (class "Default")
      (node (ref "IC26") (pin "53") (pinfunction "QSPI_SD0_53") (pintype "bidirectional"))
      (node (ref "IC27") (pin "5") (pinfunction "DI/IO0_5") (pintype "bidirectional"))
    )
    (net (code "365") (name "QSPI_SD1") (class "Default")
      (node (ref "IC26") (pin "55") (pinfunction "QSPI_SD1_55") (pintype "bidirectional"))
      (node (ref "IC27") (pin "2") (pinfunction "DO/IO1_2") (pintype "bidirectional"))
    )
    (net (code "366") (name "QSPI_SD2") (class "Default")
      (node (ref "IC26") (pin "54") (pinfunction "QSPI_SD2_54") (pintype "bidirectional"))
      (node (ref "IC27") (pin "3") (pinfunction "~{WP}/IO2_3") (pintype "bidirectional"))
    )
    (net (code "367") (name "QSPI_SD3") (class "Default")
      (node (ref "IC26") (pin "51") (pinfunction "QSPI_SD3_51") (pintype "bidirectional"))
      (node (ref "IC27") (pin "7") (pinfunction "~{HOLD}/IO3_7") (pintype "bidirectional"))
    )
    (net (code "368") (name "RCT") (class "Default")
      (node (ref "C214") (pin "1") (pinfunction "1_1") (pintype "passive"))
      (node (ref "ETH1") (pin "5") (pinfunction "RCT_5") (pintype "passive"))
      (node (ref "R230") (pin "1") (pinfunction "1_1") (pintype "passive"))
      (node (ref "R231") (pin "1") (pinfunction "1_1") (pintype "passive"))
    )
    (net (code "369") (name "RDC_RD_N") (class "Default")
      (node (ref "C215") (pin "1") (pinfunction "1_1") (pintype "passive"))
      (node (ref "R229") (pin "2") (pinfunction "2_2") (pintype "passive"))
      (node (ref "R230") (pin "2") (pinfunction "2_2") (pintype "passive"))
    )
    (net (code "370") (name "RDC_RD_P") (class "Default")
      (node (ref "C216") (pin "1") (pinfunction "1_1") (pintype "passive"))
      (node (ref "R228") (pin "2") (pinfunction "2_2") (pintype "passive"))
      (node (ref "R231") (pin "2") (pinfunction "2_2") (pintype "passive"))
    )
    (net (code "371") (name "RD_N") (class "Default")
      (node (ref "C215") (pin "2") (pinfunction "2_2") (pintype "passive"))
      (node (ref "ETH1") (pin "6") (pinfunction "RD-_6") (pintype "passive"))
    )
    (net (code "372") (name "RD_P") (class "Default")
      (node (ref "C216") (pin "2") (pinfunction "2_2") (pintype "passive"))
      (node (ref "ETH1") (pin "4") (pinfunction "RD+_4") (pintype "passive"))
    )
    (net (code "373") (name "RP_XI") (class "Default")
      (node (ref "C177") (pin "1") (pinfunction "1_1") (pintype "passive"))
      (node (ref "IC26") (pin "20") (pinfunction "XIN_20") (pintype "bidirectional"))
      (node (ref "X1") (pin "1") (pinfunction "1_1") (pintype "passive"))
    )
    (net (code "374") (name "RP_XO") (class "Default")
      (node (ref "IC26") (pin "21") (pinfunction "XOUT_21") (pintype "bidirectional"))
      (node (ref "R211") (pin "2") (pinfunction "2_2") (pintype "passive"))
    )
    (net (code "375") (name "RUN") (class "Default")
      (node (ref "IC26") (pin "26") (pinfunction "RUN_26") (pintype "bidirectional"))
      (node (ref "R208") (pin "2") (pinfunction "2_2") (pintype "passive"))
      (node (ref "RESET") (pin "2") (pinfunction "2_2") (pintype "passive"))
      (node (ref "RESET") (pin "4") (pinfunction "4_4") (pintype "passive"))
    )
    (net (code "376") (name "RX_RD_N") (class "Default")
      (node (ref "IC39") (pin "5") (pinfunction "RXN_5") (pintype "input"))
      (node (ref "R229") (pin "1") (pinfunction "1_1") (pintype "passive"))
    )
    (net (code "377") (name "RX_RD_P") (class "Default")
      (node (ref "IC39") (pin "6") (pinfunction "RXP_6") (pintype "input"))
      (node (ref "R228") (pin "1") (pinfunction "1_1") (pintype "passive"))
    )
    (net (code "378") (name "SWCLK") (class "Default")
      (node (ref "IC26") (pin "24") (pinfunction "SWCLK_24") (pintype "bidirectional"))
    )
    (net (code "379") (name "SWDIO") (class "Default")
      (node (ref "IC26") (pin "25") (pinfunction "SWDIO_25") (pintype "bidirectional"))
    )
    (net (code "380") (name "TCA0_I2C_SCL") (class "Default")
      (node (ref "IC10") (pin "4") (pinfunction "SCL_4") (pintype "input"))
      (node (ref "IC38") (pin "2") (pinfunction "SC0_2") (pintype "bidirectional"))
      (node (ref "IC9") (pin "4") (pinfunction "SCL_4") (pintype "input"))
      (node (ref "R215") (pin "3") (pinfunction "3_3") (pintype "passive"))
    )
    (net (code "381") (name "TCA0_I2C_SDA") (class "Default")
      (node (ref "IC10") (pin "5") (pinfunction "SDA_5") (pintype "bidirectional"))
      (node (ref "IC38") (pin "1") (pinfunction "SD0_1") (pintype "bidirectional"))
      (node (ref "IC9") (pin "5") (pinfunction "SDA_5") (pintype "bidirectional"))
      (node (ref "R215") (pin "4") (pinfunction "4_4") (pintype "passive"))
    )
    (net (code "382") (name "TCA1_I2C_SCL") (class "Default")
      (node (ref "IC11") (pin "4") (pinfunction "SCL_4") (pintype "input"))
      (node (ref "IC14") (pin "4") (pinfunction "SCL_4") (pintype "input"))
      (node (ref "IC38") (pin "4") (pinfunction "SC1_4") (pintype "bidirectional"))
      (node (ref "R215") (pin "1") (pinfunction "1_1") (pintype "passive"))
    )
    (net (code "383") (name "TCA1_I2C_SDA") (class "Default")
      (node (ref "IC11") (pin "5") (pinfunction "SDA_5") (pintype "bidirectional"))
      (node (ref "IC14") (pin "5") (pinfunction "SDA_5") (pintype "bidirectional"))
      (node (ref "IC38") (pin "3") (pinfunction "SD1_3") (pintype "bidirectional"))
      (node (ref "R215") (pin "2") (pinfunction "2_2") (pintype "passive"))
    )
    (net (code "384") (name "TCA2_I2C_SCL") (class "Default")
      (node (ref "IC17") (pin "4") (pinfunction "SCL_4") (pintype "input"))
      (node (ref "IC20") (pin "4") (pinfunction "SCL_4") (pintype "input"))
      (node (ref "IC38") (pin "6") (pinfunction "SC2_6") (pintype "bidirectional"))
      (node (ref "R216") (pin "3") (pinfunction "3_3") (pintype "passive"))
    )
    (net (code "385") (name "TCA2_I2C_SDA") (class "Default")
      (node (ref "IC17") (pin "5") (pinfunction "SDA_5") (pintype "bidirectional"))
      (node (ref "IC20") (pin "5") (pinfunction "SDA_5") (pintype "bidirectional"))
      (node (ref "IC38") (pin "5") (pinfunction "SD2_5") (pintype "bidirectional"))
      (node (ref "R216") (pin "4") (pinfunction "4_4") (pintype "passive"))
    )
    (net (code "386") (name "TCA3_I2C_SCL") (class "Default")
      (node (ref "IC23") (pin "4") (pinfunction "SCL_4") (pintype "input"))
      (node (ref "IC30") (pin "4") (pinfunction "SCL_4") (pintype "input"))
      (node (ref "IC38") (pin "8") (pinfunction "SC3_8") (pintype "bidirectional"))
      (node (ref "R216") (pin "1") (pinfunction "1_1") (pintype "passive"))
    )
    (net (code "387") (name "TCA3_I2C_SDA") (class "Default")
      (node (ref "IC23") (pin "5") (pinfunction "SDA_5") (pintype "bidirectional"))
      (node (ref "IC30") (pin "5") (pinfunction "SDA_5") (pintype "bidirectional"))
      (node (ref "IC38") (pin "7") (pinfunction "SD3_7") (pintype "bidirectional"))
      (node (ref "R216") (pin "2") (pinfunction "2_2") (pintype "passive"))
    )
    (net (code "388") (name "TCA4_I2C_SCL") (class "Default")
      (node (ref "IC13") (pin "5") (pinfunction "SCL_5") (pintype "bidirectional"))
      (node (ref "IC16") (pin "5") (pinfunction "SCL_5") (pintype "bidirectional"))
      (node (ref "IC22") (pin "5") (pinfunction "SCL_5") (pintype "bidirectional"))
      (node (ref "IC25") (pin "5") (pinfunction "SCL_5") (pintype "bidirectional"))
      (node (ref "IC38") (pin "11") (pinfunction "SC4_11") (pintype "bidirectional"))
      (node (ref "R217") (pin "3") (pinfunction "3_3") (pintype "passive"))
    )
    (net (code "389") (name "TCA4_I2C_SDA") (class "Default")
      (node (ref "IC13") (pin "6") (pinfunction "SDA_6") (pintype "bidirectional"))
      (node (ref "IC16") (pin "6") (pinfunction "SDA_6") (pintype "bidirectional"))
      (node (ref "IC22") (pin "6") (pinfunction "SDA_6") (pintype "bidirectional"))
      (node (ref "IC25") (pin "6") (pinfunction "SDA_6") (pintype "bidirectional"))
      (node (ref "IC38") (pin "10") (pinfunction "SD4_10") (pintype "bidirectional"))
      (node (ref "R217") (pin "4") (pinfunction "4_4") (pintype "passive"))
    )
    (net (code "390") (name "TCA5_I2C_SCL") (class "Default")
      (node (ref "IC19") (pin "5") (pinfunction "SCL_5") (pintype "bidirectional"))
      (node (ref "IC33") (pin "5") (pinfunction "SCL_5") (pintype "bidirectional"))
      (node (ref "IC36") (pin "5") (pinfunction "SCL_5") (pintype "bidirectional"))
      (node (ref "IC38") (pin "13") (pinfunction "SC5_13") (pintype "bidirectional"))
      (node (ref "IC44") (pin "5") (pinfunction "SCL_5") (pintype "bidirectional"))
      (node (ref "R217") (pin "1") (pinfunction "1_1") (pintype "passive"))
    )
    (net (code "391") (name "TCA5_I2C_SDA") (class "Default")
      (node (ref "IC19") (pin "6") (pinfunction "SDA_6") (pintype "bidirectional"))
      (node (ref "IC33") (pin "6") (pinfunction "SDA_6") (pintype "bidirectional"))
      (node (ref "IC36") (pin "6") (pinfunction "SDA_6") (pintype "bidirectional"))
      (node (ref "IC38") (pin "12") (pinfunction "SD5_12") (pintype "bidirectional"))
      (node (ref "IC44") (pin "6") (pinfunction "SDA_6") (pintype "bidirectional"))
      (node (ref "R217") (pin "2") (pinfunction "2_2") (pintype "passive"))
    )
    (net (code "392") (name "TCA6_I2C_SCL") (class "Default")
      (node (ref "IC38") (pin "15") (pinfunction "SC6_15") (pintype "bidirectional"))
    )
    (net (code "393") (name "TCA6_I2C_SDA") (class "Default")
      (node (ref "IC38") (pin "14") (pinfunction "SD6_14") (pintype "bidirectional"))
    )
    (net (code "394") (name "TCA7_I2C_SCL") (class "Default")
      (node (ref "IC38") (pin "17") (pinfunction "SC7_17") (pintype "bidirectional"))
    )
    (net (code "395") (name "TCA7_I2C_SDA") (class "Default")
      (node (ref "IC38") (pin "16") (pinfunction "SD7_16") (pintype "bidirectional"))
    )
    (net (code "396") (name "TCT") (class "Default")
      (node (ref "C230") (pin "1") (pinfunction "1_1") (pintype "passive"))
      (node (ref "ETH1") (pin "2") (pinfunction "TCT_2") (pintype "passive"))
      (node (ref "R239") (pin "1") (pinfunction "1_1") (pintype "passive"))
    )
    (net (code "397") (name "TD_N") (class "Default")
      (node (ref "ETH1") (pin "3") (pinfunction "TD-_3") (pintype "passive"))
      (node (ref "R227") (pin "2") (pinfunction "2_2") (pintype "passive"))
      (node (ref "R233") (pin "1") (pinfunction "1_1") (pintype "passive"))
    )
    (net (code "398") (name "TD_P") (class "Default")
      (node (ref "ETH1") (pin "1") (pinfunction "TD+_1") (pintype "passive"))
      (node (ref "R226") (pin "2") (pinfunction "2_2") (pintype "passive"))
      (node (ref "R232") (pin "1") (pinfunction "1_1") (pintype "passive"))
    )
    (net (code "399") (name "TX_TD_N") (class "Default")
      (node (ref "IC39") (pin "1") (pinfunction "TXN_1") (pintype "output"))
      (node (ref "R227") (pin "1") (pinfunction "1_1") (pintype "passive"))
    )
    (net (code "400") (name "TX_TD_P") (class "Default")
      (node (ref "IC39") (pin "2") (pinfunction "TXP_2") (pintype "output"))
      (node (ref "R226") (pin "1") (pinfunction "1_1") (pintype "passive"))
    )
    (net (code "401") (name "UART0_RX") (class "Default")
      (node (ref "IC26") (pin "3") (pinfunction "GPIO1_3") (pintype "bidirectional"))
    )
    (net (code "402") (name "UART0_TX") (class "Default")
      (node (ref "IC26") (pin "2") (pinfunction "GPIO0_2") (pintype "bidirectional"))
    )
    (net (code "403") (name "USBA1_EN") (class "Default")
      (node (ref "IC42") (pin "17") (pinfunction "IO1.0_17") (pintype "bidirectional"))
      (node (ref "IC8") (pin "3") (pinfunction "EN_3") (pintype "bidirectional"))
      (node (ref "R1") (pin "2") (pinfunction "2_2") (pintype "passive"))
    )
    (net (code "404") (name "USBA2_EN") (class "Default")
      (node (ref "IC1") (pin "3") (pinfunction "EN_3") (pintype "bidirectional"))
      (node (ref "IC42") (pin "18") (pinfunction "IO1.1_18") (pintype "bidirectional"))
      (node (ref "R4") (pin "2") (pinfunction "2_2") (pintype "passive"))
    )
    (net (code "405") (name "USBA3_EN") (class "Default")
      (node (ref "IC2") (pin "3") (pinfunction "EN_3") (pintype "bidirectional"))
      (node (ref "IC42") (pin "19") (pinfunction "IO1.2_19") (pintype "bidirectional"))
      (node (ref "R7") (pin "2") (pinfunction "2_2") (pintype "passive"))
    )
    (net (code "406") (name "USBA4_EN") (class "Default")
      (node (ref "IC3") (pin "3") (pinfunction "EN_3") (pintype "bidirectional"))
      (node (ref "IC42") (pin "20") (pinfunction "IO1.3_20") (pintype "bidirectional"))
      (node (ref "R10") (pin "2") (pinfunction "2_2") (pintype "passive"))
    )
    (net (code "407") (name "USB_BOOT") (class "Default")
      (node (ref "BOOT") (pin "1") (pinfunction "1_1") (pintype "passive"))
      (node (ref "BOOT") (pin "3") (pinfunction "3_3") (pintype "passive"))
      (node (ref "R210") (pin "1") (pinfunction "1_1") (pintype "passive"))
    )
    (net (code "408") (name "USB_DP_N") (class "Default")
      (node (ref "ESD1") (pin "3") (pinfunction "C2_3") (pintype "bidirectional"))
      (node (ref "R205") (pin "1") (pinfunction "1_1") (pintype "passive"))
      (node (ref "USB9") (pin "A7") (pinfunction "D-_A7") (pintype "bidirectional"))
      (node (ref "USB9") (pin "B7") (pinfunction "D-_B7") (pintype "bidirectional"))
    )
    (net (code "409") (name "USB_DP_P") (class "Default")
      (node (ref "ESD1") (pin "2") (pinfunction "C1_2") (pintype "bidirectional"))
      (node (ref "R206") (pin "1") (pinfunction "1_1") (pintype "passive"))
      (node (ref "USB9") (pin "A6") (pinfunction "D+_A6") (pintype "bidirectional"))
      (node (ref "USB9") (pin "B6") (pinfunction "D+_B6") (pintype "bidirectional"))
    )
    (net (code "410") (name "VBUS") (class "Default")
      (node (ref "C247") (pin "1") (pinfunction "1_1") (pintype "passive"))
      (node (ref "C248") (pin "1") (pinfunction "1_1") (pintype "passive"))
      (node (ref "ESD1") (pin "4") (pinfunction "C3_4") (pintype "bidirectional"))
      (node (ref "R249") (pin "1") (pinfunction "1_1") (pintype "passive"))
      (node (ref "USB9") (pin "VBUS1") (pinfunction "VBUS_VBUS1") (pintype "power_in"))
      (node (ref "USB9") (pin "VBUS2") (pinfunction "VBUS_VBUS2") (pintype "power_in"))
    )
    (net (code "411") (name "VBUS_USBA1") (class "Default")
      (node (ref "C83") (pin "1") (pinfunction "1_1") (pintype "passive"))
      (node (ref "C84") (pin "1") (pinfunction "1_1") (pintype "passive"))
      (node (ref "C85") (pin "1") (pinfunction "1_1") (pintype "passive"))
      (node (ref "IC8") (pin "6") (pinfunction "OUT_6") (pintype "bidirectional"))
      (node (ref "USBA_1-2") (pin "1") (pinfunction "VBUS_1") (pintype "passive"))
      (node (ref "VUSBA1") (pin "TP") (pinfunction "TP_TP") (pintype "input"))
    )
    (net (code "412") (name "VBUS_USBA2") (class "Default")
      (node (ref "C3") (pin "1") (pinfunction "1_1") (pintype "passive"))
      (node (ref "C4") (pin "1") (pinfunction "1_1") (pintype "passive"))
      (node (ref "C5") (pin "1") (pinfunction "1_1") (pintype "passive"))
      (node (ref "IC1") (pin "6") (pinfunction "OUT_6") (pintype "bidirectional"))
      (node (ref "USBA_1-2") (pin "5") (pinfunction "VBUS_5") (pintype "passive"))
      (node (ref "VUSBA2") (pin "TP") (pinfunction "TP_TP") (pintype "input"))
    )
    (net (code "413") (name "VBUS_USBA3") (class "Default")
      (node (ref "C10") (pin "1") (pinfunction "1_1") (pintype "passive"))
      (node (ref "C8") (pin "1") (pinfunction "1_1") (pintype "passive"))
      (node (ref "C9") (pin "1") (pinfunction "1_1") (pintype "passive"))
      (node (ref "IC2") (pin "6") (pinfunction "OUT_6") (pintype "bidirectional"))
      (node (ref "USBA_3-4") (pin "1") (pinfunction "VBUS_1") (pintype "passive"))
      (node (ref "VUSBA3") (pin "TP") (pinfunction "TP_TP") (pintype "input"))
    )
    (net (code "414") (name "VBUS_USBA4") (class "Default")
      (node (ref "C13") (pin "1") (pinfunction "1_1") (pintype "passive"))
      (node (ref "C14") (pin "1") (pinfunction "1_1") (pintype "passive"))
      (node (ref "C15") (pin "1") (pinfunction "1_1") (pintype "passive"))
      (node (ref "IC3") (pin "6") (pinfunction "OUT_6") (pintype "bidirectional"))
      (node (ref "USBA_3-4") (pin "5") (pinfunction "VBUS_5") (pintype "passive"))
      (node (ref "VUSBA4") (pin "TP") (pinfunction "TP_TP") (pintype "input"))
    )
    (net (code "415") (name "VOUT_PORT1") (class "Default")
      (node (ref "C51") (pin "1") (pinfunction "1_1") (pintype "passive"))
      (node (ref "C52") (pin "1") (pinfunction "1_1") (pintype "passive"))
      (node (ref "C53") (pin "1") (pinfunction "1_1") (pintype "passive"))
      (node (ref "C54") (pin "1") (pinfunction "1_1") (pintype "passive"))
      (node (ref "IC12") (pin "11") (pinfunction "VOUT_11") (pintype "power_in"))
      (node (ref "IC12") (pin "12") (pinfunction "ISP_12") (pintype "input"))
      (node (ref "IC12") (pin "26") (pinfunction "VOUT_26") (pintype "power_in"))
      (node (ref "R63") (pin "1") (pinfunction "1_1") (pintype "passive"))
    )
    (net (code "416") (name "VOUT_PORT2") (class "Default")
      (node (ref "C70") (pin "1") (pinfunction "1_1") (pintype "passive"))
      (node (ref "C71") (pin "1") (pinfunction "1_1") (pintype "passive"))
      (node (ref "C72") (pin "1") (pinfunction "1_1") (pintype "passive"))
      (node (ref "C73") (pin "1") (pinfunction "1_1") (pintype "passive"))
      (node (ref "IC15") (pin "11") (pinfunction "VOUT_11") (pintype "power_in"))
      (node (ref "IC15") (pin "12") (pinfunction "ISP_12") (pintype "input"))
      (node (ref "IC15") (pin "26") (pinfunction "VOUT_26") (pintype "power_in"))
      (node (ref "R87") (pin "1") (pinfunction "1_1") (pintype "passive"))
    )
    (net (code "417") (name "VOUT_PORT3") (class "Default")
      (node (ref "C131") (pin "1") (pinfunction "1_1") (pintype "passive"))
      (node (ref "C132") (pin "1") (pinfunction "1_1") (pintype "passive"))
      (node (ref "C133") (pin "1") (pinfunction "1_1") (pintype "passive"))
      (node (ref "C134") (pin "1") (pinfunction "1_1") (pintype "passive"))
      (node (ref "IC24") (pin "11") (pinfunction "VOUT_11") (pintype "power_in"))
      (node (ref "IC24") (pin "12") (pinfunction "ISP_12") (pintype "input"))
      (node (ref "IC24") (pin "26") (pinfunction "VOUT_26") (pintype "power_in"))
      (node (ref "R156") (pin "1") (pinfunction "1_1") (pintype "passive"))
    )
    (net (code "418") (name "VOUT_PORT4") (class "Default")
      (node (ref "C112") (pin "1") (pinfunction "1_1") (pintype "passive"))
      (node (ref "C113") (pin "1") (pinfunction "1_1") (pintype "passive"))
      (node (ref "C114") (pin "1") (pinfunction "1_1") (pintype "passive"))
      (node (ref "C115") (pin "1") (pinfunction "1_1") (pintype "passive"))
      (node (ref "IC21") (pin "11") (pinfunction "VOUT_11") (pintype "power_in"))
      (node (ref "IC21") (pin "12") (pinfunction "ISP_12") (pintype "input"))
      (node (ref "IC21") (pin "26") (pinfunction "VOUT_26") (pintype "power_in"))
      (node (ref "R133") (pin "1") (pinfunction "1_1") (pintype "passive"))
    )
    (net (code "419") (name "VOUT_PORT5") (class "Default")
      (node (ref "C93") (pin "1") (pinfunction "1_1") (pintype "passive"))
      (node (ref "C94") (pin "1") (pinfunction "1_1") (pintype "passive"))
      (node (ref "C95") (pin "1") (pinfunction "1_1") (pintype "passive"))
      (node (ref "C96") (pin "1") (pinfunction "1_1") (pintype "passive"))
      (node (ref "IC18") (pin "11") (pinfunction "VOUT_11") (pintype "power_in"))
      (node (ref "IC18") (pin "12") (pinfunction "ISP_12") (pintype "input"))
      (node (ref "IC18") (pin "26") (pinfunction "VOUT_26") (pintype "power_in"))
      (node (ref "R110") (pin "1") (pinfunction "1_1") (pintype "passive"))
    )
    (net (code "420") (name "VOUT_PORT6") (class "Default")
      (node (ref "C150") (pin "1") (pinfunction "1_1") (pintype "passive"))
      (node (ref "C151") (pin "1") (pinfunction "1_1") (pintype "passive"))
      (node (ref "C152") (pin "1") (pinfunction "1_1") (pintype "passive"))
      (node (ref "C153") (pin "1") (pinfunction "1_1") (pintype "passive"))
      (node (ref "IC32") (pin "11") (pinfunction "VOUT_11") (pintype "power_in"))
      (node (ref "IC32") (pin "12") (pinfunction "ISP_12") (pintype "input"))
      (node (ref "IC32") (pin "26") (pinfunction "VOUT_26") (pintype "power_in"))
      (node (ref "R179") (pin "1") (pinfunction "1_1") (pintype "passive"))
    )
    (net (code "421") (name "VOUT_PORT7") (class "Default")
      (node (ref "C169") (pin "1") (pinfunction "1_1") (pintype "passive"))
      (node (ref "C170") (pin "1") (pinfunction "1_1") (pintype "passive"))
      (node (ref "C171") (pin "1") (pinfunction "1_1") (pintype "passive"))
      (node (ref "C172") (pin "1") (pinfunction "1_1") (pintype "passive"))
      (node (ref "IC35") (pin "11") (pinfunction "VOUT_11") (pintype "power_in"))
      (node (ref "IC35") (pin "12") (pinfunction "ISP_12") (pintype "input"))
      (node (ref "IC35") (pin "26") (pinfunction "VOUT_26") (pintype "power_in"))
      (node (ref "R202") (pin "1") (pinfunction "1_1") (pintype "passive"))
    )
    (net (code "422") (name "VOUT_PORT8") (class "Default")
      (node (ref "C209") (pin "1") (pinfunction "1_1") (pintype "passive"))
      (node (ref "C210") (pin "1") (pinfunction "1_1") (pintype "passive"))
      (node (ref "C211") (pin "1") (pinfunction "1_1") (pintype "passive"))
      (node (ref "C240") (pin "1") (pinfunction "1_1") (pintype "passive"))
      (node (ref "IC41") (pin "11") (pinfunction "VOUT_11") (pintype "power_in"))
      (node (ref "IC41") (pin "12") (pinfunction "ISP_12") (pintype "input"))
      (node (ref "IC41") (pin "26") (pinfunction "VOUT_26") (pintype "power_in"))
      (node (ref "R272") (pin "1") (pinfunction "1_1") (pintype "passive"))
    )
    (net (code "423") (name "VSRC1") (class "Default")
      (node (ref "C39") (pin "1") (pinfunction "1_1") (pintype "passive"))
      (node (ref "IC12") (pin "13") (pinfunction "ISN_13") (pintype "input"))
      (node (ref "IC9") (pin "1") (pinfunction "VDD_1") (pintype "power_in"))
      (node (ref "R5") (pin "1") (pinfunction "1_1") (pintype "passive"))
      (node (ref "R53") (pin "1") (pinfunction "1_1") (pintype "passive"))
      (node (ref "R63") (pin "2") (pinfunction "2_2") (pintype "passive"))
      (node (ref "T6") (pin "1") (pinfunction "S_1") (pintype "passive"))
      (node (ref "T6") (pin "2") (pinfunction "S_2") (pintype "passive"))
      (node (ref "T6") (pin "3") (pinfunction "S_3") (pintype "passive"))
      (node (ref "T7") (pin "5") (pinfunction "D_5") (pintype "passive"))
      (node (ref "T7") (pin "6") (pinfunction "D_6") (pintype "passive"))
      (node (ref "T7") (pin "7") (pinfunction "D_7") (pintype "passive"))
      (node (ref "T7") (pin "8") (pinfunction "D_8") (pintype "passive"))
      (node (ref "T7") (pin "9") (pinfunction "D_9") (pintype "passive"))
    )
    (net (code "424") (name "VSRC2") (class "Default")
      (node (ref "C58") (pin "1") (pinfunction "1_1") (pintype "passive"))
      (node (ref "IC10") (pin "1") (pinfunction "VDD_1") (pintype "power_in"))
      (node (ref "IC15") (pin "13") (pinfunction "ISN_13") (pintype "input"))
      (node (ref "R67") (pin "1") (pinfunction "1_1") (pintype "passive"))
      (node (ref "R76") (pin "1") (pinfunction "1_1") (pintype "passive"))
      (node (ref "R87") (pin "2") (pinfunction "2_2") (pintype "passive"))
      (node (ref "T11") (pin "1") (pinfunction "S_1") (pintype "passive"))
      (node (ref "T11") (pin "2") (pinfunction "S_2") (pintype "passive"))
      (node (ref "T11") (pin "3") (pinfunction "S_3") (pintype "passive"))
      (node (ref "T12") (pin "5") (pinfunction "D_5") (pintype "passive"))
      (node (ref "T12") (pin "6") (pinfunction "D_6") (pintype "passive"))
      (node (ref "T12") (pin "7") (pinfunction "D_7") (pintype "passive"))
      (node (ref "T12") (pin "8") (pinfunction "D_8") (pintype "passive"))
      (node (ref "T12") (pin "9") (pinfunction "D_9") (pintype "passive"))
    )
    (net (code "425") (name "VSRC3") (class "Default")
      (node (ref "C119") (pin "1") (pinfunction "1_1") (pintype "passive"))
      (node (ref "IC11") (pin "1") (pinfunction "VDD_1") (pintype "power_in"))
      (node (ref "IC24") (pin "13") (pinfunction "ISN_13") (pintype "input"))
      (node (ref "R137") (pin "1") (pinfunction "1_1") (pintype "passive"))
      (node (ref "R146") (pin "1") (pinfunction "1_1") (pintype "passive"))
      (node (ref "R156") (pin "2") (pinfunction "2_2") (pintype "passive"))
      (node (ref "T26") (pin "1") (pinfunction "S_1") (pintype "passive"))
      (node (ref "T26") (pin "2") (pinfunction "S_2") (pintype "passive"))
      (node (ref "T26") (pin "3") (pinfunction "S_3") (pintype "passive"))
      (node (ref "T27") (pin "5") (pinfunction "D_5") (pintype "passive"))
      (node (ref "T27") (pin "6") (pinfunction "D_6") (pintype "passive"))
      (node (ref "T27") (pin "7") (pinfunction "D_7") (pintype "passive"))
      (node (ref "T27") (pin "8") (pinfunction "D_8") (pintype "passive"))
      (node (ref "T27") (pin "9") (pinfunction "D_9") (pintype "passive"))
    )
    (net (code "426") (name "VSRC4") (class "Default")
      (node (ref "C100") (pin "1") (pinfunction "1_1") (pintype "passive"))
      (node (ref "IC14") (pin "1") (pinfunction "VDD_1") (pintype "power_in"))
      (node (ref "IC21") (pin "13") (pinfunction "ISN_13") (pintype "input"))
      (node (ref "R114") (pin "1") (pinfunction "1_1") (pintype "passive"))
      (node (ref "R123") (pin "1") (pinfunction "1_1") (pintype "passive"))
      (node (ref "R133") (pin "2") (pinfunction "2_2") (pintype "passive"))
      (node (ref "T21") (pin "1") (pinfunction "S_1") (pintype "passive"))
      (node (ref "T21") (pin "2") (pinfunction "S_2") (pintype "passive"))
      (node (ref "T21") (pin "3") (pinfunction "S_3") (pintype "passive"))
      (node (ref "T22") (pin "5") (pinfunction "D_5") (pintype "passive"))
      (node (ref "T22") (pin "6") (pinfunction "D_6") (pintype "passive"))
      (node (ref "T22") (pin "7") (pinfunction "D_7") (pintype "passive"))
      (node (ref "T22") (pin "8") (pinfunction "D_8") (pintype "passive"))
      (node (ref "T22") (pin "9") (pinfunction "D_9") (pintype "passive"))
    )
    (net (code "427") (name "VSRC5") (class "Default")
      (node (ref "C77") (pin "1") (pinfunction "1_1") (pintype "passive"))
      (node (ref "IC17") (pin "1") (pinfunction "VDD_1") (pintype "power_in"))
      (node (ref "IC18") (pin "13") (pinfunction "ISN_13") (pintype "input"))
      (node (ref "R100") (pin "1") (pinfunction "1_1") (pintype "passive"))
      (node (ref "R110") (pin "2") (pinfunction "2_2") (pintype "passive"))
      (node (ref "R91") (pin "1") (pinfunction "1_1") (pintype "passive"))
      (node (ref "T16") (pin "1") (pinfunction "S_1") (pintype "passive"))
      (node (ref "T16") (pin "2") (pinfunction "S_2") (pintype "passive"))
      (node (ref "T16") (pin "3") (pinfunction "S_3") (pintype "passive"))
      (node (ref "T17") (pin "5") (pinfunction "D_5") (pintype "passive"))
      (node (ref "T17") (pin "6") (pinfunction "D_6") (pintype "passive"))
      (node (ref "T17") (pin "7") (pinfunction "D_7") (pintype "passive"))
      (node (ref "T17") (pin "8") (pinfunction "D_8") (pintype "passive"))
      (node (ref "T17") (pin "9") (pinfunction "D_9") (pintype "passive"))
    )
    (net (code "428") (name "VSRC6") (class "Default")
      (node (ref "C138") (pin "1") (pinfunction "1_1") (pintype "passive"))
      (node (ref "IC20") (pin "1") (pinfunction "VDD_1") (pintype "power_in"))
      (node (ref "IC32") (pin "13") (pinfunction "ISN_13") (pintype "input"))
      (node (ref "R160") (pin "1") (pinfunction "1_1") (pintype "passive"))
      (node (ref "R169") (pin "1") (pinfunction "1_1") (pintype "passive"))
      (node (ref "R179") (pin "2") (pinfunction "2_2") (pintype "passive"))
      (node (ref "T31") (pin "1") (pinfunction "S_1") (pintype "passive"))
      (node (ref "T31") (pin "2") (pinfunction "S_2") (pintype "passive"))
      (node (ref "T31") (pin "3") (pinfunction "S_3") (pintype "passive"))
      (node (ref "T32") (pin "5") (pinfunction "D_5") (pintype "passive"))
      (node (ref "T32") (pin "6") (pinfunction "D_6") (pintype "passive"))
      (node (ref "T32") (pin "7") (pinfunction "D_7") (pintype "passive"))
      (node (ref "T32") (pin "8") (pinfunction "D_8") (pintype "passive"))
      (node (ref "T32") (pin "9") (pinfunction "D_9") (pintype "passive"))
    )
    (net (code "429") (name "VSRC7") (class "Default")
      (node (ref "C157") (pin "1") (pinfunction "1_1") (pintype "passive"))
      (node (ref "IC23") (pin "1") (pinfunction "VDD_1") (pintype "power_in"))
      (node (ref "IC35") (pin "13") (pinfunction "ISN_13") (pintype "input"))
      (node (ref "R183") (pin "1") (pinfunction "1_1") (pintype "passive"))
      (node (ref "R192") (pin "1") (pinfunction "1_1") (pintype "passive"))
      (node (ref "R202") (pin "2") (pinfunction "2_2") (pintype "passive"))
      (node (ref "T36") (pin "1") (pinfunction "S_1") (pintype "passive"))
      (node (ref "T36") (pin "2") (pinfunction "S_2") (pintype "passive"))
      (node (ref "T36") (pin "3") (pinfunction "S_3") (pintype "passive"))
      (node (ref "T37") (pin "5") (pinfunction "D_5") (pintype "passive"))
      (node (ref "T37") (pin "6") (pinfunction "D_6") (pintype "passive"))
      (node (ref "T37") (pin "7") (pinfunction "D_7") (pintype "passive"))
      (node (ref "T37") (pin "8") (pinfunction "D_8") (pintype "passive"))
      (node (ref "T37") (pin "9") (pinfunction "D_9") (pintype "passive"))
    )
    (net (code "430") (name "VSRC8") (class "Default")
      (node (ref "C197") (pin "1") (pinfunction "1_1") (pintype "passive"))
      (node (ref "IC30") (pin "1") (pinfunction "VDD_1") (pintype "power_in"))
      (node (ref "IC41") (pin "13") (pinfunction "ISN_13") (pintype "input"))
      (node (ref "R219") (pin "1") (pinfunction "1_1") (pintype "passive"))
      (node (ref "R248") (pin "1") (pinfunction "1_1") (pintype "passive"))
      (node (ref "R272") (pin "2") (pinfunction "2_2") (pintype "passive"))
      (node (ref "T41") (pin "1") (pinfunction "S_1") (pintype "passive"))
      (node (ref "T41") (pin "2") (pinfunction "S_2") (pintype "passive"))
      (node (ref "T41") (pin "3") (pinfunction "S_3") (pintype "passive"))
      (node (ref "T42") (pin "5") (pinfunction "D_5") (pintype "passive"))
      (node (ref "T42") (pin "6") (pinfunction "D_6") (pintype "passive"))
      (node (ref "T42") (pin "7") (pinfunction "D_7") (pintype "passive"))
      (node (ref "T42") (pin "8") (pinfunction "D_8") (pintype "passive"))
      (node (ref "T42") (pin "9") (pinfunction "D_9") (pintype "passive"))
    )
    (net (code "431") (name "W5500_MISO") (class "Default")
      (node (ref "IC26") (pin "27") (pinfunction "GPIO16_27") (pintype "bidirectional"))
      (node (ref "IC39") (pin "34") (pinfunction "MISO_34") (pintype "output"))
    )
    (net (code "432") (name "W5500_MOSI") (class "Default")
      (node (ref "IC26") (pin "30") (pinfunction "GPIO19_30") (pintype "bidirectional"))
      (node (ref "IC39") (pin "35") (pinfunction "MOSI_35") (pintype "input"))
    )
    (net (code "433") (name "W5500_SCK") (class "Default")
      (node (ref "IC26") (pin "29") (pinfunction "GPIO18_29") (pintype "bidirectional"))
      (node (ref "IC39") (pin "33") (pinfunction "SCLK_33") (pintype "input"))
    )
    (net (code "434") (name "unconnected-(IC12-CC_N-Pad6)") (class "Default")
      (node (ref "IC12") (pin "6") (pinfunction "CC_N_6") (pintype "output"))
    )
    (net (code "435") (name "unconnected-(IC12-PG-Pad5)") (class "Default")
      (node (ref "IC12") (pin "5") (pinfunction "PG_5") (pintype "output"))
    )
    (net (code "436") (name "unconnected-(IC15-CC_N-Pad6)") (class "Default")
      (node (ref "IC15") (pin "6") (pinfunction "CC_N_6") (pintype "output"))
    )
    (net (code "437") (name "unconnected-(IC15-PG-Pad5)") (class "Default")
      (node (ref "IC15") (pin "5") (pinfunction "PG_5") (pintype "output"))
    )
    (net (code "438") (name "unconnected-(IC18-CC_N-Pad6)") (class "Default")
      (node (ref "IC18") (pin "6") (pinfunction "CC_N_6") (pintype "output"))
    )
    (net (code "439") (name "unconnected-(IC18-PG-Pad5)") (class "Default")
      (node (ref "IC18") (pin "5") (pinfunction "PG_5") (pintype "output"))
    )
    (net (code "440") (name "unconnected-(IC21-CC_N-Pad6)") (class "Default")
      (node (ref "IC21") (pin "6") (pinfunction "CC_N_6") (pintype "output"))
    )
    (net (code "441") (name "unconnected-(IC21-PG-Pad5)") (class "Default")
      (node (ref "IC21") (pin "5") (pinfunction "PG_5") (pintype "output"))
    )
    (net (code "442") (name "unconnected-(IC24-CC_N-Pad6)") (class "Default")
      (node (ref "IC24") (pin "6") (pinfunction "CC_N_6") (pintype "output"))
    )
    (net (code "443") (name "unconnected-(IC24-PG-Pad5)") (class "Default")
      (node (ref "IC24") (pin "5") (pinfunction "PG_5") (pintype "output"))
    )
    (net (code "444") (name "unconnected-(IC26-GPIO25-Pad37)") (class "Default")
      (node (ref "IC26") (pin "37") (pinfunction "GPIO25_37") (pintype "bidirectional"))
    )
    (net (code "445") (name "unconnected-(IC26-GPIO26{slash}ADC0-Pad38)") (class "Default")
      (node (ref "IC26") (pin "38") (pinfunction "GPIO26/ADC0_38") (pintype "bidirectional"))
    )
    (net (code "446") (name "unconnected-(IC26-GPIO27{slash}ADC1-Pad39)") (class "Default")
      (node (ref "IC26") (pin "39") (pinfunction "GPIO27/ADC1_39") (pintype "bidirectional"))
    )
    (net (code "447") (name "unconnected-(IC26-GPIO28{slash}ADC2-Pad40)") (class "Default")
      (node (ref "IC26") (pin "40") (pinfunction "GPIO28/ADC2_40") (pintype "bidirectional"))
    )
    (net (code "448") (name "unconnected-(IC26-GPIO29{slash}ADC3-Pad41)") (class "Default")
      (node (ref "IC26") (pin "41") (pinfunction "GPIO29/ADC3_41") (pintype "bidirectional"))
    )
    (net (code "449") (name "unconnected-(IC32-CC_N-Pad6)") (class "Default")
      (node (ref "IC32") (pin "6") (pinfunction "CC_N_6") (pintype "output"))
    )
    (net (code "450") (name "unconnected-(IC32-PG-Pad5)") (class "Default")
      (node (ref "IC32") (pin "5") (pinfunction "PG_5") (pintype "output"))
    )
    (net (code "451") (name "unconnected-(IC35-CC_N-Pad6)") (class "Default")
      (node (ref "IC35") (pin "6") (pinfunction "CC_N_6") (pintype "output"))
    )
    (net (code "452") (name "unconnected-(IC35-PG-Pad5)") (class "Default")
      (node (ref "IC35") (pin "5") (pinfunction "PG_5") (pintype "output"))
    )
    (net (code "453") (name "unconnected-(IC39-DNC-Pad7)") (class "Default")
      (node (ref "IC39") (pin "7") (pinfunction "DNC_7") (pintype "bidirectional"))
    )
    (net (code "454") (name "unconnected-(IC39-DUPLED-Pad26)") (class "Default")
      (node (ref "IC39") (pin "26") (pinfunction "DUPLED_26") (pintype "output"))
    )
    (net (code "455") (name "unconnected-(IC39-RSVD1-Pad23)") (class "Default")
      (node (ref "IC39") (pin "23") (pinfunction "RSVD1_23") (pintype "input"))
    )
    (net (code "456") (name "unconnected-(IC39-RSVD2-Pad38)") (class "Default")
      (node (ref "IC39") (pin "38") (pinfunction "RSVD2_38") (pintype "input"))
    )
    (net (code "457") (name "unconnected-(IC39-RSVD3-Pad39)") (class "Default")
      (node (ref "IC39") (pin "39") (pinfunction "RSVD3_39") (pintype "input"))
    )
    (net (code "458") (name "unconnected-(IC39-RSVD4-Pad40)") (class "Default")
      (node (ref "IC39") (pin "40") (pinfunction "RSVD4_40") (pintype "input"))
    )
    (net (code "459") (name "unconnected-(IC39-RSVD5-Pad41)") (class "Default")
      (node (ref "IC39") (pin "41") (pinfunction "RSVD5_41") (pintype "input"))
    )
    (net (code "460") (name "unconnected-(IC39-RSVD6-Pad42)") (class "Default")
      (node (ref "IC39") (pin "42") (pinfunction "RSVD6_42") (pintype "input"))
    )
    (net (code "461") (name "unconnected-(IC39-SPDLED-Pad24)") (class "Default")
      (node (ref "IC39") (pin "24") (pinfunction "SPDLED_24") (pintype "output"))
    )
    (net (code "462") (name "unconnected-(IC39-VBG-Pad18)") (class "Default")
      (node (ref "IC39") (pin "18") (pinfunction "VBG_18") (pintype "output"))
    )
    (net (code "463") (name "unconnected-(IC41-CC_N-Pad6)") (class "Default")
      (node (ref "IC41") (pin "6") (pinfunction "CC_N_6") (pintype "output"))
    )
    (net (code "464") (name "unconnected-(IC41-PG-Pad5)") (class "Default")
      (node (ref "IC41") (pin "5") (pinfunction "PG_5") (pintype "output"))
    )
    (net (code "465") (name "unconnected-(IC42-INTA-Pad16)") (class "Default")
      (node (ref "IC42") (pin "16") (pinfunction "INTA_16") (pintype "bidirectional"))
    )
    (net (code "466") (name "unconnected-(IC42-INTB-Pad15)") (class "Default")
      (node (ref "IC42") (pin "15") (pinfunction "INTB_15") (pintype "bidirectional"))
    )
    (net (code "467") (name "unconnected-(R253-Pad5)") (class "Default")
      (node (ref "R253") (pin "5") (pinfunction "5_5") (pintype "passive"))
    )
    (net (code "468") (name "unconnected-(USB9-SBU1-PadA8)") (class "Default")
      (node (ref "USB9") (pin "A8") (pinfunction "SBU1_A8") (pintype "bidirectional"))
    )
    (net (code "469") (name "unconnected-(USB9-SBU2-PadB8)") (class "Default")
      (node (ref "USB9") (pin "B8") (pinfunction "SBU2_B8") (pintype "bidirectional"))
    )
    (net (code "470") (name "unconnected-(USBA_1-2A-D+-Pad3)") (class "Default")
      (node (ref "USBA_1-2") (pin "3") (pinfunction "D+_3") (pintype "passive"))
    )
    (net (code "471") (name "unconnected-(USBA_1-2A-D--Pad2)") (class "Default")
      (node (ref "USBA_1-2") (pin "2") (pinfunction "D-_2") (pintype "passive"))
    )
    (net (code "472") (name "unconnected-(USBA_1-2B-D+-Pad7)") (class "Default")
      (node (ref "USBA_1-2") (pin "7") (pinfunction "D+_7") (pintype "passive"))
    )
    (net (code "473") (name "unconnected-(USBA_1-2B-D--Pad6)") (class "Default")
      (node (ref "USBA_1-2") (pin "6") (pinfunction "D-_6") (pintype "passive"))
    )
    (net (code "474") (name "unconnected-(USBA_3-4A-D+-Pad3)") (class "Default")
      (node (ref "USBA_3-4") (pin "3") (pinfunction "D+_3") (pintype "passive"))
    )
    (net (code "475") (name "unconnected-(USBA_3-4A-D--Pad2)") (class "Default")
      (node (ref "USBA_3-4") (pin "2") (pinfunction "D-_2") (pintype "passive"))
    )
    (net (code "476") (name "unconnected-(USBA_3-4B-D+-Pad7)") (class "Default")
      (node (ref "USBA_3-4") (pin "7") (pinfunction "D+_7") (pintype "passive"))
    )
    (net (code "477") (name "unconnected-(USBA_3-4B-D--Pad6)") (class "Default")
      (node (ref "USBA_3-4") (pin "6") (pinfunction "D-_6") (pintype "passive"))
    )
    (net (code "478") (name "~{ACT}") (class "Default")
      (node (ref "IC39") (pin "27") (pinfunction "ACTLED_27") (pintype "output"))
      (node (ref "R238") (pin "1") (pinfunction "1_1") (pintype "passive"))
    )
    (net (code "479") (name "~{LINK}") (class "Default")
      (node (ref "IC39") (pin "25") (pinfunction "LINKLED_25") (pintype "output"))
      (node (ref "R237") (pin "1") (pinfunction "1_1") (pintype "passive"))
    )
    (net (code "480") (name "~{QSPI_SS}") (class "Default")
      (node (ref "IC26") (pin "56") (pinfunction "QSPI_SS_N_56") (pintype "bidirectional"))
      (node (ref "IC27") (pin "1") (pinfunction "~{CS}_1") (pintype "bidirectional"))
      (node (ref "R209") (pin "1") (pinfunction "1_1") (pintype "passive"))
      (node (ref "R210") (pin "2") (pinfunction "2_2") (pintype "passive"))
    )
    (net (code "481") (name "~{TCA_RST}") (class "Default")
      (node (ref "IC26") (pin "36") (pinfunction "GPIO24_36") (pintype "bidirectional"))
      (node (ref "IC38") (pin "24") (pinfunction "RESET_24") (pintype "input"))
    )
    (net (code "482") (name "~{W5500_CS}") (class "Default")
      (node (ref "IC26") (pin "28") (pinfunction "GPIO17_28") (pintype "bidirectional"))
      (node (ref "IC39") (pin "32") (pinfunction "~{SCSN}_32") (pintype "input"))
    )
    (net (code "483") (name "~{W5500_INT}") (class "Default")
      (node (ref "IC26") (pin "32") (pinfunction "GPIO21_32") (pintype "bidirectional"))
      (node (ref "IC39") (pin "36") (pinfunction "~{INTN}_36") (pintype "input"))
    )
    (net (code "484") (name "~{W5500_RST}") (class "Default")
      (node (ref "IC26") (pin "31") (pinfunction "GPIO20_31") (pintype "bidirectional"))
      (node (ref "IC39") (pin "37") (pinfunction "~{RSTN}_37") (pintype "input"))
      (node (ref "R236") (pin "1") (pinfunction "1_1") (pintype "passive"))
    )
  )
)
